# DMFX-1_v1_1.net
KiCad netlist of a schematic drawn in EAGLE
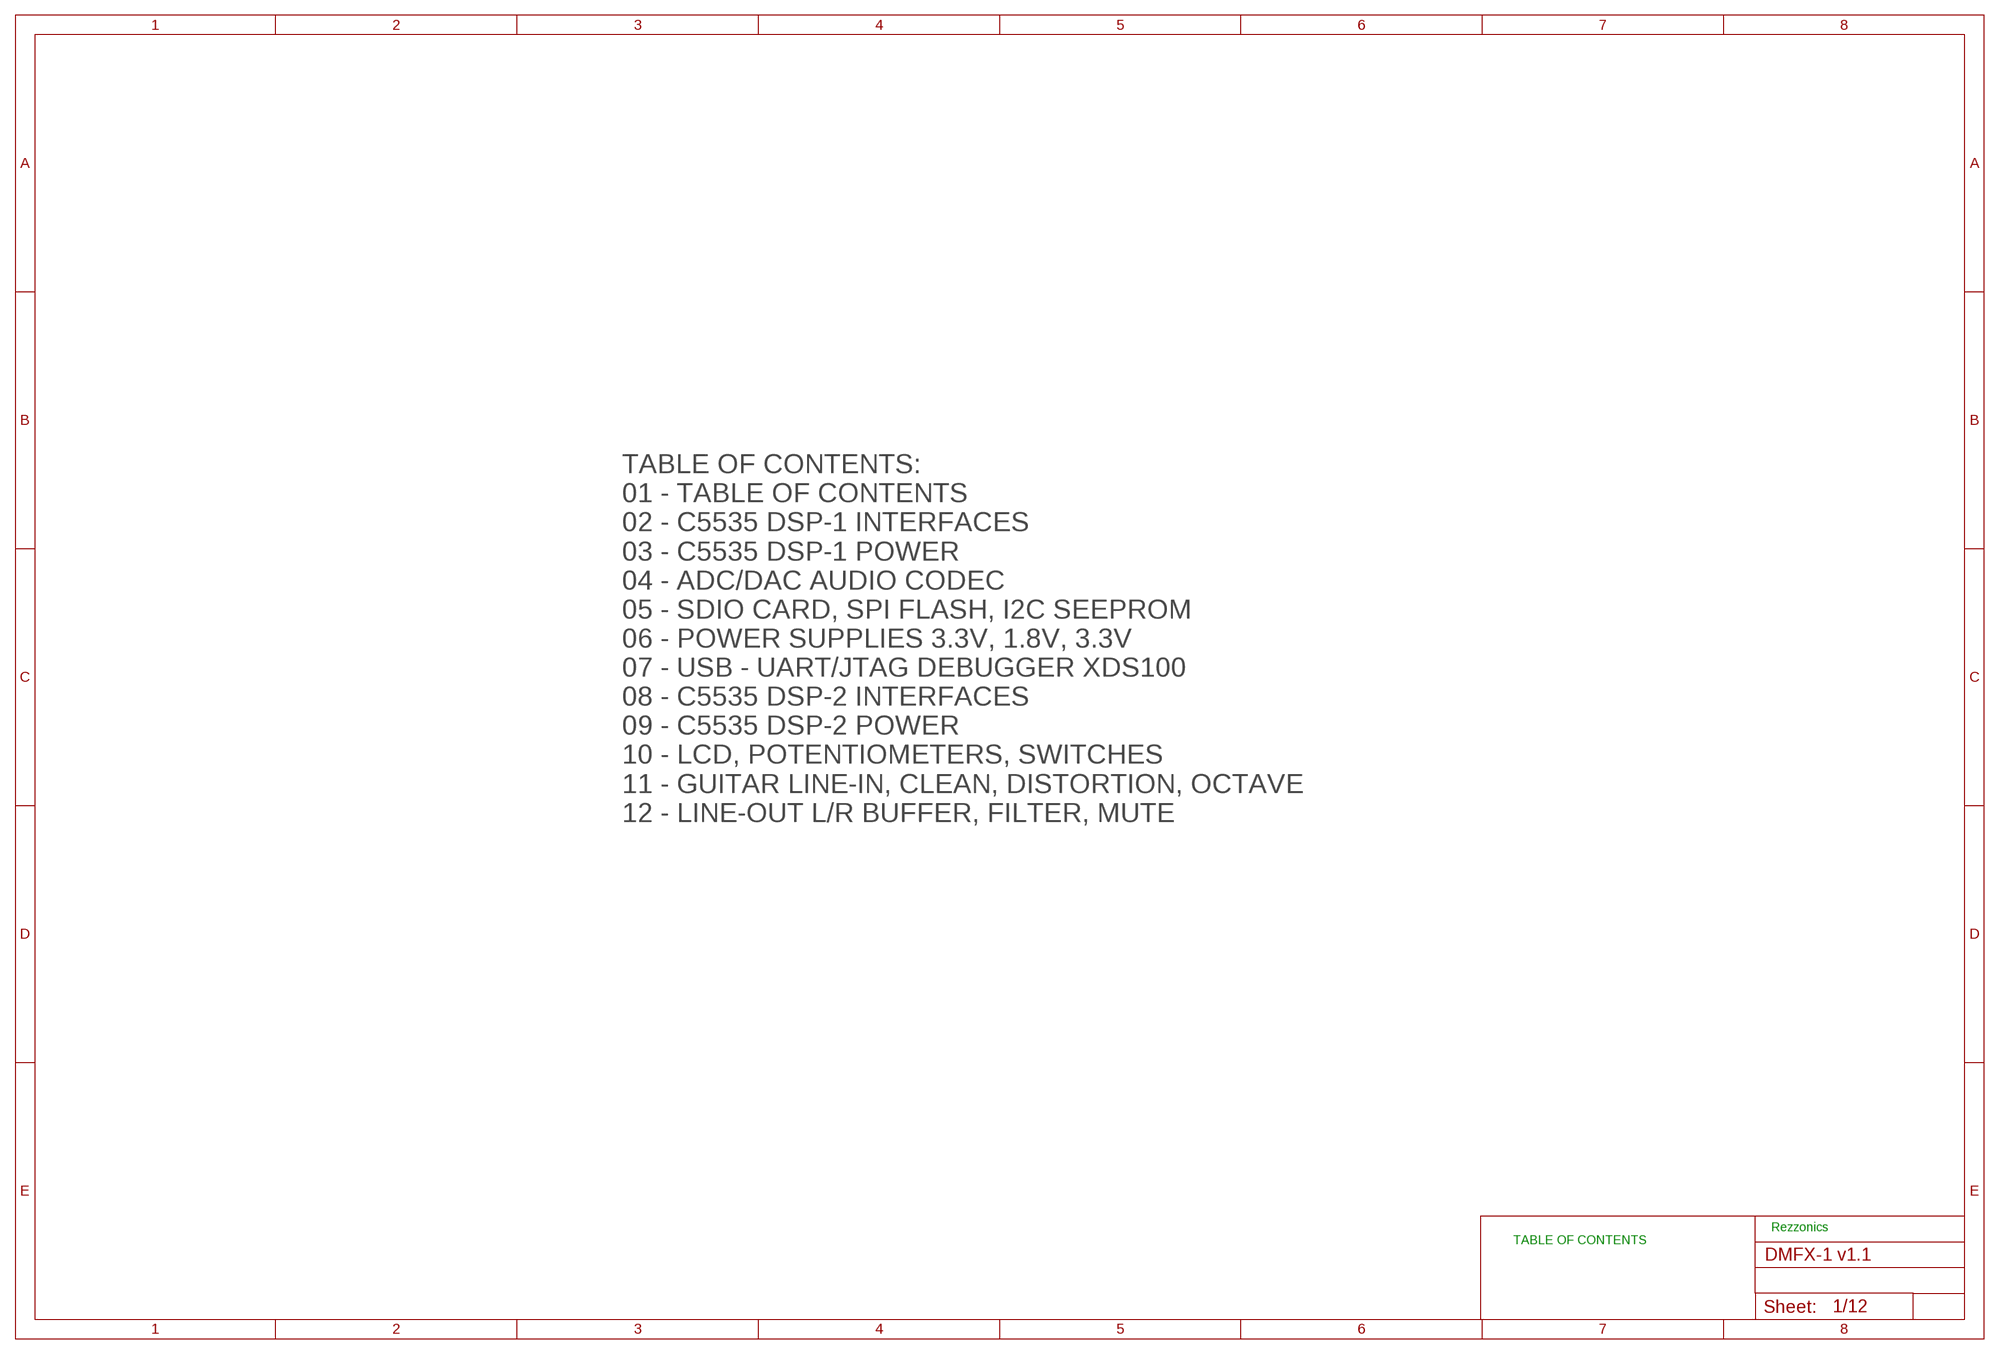
[diagram p0: schematic, sheet 1]
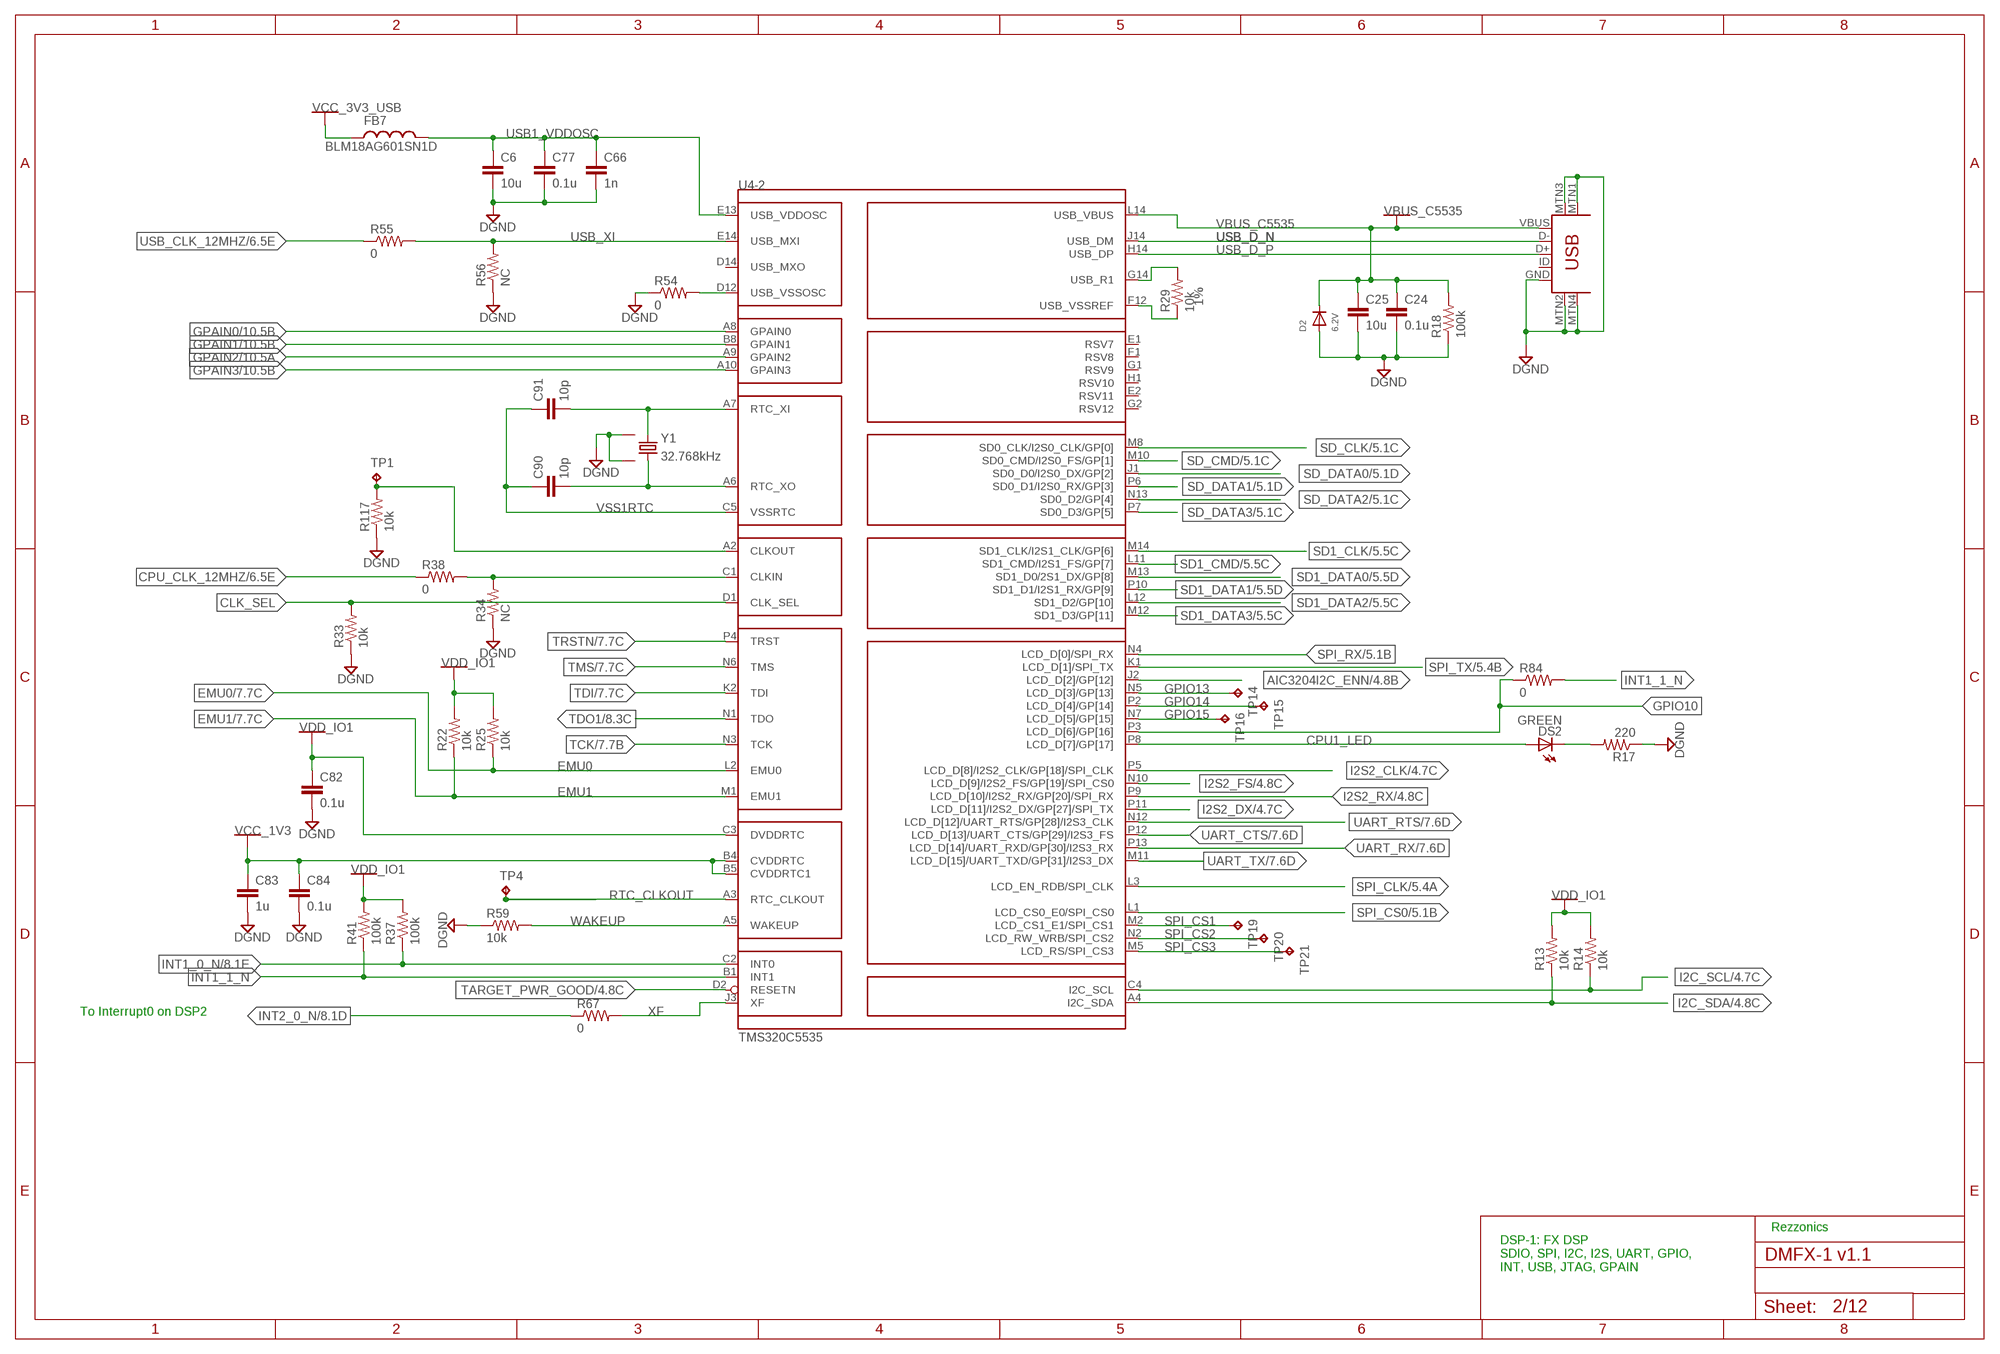
[diagram p1: schematic, sheet 2]
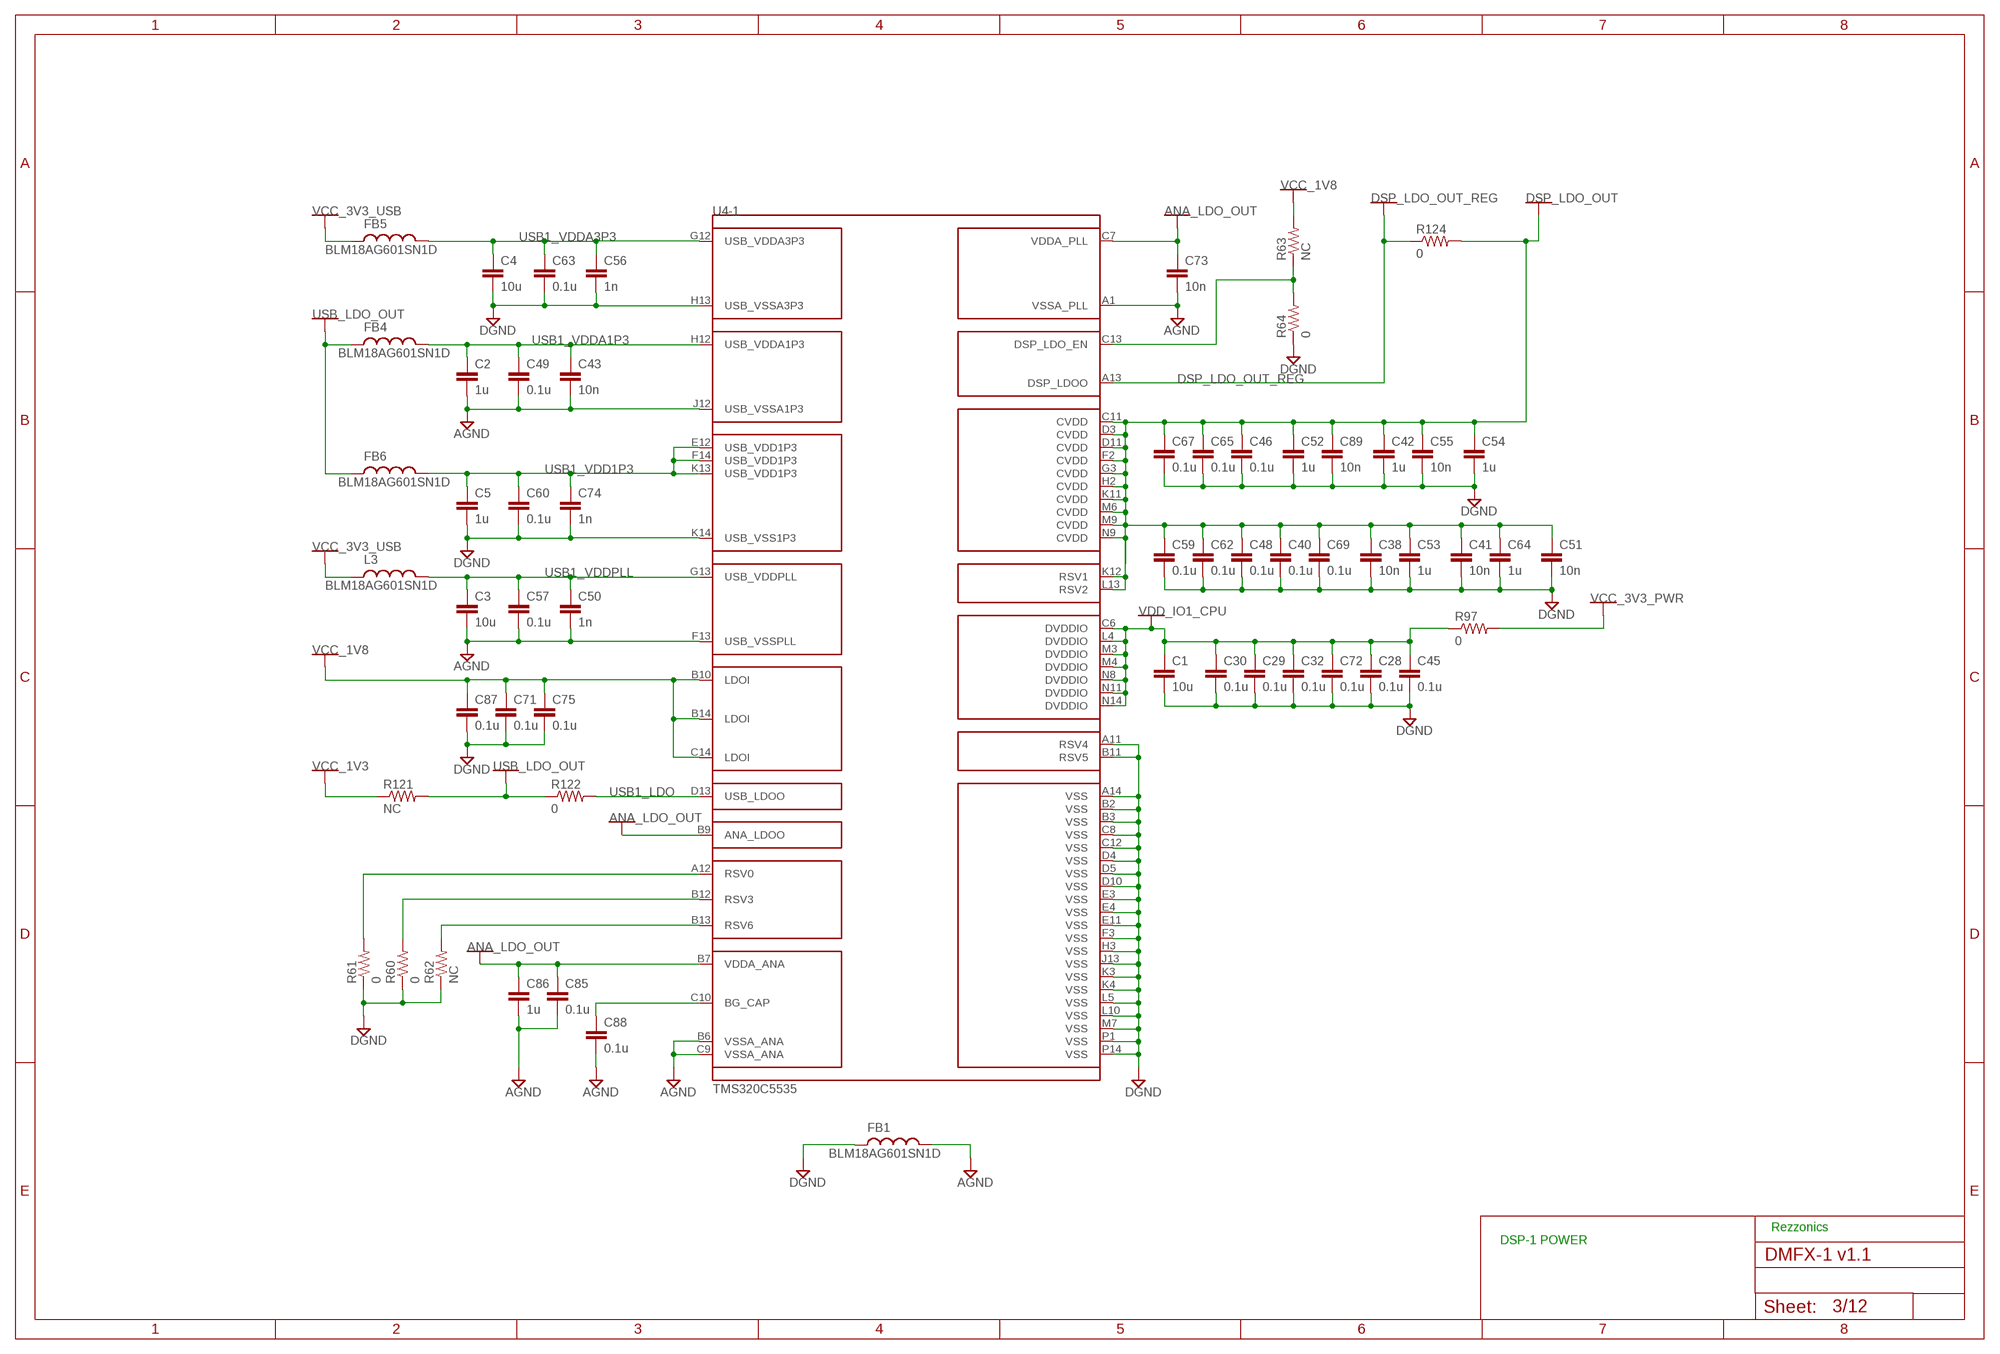
[diagram p2: schematic, sheet 3]
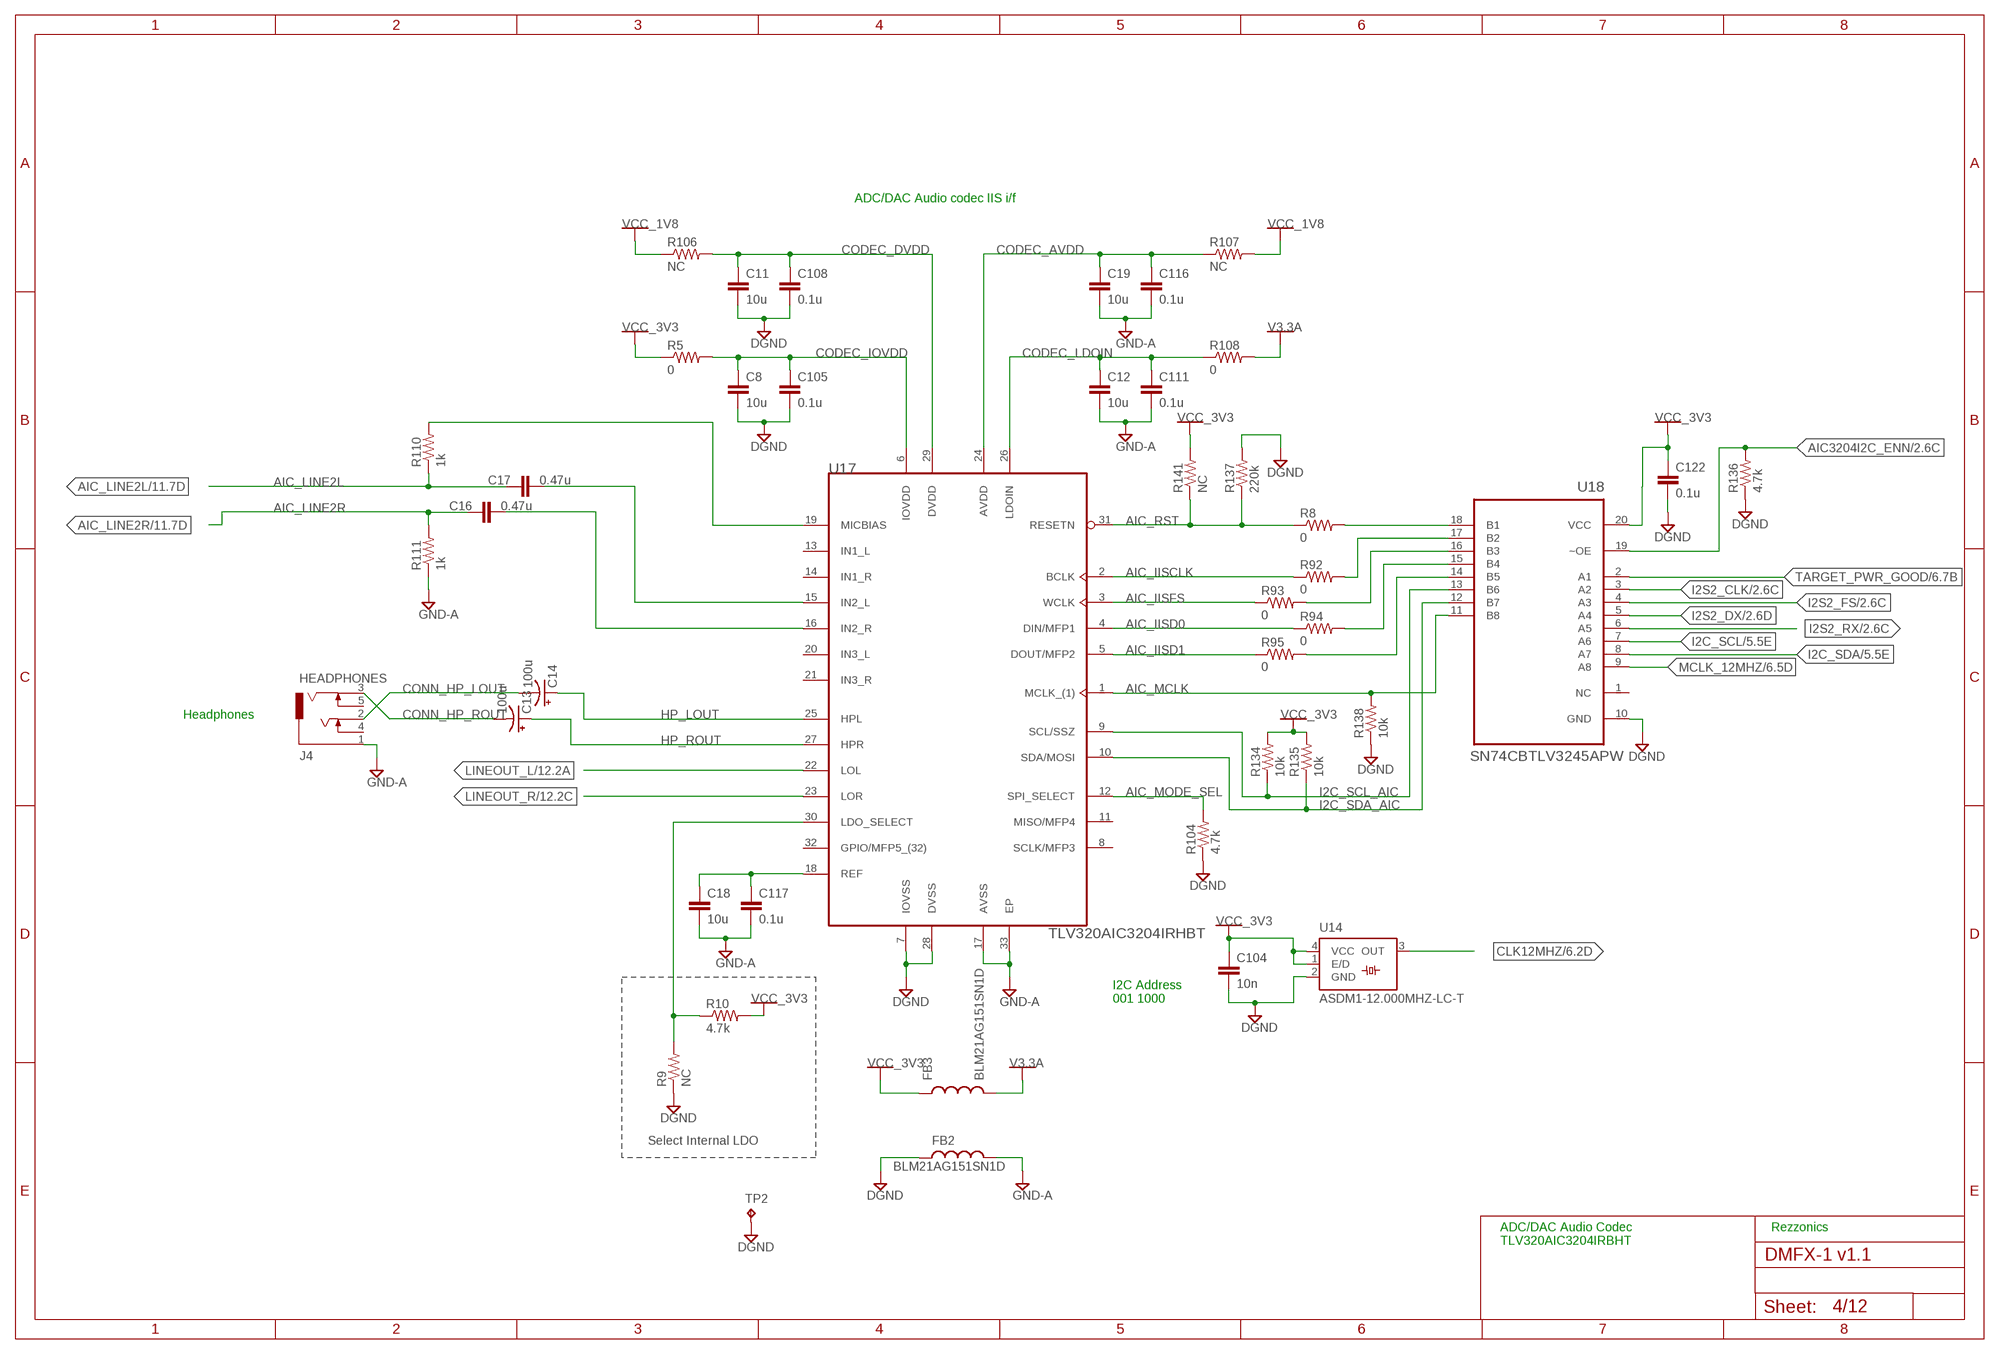
[diagram p3: schematic, sheet 4]
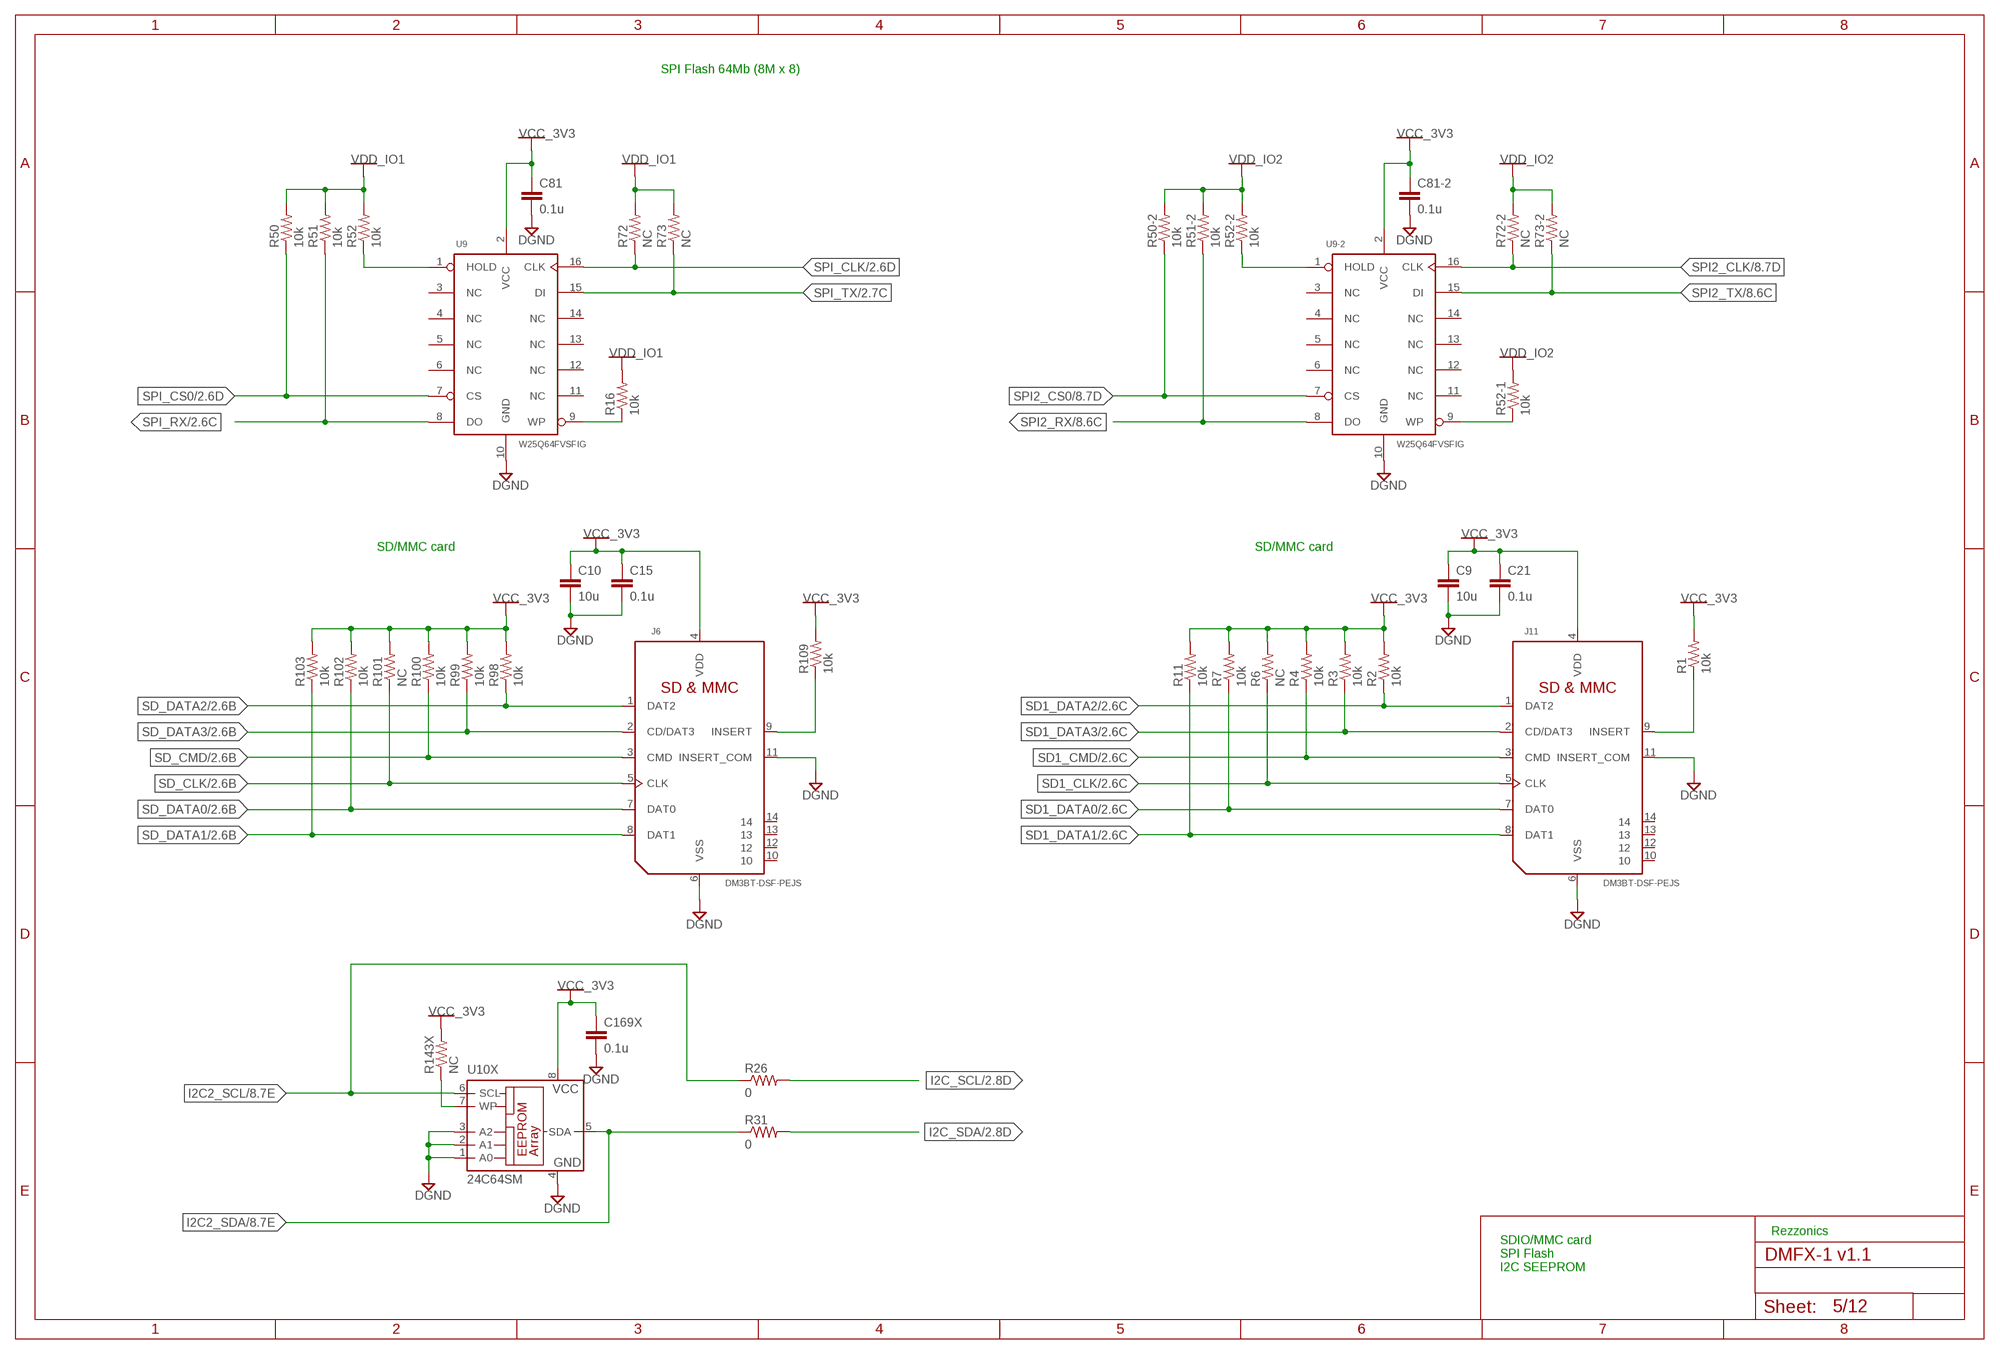
[diagram p4: schematic, sheet 5]
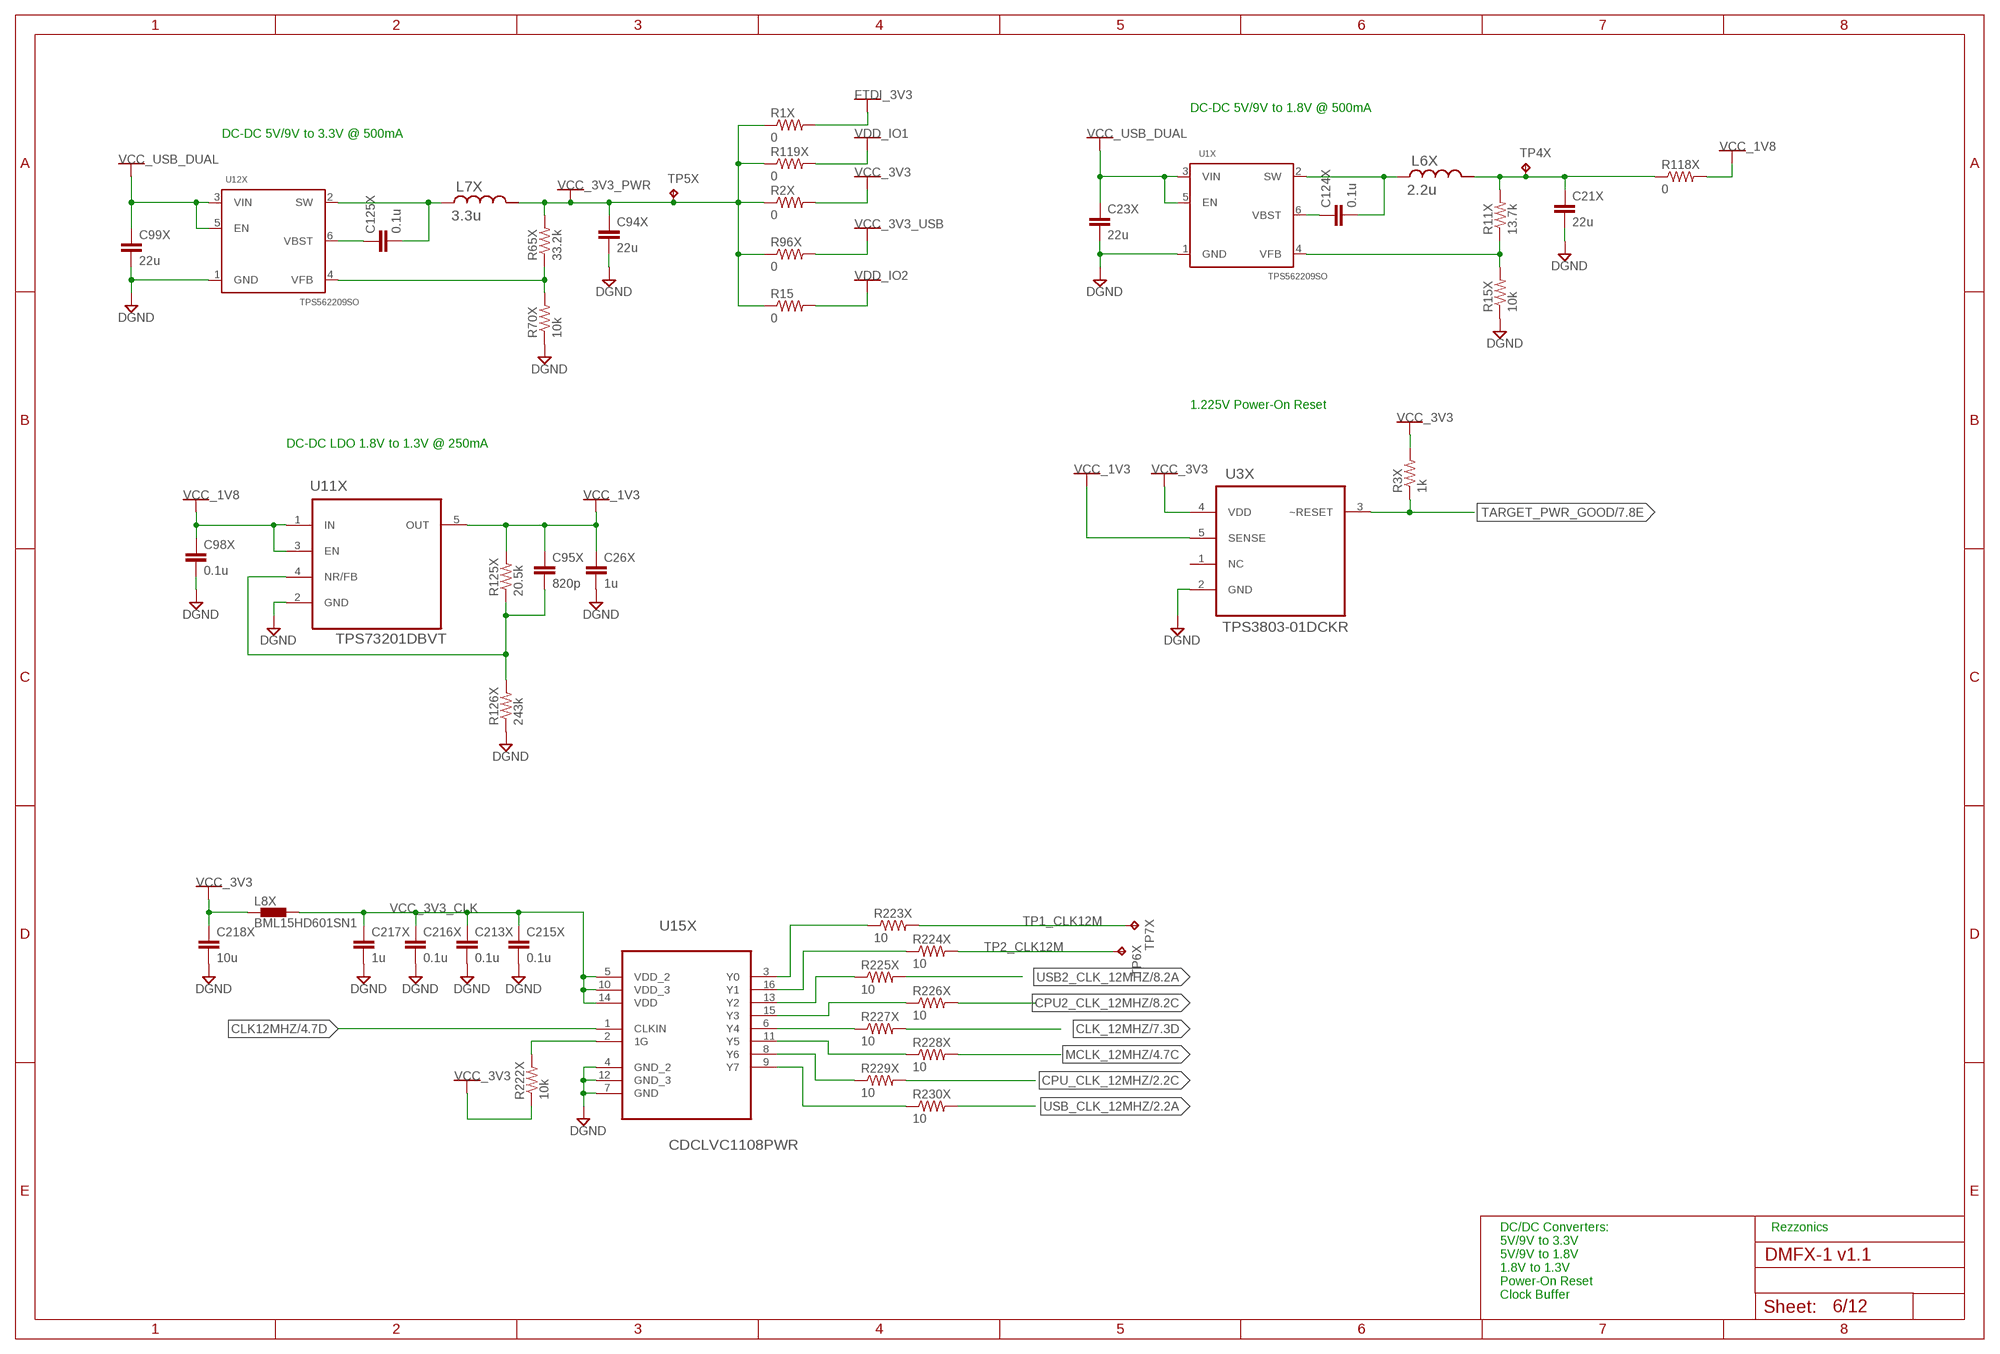
[diagram p5: schematic, sheet 6]
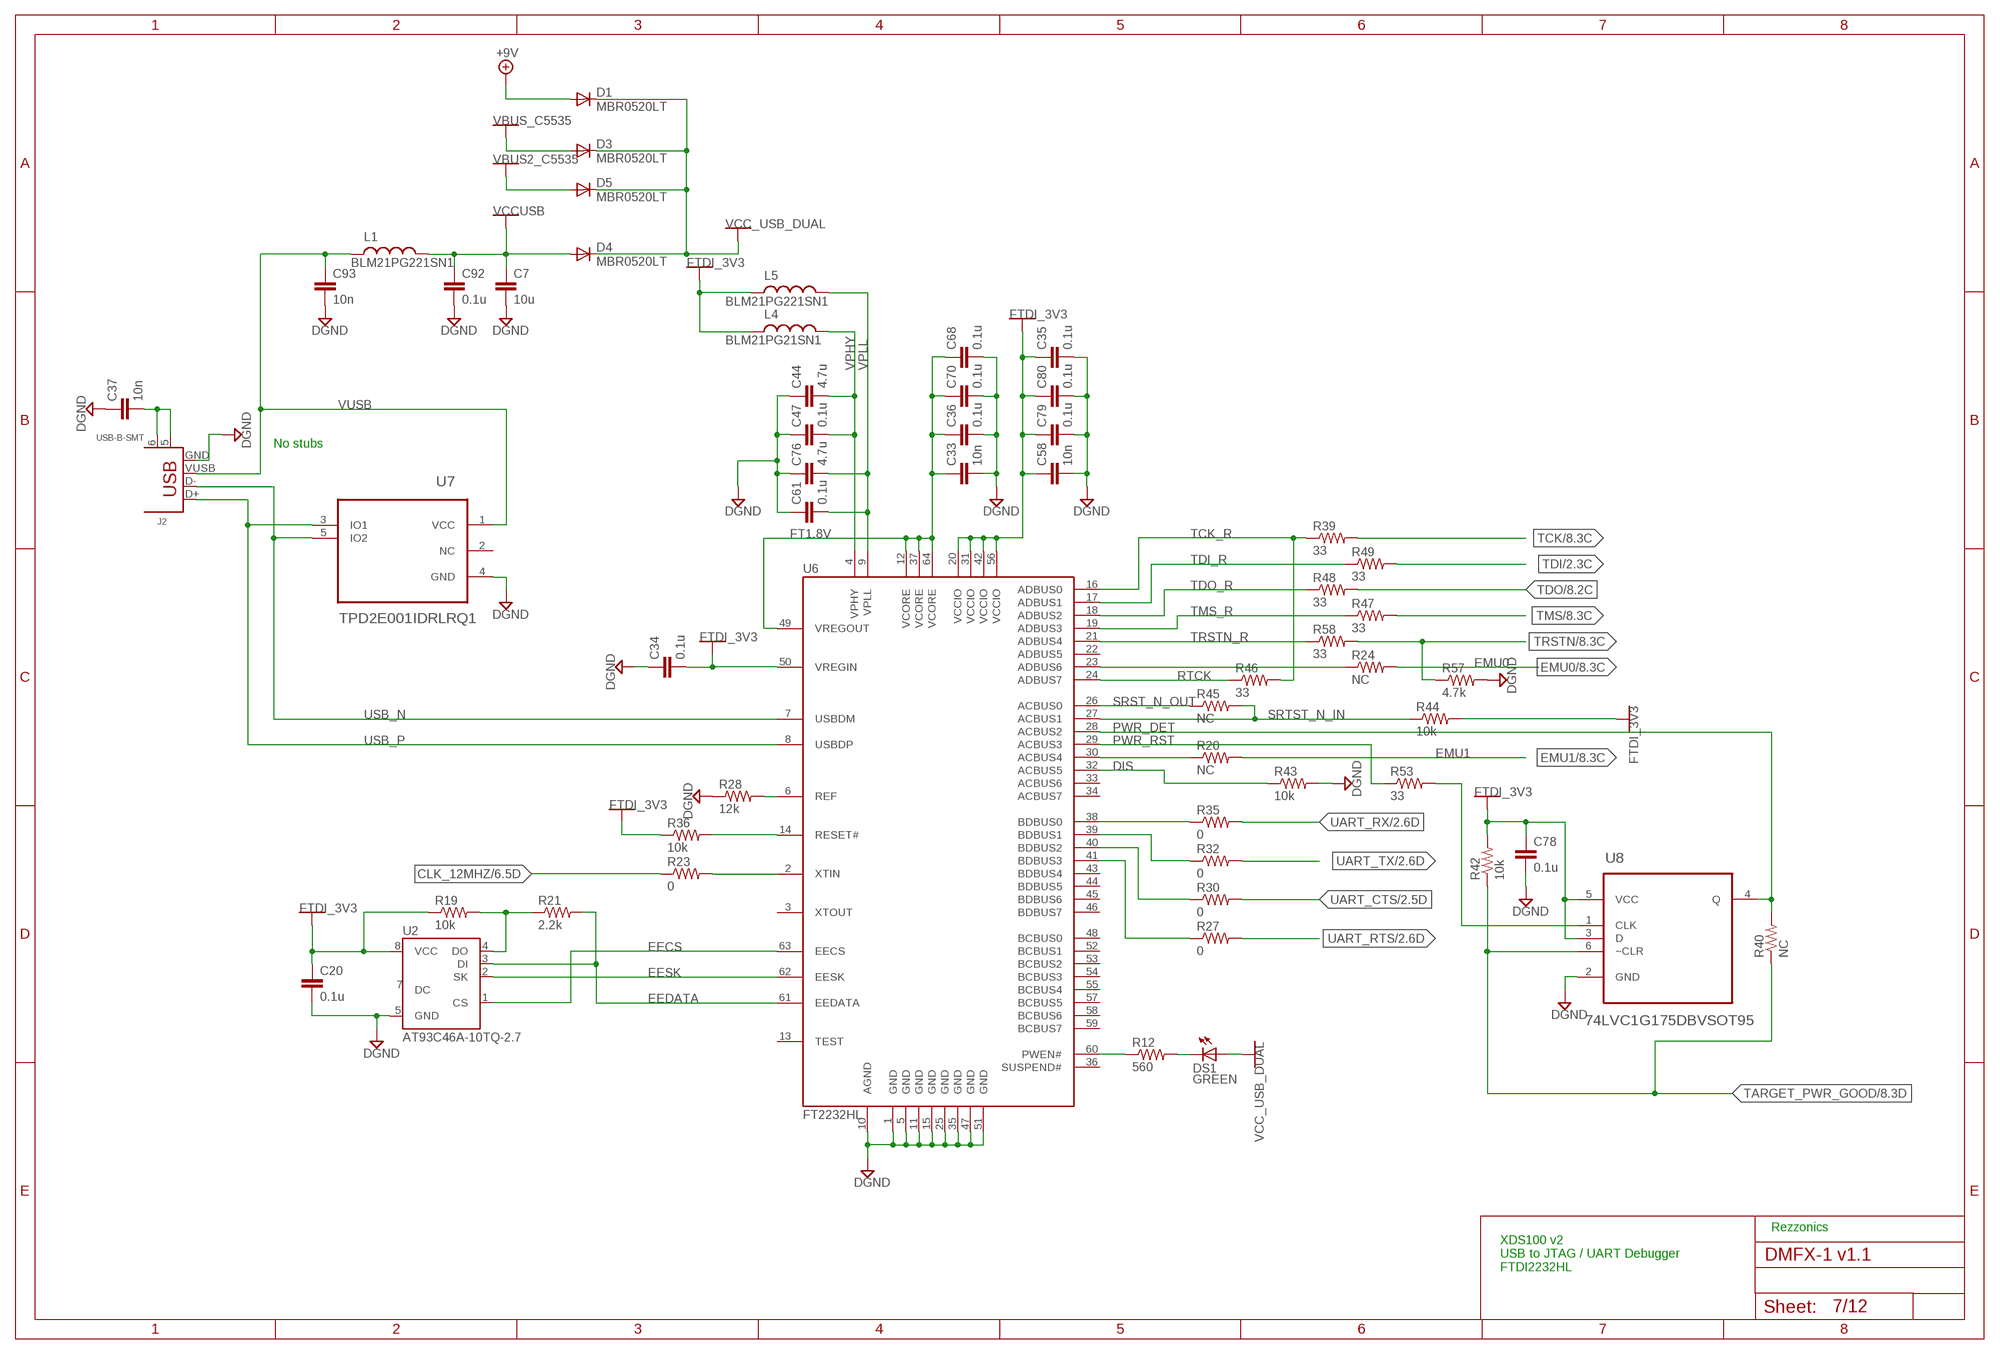
[diagram p6: schematic, sheet 7]
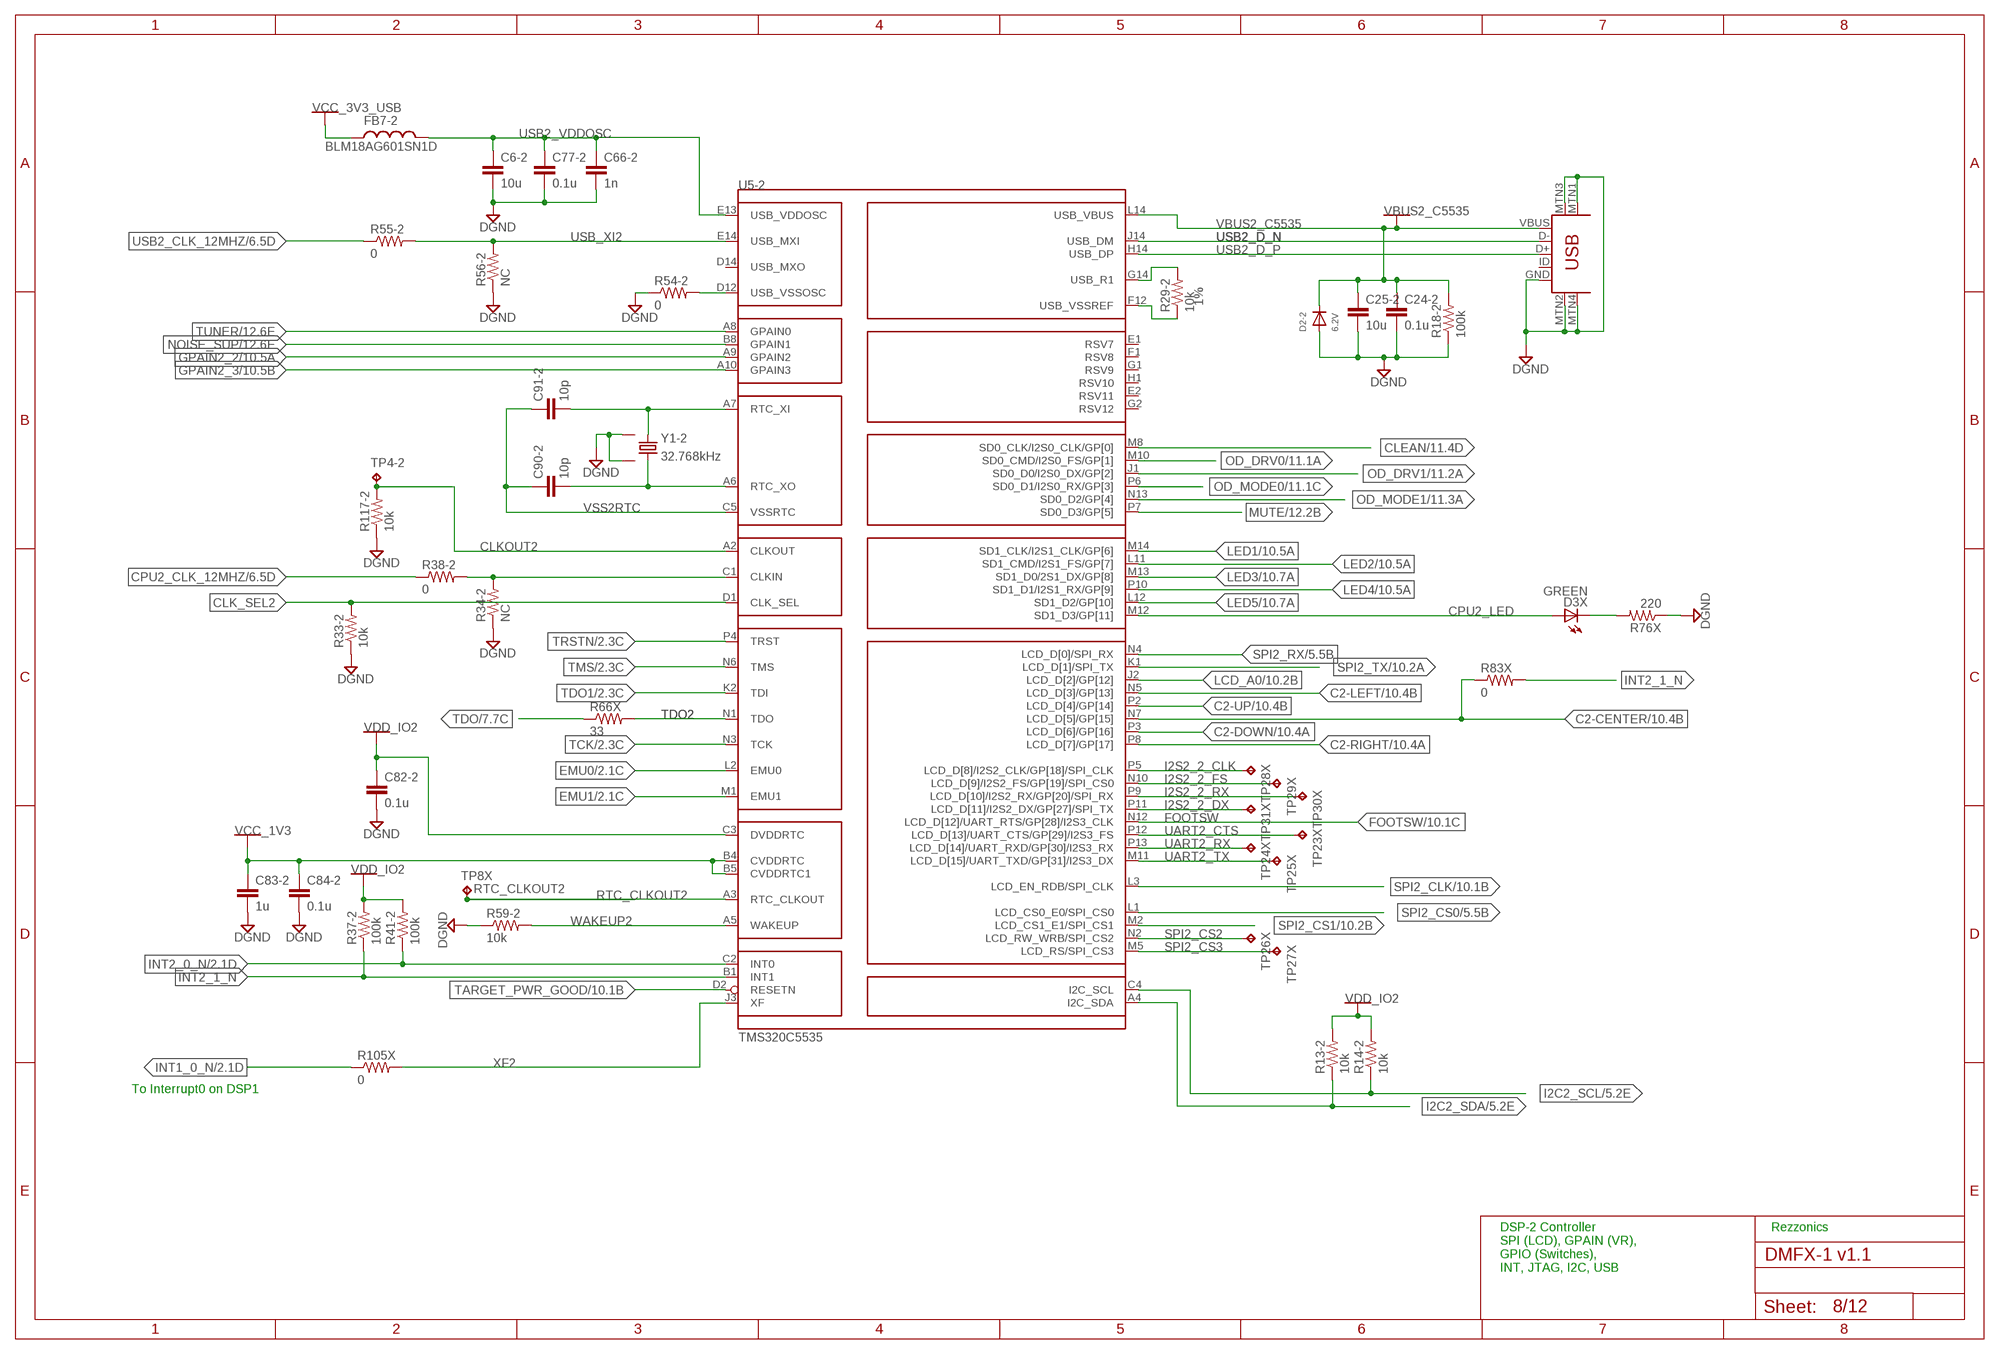
[diagram p7: schematic, sheet 8]
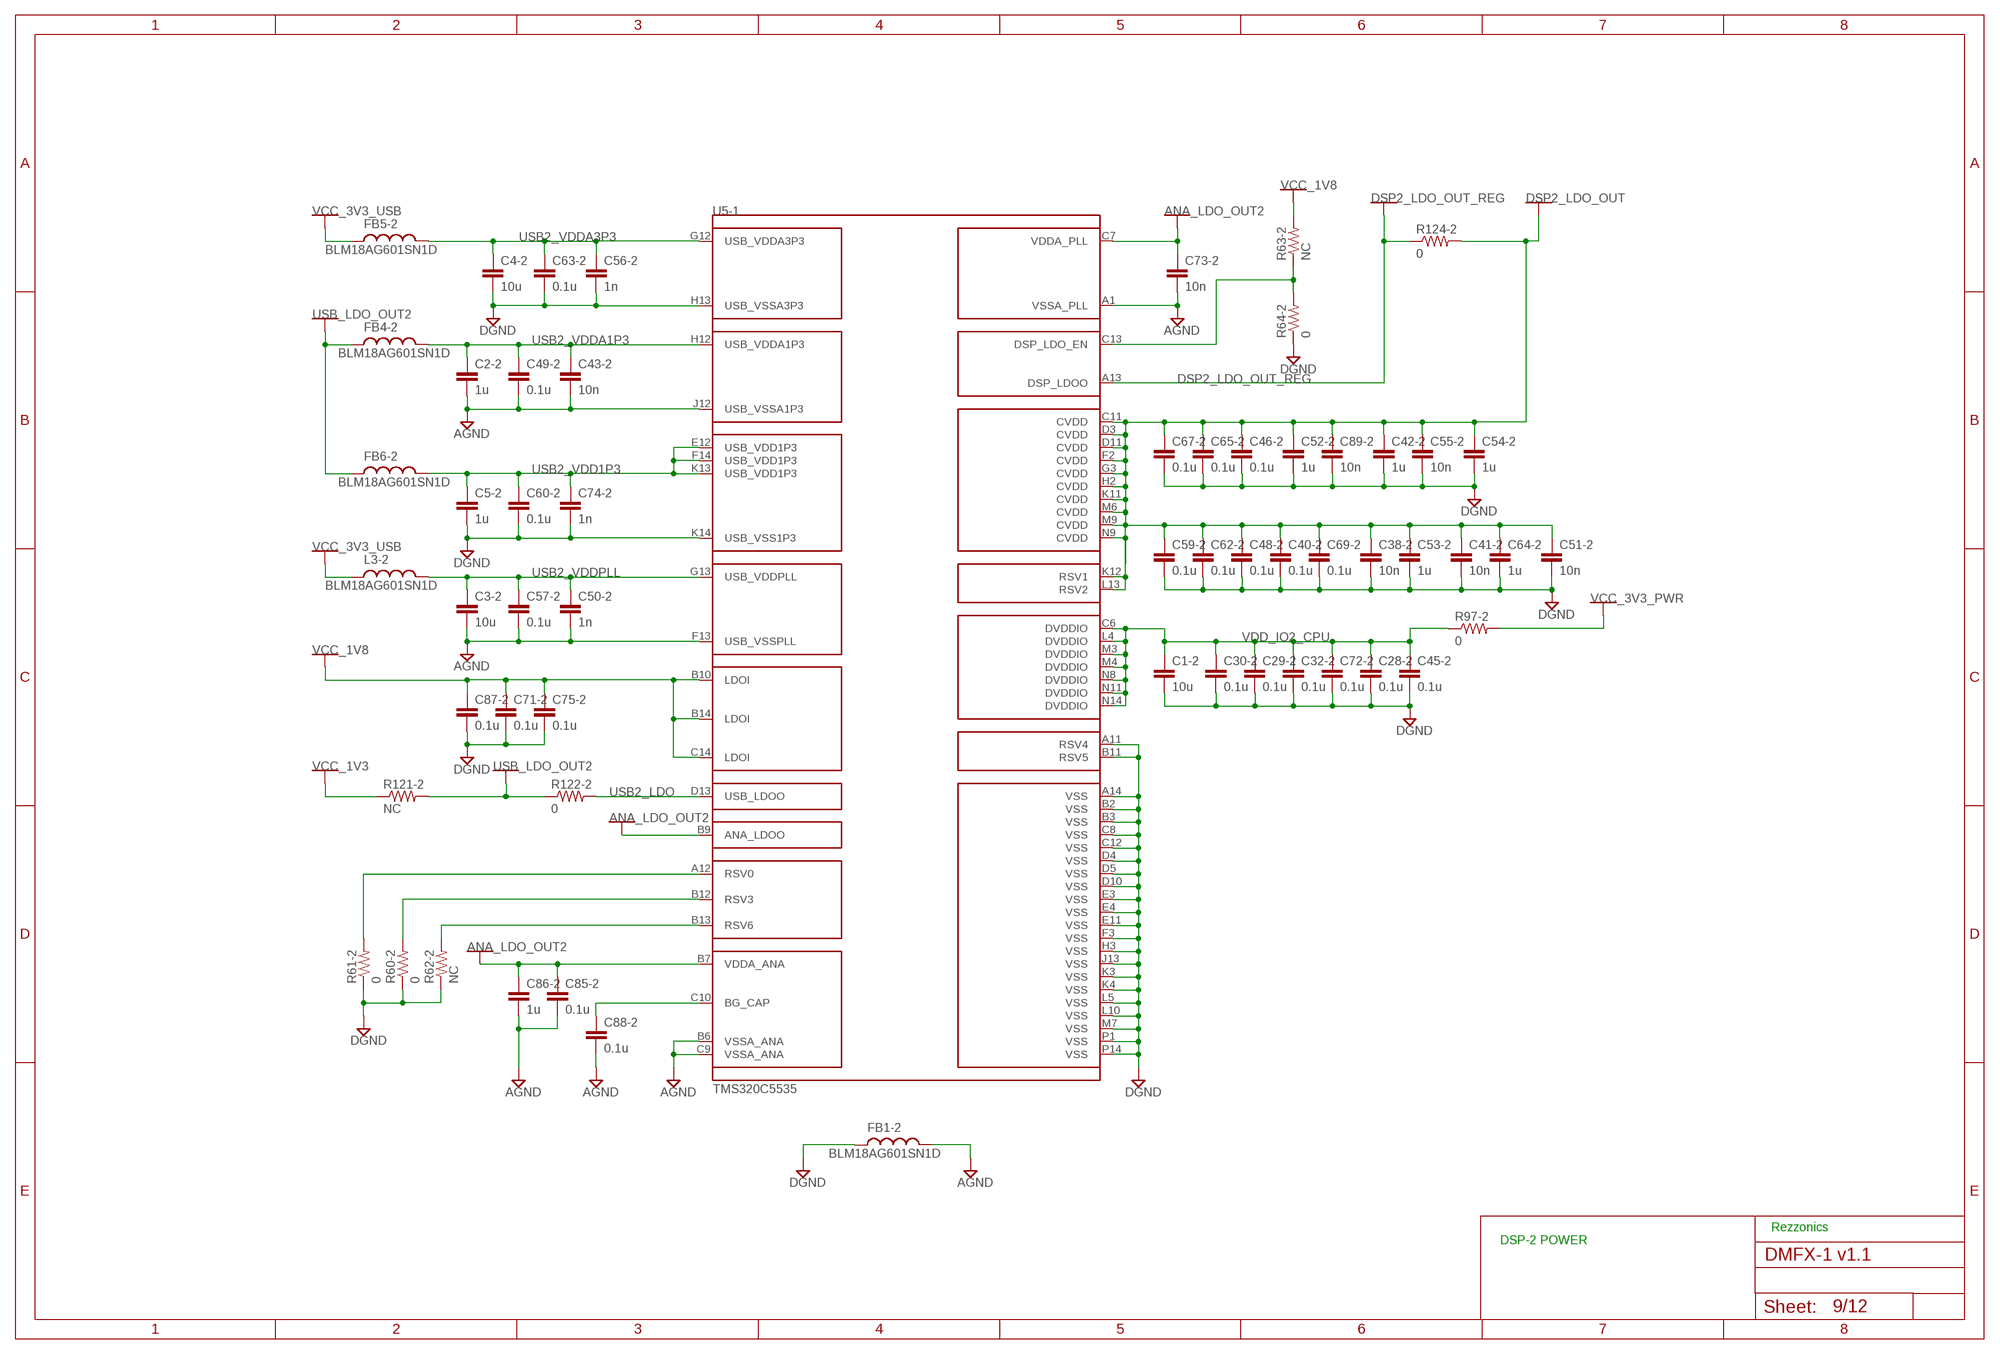
[diagram p8: schematic, sheet 9]
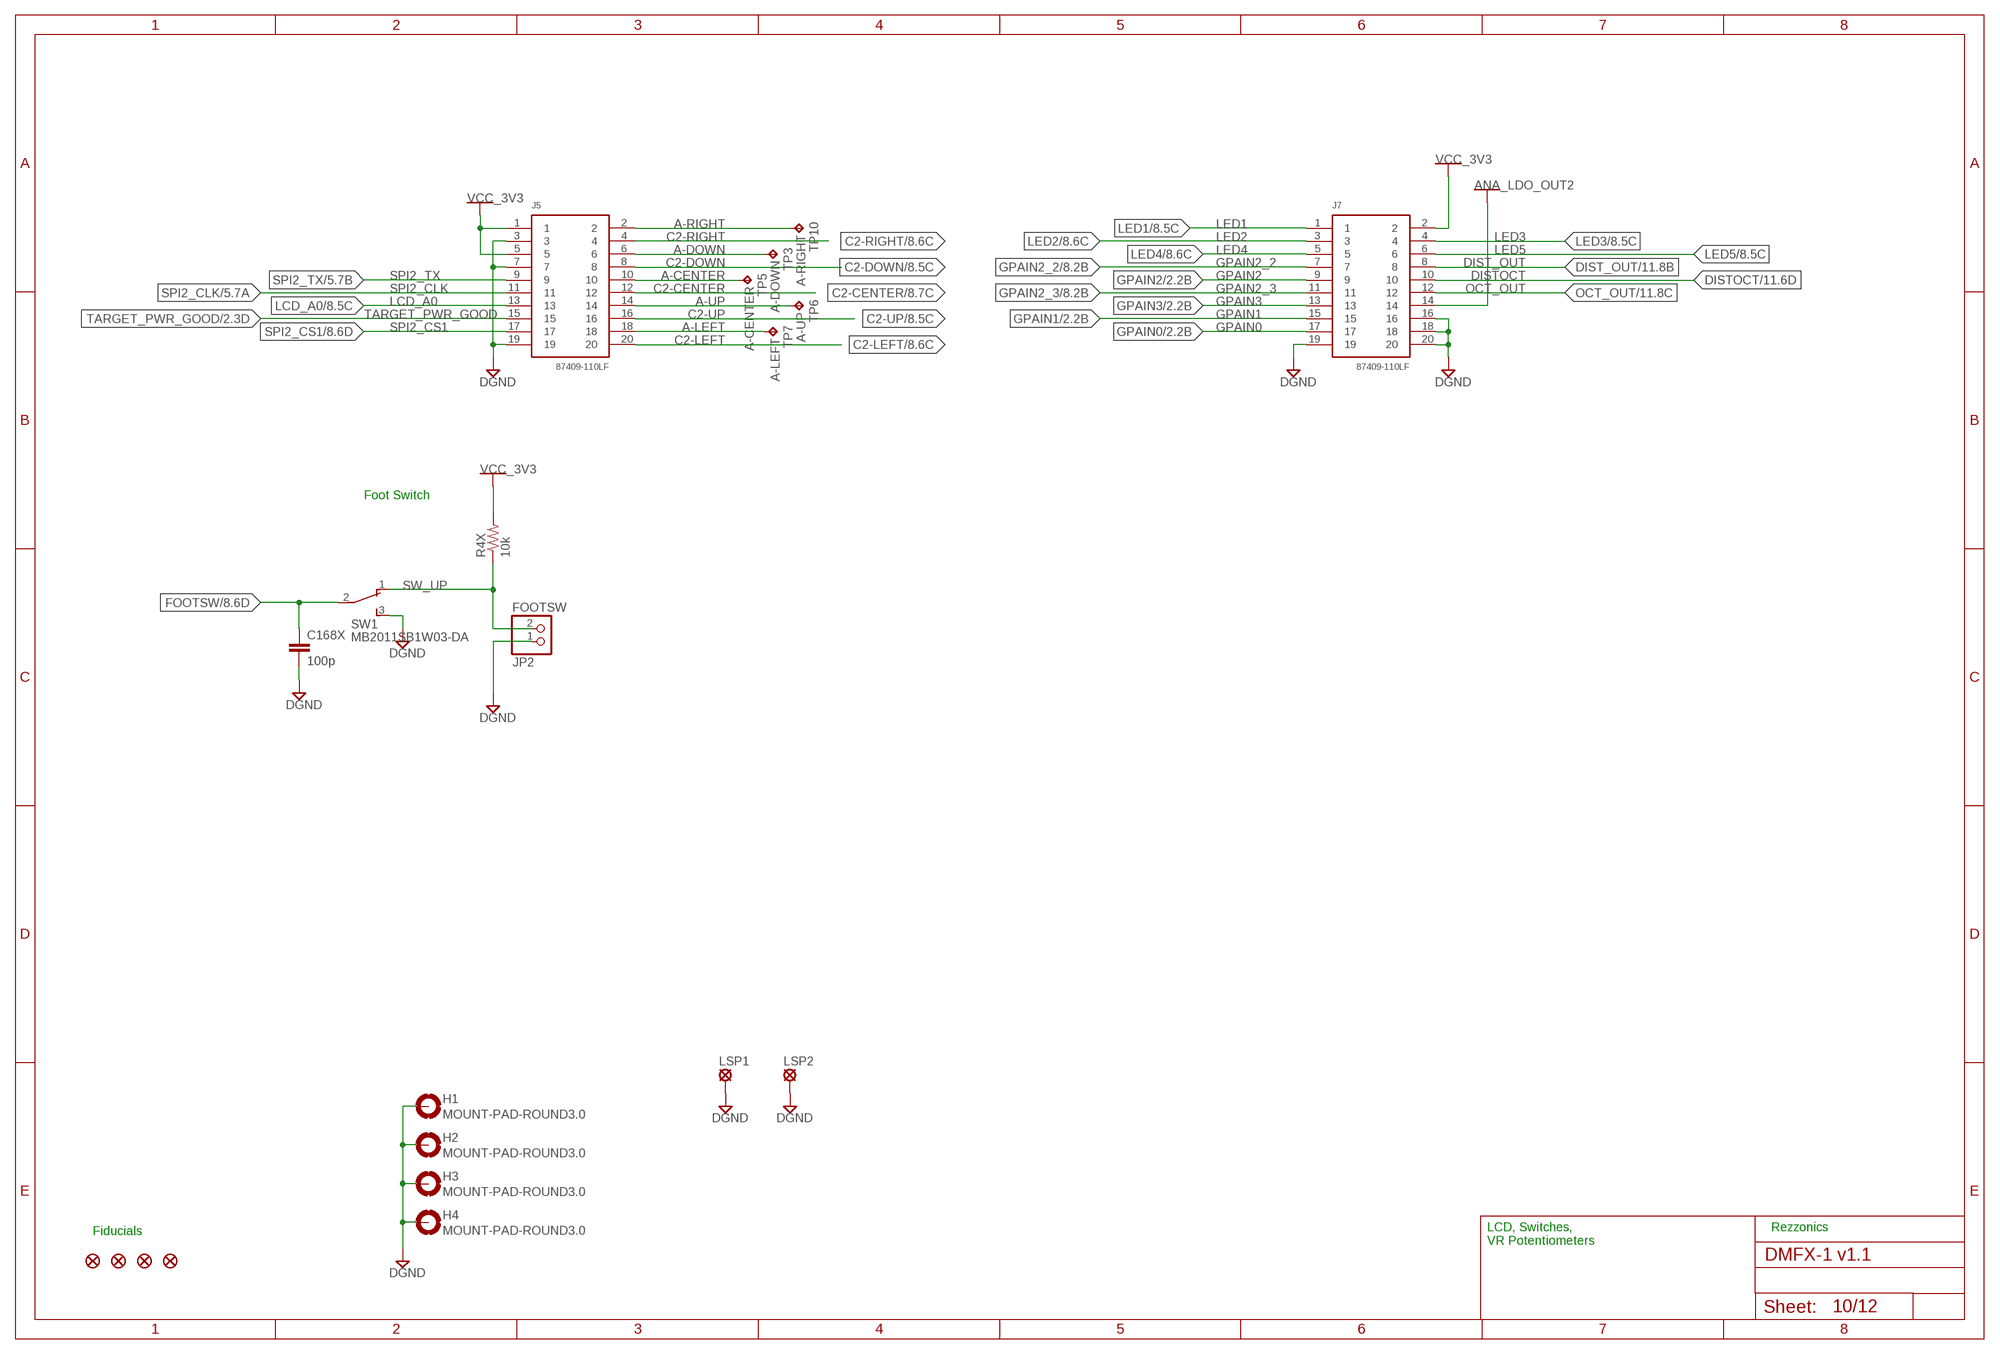
[diagram p9: schematic, sheet 10]
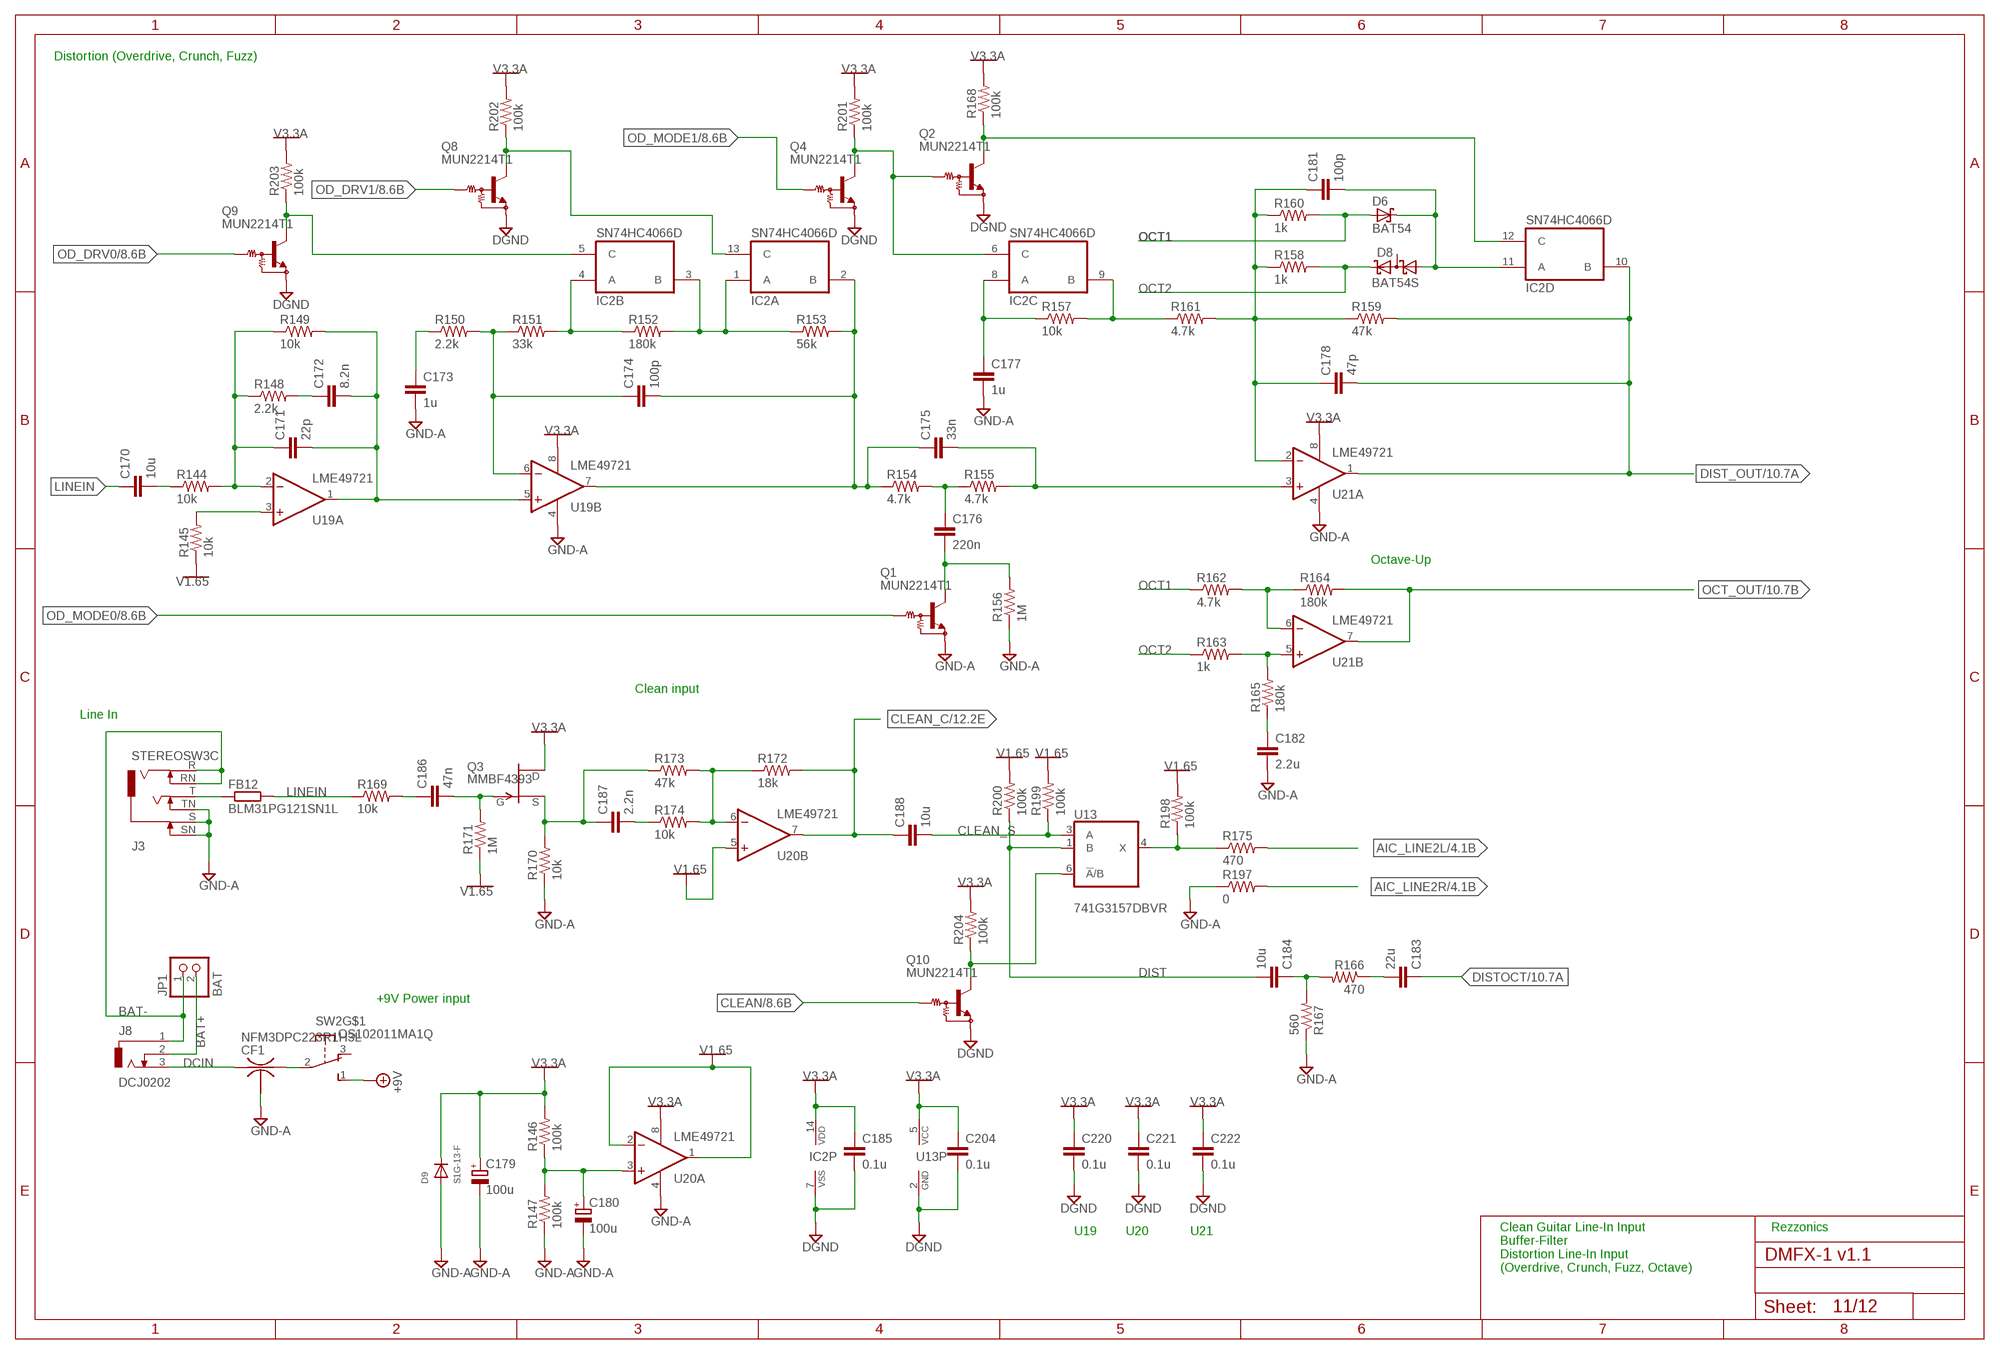
[diagram p10: schematic, sheet 11]
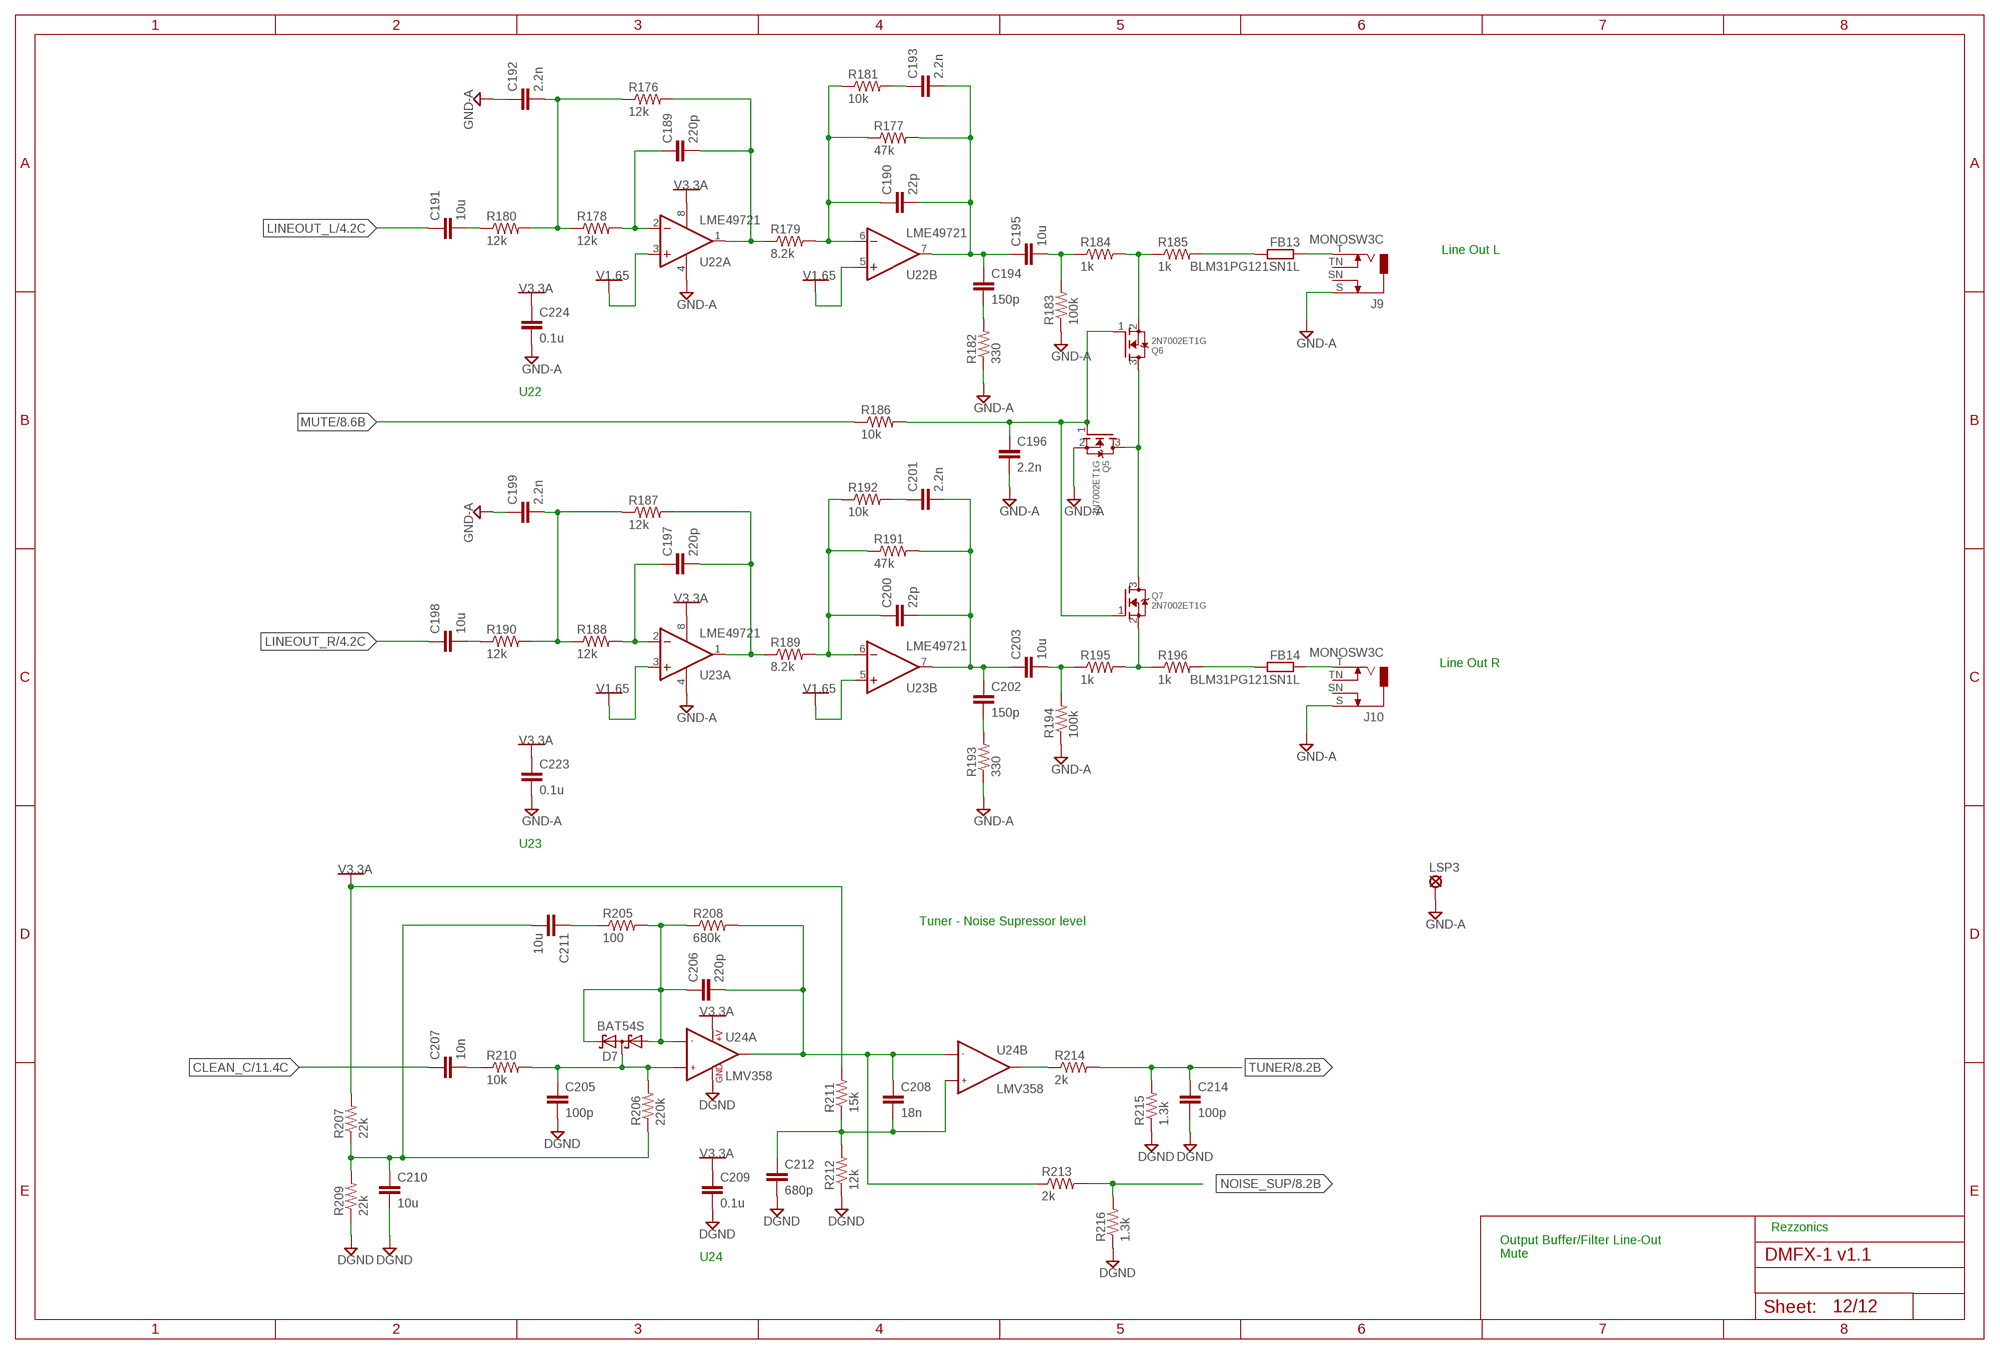
[diagram p11: schematic, sheet 12]

(export (version "E")
  (design (tool "Eeschema 10.0.6"))
  (components
    (comp (ref "C170")
      (value "10u")
      (footprint "eagle-import:C0805K")
      (fields (field (name "MPN") "GRM21BR71A106KA73L"))
      (libsource (lib "eagle-import") (part "C-EUC0805K"))
    )
    (comp (ref "C171")
      (value "22p")
      (footprint "eagle-import:0402-CAP")
      (fields (field (name "MPN") "GRM1555C2A220JA01D"))
      (libsource (lib "eagle-import") (part "CAP0402-CAP"))
    )
    (comp (ref "C172")
      (value "8.2n")
      (footprint "eagle-import:0402-CAP")
      (fields (field (name "MPN") "GRM155R71H822KA88D"))
      (libsource (lib "eagle-import") (part "CAP0402-CAP"))
    )
    (comp (ref "C173")
      (value "1u")
      (footprint "eagle-import:0402-CAP")
      (fields (field (name "MPN") "GRM155R70J105KA12D"))
      (libsource (lib "eagle-import") (part "CAP0402-CAP"))
    )
    (comp (ref "C174")
      (value "100p")
      (footprint "eagle-import:0402-CAP")
      (fields (field (name "MPN") "GRM1555C1H101FA01J"))
      (libsource (lib "eagle-import") (part "CAP0402-CAP"))
    )
    (comp (ref "C175")
      (value "33n")
      (footprint "eagle-import:0402-CAP")
      (fields (field (name "MPN") "GRM155R71E333KA88J"))
      (libsource (lib "eagle-import") (part "CAP0402-CAP"))
    )
    (comp (ref "C176")
      (value "220n")
      (footprint "eagle-import:0402-CAP")
      (fields (field (name "MPN") "GRM155R71C224KA12D"))
      (libsource (lib "eagle-import") (part "CAP0402-CAP"))
    )
    (comp (ref "C177")
      (value "1u")
      (footprint "eagle-import:0402-CAP")
      (fields (field (name "MPN") "GRM155R70J105KA12D"))
      (libsource (lib "eagle-import") (part "CAP0402-CAP"))
    )
    (comp (ref "C178")
      (value "47p")
      (footprint "eagle-import:0402-CAP")
      (fields (field (name "MPN") "GRM1555C1H470FA01D"))
      (libsource (lib "eagle-import") (part "CAP0402-CAP"))
    )
    (comp (ref "C179")
      (value "100u")
      (footprint "eagle-import:PANASONIC_D")
      (fields (field (name "MF") "Cornell-Dubilier") (field (name "MPN") "AVE107M25X16T-F"))
      (libsource (lib "eagle-import") (part "CPOL-EUD"))
    )
    (comp (ref "C180")
      (value "100u")
      (footprint "eagle-import:PANASONIC_D")
      (fields (field (name "MF") "Cornell Dubilier") (field (name "MPN") "AVE107M25X16T-F"))
      (libsource (lib "eagle-import") (part "CPOL-EUD"))
    )
    (comp (ref "C181")
      (value "100p")
      (footprint "eagle-import:0402-CAP")
      (fields (field (name "MPN") "GRM1555C1H101FA01J"))
      (libsource (lib "eagle-import") (part "CAP0402-CAP"))
    )
    (comp (ref "C182")
      (value "2.2u")
      (footprint "eagle-import:0402-CAP")
      (fields (field (name "MPN") "GRM155R60J225ME15D"))
      (libsource (lib "eagle-import") (part "CAP0402-CAP"))
    )
    (comp (ref "C183")
      (value "22u")
      (footprint "eagle-import:C1206K")
      (fields (field (name "MPN") "GRM31CR71A226KE15L"))
      (libsource (lib "eagle-import") (part "C-EUC1206K"))
    )
    (comp (ref "C184")
      (value "10u")
      (footprint "eagle-import:C0805K")
      (fields (field (name "MPN") "GRM21BR71A106KA73L"))
      (libsource (lib "eagle-import") (part "C-EUC0805K"))
    )
    (comp (ref "C185")
      (value "0.1u")
      (footprint "eagle-import:C0402K")
      (fields (field (name "MPN") "GRM155R71C104JA88D"))
      (libsource (lib "eagle-import") (part "resistor_C-EUC0402K"))
    )
    (comp (ref "C186")
      (value "47n")
      (footprint "eagle-import:0402-CAP")
      (fields (field (name "MPN") "GRM155R71H473KE14D"))
      (libsource (lib "eagle-import") (part "CAP0402-CAP"))
    )
    (comp (ref "C187")
      (value "2.2n")
      (footprint "eagle-import:0402-CAP")
      (fields (field (name "MPN") "GRM155R71H222JA01J"))
      (libsource (lib "eagle-import") (part "CAP0402-CAP"))
    )
    (comp (ref "C188")
      (value "10u")
      (footprint "eagle-import:C0805K")
      (fields (field (name "MPN") "GRM21BR71A106KA73L"))
      (libsource (lib "eagle-import") (part "C-EUC0805K"))
    )
    (comp (ref "C204")
      (value "0.1u")
      (footprint "eagle-import:C0402K")
      (fields (field (name "MPN") "GRM155R71C104JA88D"))
      (libsource (lib "eagle-import") (part "resistor_C-EUC0402K"))
    )
    (comp (ref "C220")
      (value "0.1u")
      (footprint "eagle-import:C0402K")
      (fields (field (name "MPN") "GRM155R71C104JA88D"))
      (libsource (lib "eagle-import") (part "resistor_C-EUC0402K"))
    )
    (comp (ref "C221")
      (value "0.1u")
      (footprint "eagle-import:C0402K")
      (fields (field (name "MPN") "GRM155R71C104JA88D"))
      (libsource (lib "eagle-import") (part "resistor_C-EUC0402K"))
    )
    (comp (ref "C222")
      (value "0.1u")
      (footprint "eagle-import:C0402K")
      (fields (field (name "MPN") "GRM155R71C104JA88D"))
      (libsource (lib "eagle-import") (part "resistor_C-EUC0402K"))
    )
    (comp (ref "CF1")
      (value "NFM3DPC223R1H3L")
      (footprint "eagle-import:NFM3DC")
      (fields
        (field (name "MF") "FARNELL")
        (field (name "MPN") "NFM3DCC470U1H3L")
        (field (name "MPN_1") "NFM3DPC223R1H3L")
      )
      (libsource (lib "eagle-import") (part "NFM3DC"))
    )
    (comp (ref "D6")
      (value "BAT54")
      (footprint "eagle-import:SOT23")
      (fields (field (name "MPN") "BAT54LT1G"))
      (libsource (lib "eagle-import") (part "BAT54"))
    )
    (comp (ref "D8")
      (value "BAT54S")
      (footprint "eagle-import:SOT23")
      (fields (field (name "MPN") "BAT54SLT1G"))
      (libsource (lib "eagle-import") (part "BAT54S"))
    )
    (comp (ref "D9")
      (value "S1G-13-F")
      (footprint "eagle-import:SMADIODE")
      (libsource (lib "eagle-import") (part "DIODESMA"))
    )
    (comp (ref "FB12")
      (value "BLM31PG121SN1L")
      (footprint "eagle-import:R1206")
      (libsource (lib "eagle-import") (part "R-EU_R1206"))
    )
    (comp (ref "IC2")
      (value "SN74HC4066D")
      (footprint "eagle-import:SO14")
      (fields (field (name "MPN") "SN74HC4066DR"))
      (libsource (lib "eagle-import") (part "4066D"))
    )
    (comp (ref "J3")
      (value "STEREOSW3C")
      (footprint "eagle-import:NEUTRIK-NMJ6HCD2")
      (fields (field (name "MPN") "NMJ6HCD2"))
      (libsource (lib "eagle-import") (part "STEREOSW3C"))
    )
    (comp (ref "J8")
      (value "DCJ0202")
      (footprint "eagle-import:DCJ0202")
      (fields (field (name "MF") "Kobiconn") (field (name "MPN") "PJ-202A"))
      (libsource (lib "eagle-import") (part "DCJ0202"))
    )
    (comp (ref "JP1")
      (value "BAT")
      (footprint "eagle-import:1X02")
      (fields (field (name "MF") "3M") (field (name "MPN") "929834-01-02-RK"))
      (libsource (lib "eagle-import") (part "PINHD-1X2"))
    )
    (comp (ref "Q1")
      (value "MUN2214T1")
      (footprint "eagle-import:SC59-BEC")
      (fields (field (name "MPN") "MUN2214T1G"))
      (libsource (lib "eagle-import") (part "MUN2214T1"))
    )
    (comp (ref "Q2")
      (value "MUN2214T1")
      (footprint "eagle-import:SC59-BEC")
      (fields (field (name "MPN") "MUN2214T1G"))
      (libsource (lib "eagle-import") (part "MUN2214T1"))
    )
    (comp (ref "Q3")
      (value "MMBF4393")
      (footprint "eagle-import:SOT23")
      (libsource (lib "eagle-import") (part "?548SST6"))
    )
    (comp (ref "Q4")
      (value "MUN2214T1")
      (footprint "eagle-import:SC59-BEC")
      (fields (field (name "MPN") "MUN2214T1G"))
      (libsource (lib "eagle-import") (part "MUN2214T1"))
    )
    (comp (ref "Q8")
      (value "MUN2214T1")
      (footprint "eagle-import:SC59-BEC")
      (fields (field (name "MPN") "MUN2214T1G"))
      (libsource (lib "eagle-import") (part "MUN2214T1"))
    )
    (comp (ref "Q9")
      (value "MUN2214T1")
      (footprint "eagle-import:SC59-BEC")
      (fields (field (name "MPN") "MUN2214T1G"))
      (libsource (lib "eagle-import") (part "MUN2214T1"))
    )
    (comp (ref "Q10")
      (value "MUN2214T1")
      (footprint "eagle-import:SC59-BEC")
      (fields (field (name "MPN") "MUN2214T1G"))
      (libsource (lib "eagle-import") (part "MUN2214T1"))
    )
    (comp (ref "R144")
      (value "10k")
      (footprint "eagle-import:0402-RES")
      (fields (field (name "MPN") "ERJ-2RKF1002X"))
      (libsource (lib "eagle-import") (part "RESISTOR0402-RES"))
    )
    (comp (ref "R145")
      (value "10k")
      (footprint "eagle-import:0402-RES")
      (fields (field (name "MPN") "ERJ-2RKF1002X"))
      (libsource (lib "eagle-import") (part "RESISTOR0402-RES"))
    )
    (comp (ref "R146")
      (value "100k")
      (footprint "eagle-import:0402-RES")
      (fields (field (name "MPN") "ERJ-2RKF1003X"))
      (libsource (lib "eagle-import") (part "RESISTOR0402-RES"))
    )
    (comp (ref "R147")
      (value "100k")
      (footprint "eagle-import:0402-RES")
      (fields (field (name "MPN") "ERJ-2RKF1003X"))
      (libsource (lib "eagle-import") (part "RESISTOR0402-RES"))
    )
    (comp (ref "R148")
      (value "2.2k")
      (footprint "eagle-import:0402-RES")
      (fields (field (name "MPN") "ERJ-2RKF2201X"))
      (libsource (lib "eagle-import") (part "RESISTOR0402-RES"))
    )
    (comp (ref "R149")
      (value "10k")
      (footprint "eagle-import:0402-RES")
      (fields (field (name "MPN") "ERJ-2RKF1002X"))
      (libsource (lib "eagle-import") (part "RESISTOR0402-RES"))
    )
    (comp (ref "R150")
      (value "2.2k")
      (footprint "eagle-import:0402-RES")
      (fields (field (name "MPN") "ERJ-2RKF2201X"))
      (libsource (lib "eagle-import") (part "RESISTOR0402-RES"))
    )
    (comp (ref "R151")
      (value "33k")
      (footprint "eagle-import:0402-RES")
      (fields (field (name "MPN") "ERJ-2RKF3302X"))
      (libsource (lib "eagle-import") (part "RESISTOR0402-RES"))
    )
    (comp (ref "R152")
      (value "180k")
      (footprint "eagle-import:0402-RES")
      (fields (field (name "MPN") "ERJ-2RKF1803X"))
      (libsource (lib "eagle-import") (part "RESISTOR0402-RES"))
    )
    (comp (ref "R153")
      (value "56k")
      (footprint "eagle-import:0402-RES")
      (fields (field (name "MPN") "ERJ-2RKF5602X"))
      (libsource (lib "eagle-import") (part "RESISTOR0402-RES"))
    )
    (comp (ref "R154")
      (value "4.7k")
      (footprint "eagle-import:0402-RES")
      (fields (field (name "MPN") "ERJ-2RKF4701X"))
      (libsource (lib "eagle-import") (part "RESISTOR0402-RES"))
    )
    (comp (ref "R155")
      (value "4.7k")
      (footprint "eagle-import:0402-RES")
      (fields (field (name "MPN") "ERJ-2RKF4701X"))
      (libsource (lib "eagle-import") (part "RESISTOR0402-RES"))
    )
    (comp (ref "R156")
      (value "1M")
      (footprint "eagle-import:0402-RES")
      (fields (field (name "MPN") "ERJ-2RKF1004X"))
      (libsource (lib "eagle-import") (part "RESISTOR0402-RES"))
    )
    (comp (ref "R157")
      (value "10k")
      (footprint "eagle-import:0402-RES")
      (fields (field (name "MPN") "ERJ-2RKF1002X"))
      (libsource (lib "eagle-import") (part "RESISTOR0402-RES"))
    )
    (comp (ref "R158")
      (value "1k")
      (footprint "eagle-import:0402-RES")
      (fields (field (name "MPN") "ERJ-2RKF1001X"))
      (libsource (lib "eagle-import") (part "RESISTOR0402-RES"))
    )
    (comp (ref "R159")
      (value "47k")
      (footprint "eagle-import:0402-RES")
      (fields (field (name "MPN") "ERJ-2RKF4702X"))
      (libsource (lib "eagle-import") (part "RESISTOR0402-RES"))
    )
    (comp (ref "R160")
      (value "1k")
      (footprint "eagle-import:0402-RES")
      (fields (field (name "MPN") "ERJ-2RKF1001X"))
      (libsource (lib "eagle-import") (part "RESISTOR0402-RES"))
    )
    (comp (ref "R161")
      (value "4.7k")
      (footprint "eagle-import:0402-RES")
      (fields (field (name "MPN") "ERJ-2RKF4701X"))
      (libsource (lib "eagle-import") (part "RESISTOR0402-RES"))
    )
    (comp (ref "R162")
      (value "4.7k")
      (footprint "eagle-import:0402-RES")
      (fields (field (name "MPN") "ERJ-2RKF4701X"))
      (libsource (lib "eagle-import") (part "RESISTOR0402-RES"))
    )
    (comp (ref "R163")
      (value "1k")
      (footprint "eagle-import:0402-RES")
      (fields (field (name "MPN") "ERJ-2RKF1001X"))
      (libsource (lib "eagle-import") (part "RESISTOR0402-RES"))
    )
    (comp (ref "R164")
      (value "180k")
      (footprint "eagle-import:0402-RES")
      (fields (field (name "MPN") "ERJ-2RKF1803X"))
      (libsource (lib "eagle-import") (part "RESISTOR0402-RES"))
    )
    (comp (ref "R165")
      (value "180k")
      (footprint "eagle-import:0402-RES")
      (fields (field (name "MPN") "ERJ-2RKF1803X"))
      (libsource (lib "eagle-import") (part "RESISTOR0402-RES"))
    )
    (comp (ref "R166")
      (value "470")
      (footprint "eagle-import:0402-RES")
      (fields (field (name "MPN") "ERJ-2RKF4700X"))
      (libsource (lib "eagle-import") (part "RESISTOR0402-RES"))
    )
    (comp (ref "R167")
      (value "560")
      (footprint "eagle-import:0402-RES")
      (fields (field (name "MPN") "ERJ-2RKF5600X"))
      (libsource (lib "eagle-import") (part "RESISTOR0402-RES"))
    )
    (comp (ref "R168")
      (value "100k")
      (footprint "eagle-import:0402-RES")
      (fields (field (name "MPN") "ERJ-2RKF1003X"))
      (libsource (lib "eagle-import") (part "RESISTOR0402-RES"))
    )
    (comp (ref "R169")
      (value "10k")
      (footprint "eagle-import:0402-RES")
      (fields (field (name "MPN") "ERJ-2RKF1002X"))
      (libsource (lib "eagle-import") (part "RESISTOR0402-RES"))
    )
    (comp (ref "R170")
      (value "10k")
      (footprint "eagle-import:0402-RES")
      (fields (field (name "MPN") "ERJ-2RKF1002X"))
      (libsource (lib "eagle-import") (part "RESISTOR0402-RES"))
    )
    (comp (ref "R171")
      (value "1M")
      (footprint "eagle-import:0402-RES")
      (fields (field (name "MPN") "ERJ-2RKF1004X"))
      (libsource (lib "eagle-import") (part "RESISTOR0402-RES"))
    )
    (comp (ref "R172")
      (value "18k")
      (footprint "eagle-import:0402-RES")
      (fields (field (name "MPN") "ERJ-2RKF1802X"))
      (libsource (lib "eagle-import") (part "RESISTOR0402-RES"))
    )
    (comp (ref "R173")
      (value "47k")
      (footprint "eagle-import:0402-RES")
      (fields (field (name "MPN") "ERJ-2RKF4702X"))
      (libsource (lib "eagle-import") (part "RESISTOR0402-RES"))
    )
    (comp (ref "R174")
      (value "10k")
      (footprint "eagle-import:0402-RES")
      (fields (field (name "MPN") "ERJ-2RKF1002X"))
      (libsource (lib "eagle-import") (part "RESISTOR0402-RES"))
    )
    (comp (ref "R175")
      (value "470")
      (footprint "eagle-import:0402-RES")
      (fields (field (name "MPN") "ERJ-2RKF4700X"))
      (libsource (lib "eagle-import") (part "RESISTOR0402-RES"))
    )
    (comp (ref "R197")
      (value "0")
      (footprint "eagle-import:0402-RES")
      (fields (field (name "MPN") "ERJ-2GE0R00X"))
      (libsource (lib "eagle-import") (part "RESISTOR0402-RES"))
    )
    (comp (ref "R198")
      (value "100k")
      (footprint "eagle-import:0402-RES")
      (fields (field (name "MPN") "ERJ-2RKF1003X"))
      (libsource (lib "eagle-import") (part "RESISTOR0402-RES"))
    )
    (comp (ref "R199")
      (value "100k")
      (footprint "eagle-import:0402-RES")
      (fields (field (name "MPN") "ERJ-2RKF1003X"))
      (libsource (lib "eagle-import") (part "RESISTOR0402-RES"))
    )
    (comp (ref "R200")
      (value "100k")
      (footprint "eagle-import:0402-RES")
      (fields (field (name "MPN") "ERJ-2RKF1003X"))
      (libsource (lib "eagle-import") (part "RESISTOR0402-RES"))
    )
    (comp (ref "R201")
      (value "100k")
      (footprint "eagle-import:0402-RES")
      (fields (field (name "MPN") "ERJ-2RKF1003X"))
      (libsource (lib "eagle-import") (part "RESISTOR0402-RES"))
    )
    (comp (ref "R202")
      (value "100k")
      (footprint "eagle-import:0402-RES")
      (fields (field (name "MPN") "ERJ-2RKF1003X"))
      (libsource (lib "eagle-import") (part "RESISTOR0402-RES"))
    )
    (comp (ref "R203")
      (value "100k")
      (footprint "eagle-import:0402-RES")
      (fields (field (name "MPN") "ERJ-2RKF1003X"))
      (libsource (lib "eagle-import") (part "RESISTOR0402-RES"))
    )
    (comp (ref "R204")
      (value "100k")
      (footprint "eagle-import:0402-RES")
      (fields (field (name "MPN") "ERJ-2RKF1003X"))
      (libsource (lib "eagle-import") (part "RESISTOR0402-RES"))
    )
    (comp (ref "SW2")
      (value "OS102011MA1Q")
      (footprint "eagle-import:OS102011MA1Q")
      (fields (field (name "MPN") "OS102011MA1QN1"))
      (libsource (lib "eagle-import") (part "OS102011MA1Q"))
    )
    (comp (ref "U13")
      (value "741G3157DBVR")
      (footprint "eagle-import:DBV_R-PDSO-G6")
      (fields (field (name "MPN") "SN74LVC1G3157DBVR"))
      (libsource (lib "eagle-import") (part "741G3157DBVR"))
    )
    (comp (ref "U19")
      (value "LME49721")
      (footprint "eagle-import:SO08")
      (fields (field (name "MPN") "LME49721MAX/NOPB"))
      (libsource (lib "eagle-import") (part "RC4559D"))
    )
    (comp (ref "U20")
      (value "LME49721")
      (footprint "eagle-import:SO08")
      (fields (field (name "MPN") "LME49721MAX/NOPB"))
      (libsource (lib "eagle-import") (part "RC4559D"))
    )
    (comp (ref "U21")
      (value "LME49721")
      (footprint "eagle-import:SO08")
      (fields (field (name "MPN") "LME49721MAX/NOPB"))
      (libsource (lib "eagle-import") (part "RC4559D"))
    )
    (comp (ref "C1-2")
      (value "10u")
      (footprint "eagle-import:C0603K")
      (fields (field (name "MPN") "GRM188R61C106MA73D"))
      (libsource (lib "eagle-import") (part "C-EUC0603K"))
    )
    (comp (ref "C2-2")
      (value "1u")
      (footprint "eagle-import:C0402K")
      (fields (field (name "MPN") "GRM155R70J105KA12D"))
      (libsource (lib "eagle-import") (part "resistor_C-EUC0402K"))
    )
    (comp (ref "C3-2")
      (value "10u")
      (footprint "eagle-import:C0603K")
      (fields (field (name "MPN") "GRM188R61C106MA73D"))
      (libsource (lib "eagle-import") (part "C-EUC0603K"))
    )
    (comp (ref "C4-2")
      (value "10u")
      (footprint "eagle-import:C0603K")
      (fields (field (name "MPN") "GRM188R61C106MA73D"))
      (libsource (lib "eagle-import") (part "C-EUC0603K"))
    )
    (comp (ref "C5-2")
      (value "1u")
      (footprint "eagle-import:C0402K")
      (fields (field (name "MPN") "GRM155R70J105KA12D"))
      (libsource (lib "eagle-import") (part "resistor_C-EUC0402K"))
    )
    (comp (ref "C28-2")
      (value "0.1u")
      (footprint "eagle-import:0402")
      (fields (field (name "MPN") "GRM155R71C104JA88D"))
      (libsource (lib "eagle-import") (part "C0402_BGA"))
    )
    (comp (ref "C29-2")
      (value "0.1u")
      (footprint "eagle-import:0402")
      (fields (field (name "MPN") "GRM155R71C104JA88D"))
      (libsource (lib "eagle-import") (part "C0402_BGA"))
    )
    (comp (ref "C30-2")
      (value "0.1u")
      (footprint "eagle-import:0402")
      (fields (field (name "MPN") "GRM155R71C104JA88D"))
      (libsource (lib "eagle-import") (part "C0402_BGA"))
    )
    (comp (ref "C32-2")
      (value "0.1u")
      (footprint "eagle-import:0402")
      (fields (field (name "MPN") "GRM155R71C104JA88D"))
      (libsource (lib "eagle-import") (part "C0402_BGA"))
    )
    (comp (ref "C38-2")
      (value "10n")
      (footprint "eagle-import:0402")
      (fields (field (name "MPN") "GRM155R71E103KA01D"))
      (libsource (lib "eagle-import") (part "C0402_BGA"))
    )
    (comp (ref "C40-2")
      (value "0.1u")
      (footprint "eagle-import:0402")
      (fields (field (name "MPN") "GRM155R71C104JA88D"))
      (libsource (lib "eagle-import") (part "C0402_BGA"))
    )
    (comp (ref "C41-2")
      (value "10n")
      (footprint "eagle-import:0402")
      (fields (field (name "MPN") "GRM155R71E103KA01D"))
      (libsource (lib "eagle-import") (part "C0402_BGA"))
    )
    (comp (ref "C42-2")
      (value "1u")
      (footprint "eagle-import:0402")
      (fields (field (name "MPN") "GRM155R70J105KA12D"))
      (libsource (lib "eagle-import") (part "C0402_BGA"))
    )
    (comp (ref "C43-2")
      (value "10n")
      (footprint "eagle-import:0402")
      (fields (field (name "MPN") "GRM155R71E103KA01D"))
      (libsource (lib "eagle-import") (part "C0402_BGA"))
    )
    (comp (ref "C45-2")
      (value "0.1u")
      (footprint "eagle-import:0402")
      (fields (field (name "MPN") "GRM155R71C104JA88D"))
      (libsource (lib "eagle-import") (part "C0402_BGA"))
    )
    (comp (ref "C46-2")
      (value "0.1u")
      (footprint "eagle-import:0402")
      (fields (field (name "MPN") "GRM155R71C104JA88D"))
      (libsource (lib "eagle-import") (part "C0402_BGA"))
    )
    (comp (ref "C48-2")
      (value "0.1u")
      (footprint "eagle-import:0402")
      (fields (field (name "MPN") "GRM155R71C104JA88D"))
      (libsource (lib "eagle-import") (part "C0402_BGA"))
    )
    (comp (ref "C49-2")
      (value "0.1u")
      (footprint "eagle-import:0402")
      (fields (field (name "MPN") "GRM155R71C104JA88D"))
      (libsource (lib "eagle-import") (part "C0402_BGA"))
    )
    (comp (ref "C50-2")
      (value "1n")
      (footprint "eagle-import:0402")
      (fields (field (name "MPN") "GRM155R71H102JA01J"))
      (libsource (lib "eagle-import") (part "C0402_BGA"))
    )
    (comp (ref "C51-2")
      (value "10n")
      (footprint "eagle-import:0402")
      (fields (field (name "MPN") "GRM155R71E103KA01D"))
      (libsource (lib "eagle-import") (part "C0402_BGA"))
    )
    (comp (ref "C52-2")
      (value "1u")
      (footprint "eagle-import:0402")
      (fields (field (name "MPN") "GRM155R70J105KA12D"))
      (libsource (lib "eagle-import") (part "C0402_BGA"))
    )
    (comp (ref "C53-2")
      (value "1u")
      (footprint "eagle-import:0402")
      (fields (field (name "MPN") "GRM155R70J105KA12D"))
      (libsource (lib "eagle-import") (part "C0402_BGA"))
    )
    (comp (ref "C54-2")
      (value "1u")
      (footprint "eagle-import:0402")
      (fields (field (name "MPN") "GRM155R70J105KA12D"))
      (libsource (lib "eagle-import") (part "C0402_BGA"))
    )
    (comp (ref "C55-2")
      (value "10n")
      (footprint "eagle-import:0402")
      (fields (field (name "MPN") "GRM155R71E103KA01D"))
      (libsource (lib "eagle-import") (part "C0402_BGA"))
    )
    (comp (ref "C56-2")
      (value "1n")
      (footprint "eagle-import:0402")
      (fields (field (name "MPN") "GRM155R71H102JA01J"))
      (libsource (lib "eagle-import") (part "C0402_BGA"))
    )
    (comp (ref "C57-2")
      (value "0.1u")
      (footprint "eagle-import:0402")
      (fields (field (name "MPN") "GRM155R71C104JA88D"))
      (libsource (lib "eagle-import") (part "C0402_BGA"))
    )
    (comp (ref "C59-2")
      (value "0.1u")
      (footprint "eagle-import:0402")
      (fields (field (name "MPN") "GRM155R71C104JA88D"))
      (libsource (lib "eagle-import") (part "C0402_BGA"))
    )
    (comp (ref "C60-2")
      (value "0.1u")
      (footprint "eagle-import:0402")
      (fields (field (name "MPN") "GRM155R71C104JA88D"))
      (libsource (lib "eagle-import") (part "C0402_BGA"))
    )
    (comp (ref "C62-2")
      (value "0.1u")
      (footprint "eagle-import:0402")
      (fields (field (name "MPN") "GRM155R71C104JA88D"))
      (libsource (lib "eagle-import") (part "C0402_BGA"))
    )
    (comp (ref "C63-2")
      (value "0.1u")
      (footprint "eagle-import:0402")
      (fields (field (name "MPN") "GRM155R71C104JA88D"))
      (libsource (lib "eagle-import") (part "C0402_BGA"))
    )
    (comp (ref "C64-2")
      (value "1u")
      (footprint "eagle-import:0402")
      (fields (field (name "MPN") "GRM155R70J105KA12D"))
      (libsource (lib "eagle-import") (part "C0402_BGA"))
    )
    (comp (ref "C65-2")
      (value "0.1u")
      (footprint "eagle-import:0402")
      (fields (field (name "MPN") "GRM155R71C104JA88D"))
      (libsource (lib "eagle-import") (part "C0402_BGA"))
    )
    (comp (ref "C67-2")
      (value "0.1u")
      (footprint "eagle-import:0402")
      (fields (field (name "MPN") "GRM155R71C104JA88D"))
      (libsource (lib "eagle-import") (part "C0402_BGA"))
    )
    (comp (ref "C69-2")
      (value "0.1u")
      (footprint "eagle-import:0402")
      (fields (field (name "MPN") "GRM155R71C104JA88D"))
      (libsource (lib "eagle-import") (part "C0402_BGA"))
    )
    (comp (ref "C71-2")
      (value "0.1u")
      (footprint "eagle-import:0402")
      (fields (field (name "MPN") "GRM155R71C104JA88D"))
      (libsource (lib "eagle-import") (part "C0402_BGA"))
    )
    (comp (ref "C72-2")
      (value "0.1u")
      (footprint "eagle-import:0402")
      (fields (field (name "MPN") "GRM155R71C104JA88D"))
      (libsource (lib "eagle-import") (part "C0402_BGA"))
    )
    (comp (ref "C73-2")
      (value "10n")
      (footprint "eagle-import:0402")
      (fields (field (name "MPN") "GRM155R71E103KA01D"))
      (libsource (lib "eagle-import") (part "C0402_BGA"))
    )
    (comp (ref "C74-2")
      (value "1n")
      (footprint "eagle-import:C0402K")
      (fields (field (name "MPN") "GRM155R71H102JA01J"))
      (libsource (lib "eagle-import") (part "resistor_C-EUC0402K"))
    )
    (comp (ref "C75-2")
      (value "0.1u")
      (footprint "eagle-import:0402")
      (fields (field (name "MPN") "GRM155R71C104JA88D"))
      (libsource (lib "eagle-import") (part "C0402_BGA"))
    )
    (comp (ref "C85-2")
      (value "0.1u")
      (footprint "eagle-import:0402")
      (fields (field (name "MPN") "GRM155R71C104JA88D"))
      (libsource (lib "eagle-import") (part "C0402_BGA"))
    )
    (comp (ref "C86-2")
      (value "1u")
      (footprint "eagle-import:0402")
      (fields (field (name "MPN") "GRM155R70J105KA12D"))
      (libsource (lib "eagle-import") (part "C0402_BGA"))
    )
    (comp (ref "C87-2")
      (value "0.1u")
      (footprint "eagle-import:0402")
      (fields (field (name "MPN") "GRM155R71C104JA88D"))
      (libsource (lib "eagle-import") (part "C0402_BGA"))
    )
    (comp (ref "C88-2")
      (value "0.1u")
      (footprint "eagle-import:0402")
      (fields (field (name "MPN") "GRM155R71C104JA88D"))
      (libsource (lib "eagle-import") (part "C0402_BGA"))
    )
    (comp (ref "C89-2")
      (value "10n")
      (footprint "eagle-import:C0402K")
      (fields (field (name "MPN") "GRM155R71E103KA01D"))
      (libsource (lib "eagle-import") (part "resistor_C-EUC0402K"))
    )
    (comp (ref "FB1-2")
      (value "BLM18AG601SN1D")
      (footprint "eagle-import:0603")
      (libsource (lib "eagle-import") (part "INDUCTOR0603"))
    )
    (comp (ref "FB4-2")
      (value "BLM18AG601SN1D")
      (footprint "eagle-import:0603")
      (libsource (lib "eagle-import") (part "INDUCTOR0603"))
    )
    (comp (ref "FB5-2")
      (value "BLM18AG601SN1D")
      (footprint "eagle-import:0603")
      (libsource (lib "eagle-import") (part "INDUCTOR0603"))
    )
    (comp (ref "FB6-2")
      (value "BLM18AG601SN1D")
      (footprint "eagle-import:0603")
      (libsource (lib "eagle-import") (part "INDUCTOR0603"))
    )
    (comp (ref "L3-2")
      (value "BLM18AG601SN1D")
      (footprint "eagle-import:0603")
      (libsource (lib "eagle-import") (part "INDUCTOR0603"))
    )
    (comp (ref "R60-2")
      (value "0")
      (footprint "eagle-import:0402-RES")
      (fields (field (name "MPN") "ERJ-2GE0R00X"))
      (libsource (lib "eagle-import") (part "RESISTOR0402-RES"))
    )
    (comp (ref "R61-2")
      (value "0")
      (footprint "eagle-import:0402-RES")
      (fields (field (name "MPN") "ERJ-2GE0R00X"))
      (libsource (lib "eagle-import") (part "RESISTOR0402-RES"))
    )
    (comp (ref "R62-2")
      (value "NC")
      (footprint "eagle-import:0402-RES")
      (libsource (lib "eagle-import") (part "RESISTOR0402-RES"))
    )
    (comp (ref "R63-2")
      (value "NC")
      (footprint "eagle-import:0402-RES")
      (libsource (lib "eagle-import") (part "RESISTOR0402-RES"))
    )
    (comp (ref "R64-2")
      (value "0")
      (footprint "eagle-import:0402-RES")
      (fields (field (name "MPN") "ERJ-2GE0R00X"))
      (libsource (lib "eagle-import") (part "RESISTOR0402-RES"))
    )
    (comp (ref "R97-2")
      (value "0")
      (footprint "eagle-import:0805")
      (fields (field (name "MPN") "ERJ-6GEY0R00V"))
      (libsource (lib "eagle-import") (part "RESISTOR0805-RES"))
    )
    (comp (ref "R121-2")
      (value "NC")
      (footprint "eagle-import:0805")
      (libsource (lib "eagle-import") (part "RESISTOR0805-RES"))
    )
    (comp (ref "R122-2")
      (value "0")
      (footprint "eagle-import:0805")
      (fields (field (name "MPN") "ERJ-6GEY0R00V"))
      (libsource (lib "eagle-import") (part "RESISTOR0805-RES"))
    )
    (comp (ref "R124-2")
      (value "0")
      (footprint "eagle-import:0805")
      (fields (field (name "MPN") "ERJ-6GEY0R00V"))
      (libsource (lib "eagle-import") (part "RESISTOR0805-RES"))
    )
    (comp (ref "U5")
      (value "TMS320C5535")
      (footprint "eagle-import:PBGA144")
      (fields (field (name "MPN") "TMS320C5535AZHH10"))
      (libsource (lib "eagle-import") (part "TMS320C5535S-PBGA-N144"))
    )
    (comp (ref "C189")
      (value "220p")
      (footprint "eagle-import:0402-CAP")
      (fields (field (name "MPN") "GRM1555C1H221FA01D"))
      (libsource (lib "eagle-import") (part "CAP0402-CAP"))
    )
    (comp (ref "C190")
      (value "22p")
      (footprint "eagle-import:0402-CAP")
      (fields (field (name "MPN") "GRM1555C2A220JA01D"))
      (libsource (lib "eagle-import") (part "CAP0402-CAP"))
    )
    (comp (ref "C191")
      (value "10u")
      (footprint "eagle-import:C0805K")
      (fields (field (name "MPN") "GRM21BR71A106KA73L"))
      (libsource (lib "eagle-import") (part "C-EUC0805K"))
    )
    (comp (ref "C192")
      (value "2.2n")
      (footprint "eagle-import:0402-CAP")
      (fields (field (name "MPN") "GRM155R71H222JA01J"))
      (libsource (lib "eagle-import") (part "CAP0402-CAP"))
    )
    (comp (ref "C193")
      (value "2.2n")
      (footprint "eagle-import:0402-CAP")
      (fields (field (name "MPN") "GRM155R71H222JA01J"))
      (libsource (lib "eagle-import") (part "CAP0402-CAP"))
    )
    (comp (ref "C194")
      (value "150p")
      (footprint "eagle-import:0402-CAP")
      (fields (field (name "MPN") "GRM1555C1H151GA01D"))
      (libsource (lib "eagle-import") (part "CAP0402-CAP"))
    )
    (comp (ref "C195")
      (value "10u")
      (footprint "eagle-import:C0805K")
      (fields (field (name "MPN") "GRM21BR71A106KA73L"))
      (libsource (lib "eagle-import") (part "C-EUC0805K"))
    )
    (comp (ref "C196")
      (value "2.2n")
      (footprint "eagle-import:0402-CAP")
      (fields (field (name "MPN") "GRM155R71H222JA01J"))
      (libsource (lib "eagle-import") (part "CAP0402-CAP"))
    )
    (comp (ref "C197")
      (value "220p")
      (footprint "eagle-import:0402-CAP")
      (fields (field (name "MPN") "GRM1555C1H221FA01D"))
      (libsource (lib "eagle-import") (part "CAP0402-CAP"))
    )
    (comp (ref "C198")
      (value "10u")
      (footprint "eagle-import:C0805K")
      (fields (field (name "MPN") "GRM21BR71A106KA73L"))
      (libsource (lib "eagle-import") (part "C-EUC0805K"))
    )
    (comp (ref "C199")
      (value "2.2n")
      (footprint "eagle-import:0402-CAP")
      (fields (field (name "MPN") "GRM155R71H222JA01J"))
      (libsource (lib "eagle-import") (part "CAP0402-CAP"))
    )
    (comp (ref "C200")
      (value "22p")
      (footprint "eagle-import:0402-CAP")
      (fields (field (name "MPN") "GRM1555C2A220JA01D"))
      (libsource (lib "eagle-import") (part "CAP0402-CAP"))
    )
    (comp (ref "C201")
      (value "2.2n")
      (footprint "eagle-import:0402-CAP")
      (fields (field (name "MPN") "GRM155R71H222JA01J"))
      (libsource (lib "eagle-import") (part "CAP0402-CAP"))
    )
    (comp (ref "C202")
      (value "150p")
      (footprint "eagle-import:0402-CAP")
      (fields (field (name "MPN") "GRM1555C1H151GA01D"))
      (libsource (lib "eagle-import") (part "CAP0402-CAP"))
    )
    (comp (ref "C203")
      (value "10u")
      (footprint "eagle-import:C0805K")
      (fields (field (name "MPN") "GRM21BR71A106KA73L"))
      (libsource (lib "eagle-import") (part "C-EUC0805K"))
    )
    (comp (ref "C205")
      (value "100p")
      (footprint "eagle-import:0402-CAP")
      (fields (field (name "MPN") "GRM1555C1H101FA01J"))
      (libsource (lib "eagle-import") (part "CAP0402-CAP"))
    )
    (comp (ref "C206")
      (value "220p")
      (footprint "eagle-import:0402-CAP")
      (fields (field (name "MPN") "GRM1555C1H221FA01D"))
      (libsource (lib "eagle-import") (part "CAP0402-CAP"))
    )
    (comp (ref "C207")
      (value "10n")
      (footprint "eagle-import:0402-CAP")
      (fields (field (name "MPN") "GRM155R71E103KA01D"))
      (libsource (lib "eagle-import") (part "CAP0402-CAP"))
    )
    (comp (ref "C208")
      (value "18n")
      (footprint "eagle-import:0402-CAP")
      (fields (field (name "MPN") "GRM155R71H183KA12D"))
      (libsource (lib "eagle-import") (part "CAP0402-CAP"))
    )
    (comp (ref "C209")
      (value "0.1u")
      (footprint "eagle-import:0402-CAP")
      (fields (field (name "MPN") "GRM155R71C104JA88D"))
      (libsource (lib "eagle-import") (part "CAP0402-CAP"))
    )
    (comp (ref "C210")
      (value "10u")
      (footprint "eagle-import:C0805K")
      (fields (field (name "MPN") "GRM21BR71A106KA73L"))
      (libsource (lib "eagle-import") (part "resistor_C-EUC0805K"))
    )
    (comp (ref "C211")
      (value "10u")
      (footprint "eagle-import:C0805K")
      (fields (field (name "MPN") "GRM21BR71A106KA73L"))
      (libsource (lib "eagle-import") (part "resistor_C-EUC0805K"))
    )
    (comp (ref "C212")
      (value "680p")
      (footprint "eagle-import:0402-CAP")
      (fields (field (name "MPN") "GRM155R72A681KA01D"))
      (libsource (lib "eagle-import") (part "CAP0402-CAP"))
    )
    (comp (ref "C214")
      (value "100p")
      (footprint "eagle-import:0402-CAP")
      (fields (field (name "MPN") "GRM1555C1H101FA01J"))
      (libsource (lib "eagle-import") (part "CAP0402-CAP"))
    )
    (comp (ref "C223")
      (value "0.1u")
      (footprint "eagle-import:0402-CAP")
      (fields (field (name "MPN") "GRM155R71C104JA88D"))
      (libsource (lib "eagle-import") (part "CAP0402-CAP"))
    )
    (comp (ref "C224")
      (value "0.1u")
      (footprint "eagle-import:0402-CAP")
      (fields (field (name "MPN") "GRM155R71C104JA88D"))
      (libsource (lib "eagle-import") (part "CAP0402-CAP"))
    )
    (comp (ref "D7")
      (value "BAT54S")
      (footprint "eagle-import:SOT23")
      (fields (field (name "MPN") "BAT54SLT1G"))
      (libsource (lib "eagle-import") (part "BAT54S"))
    )
    (comp (ref "FB13")
      (value "BLM31PG121SN1L")
      (footprint "eagle-import:R1206")
      (libsource (lib "eagle-import") (part "R-EU_R1206"))
    )
    (comp (ref "FB14")
      (value "BLM31PG121SN1L")
      (footprint "eagle-import:R1206")
      (libsource (lib "eagle-import") (part "R-EU_R1206"))
    )
    (comp (ref "J9")
      (value "MONOSW3C")
      (footprint "eagle-import:NEUTRIK-NMJ4HCD2")
      (fields (field (name "MPN") "NMJ4HCD2"))
      (libsource (lib "eagle-import") (part "MONOSW3C"))
    )
    (comp (ref "J10")
      (value "MONOSW3C")
      (footprint "eagle-import:NEUTRIK-NMJ4HCD2")
      (fields (field (name "MPN") "NMJ4HCD2"))
      (libsource (lib "eagle-import") (part "MONOSW3C"))
    )
    (comp (ref "LSP3")
      (value "LSP13")
      (footprint "eagle-import:LSP13")
      (libsource (lib "eagle-import") (part "LSP13"))
    )
    (comp (ref "Q5")
      (value "2N7002ET1G")
      (footprint "eagle-import:SOT23")
      (libsource (lib "eagle-import") (part "MOSFET-NREFLOW"))
    )
    (comp (ref "Q6")
      (value "2N7002ET1G")
      (footprint "eagle-import:SOT23")
      (libsource (lib "eagle-import") (part "MOSFET-NREFLOW"))
    )
    (comp (ref "Q7")
      (value "2N7002ET1G")
      (footprint "eagle-import:SOT23")
      (libsource (lib "eagle-import") (part "MOSFET-NREFLOW"))
    )
    (comp (ref "R176")
      (value "12k")
      (footprint "eagle-import:0402-RES")
      (fields (field (name "MPN") "ERJ-2RKF1202X"))
      (libsource (lib "eagle-import") (part "RESISTOR0402-RES"))
    )
    (comp (ref "R177")
      (value "47k")
      (footprint "eagle-import:0402-RES")
      (fields (field (name "MPN") "ERJ-2RKF4702X"))
      (libsource (lib "eagle-import") (part "RESISTOR0402-RES"))
    )
    (comp (ref "R178")
      (value "12k")
      (footprint "eagle-import:0402-RES")
      (fields (field (name "MPN") "ERJ-2RKF1202X"))
      (libsource (lib "eagle-import") (part "RESISTOR0402-RES"))
    )
    (comp (ref "R179")
      (value "8.2k")
      (footprint "eagle-import:0402-RES")
      (fields (field (name "MPN") "ERJ-2RKF8201X"))
      (libsource (lib "eagle-import") (part "RESISTOR0402-RES"))
    )
    (comp (ref "R180")
      (value "12k")
      (footprint "eagle-import:0402-RES")
      (fields (field (name "MPN") "ERJ-2RKF1202X"))
      (libsource (lib "eagle-import") (part "RESISTOR0402-RES"))
    )
    (comp (ref "R181")
      (value "10k")
      (footprint "eagle-import:0402-RES")
      (fields (field (name "MPN") "ERJ-2RKF1002X"))
      (libsource (lib "eagle-import") (part "RESISTOR0402-RES"))
    )
    (comp (ref "R182")
      (value "330")
      (footprint "eagle-import:0402-RES")
      (fields (field (name "MPN") "ERJ-2RKF3300X"))
      (libsource (lib "eagle-import") (part "RESISTOR0402-RES"))
    )
    (comp (ref "R183")
      (value "100k")
      (footprint "eagle-import:0402-RES")
      (fields (field (name "MPN") "ERJ-2RKF1003X"))
      (libsource (lib "eagle-import") (part "RESISTOR0402-RES"))
    )
    (comp (ref "R184")
      (value "1k")
      (footprint "eagle-import:0402-RES")
      (fields (field (name "MPN") "ERJ-2RKF1001X"))
      (libsource (lib "eagle-import") (part "RESISTOR0402-RES"))
    )
    (comp (ref "R185")
      (value "1k")
      (footprint "eagle-import:0402-RES")
      (fields (field (name "MPN") "ERJ-2RKF1001X"))
      (libsource (lib "eagle-import") (part "RESISTOR0402-RES"))
    )
    (comp (ref "R186")
      (value "10k")
      (footprint "eagle-import:0402-RES")
      (fields (field (name "MPN") "ERJ-2RKF1002X"))
      (libsource (lib "eagle-import") (part "RESISTOR0402-RES"))
    )
    (comp (ref "R187")
      (value "12k")
      (footprint "eagle-import:0402-RES")
      (fields (field (name "MPN") "ERJ-2RKF1202X"))
      (libsource (lib "eagle-import") (part "RESISTOR0402-RES"))
    )
    (comp (ref "R188")
      (value "12k")
      (footprint "eagle-import:0402-RES")
      (fields (field (name "MPN") "ERJ-2RKF1202X"))
      (libsource (lib "eagle-import") (part "RESISTOR0402-RES"))
    )
    (comp (ref "R189")
      (value "8.2k")
      (footprint "eagle-import:0402-RES")
      (fields (field (name "MPN") "ERJ-2RKF8201X"))
      (libsource (lib "eagle-import") (part "RESISTOR0402-RES"))
    )
    (comp (ref "R190")
      (value "12k")
      (footprint "eagle-import:0402-RES")
      (fields (field (name "MPN") "ERJ-2RKF1202X"))
      (libsource (lib "eagle-import") (part "RESISTOR0402-RES"))
    )
    (comp (ref "R191")
      (value "47k")
      (footprint "eagle-import:0402-RES")
      (fields (field (name "MPN") "ERJ-2RKF4702X"))
      (libsource (lib "eagle-import") (part "RESISTOR0402-RES"))
    )
    (comp (ref "R192")
      (value "10k")
      (footprint "eagle-import:0402-RES")
      (fields (field (name "MPN") "ERJ-2RKF1002X"))
      (libsource (lib "eagle-import") (part "RESISTOR0402-RES"))
    )
    (comp (ref "R193")
      (value "330")
      (footprint "eagle-import:0402-RES")
      (fields (field (name "MPN") "ERJ-2RKF3300X"))
      (libsource (lib "eagle-import") (part "RESISTOR0402-RES"))
    )
    (comp (ref "R194")
      (value "100k")
      (footprint "eagle-import:0402-RES")
      (fields (field (name "MPN") "ERJ-2RKF1003X"))
      (libsource (lib "eagle-import") (part "RESISTOR0402-RES"))
    )
    (comp (ref "R195")
      (value "1k")
      (footprint "eagle-import:0402-RES")
      (fields (field (name "MPN") "ERJ-2RKF1001X"))
      (libsource (lib "eagle-import") (part "RESISTOR0402-RES"))
    )
    (comp (ref "R196")
      (value "1k")
      (footprint "eagle-import:0402-RES")
      (fields (field (name "MPN") "ERJ-2RKF1001X"))
      (libsource (lib "eagle-import") (part "RESISTOR0402-RES"))
    )
    (comp (ref "R205")
      (value "100")
      (footprint "eagle-import:0402-RES")
      (fields (field (name "MPN") "ERJ-2RKF1000X"))
      (libsource (lib "eagle-import") (part "RESISTOR0402-RES"))
    )
    (comp (ref "R206")
      (value "220k")
      (footprint "eagle-import:0402-RES")
      (fields (field (name "MPN") "ERJ-2RKF2203X"))
      (libsource (lib "eagle-import") (part "RESISTOR0402-RES"))
    )
    (comp (ref "R207")
      (value "22k")
      (footprint "eagle-import:0402-RES")
      (fields (field (name "MPN") "ERJ-2RKF2202X"))
      (libsource (lib "eagle-import") (part "RESISTOR0402-RES"))
    )
    (comp (ref "R208")
      (value "680k")
      (footprint "eagle-import:0402-RES")
      (fields (field (name "MPN") "ERJ-2RKF6803X"))
      (libsource (lib "eagle-import") (part "RESISTOR0402-RES"))
    )
    (comp (ref "R209")
      (value "22k")
      (footprint "eagle-import:0402-RES")
      (fields (field (name "MPN") "ERJ-2RKF2202X"))
      (libsource (lib "eagle-import") (part "RESISTOR0402-RES"))
    )
    (comp (ref "R210")
      (value "10k")
      (footprint "eagle-import:0402-RES")
      (fields (field (name "MPN") "ERJ-2RKF1002X"))
      (libsource (lib "eagle-import") (part "RESISTOR0402-RES"))
    )
    (comp (ref "R211")
      (value "15k")
      (footprint "eagle-import:0402-RES")
      (fields (field (name "MPN") "ERJ-2RKF1502X"))
      (libsource (lib "eagle-import") (part "RESISTOR0402-RES"))
    )
    (comp (ref "R212")
      (value "12k")
      (footprint "eagle-import:0402-RES")
      (fields (field (name "MPN") "ERJ-2RKF1202X"))
      (libsource (lib "eagle-import") (part "RESISTOR0402-RES"))
    )
    (comp (ref "R213")
      (value "2k")
      (footprint "eagle-import:0402-RES")
      (fields (field (name "MPN") "ERJ-2RKF2001X"))
      (libsource (lib "eagle-import") (part "RESISTOR0402-RES"))
    )
    (comp (ref "R214")
      (value "2k")
      (footprint "eagle-import:0402-RES")
      (fields (field (name "MPN") "ERJ-2RKF2001X"))
      (libsource (lib "eagle-import") (part "RESISTOR0402-RES"))
    )
    (comp (ref "R215")
      (value "1.3k")
      (footprint "eagle-import:0402-RES")
      (fields (field (name "MPN") "ERJ-2RKF1301X"))
      (libsource (lib "eagle-import") (part "RESISTOR0402-RES"))
    )
    (comp (ref "R216")
      (value "1.3k")
      (footprint "eagle-import:0402-RES")
      (fields (field (name "MPN") "ERJ-2RKF1301X"))
      (libsource (lib "eagle-import") (part "RESISTOR0402-RES"))
    )
    (comp (ref "U22")
      (value "LME49721")
      (footprint "eagle-import:SO08")
      (fields (field (name "MPN") "LME49721MAX/NOPB"))
      (libsource (lib "eagle-import") (part "RC4559D"))
    )
    (comp (ref "U23")
      (value "LME49721")
      (footprint "eagle-import:SO08")
      (fields (field (name "MPN") "LME49721MAX/NOPB"))
      (libsource (lib "eagle-import") (part "RC4559D"))
    )
    (comp (ref "U24")
      (value "LMV358")
      (footprint "eagle-import:SO08")
      (fields (field (name "MPN") "LMV358IDR"))
      (libsource (lib "eagle-import") (part "LMV358"))
    )
    (comp (ref "C8")
      (value "10u")
      (footprint "eagle-import:C0603K")
      (fields (field (name "MPN") "GRM188R61C106MA73D"))
      (libsource (lib "eagle-import") (part "C-EUC0603K"))
    )
    (comp (ref "C11")
      (value "10u")
      (footprint "eagle-import:C0603K")
      (fields (field (name "MPN") "GRM188R61C106MA73D"))
      (libsource (lib "eagle-import") (part "C-EUC0603K"))
    )
    (comp (ref "C12")
      (value "10u")
      (footprint "eagle-import:C0603K")
      (fields (field (name "MPN") "GRM188R61C106MA73D"))
      (libsource (lib "eagle-import") (part "C-EUC0603K"))
    )
    (comp (ref "C13")
      (value "100u")
      (footprint "eagle-import:1411")
      (fields (field (name "MPN") "ATCC-211B-010-107M-T"))
      (libsource (lib "eagle-import") (part "CPOL-US1411"))
    )
    (comp (ref "C14")
      (value "100u")
      (footprint "eagle-import:1411")
      (fields (field (name "MPN") "ATCC-211B-010-107M-T"))
      (libsource (lib "eagle-import") (part "CPOL-US1411"))
    )
    (comp (ref "C16")
      (value "0.47u")
      (footprint "eagle-import:C0603K")
      (fields (field (name "MPN") "GRM188R71C474KA88D"))
      (libsource (lib "eagle-import") (part "C-EUC0603K"))
    )
    (comp (ref "C17")
      (value "0.47u")
      (footprint "eagle-import:C0603K")
      (fields (field (name "MPN") "GRM188R71C474KA88D"))
      (libsource (lib "eagle-import") (part "C-EUC0603K"))
    )
    (comp (ref "C18")
      (value "10u")
      (footprint "eagle-import:C0603K")
      (fields (field (name "MPN") "GRM188R61C106MA73D"))
      (libsource (lib "eagle-import") (part "C-EUC0603K"))
    )
    (comp (ref "C19")
      (value "10u")
      (footprint "eagle-import:C0603K")
      (fields (field (name "MPN") "GRM188R61C106MA73D"))
      (libsource (lib "eagle-import") (part "C-EUC0603K"))
    )
    (comp (ref "C104")
      (value "10n")
      (footprint "eagle-import:C0402K")
      (fields (field (name "MPN") "GRM155R71E103KA01D"))
      (libsource (lib "eagle-import") (part "resistor_C-EUC0402K"))
    )
    (comp (ref "C105")
      (value "0.1u")
      (footprint "eagle-import:C0402K")
      (fields (field (name "MPN") "GRM155R71C104JA88D"))
      (libsource (lib "eagle-import") (part "resistor_C-EUC0402K"))
    )
    (comp (ref "C108")
      (value "0.1u")
      (footprint "eagle-import:C0402K")
      (fields (field (name "MPN") "GRM155R71C104JA88D"))
      (libsource (lib "eagle-import") (part "resistor_C-EUC0402K"))
    )
    (comp (ref "C111")
      (value "0.1u")
      (footprint "eagle-import:C0402K")
      (fields (field (name "MPN") "GRM155R71C104JA88D"))
      (libsource (lib "eagle-import") (part "resistor_C-EUC0402K"))
    )
    (comp (ref "C116")
      (value "0.1u")
      (footprint "eagle-import:C0402K")
      (fields (field (name "MPN") "GRM155R71C104JA88D"))
      (libsource (lib "eagle-import") (part "resistor_C-EUC0402K"))
    )
    (comp (ref "C117")
      (value "0.1u")
      (footprint "eagle-import:C0402K")
      (fields (field (name "MPN") "GRM155R71C104JA88D"))
      (libsource (lib "eagle-import") (part "resistor_C-EUC0402K"))
    )
    (comp (ref "C122")
      (value "0.1u")
      (footprint "eagle-import:C0402K")
      (fields (field (name "MPN") "GRM155R71C104JA88D"))
      (libsource (lib "eagle-import") (part "resistor_C-EUC0402K"))
    )
    (comp (ref "FB2")
      (value "BLM21AG151SN1D")
      (footprint "eagle-import:0805")
      (libsource (lib "eagle-import") (part "INDUCTOR0805"))
    )
    (comp (ref "FB3")
      (value "BLM21AG151SN1D")
      (footprint "eagle-import:0805")
      (libsource (lib "eagle-import") (part "INDUCTOR0805"))
    )
    (comp (ref "J4")
      (value "HEADPHONES")
      (footprint "eagle-import:AUDIO-JACK-3.5MM-SMD")
      (fields (field (name "MPN") "SJ1-3515-SMT-TR"))
      (libsource (lib "eagle-import") (part "AUDIOJACK3_5SMD"))
    )
    (comp (ref "R5")
      (value "0")
      (footprint "eagle-import:0402-RES")
      (fields (field (name "MPN") "ERJ-2GE0R00X"))
      (libsource (lib "eagle-import") (part "RESISTOR0402-RES"))
    )
    (comp (ref "R8")
      (value "0")
      (footprint "eagle-import:0402-RES")
      (fields (field (name "MPN") "ERJ-2GE0R00X"))
      (libsource (lib "eagle-import") (part "RESISTOR0402-RES"))
    )
    (comp (ref "R9")
      (value "NC")
      (footprint "eagle-import:0603-RES")
      (libsource (lib "eagle-import") (part "RESISTOR0603-RES"))
    )
    (comp (ref "R10")
      (value "4.7k")
      (footprint "eagle-import:0603-RES")
      (fields (field (name "MPN") "ERJ-3EKF4701V"))
      (libsource (lib "eagle-import") (part "RESISTOR0603-RES"))
    )
    (comp (ref "R92")
      (value "0")
      (footprint "eagle-import:0402-RES")
      (fields (field (name "MPN") "ERJ-2GE0R00X"))
      (libsource (lib "eagle-import") (part "RESISTOR0402-RES"))
    )
    (comp (ref "R93")
      (value "0")
      (footprint "eagle-import:0402-RES")
      (fields (field (name "MPN") "ERJ-2GE0R00X"))
      (libsource (lib "eagle-import") (part "RESISTOR0402-RES"))
    )
    (comp (ref "R94")
      (value "0")
      (footprint "eagle-import:0402-RES")
      (fields (field (name "MPN") "ERJ-2GE0R00X"))
      (libsource (lib "eagle-import") (part "RESISTOR0402-RES"))
    )
    (comp (ref "R95")
      (value "0")
      (footprint "eagle-import:0402-RES")
      (fields (field (name "MPN") "ERJ-2GE0R00X"))
      (libsource (lib "eagle-import") (part "RESISTOR0402-RES"))
    )
    (comp (ref "R104")
      (value "4.7k")
      (footprint "eagle-import:0402-RES")
      (fields (field (name "MPN") "ERJ-2RKF4701X"))
      (libsource (lib "eagle-import") (part "RESISTOR0402-RES"))
    )
    (comp (ref "R106")
      (value "NC")
      (footprint "eagle-import:0402-RES")
      (libsource (lib "eagle-import") (part "RESISTOR0402-RES"))
    )
    (comp (ref "R107")
      (value "NC")
      (footprint "eagle-import:0402-RES")
      (libsource (lib "eagle-import") (part "RESISTOR0402-RES"))
    )
    (comp (ref "R108")
      (value "0")
      (footprint "eagle-import:0402-RES")
      (fields (field (name "MPN") "ERJ-2GE0R00X"))
      (libsource (lib "eagle-import") (part "RESISTOR0402-RES"))
    )
    (comp (ref "R110")
      (value "1k")
      (footprint "eagle-import:0402-RES")
      (fields (field (name "MPN") "ERJ-2RKF1001X"))
      (libsource (lib "eagle-import") (part "RESISTOR0402-RES"))
    )
    (comp (ref "R111")
      (value "1k")
      (footprint "eagle-import:0402-RES")
      (fields (field (name "MPN") "ERJ-2RKF1001X"))
      (libsource (lib "eagle-import") (part "RESISTOR0402-RES"))
    )
    (comp (ref "R134")
      (value "10k")
      (footprint "eagle-import:0402-RES")
      (fields (field (name "MPN") "ERJ-2RKF1002X"))
      (libsource (lib "eagle-import") (part "RESISTOR0402-RES"))
    )
    (comp (ref "R135")
      (value "10k")
      (footprint "eagle-import:0402-RES")
      (fields (field (name "MPN") "ERJ-2RKF1002X"))
      (libsource (lib "eagle-import") (part "RESISTOR0402-RES"))
    )
    (comp (ref "R136")
      (value "4.7k")
      (footprint "eagle-import:0402-RES")
      (fields (field (name "MPN") "ERJ-2RKF4701X"))
      (libsource (lib "eagle-import") (part "RESISTOR0402-RES"))
    )
    (comp (ref "R137")
      (value "220k")
      (footprint "eagle-import:0402-RES")
      (fields (field (name "MPN") "ERJ-2RKF2203X"))
      (libsource (lib "eagle-import") (part "RESISTOR0402-RES"))
    )
    (comp (ref "R138")
      (value "10k")
      (footprint "eagle-import:0402-RES")
      (fields (field (name "MPN") "ERJ-2RKF1002X"))
      (libsource (lib "eagle-import") (part "RESISTOR0402-RES"))
    )
    (comp (ref "R141")
      (value "NC")
      (footprint "eagle-import:0402-RES")
      (libsource (lib "eagle-import") (part "RESISTOR0402-RES"))
    )
    (comp (ref "TP2")
      (value "TPTP06R")
      (footprint "eagle-import:TP06R")
      (fields (field (name "TP_SIGNAL_NAME") "GND"))
      (libsource (lib "eagle-import") (part "TPTP06R"))
    )
    (comp (ref "U14")
      (value "ASDM1-12.000MHZ-LC-T")
      (footprint "eagle-import:ASDM1")
      (fields
        (field (name "MF") "Abracon")
        (field (name "MPN") "ASDM")
        (field (name "MPN_1") "ASDM1-12.000MHZ-LC-T")
      )
      (libsource (lib "eagle-import") (part "ASDM"))
    )
    (comp (ref "U17")
      (value "TLV320AIC3204IRHBT")
      (footprint "eagle-import:QFN50P500X500X100-33N")
      (fields (field (name "MPN") "TLV320AIC3204IRHBT"))
      (libsource (lib "eagle-import") (part "TLV320AIC3204IRHBT"))
    )
    (comp (ref "U18")
      (value "SN74CBTLV3245APW")
      (footprint "eagle-import:SOP65P640X120-20N")
      (fields (field (name "MPN") "SN74CBTLV3245APWR"))
      (libsource (lib "eagle-import") (part "SN74CBTLV3245APW"))
    )
    (comp (ref "C21X")
      (value "22u")
      (footprint "eagle-import:C1206K")
      (fields (field (name "MPN") "GRM31CR71A226KE15L"))
      (libsource (lib "eagle-import") (part "C-EUC1206K"))
    )
    (comp (ref "C23X")
      (value "22u")
      (footprint "eagle-import:C1210K")
      (fields (field (name "MPN") "GRM32ER71E226ME15L"))
      (libsource (lib "eagle-import") (part "C-EUC1210K"))
    )
    (comp (ref "C26X")
      (value "1u")
      (footprint "eagle-import:C0402K")
      (fields (field (name "MPN") "GRM155R70J105KA12D"))
      (libsource (lib "eagle-import") (part "resistor_C-EUC0402K"))
    )
    (comp (ref "C94X")
      (value "22u")
      (footprint "eagle-import:C1206K")
      (fields (field (name "MPN") "GRM31CR71A226KE15L"))
      (libsource (lib "eagle-import") (part "C-EUC1206K"))
    )
    (comp (ref "C95X")
      (value "820p")
      (footprint "eagle-import:C0402K")
      (fields (field (name "MPN") "GRM1555C1H821JA01D"))
      (libsource (lib "eagle-import") (part "resistor_C-EUC0402K"))
    )
    (comp (ref "C98X")
      (value "0.1u")
      (footprint "eagle-import:C0402K")
      (fields (field (name "MPN") "GRM155R71C104JA88D"))
      (libsource (lib "eagle-import") (part "resistor_C-EUC0402K"))
    )
    (comp (ref "C99X")
      (value "22u")
      (footprint "eagle-import:C1210K")
      (fields (field (name "MPN") "GRM32ER71E226ME15L"))
      (libsource (lib "eagle-import") (part "C-EUC1210K"))
    )
    (comp (ref "C124X")
      (value "0.1u")
      (footprint "eagle-import:C0402K")
      (fields (field (name "MPN") "GRM155R71C104JA88D"))
      (libsource (lib "eagle-import") (part "resistor_C-EUC0402K"))
    )
    (comp (ref "C125X")
      (value "0.1u")
      (footprint "eagle-import:C0402K")
      (fields (field (name "MPN") "GRM155R71C104JA88D"))
      (libsource (lib "eagle-import") (part "resistor_C-EUC0402K"))
    )
    (comp (ref "C213X")
      (value "0.1u")
      (footprint "eagle-import:C0402K")
      (fields (field (name "MPN") "GRM155R71C104JA88D"))
      (libsource (lib "eagle-import") (part "resistor_C-EUC0402K"))
    )
    (comp (ref "C215X")
      (value "0.1u")
      (footprint "eagle-import:C0402K")
      (fields (field (name "MPN") "GRM155R71C104JA88D"))
      (libsource (lib "eagle-import") (part "resistor_C-EUC0402K"))
    )
    (comp (ref "C216X")
      (value "0.1u")
      (footprint "eagle-import:C0402K")
      (fields (field (name "MPN") "GRM155R71C104JA88D"))
      (libsource (lib "eagle-import") (part "resistor_C-EUC0402K"))
    )
    (comp (ref "C217X")
      (value "1u")
      (footprint "eagle-import:C0402K")
      (fields (field (name "MPN") "GRM155R70J105KA12D"))
      (libsource (lib "eagle-import") (part "resistor_C-EUC0402K"))
    )
    (comp (ref "C218X")
      (value "10u")
      (footprint "eagle-import:C0603K")
      (fields (field (name "MPN") "GRM188R61C106MA73D"))
      (libsource (lib "eagle-import") (part "resistor_C-EUC0603K"))
    )
    (comp (ref "L6X")
      (value "2.2u")
      (footprint "eagle-import:SRN3015")
      (fields (field (name "MPN") "SRN3015-2R2M"))
      (libsource (lib "eagle-import") (part "SRN3015"))
    )
    (comp (ref "L7X")
      (value "3.3u")
      (footprint "eagle-import:SRN3015")
      (fields (field (name "MPN") "SRN3015-3R3M"))
      (libsource (lib "eagle-import") (part "SRN3015"))
    )
    (comp (ref "L8X")
      (value "BML15HD601SN1")
      (footprint "eagle-import:0402")
      (fields (field (name "MPN") "BLM15HD601SN1D"))
      (libsource (lib "eagle-import") (part "BML15HD601SN1"))
    )
    (comp (ref "R1X")
      (value "0")
      (footprint "eagle-import:0402-RES")
      (fields (field (name "MPN") "ERJ-2GE0R00X"))
      (libsource (lib "eagle-import") (part "RESISTOR0402-RES"))
    )
    (comp (ref "R2X")
      (value "0")
      (footprint "eagle-import:0402-RES")
      (fields (field (name "MPN") "ERJ-2GE0R00X"))
      (libsource (lib "eagle-import") (part "RESISTOR0402-RES"))
    )
    (comp (ref "R3X")
      (value "1k")
      (footprint "eagle-import:0402-RES")
      (fields (field (name "MPN") "ERJ-2RKF1001X"))
      (libsource (lib "eagle-import") (part "RESISTOR0402-RES"))
    )
    (comp (ref "R11X")
      (value "13.7k")
      (footprint "eagle-import:0402-RES")
      (fields (field (name "MPN") "ERJ-2RKF1372X"))
      (libsource (lib "eagle-import") (part "RESISTOR0402-RES"))
    )
    (comp (ref "R15")
      (value "0")
      (footprint "eagle-import:0402-RES")
      (fields (field (name "MPN") "ERJ-2GE0R00X"))
      (libsource (lib "eagle-import") (part "RESISTOR0402-RES"))
    )
    (comp (ref "R15X")
      (value "10k")
      (footprint "eagle-import:0402-RES")
      (fields (field (name "MPN") "ERJ-2RKF1002X"))
      (libsource (lib "eagle-import") (part "RESISTOR0402-RES"))
    )
    (comp (ref "R65X")
      (value "33.2k")
      (footprint "eagle-import:0402-RES")
      (fields (field (name "MPN") "ERJ-2RKF3322X"))
      (libsource (lib "eagle-import") (part "RESISTOR0402-RES"))
    )
    (comp (ref "R70X")
      (value "10k")
      (footprint "eagle-import:0402-RES")
      (fields (field (name "MPN") "ERJ-2RKF1002X"))
      (libsource (lib "eagle-import") (part "RESISTOR0402-RES"))
    )
    (comp (ref "R96X")
      (value "0")
      (footprint "eagle-import:0402-RES")
      (fields (field (name "MPN") "ERJ-2GE0R00X"))
      (libsource (lib "eagle-import") (part "RESISTOR0402-RES"))
    )
    (comp (ref "R118X")
      (value "0")
      (footprint "eagle-import:0402-RES")
      (fields (field (name "MPN") "ERJ-2GE0R00X"))
      (libsource (lib "eagle-import") (part "RESISTOR0402-RES"))
    )
    (comp (ref "R119X")
      (value "0")
      (footprint "eagle-import:0402-RES")
      (fields (field (name "MPN") "ERJ-2GE0R00X"))
      (libsource (lib "eagle-import") (part "RESISTOR0402-RES"))
    )
    (comp (ref "R125X")
      (value "20.5k")
      (footprint "eagle-import:0402-RES")
      (fields (field (name "MPN") "ERJ-2RKF2052X"))
      (libsource (lib "eagle-import") (part "RESISTOR0402-RES"))
    )
    (comp (ref "R126X")
      (value "243k")
      (footprint "eagle-import:0402-RES")
      (fields (field (name "MPN") "ERJ-2RKF2433X"))
      (libsource (lib "eagle-import") (part "RESISTOR0402-RES"))
    )
    (comp (ref "R222X")
      (value "10k")
      (footprint "eagle-import:0402-RES")
      (fields (field (name "MPN") "ERJ-2RKF1002X"))
      (libsource (lib "eagle-import") (part "RESISTOR0402-RES"))
    )
    (comp (ref "R223X")
      (value "10")
      (footprint "eagle-import:0402-RES")
      (fields (field (name "MPN") "ERJ-2RKF10R0X"))
      (libsource (lib "eagle-import") (part "RESISTOR0402-RES"))
    )
    (comp (ref "R224X")
      (value "10")
      (footprint "eagle-import:0402-RES")
      (fields (field (name "MPN") "ERJ-2RKF10R0X"))
      (libsource (lib "eagle-import") (part "RESISTOR0402-RES"))
    )
    (comp (ref "R225X")
      (value "10")
      (footprint "eagle-import:0402-RES")
      (fields (field (name "MPN") "ERJ-2RKF10R0X"))
      (libsource (lib "eagle-import") (part "RESISTOR0402-RES"))
    )
    (comp (ref "R226X")
      (value "10")
      (footprint "eagle-import:0402-RES")
      (fields (field (name "MPN") "ERJ-2RKF10R0X"))
      (libsource (lib "eagle-import") (part "RESISTOR0402-RES"))
    )
    (comp (ref "R227X")
      (value "10")
      (footprint "eagle-import:0402-RES")
      (fields (field (name "MPN") "ERJ-2RKF10R0X"))
      (libsource (lib "eagle-import") (part "RESISTOR0402-RES"))
    )
    (comp (ref "R228X")
      (value "10")
      (footprint "eagle-import:0402-RES")
      (fields (field (name "MPN") "ERJ-2RKF10R0X"))
      (libsource (lib "eagle-import") (part "RESISTOR0402-RES"))
    )
    (comp (ref "R229X")
      (value "10")
      (footprint "eagle-import:0402-RES")
      (fields (field (name "MPN") "ERJ-2RKF10R0X"))
      (libsource (lib "eagle-import") (part "RESISTOR0402-RES"))
    )
    (comp (ref "R230X")
      (value "10")
      (footprint "eagle-import:0402-RES")
      (fields (field (name "MPN") "ERJ-2RKF10R0X"))
      (libsource (lib "eagle-import") (part "RESISTOR0402-RES"))
    )
    (comp (ref "TP4X")
      (value "TPTP06R")
      (footprint "eagle-import:TP06R")
      (fields (field (name "TP_SIGNAL_NAME") "VCC_1V8_TP"))
      (libsource (lib "eagle-import") (part "TPTP06R"))
    )
    (comp (ref "TP5X")
      (value "TPTP06R")
      (footprint "eagle-import:TP06R")
      (fields (field (name "TP_SIGNAL_NAME") "VCC_3V3_TP"))
      (libsource (lib "eagle-import") (part "TPTP06R"))
    )
    (comp (ref "TP6X")
      (value "TPTP06R")
      (footprint "eagle-import:TP06R")
      (libsource (lib "eagle-import") (part "TPTP06R"))
    )
    (comp (ref "TP7X")
      (value "TPTP06R")
      (footprint "eagle-import:TP06R")
      (libsource (lib "eagle-import") (part "TPTP06R"))
    )
    (comp (ref "U1X")
      (value "TPS562209SO")
      (footprint "eagle-import:SOT95P280X145-6N")
      (fields (field (name "MPN") "TPS562209DDCT"))
      (libsource (lib "eagle-import") (part "TPS562209SO"))
    )
    (comp (ref "U3X")
      (value "TPS3803-01DCKR")
      (footprint "eagle-import:SOT65P210X110-5N")
      (fields (field (name "MPN") "TPS3803-01DCKR"))
      (libsource (lib "eagle-import") (part "TPS3803-01DCKR"))
    )
    (comp (ref "U11X")
      (value "TPS73201DBVT")
      (footprint "eagle-import:SOT95P280X145-5N")
      (fields (field (name "MPN") "TPS73201DBVT"))
      (libsource (lib "eagle-import") (part "TPS73201DBVT"))
    )
    (comp (ref "U12X")
      (value "TPS562209SO")
      (footprint "eagle-import:SOT95P280X145-6N")
      (fields (field (name "MPN") "TPS562209DDCT"))
      (libsource (lib "eagle-import") (part "TPS562209SO"))
    )
    (comp (ref "U15X")
      (value "CDCLVC1108PWR")
      (footprint "eagle-import:SOP65P640X120-16N")
      (fields (field (name "MPN") "CDCLVC1108PWR"))
      (libsource (lib "eagle-import") (part "CDCLVC1108PWR"))
    )
    (comp (ref "C1")
      (value "10u")
      (footprint "eagle-import:C0603K")
      (fields (field (name "MPN") "GRM188R61C106MA73D"))
      (libsource (lib "eagle-import") (part "C-EUC0603K"))
    )
    (comp (ref "C2")
      (value "1u")
      (footprint "eagle-import:C0402K")
      (fields (field (name "MPN") "GRM155R70J105KA12D"))
      (libsource (lib "eagle-import") (part "resistor_C-EUC0402K"))
    )
    (comp (ref "C3")
      (value "10u")
      (footprint "eagle-import:C0603K")
      (fields (field (name "MPN") "GRM188R61C106MA73D"))
      (libsource (lib "eagle-import") (part "C-EUC0603K"))
    )
    (comp (ref "C4")
      (value "10u")
      (footprint "eagle-import:C0603K")
      (fields (field (name "MPN") "GRM188R61C106MA73D"))
      (libsource (lib "eagle-import") (part "C-EUC0603K"))
    )
    (comp (ref "C5")
      (value "1u")
      (footprint "eagle-import:C0402K")
      (fields (field (name "MPN") "GRM155R70J105KA12D"))
      (libsource (lib "eagle-import") (part "resistor_C-EUC0402K"))
    )
    (comp (ref "C28")
      (value "0.1u")
      (footprint "eagle-import:C0402K")
      (fields (field (name "MPN") "GRM155R71C104JA88D"))
      (libsource (lib "eagle-import") (part "resistor_C-EUC0402K"))
    )
    (comp (ref "C29")
      (value "0.1u")
      (footprint "eagle-import:C0402K")
      (fields (field (name "MPN") "GRM155R71C104JA88D"))
      (libsource (lib "eagle-import") (part "resistor_C-EUC0402K"))
    )
    (comp (ref "C30")
      (value "0.1u")
      (footprint "eagle-import:C0402K")
      (fields (field (name "MPN") "GRM155R71C104JA88D"))
      (libsource (lib "eagle-import") (part "resistor_C-EUC0402K"))
    )
    (comp (ref "C32")
      (value "0.1u")
      (footprint "eagle-import:0402")
      (fields (field (name "MPN") "GRM155R71C104JA88D"))
      (libsource (lib "eagle-import") (part "C0402_BGA"))
    )
    (comp (ref "C38")
      (value "10n")
      (footprint "eagle-import:0402")
      (fields (field (name "MPN") "GRM155R71E103KA01D"))
      (libsource (lib "eagle-import") (part "C0402_BGA"))
    )
    (comp (ref "C40")
      (value "0.1u")
      (footprint "eagle-import:0402")
      (fields (field (name "MPN") "GRM155R71C104JA88D"))
      (libsource (lib "eagle-import") (part "C0402_BGA"))
    )
    (comp (ref "C41")
      (value "10n")
      (footprint "eagle-import:0402")
      (fields (field (name "MPN") "GRM155R71E103KA01D"))
      (libsource (lib "eagle-import") (part "C0402_BGA"))
    )
    (comp (ref "C42")
      (value "1u")
      (footprint "eagle-import:0402")
      (fields (field (name "MPN") "GRM155R70J105KA12D"))
      (libsource (lib "eagle-import") (part "C0402_BGA"))
    )
    (comp (ref "C43")
      (value "10n")
      (footprint "eagle-import:0402")
      (fields (field (name "MPN") "GRM155R71E103KA01D"))
      (libsource (lib "eagle-import") (part "C0402_BGA"))
    )
    (comp (ref "C45")
      (value "0.1u")
      (footprint "eagle-import:0402")
      (fields (field (name "MPN") "GRM155R71C104JA88D"))
      (libsource (lib "eagle-import") (part "C0402_BGA"))
    )
    (comp (ref "C46")
      (value "0.1u")
      (footprint "eagle-import:0402")
      (fields (field (name "MPN") "GRM155R71C104JA88D"))
      (libsource (lib "eagle-import") (part "C0402_BGA"))
    )
    (comp (ref "C48")
      (value "0.1u")
      (footprint "eagle-import:0402")
      (fields (field (name "MPN") "GRM155R71C104JA88D"))
      (libsource (lib "eagle-import") (part "C0402_BGA"))
    )
    (comp (ref "C49")
      (value "0.1u")
      (footprint "eagle-import:0402")
      (fields (field (name "MPN") "GRM155R71C104JA88D"))
      (libsource (lib "eagle-import") (part "C0402_BGA"))
    )
    (comp (ref "C50")
      (value "1n")
      (footprint "eagle-import:0402")
      (fields (field (name "MPN") "GRM155R71H102JA01J"))
      (libsource (lib "eagle-import") (part "C0402_BGA"))
    )
    (comp (ref "C51")
      (value "10n")
      (footprint "eagle-import:0402")
      (fields (field (name "MPN") "GRM155R71E103KA01D"))
      (libsource (lib "eagle-import") (part "C0402_BGA"))
    )
    (comp (ref "C52")
      (value "1u")
      (footprint "eagle-import:0402")
      (fields (field (name "MPN") "GRM155R70J105KA12D"))
      (libsource (lib "eagle-import") (part "C0402_BGA"))
    )
    (comp (ref "C53")
      (value "1u")
      (footprint "eagle-import:0402")
      (fields (field (name "MPN") "GRM155R70J105KA12D"))
      (libsource (lib "eagle-import") (part "C0402_BGA"))
    )
    (comp (ref "C54")
      (value "1u")
      (footprint "eagle-import:0402")
      (fields (field (name "MPN") "GRM155R70J105KA12D"))
      (libsource (lib "eagle-import") (part "C0402_BGA"))
    )
    (comp (ref "C55")
      (value "10n")
      (footprint "eagle-import:0402")
      (fields (field (name "MPN") "GRM155R71E103KA01D"))
      (libsource (lib "eagle-import") (part "C0402_BGA"))
    )
    (comp (ref "C56")
      (value "1n")
      (footprint "eagle-import:0402")
      (fields (field (name "MPN") "GRM155R71H102JA01J"))
      (libsource (lib "eagle-import") (part "C0402_BGA"))
    )
    (comp (ref "C57")
      (value "0.1u")
      (footprint "eagle-import:0402")
      (fields (field (name "MPN") "GRM155R71C104JA88D"))
      (libsource (lib "eagle-import") (part "C0402_BGA"))
    )
    (comp (ref "C59")
      (value "0.1u")
      (footprint "eagle-import:0402")
      (fields (field (name "MPN") "GRM155R71C104JA88D"))
      (libsource (lib "eagle-import") (part "C0402_BGA"))
    )
    (comp (ref "C60")
      (value "0.1u")
      (footprint "eagle-import:0402")
      (fields (field (name "MPN") "GRM155R71C104JA88D"))
      (libsource (lib "eagle-import") (part "C0402_BGA"))
    )
    (comp (ref "C62")
      (value "0.1u")
      (footprint "eagle-import:0402")
      (fields (field (name "MPN") "GRM155R71C104JA88D"))
      (libsource (lib "eagle-import") (part "C0402_BGA"))
    )
    (comp (ref "C63")
      (value "0.1u")
      (footprint "eagle-import:0402")
      (fields (field (name "MPN") "GRM155R71C104JA88D"))
      (libsource (lib "eagle-import") (part "C0402_BGA"))
    )
    (comp (ref "C64")
      (value "1u")
      (footprint "eagle-import:0402")
      (fields (field (name "MPN") "GRM155R70J105KA12D"))
      (libsource (lib "eagle-import") (part "C0402_BGA"))
    )
    (comp (ref "C65")
      (value "0.1u")
      (footprint "eagle-import:0402")
      (fields (field (name "MPN") "GRM155R71C104JA88D"))
      (libsource (lib "eagle-import") (part "C0402_BGA"))
    )
    (comp (ref "C67")
      (value "0.1u")
      (footprint "eagle-import:0402")
      (fields (field (name "MPN") "GRM155R71C104JA88D"))
      (libsource (lib "eagle-import") (part "C0402_BGA"))
    )
    (comp (ref "C69")
      (value "0.1u")
      (footprint "eagle-import:0402")
      (fields (field (name "MPN") "GRM155R71C104JA88D"))
      (libsource (lib "eagle-import") (part "C0402_BGA"))
    )
    (comp (ref "C71")
      (value "0.1u")
      (footprint "eagle-import:0402")
      (fields (field (name "MPN") "GRM155R71C104JA88D"))
      (libsource (lib "eagle-import") (part "C0402_BGA"))
    )
    (comp (ref "C72")
      (value "0.1u")
      (footprint "eagle-import:0402")
      (fields (field (name "MPN") "GRM155R71C104JA88D"))
      (libsource (lib "eagle-import") (part "C0402_BGA"))
    )
    (comp (ref "C73")
      (value "10n")
      (footprint "eagle-import:0402")
      (fields (field (name "MPN") "GRM155R71E103KA01D"))
      (libsource (lib "eagle-import") (part "C0402_BGA"))
    )
    (comp (ref "C74")
      (value "1n")
      (footprint "eagle-import:C0402K")
      (fields (field (name "MPN") "GRM155R71H102JA01J"))
      (libsource (lib "eagle-import") (part "resistor_C-EUC0402K"))
    )
    (comp (ref "C75")
      (value "0.1u")
      (footprint "eagle-import:0402")
      (fields (field (name "MPN") "GRM155R71C104JA88D"))
      (libsource (lib "eagle-import") (part "C0402_BGA"))
    )
    (comp (ref "C85")
      (value "0.1u")
      (footprint "eagle-import:0402")
      (fields (field (name "MPN") "GRM155R71C104JA88D"))
      (libsource (lib "eagle-import") (part "C0402_BGA"))
    )
    (comp (ref "C86")
      (value "1u")
      (footprint "eagle-import:0402")
      (fields (field (name "MPN") "GRM155R70J105KA12D"))
      (libsource (lib "eagle-import") (part "C0402_BGA"))
    )
    (comp (ref "C87")
      (value "0.1u")
      (footprint "eagle-import:0402")
      (fields (field (name "MPN") "GRM155R71C104JA88D"))
      (libsource (lib "eagle-import") (part "C0402_BGA"))
    )
    (comp (ref "C88")
      (value "0.1u")
      (footprint "eagle-import:0402")
      (fields (field (name "MPN") "GRM155R71C104JA88D"))
      (libsource (lib "eagle-import") (part "C0402_BGA"))
    )
    (comp (ref "C89")
      (value "10n")
      (footprint "eagle-import:C0402K")
      (fields (field (name "MPN") "GRM155R71E103KA01D"))
      (libsource (lib "eagle-import") (part "resistor_C-EUC0402K"))
    )
    (comp (ref "FB1")
      (value "BLM18AG601SN1D")
      (footprint "eagle-import:0603")
      (libsource (lib "eagle-import") (part "INDUCTOR0603"))
    )
    (comp (ref "FB4")
      (value "BLM18AG601SN1D")
      (footprint "eagle-import:0603")
      (libsource (lib "eagle-import") (part "INDUCTOR0603"))
    )
    (comp (ref "FB5")
      (value "BLM18AG601SN1D")
      (footprint "eagle-import:0603")
      (libsource (lib "eagle-import") (part "INDUCTOR0603"))
    )
    (comp (ref "FB6")
      (value "BLM18AG601SN1D")
      (footprint "eagle-import:0603")
      (libsource (lib "eagle-import") (part "INDUCTOR0603"))
    )
    (comp (ref "L3")
      (value "BLM18AG601SN1D")
      (footprint "eagle-import:0603")
      (libsource (lib "eagle-import") (part "INDUCTOR0603"))
    )
    (comp (ref "R60")
      (value "0")
      (footprint "eagle-import:0402-RES")
      (fields (field (name "MPN") "ERJ-2GE0R00X"))
      (libsource (lib "eagle-import") (part "RESISTOR0402-RES"))
    )
    (comp (ref "R61")
      (value "0")
      (footprint "eagle-import:0402-RES")
      (fields (field (name "MPN") "ERJ-2GE0R00X"))
      (libsource (lib "eagle-import") (part "RESISTOR0402-RES"))
    )
    (comp (ref "R62")
      (value "NC")
      (footprint "eagle-import:0402-RES")
      (libsource (lib "eagle-import") (part "RESISTOR0402-RES"))
    )
    (comp (ref "R63")
      (value "NC")
      (footprint "eagle-import:0402-RES")
      (libsource (lib "eagle-import") (part "RESISTOR0402-RES"))
    )
    (comp (ref "R64")
      (value "0")
      (footprint "eagle-import:0402-RES")
      (fields (field (name "MPN") "ERJ-2GE0R00X"))
      (libsource (lib "eagle-import") (part "RESISTOR0402-RES"))
    )
    (comp (ref "R97")
      (value "0")
      (footprint "eagle-import:0805")
      (fields (field (name "MPN") "ERJ-2GE0R00X"))
      (libsource (lib "eagle-import") (part "RESISTOR0805-RES"))
    )
    (comp (ref "R121")
      (value "NC")
      (footprint "eagle-import:0805")
      (libsource (lib "eagle-import") (part "RESISTOR0805-RES"))
    )
    (comp (ref "R122")
      (value "0")
      (footprint "eagle-import:0805")
      (fields (field (name "MPN") "ERJ-6GEY0R00V"))
      (libsource (lib "eagle-import") (part "RESISTOR0805-RES"))
    )
    (comp (ref "R124")
      (value "0")
      (footprint "eagle-import:0805")
      (fields (field (name "MPN") "ERJ-6GEY0R00V"))
      (libsource (lib "eagle-import") (part "RESISTOR0805-RES"))
    )
    (comp (ref "U4")
      (value "TMS320C5535")
      (footprint "eagle-import:PBGA144")
      (fields (field (name "MPN") "TMS320C5535AZHH10"))
      (libsource (lib "eagle-import") (part "TMS320C5535S-PBGA-N144"))
    )
    (comp (ref "C9")
      (value "10u")
      (footprint "eagle-import:C0603K")
      (fields (field (name "MPN") "GRM188R61C106MA73D"))
      (libsource (lib "eagle-import") (part "C-EUC0603K"))
    )
    (comp (ref "C10")
      (value "10u")
      (footprint "eagle-import:C0603K")
      (fields (field (name "MPN") "GRM188R61C106MA73D"))
      (libsource (lib "eagle-import") (part "C-EUC0603K"))
    )
    (comp (ref "C15")
      (value "0.1u")
      (footprint "eagle-import:C0402K")
      (fields (field (name "MPN") "GRM155R71C104JA88D"))
      (libsource (lib "eagle-import") (part "resistor_C-EUC0402K"))
    )
    (comp (ref "C21")
      (value "0.1u")
      (footprint "eagle-import:C0402K")
      (fields (field (name "MPN") "GRM155R71C104JA88D"))
      (libsource (lib "eagle-import") (part "resistor_C-EUC0402K"))
    )
    (comp (ref "C81")
      (value "0.1u")
      (footprint "eagle-import:C0402K")
      (fields (field (name "MPN") "GRM155R71C104JA88D"))
      (libsource (lib "eagle-import") (part "resistor_C-EUC0402K"))
    )
    (comp (ref "C81-2")
      (value "0.1u")
      (footprint "eagle-import:C0402K")
      (fields (field (name "MPN") "GRM155R71C104JA88D"))
      (libsource (lib "eagle-import") (part "resistor_C-EUC0402K"))
    )
    (comp (ref "C169X")
      (value "0.1u")
      (footprint "eagle-import:C0402K")
      (fields (field (name "MPN") "GRM155R71C104JA88D"))
      (libsource (lib "eagle-import") (part "resistor_C-EUC0402K"))
    )
    (comp (ref "J6")
      (value "DM3BT-DSF-PEJS")
      (footprint "eagle-import:MICROSD_RBT")
      (libsource (lib "eagle-import") (part "SDMMCRBT"))
    )
    (comp (ref "J11")
      (value "DM3BT-DSF-PEJS")
      (footprint "eagle-import:MICROSD_RBT")
      (libsource (lib "eagle-import") (part "SDMMCRBT"))
    )
    (comp (ref "R1")
      (value "10k")
      (footprint "eagle-import:0402-RES")
      (fields (field (name "MPN") "ERJ-2RKF1002X"))
      (libsource (lib "eagle-import") (part "RESISTOR0402-RES"))
    )
    (comp (ref "R2")
      (value "10k")
      (footprint "eagle-import:0402-RES")
      (fields (field (name "MPN") "ERJ-2RKF1002X"))
      (libsource (lib "eagle-import") (part "RESISTOR0402-RES"))
    )
    (comp (ref "R3")
      (value "10k")
      (footprint "eagle-import:0402-RES")
      (fields (field (name "MPN") "ERJ-2RKF1002X"))
      (libsource (lib "eagle-import") (part "RESISTOR0402-RES"))
    )
    (comp (ref "R4")
      (value "10k")
      (footprint "eagle-import:0402-RES")
      (fields (field (name "MPN") "ERJ-2RKF1002X"))
      (libsource (lib "eagle-import") (part "RESISTOR0402-RES"))
    )
    (comp (ref "R6")
      (value "NC")
      (footprint "eagle-import:0402-RES")
      (libsource (lib "eagle-import") (part "RESISTOR0402-RES"))
    )
    (comp (ref "R7")
      (value "10k")
      (footprint "eagle-import:0402-RES")
      (fields (field (name "MPN") "ERJ-2RKF1002X"))
      (libsource (lib "eagle-import") (part "RESISTOR0402-RES"))
    )
    (comp (ref "R11")
      (value "10k")
      (footprint "eagle-import:0402-RES")
      (fields (field (name "MPN") "ERJ-2RKF1002X"))
      (libsource (lib "eagle-import") (part "RESISTOR0402-RES"))
    )
    (comp (ref "R16")
      (value "10k")
      (footprint "eagle-import:0402-RES")
      (fields (field (name "MPN") "ERJ-2RKF1002X"))
      (libsource (lib "eagle-import") (part "RESISTOR0402-RES"))
    )
    (comp (ref "R26")
      (value "0")
      (footprint "eagle-import:0402-RES")
      (fields (field (name "MPN") "ERJ-2GE0R00X"))
      (libsource (lib "eagle-import") (part "RESISTOR0402-RES"))
    )
    (comp (ref "R31")
      (value "0")
      (footprint "eagle-import:0402-RES")
      (fields (field (name "MPN") "ERJ-2GE0R00X"))
      (libsource (lib "eagle-import") (part "RESISTOR0402-RES"))
    )
    (comp (ref "R50")
      (value "10k")
      (footprint "eagle-import:0402-RES")
      (fields (field (name "MPN") "ERJ-2RKF1002X"))
      (libsource (lib "eagle-import") (part "RESISTOR0402-RES"))
    )
    (comp (ref "R50-2")
      (value "10k")
      (footprint "eagle-import:0402-RES")
      (fields (field (name "MPN") "ERJ-2RKF1002X"))
      (libsource (lib "eagle-import") (part "RESISTOR0402-RES"))
    )
    (comp (ref "R51")
      (value "10k")
      (footprint "eagle-import:0402-RES")
      (fields (field (name "MPN") "ERJ-2RKF1002X"))
      (libsource (lib "eagle-import") (part "RESISTOR0402-RES"))
    )
    (comp (ref "R51-2")
      (value "10k")
      (footprint "eagle-import:0402-RES")
      (fields (field (name "MPN") "ERJ-2RKF1002X"))
      (libsource (lib "eagle-import") (part "RESISTOR0402-RES"))
    )
    (comp (ref "R52")
      (value "10k")
      (footprint "eagle-import:0402-RES")
      (fields (field (name "MPN") "ERJ-2RKF1002X"))
      (libsource (lib "eagle-import") (part "RESISTOR0402-RES"))
    )
    (comp (ref "R52-1")
      (value "10k")
      (footprint "eagle-import:0402-RES")
      (fields (field (name "MPN") "ERJ-2RKF1002X"))
      (libsource (lib "eagle-import") (part "RESISTOR0402-RES"))
    )
    (comp (ref "R52-2")
      (value "10k")
      (footprint "eagle-import:0402-RES")
      (fields (field (name "MPN") "ERJ-2RKF1002X"))
      (libsource (lib "eagle-import") (part "RESISTOR0402-RES"))
    )
    (comp (ref "R72")
      (value "NC")
      (footprint "eagle-import:0402-RES")
      (libsource (lib "eagle-import") (part "RESISTOR0402-RES"))
    )
    (comp (ref "R72-2")
      (value "NC")
      (footprint "eagle-import:0402-RES")
      (libsource (lib "eagle-import") (part "RESISTOR0402-RES"))
    )
    (comp (ref "R73")
      (value "NC")
      (footprint "eagle-import:0402-RES")
      (libsource (lib "eagle-import") (part "RESISTOR0402-RES"))
    )
    (comp (ref "R73-2")
      (value "NC")
      (footprint "eagle-import:0402-RES")
      (libsource (lib "eagle-import") (part "RESISTOR0402-RES"))
    )
    (comp (ref "R98")
      (value "10k")
      (footprint "eagle-import:0402-RES")
      (fields (field (name "MPN") "ERJ-2RKF1002X"))
      (libsource (lib "eagle-import") (part "RESISTOR0402-RES"))
    )
    (comp (ref "R99")
      (value "10k")
      (footprint "eagle-import:0402-RES")
      (fields (field (name "MPN") "ERJ-2RKF1002X"))
      (libsource (lib "eagle-import") (part "RESISTOR0402-RES"))
    )
    (comp (ref "R100")
      (value "10k")
      (footprint "eagle-import:0402-RES")
      (fields (field (name "MPN") "ERJ-2RKF1002X"))
      (libsource (lib "eagle-import") (part "RESISTOR0402-RES"))
    )
    (comp (ref "R101")
      (value "NC")
      (footprint "eagle-import:0402-RES")
      (libsource (lib "eagle-import") (part "RESISTOR0402-RES"))
    )
    (comp (ref "R102")
      (value "10k")
      (footprint "eagle-import:0402-RES")
      (fields (field (name "MPN") "ERJ-2RKF1002X"))
      (libsource (lib "eagle-import") (part "RESISTOR0402-RES"))
    )
    (comp (ref "R103")
      (value "10k")
      (footprint "eagle-import:0402-RES")
      (fields (field (name "MPN") "ERJ-2RKF1002X"))
      (libsource (lib "eagle-import") (part "RESISTOR0402-RES"))
    )
    (comp (ref "R109")
      (value "10k")
      (footprint "eagle-import:0402-RES")
      (fields (field (name "MPN") "ERJ-2RKF1002X"))
      (libsource (lib "eagle-import") (part "RESISTOR0402-RES"))
    )
    (comp (ref "R143X")
      (value "NC")
      (footprint "eagle-import:0402-RES")
      (libsource (lib "eagle-import") (part "RESISTOR0402-RES"))
    )
    (comp (ref "U9")
      (value "W25Q64FVSFIG")
      (footprint "eagle-import:SO16L")
      (libsource (lib "eagle-import") (part "SPI_FLASH-X25XX"))
    )
    (comp (ref "U9-2")
      (value "W25Q64FVSFIG")
      (footprint "eagle-import:SO16L")
      (libsource (lib "eagle-import") (part "SPI_FLASH-X25XX"))
    )
    (comp (ref "U10X")
      (value "24C64SM")
      (footprint "eagle-import:SO-08M")
      (fields
        (field (name "MF") "RAMTRON INTERNATIONAL CORP")
        (field (name "MPN") "FM24C64-S")
        (field (name "MPN_1") "AT24C64D-SSHM-T")
      )
      (libsource (lib "eagle-import") (part "24SMC64"))
    )
    (comp (ref "C7")
      (value "10u")
      (footprint "eagle-import:C0603K")
      (fields (field (name "MPN") "GRM188R61C106MA73D"))
      (libsource (lib "eagle-import") (part "C-EUC0603K"))
    )
    (comp (ref "C20")
      (value "0.1u")
      (footprint "eagle-import:C0402K")
      (fields (field (name "MPN") "GRM155R71C104JA88D"))
      (libsource (lib "eagle-import") (part "resistor_C-EUC0402K"))
    )
    (comp (ref "C33")
      (value "10n")
      (footprint "eagle-import:C0402K")
      (fields (field (name "MPN") "GRM155R71E103KA01D"))
      (libsource (lib "eagle-import") (part "resistor_C-EUC0402K"))
    )
    (comp (ref "C34")
      (value "0.1u")
      (footprint "eagle-import:C0402K")
      (fields (field (name "MPN") "GRM155R71C104JA88D"))
      (libsource (lib "eagle-import") (part "resistor_C-EUC0402K"))
    )
    (comp (ref "C35")
      (value "0.1u")
      (footprint "eagle-import:C0402K")
      (fields (field (name "MPN") "GRM155R71C104JA88D"))
      (libsource (lib "eagle-import") (part "resistor_C-EUC0402K"))
    )
    (comp (ref "C36")
      (value "0.1u")
      (footprint "eagle-import:C0402K")
      (fields (field (name "MPN") "GRM155R71C104JA88D"))
      (libsource (lib "eagle-import") (part "resistor_C-EUC0402K"))
    )
    (comp (ref "C37")
      (value "10n")
      (footprint "eagle-import:C0402K")
      (fields (field (name "MPN") "GRM155R71E103KA01D"))
      (libsource (lib "eagle-import") (part "resistor_C-EUC0402K"))
    )
    (comp (ref "C44")
      (value "4.7u")
      (footprint "eagle-import:C0603K")
      (fields (field (name "MPN") "GRM188R60J475KE19D"))
      (libsource (lib "eagle-import") (part "C-EUC0603K"))
    )
    (comp (ref "C47")
      (value "0.1u")
      (footprint "eagle-import:C0402K")
      (fields (field (name "MPN") "GRM155R71C104JA88D"))
      (libsource (lib "eagle-import") (part "resistor_C-EUC0402K"))
    )
    (comp (ref "C58")
      (value "10n")
      (footprint "eagle-import:C0402K")
      (fields (field (name "MPN") "GRM155R71E103KA01D"))
      (libsource (lib "eagle-import") (part "resistor_C-EUC0402K"))
    )
    (comp (ref "C61")
      (value "0.1u")
      (footprint "eagle-import:C0402K")
      (fields (field (name "MPN") "GRM155R71C104JA88D"))
      (libsource (lib "eagle-import") (part "resistor_C-EUC0402K"))
    )
    (comp (ref "C68")
      (value "0.1u")
      (footprint "eagle-import:C0402K")
      (fields (field (name "MPN") "GRM155R71C104JA88D"))
      (libsource (lib "eagle-import") (part "resistor_C-EUC0402K"))
    )
    (comp (ref "C70")
      (value "0.1u")
      (footprint "eagle-import:C0402K")
      (fields (field (name "MPN") "GRM155R71C104JA88D"))
      (libsource (lib "eagle-import") (part "resistor_C-EUC0402K"))
    )
    (comp (ref "C76")
      (value "4.7u")
      (footprint "eagle-import:C0603K")
      (fields (field (name "MPN") "GRM188R60J475KE19D"))
      (libsource (lib "eagle-import") (part "C-EUC0603K"))
    )
    (comp (ref "C78")
      (value "0.1u")
      (footprint "eagle-import:C0402K")
      (fields (field (name "MPN") "GRM155R71C104JA88D"))
      (libsource (lib "eagle-import") (part "resistor_C-EUC0402K"))
    )
    (comp (ref "C79")
      (value "0.1u")
      (footprint "eagle-import:C0402K")
      (fields (field (name "MPN") "GRM155R71C104JA88D"))
      (libsource (lib "eagle-import") (part "resistor_C-EUC0402K"))
    )
    (comp (ref "C80")
      (value "0.1u")
      (footprint "eagle-import:C0402K")
      (fields (field (name "MPN") "GRM155R71C104JA88D"))
      (libsource (lib "eagle-import") (part "resistor_C-EUC0402K"))
    )
    (comp (ref "C92")
      (value "0.1u")
      (footprint "eagle-import:C0402K")
      (fields (field (name "MPN") "GRM155R71C104JA88D"))
      (libsource (lib "eagle-import") (part "resistor_C-EUC0402K"))
    )
    (comp (ref "C93")
      (value "10n")
      (footprint "eagle-import:C0402K")
      (fields (field (name "MPN") "GRM155R71E103KA01D"))
      (libsource (lib "eagle-import") (part "resistor_C-EUC0402K"))
    )
    (comp (ref "D1")
      (value "MBR0520LT")
      (footprint "eagle-import:SOD123")
      (fields (field (name "MPN") "MBR0520LT1G"))
      (libsource (lib "eagle-import") (part "MBR0520LT"))
    )
    (comp (ref "D3")
      (value "MBR0520LT")
      (footprint "eagle-import:SOD123")
      (fields (field (name "MPN") "MBR0520LT1G"))
      (libsource (lib "eagle-import") (part "MBR0520LT"))
    )
    (comp (ref "D4")
      (value "MBR0520LT")
      (footprint "eagle-import:SOD123")
      (fields (field (name "MPN") "MBR0520LT1G"))
      (libsource (lib "eagle-import") (part "MBR0520LT"))
    )
    (comp (ref "D5")
      (value "MBR0520LT")
      (footprint "eagle-import:SOD123")
      (fields (field (name "MPN") "MBR0520LT1G"))
      (libsource (lib "eagle-import") (part "MBR0520LT"))
    )
    (comp (ref "DS1")
      (value "GREEN")
      (footprint "eagle-import:CHIPLED_1206")
      (fields (field (name "MPN") "LTST-C230KGKT"))
      (libsource (lib "eagle-import") (part "LEDCHIPLED_1206"))
    )
    (comp (ref "J2")
      (value "USB-B-SMT")
      (footprint "eagle-import:USB-B-SMT")
      (fields (field (name "MPN") "M701-370442"))
      (libsource (lib "eagle-import") (part "USB-B-SMT"))
    )
    (comp (ref "L1")
      (value "BLM21PG221SN1")
      (footprint "eagle-import:0805")
      (fields (field (name "MPN") "BLM21PG221SN1D"))
      (libsource (lib "eagle-import") (part "INDUCTOR0805"))
    )
    (comp (ref "L4")
      (value "BLM21PG21SN1")
      (footprint "eagle-import:0805")
      (fields (field (name "MPN") "BLM21PG221SN1D"))
      (libsource (lib "eagle-import") (part "INDUCTOR0805"))
    )
    (comp (ref "L5")
      (value "BLM21PG221SN1")
      (footprint "eagle-import:0805")
      (fields (field (name "MPN") "BLM21PG221SN1D"))
      (libsource (lib "eagle-import") (part "INDUCTOR0805"))
    )
    (comp (ref "R12")
      (value "560")
      (footprint "eagle-import:0402-RES")
      (fields (field (name "MPN") "ERJ-2RKF2200X"))
      (libsource (lib "eagle-import") (part "RESISTOR0402-RES"))
    )
    (comp (ref "R19")
      (value "10k")
      (footprint "eagle-import:0402-RES")
      (fields (field (name "MPN") "ERJ-2RKF1002X"))
      (libsource (lib "eagle-import") (part "RESISTOR0402-RES"))
    )
    (comp (ref "R20")
      (value "NC")
      (footprint "eagle-import:0402-RES")
      (libsource (lib "eagle-import") (part "RESISTOR0402-RES"))
    )
    (comp (ref "R21")
      (value "2.2k")
      (footprint "eagle-import:0402-RES")
      (fields (field (name "MPN") "ERJ-2RKF2201X"))
      (libsource (lib "eagle-import") (part "RESISTOR0402-RES"))
    )
    (comp (ref "R23")
      (value "0")
      (footprint "eagle-import:0402-RES")
      (fields (field (name "MPN") "ERJ-2GE0R00X"))
      (libsource (lib "eagle-import") (part "RESISTOR0402-RES"))
    )
    (comp (ref "R24")
      (value "NC")
      (footprint "eagle-import:0402-RES")
      (libsource (lib "eagle-import") (part "RESISTOR0402-RES"))
    )
    (comp (ref "R27")
      (value "0")
      (footprint "eagle-import:0402-RES")
      (fields (field (name "MPN") "ERJ-2GE0R00X"))
      (libsource (lib "eagle-import") (part "RESISTOR0402-RES"))
    )
    (comp (ref "R28")
      (value "12k")
      (footprint "eagle-import:0402-RES")
      (fields (field (name "MPN") "ERJ-2RKF1202X"))
      (libsource (lib "eagle-import") (part "RESISTOR0402-RES"))
    )
    (comp (ref "R30")
      (value "0")
      (footprint "eagle-import:0402-RES")
      (fields (field (name "MPN") "ERJ-2GE0R00X"))
      (libsource (lib "eagle-import") (part "RESISTOR0402-RES"))
    )
    (comp (ref "R32")
      (value "0")
      (footprint "eagle-import:0402-RES")
      (fields (field (name "MPN") "ERJ-2GE0R00X"))
      (libsource (lib "eagle-import") (part "RESISTOR0402-RES"))
    )
    (comp (ref "R35")
      (value "0")
      (footprint "eagle-import:0402-RES")
      (fields (field (name "MPN") "ERJ-2GE0R00X"))
      (libsource (lib "eagle-import") (part "RESISTOR0402-RES"))
    )
    (comp (ref "R36")
      (value "10k")
      (footprint "eagle-import:0402-RES")
      (fields (field (name "MPN") "ERJ-2RKF1002X"))
      (libsource (lib "eagle-import") (part "RESISTOR0402-RES"))
    )
    (comp (ref "R39")
      (value "33")
      (footprint "eagle-import:0402-RES")
      (fields (field (name "MPN") "ERJ-2RKF33R0X"))
      (libsource (lib "eagle-import") (part "RESISTOR0402-RES"))
    )
    (comp (ref "R40")
      (value "NC")
      (footprint "eagle-import:0402-RES")
      (libsource (lib "eagle-import") (part "RESISTOR0402-RES"))
    )
    (comp (ref "R42")
      (value "10k")
      (footprint "eagle-import:0402-RES")
      (fields (field (name "MPN") "ERJ-2RKF1002X"))
      (libsource (lib "eagle-import") (part "RESISTOR0402-RES"))
    )
    (comp (ref "R43")
      (value "10k")
      (footprint "eagle-import:0402-RES")
      (fields (field (name "MPN") "ERJ-2RKF1002X"))
      (libsource (lib "eagle-import") (part "RESISTOR0402-RES"))
    )
    (comp (ref "R44")
      (value "10k")
      (footprint "eagle-import:0402-RES")
      (fields (field (name "MPN") "ERJ-2RKF1002X"))
      (libsource (lib "eagle-import") (part "RESISTOR0402-RES"))
    )
    (comp (ref "R45")
      (value "NC")
      (footprint "eagle-import:0402-RES")
      (libsource (lib "eagle-import") (part "RESISTOR0402-RES"))
    )
    (comp (ref "R46")
      (value "33")
      (footprint "eagle-import:0402-RES")
      (fields (field (name "MPN") "ERJ-2RKF33R0X"))
      (libsource (lib "eagle-import") (part "RESISTOR0402-RES"))
    )
    (comp (ref "R47")
      (value "33")
      (footprint "eagle-import:0402-RES")
      (fields (field (name "MPN") "ERJ-2RKF33R0X"))
      (libsource (lib "eagle-import") (part "RESISTOR0402-RES"))
    )
    (comp (ref "R48")
      (value "33")
      (footprint "eagle-import:0402-RES")
      (fields (field (name "MPN") "ERJ-2RKF33R0X"))
      (libsource (lib "eagle-import") (part "RESISTOR0402-RES"))
    )
    (comp (ref "R49")
      (value "33")
      (footprint "eagle-import:0402-RES")
      (fields (field (name "MPN") "ERJ-2RKF33R0X"))
      (libsource (lib "eagle-import") (part "RESISTOR0402-RES"))
    )
    (comp (ref "R53")
      (value "33")
      (footprint "eagle-import:0402-RES")
      (fields (field (name "MPN") "ERJ-2RKF33R0X"))
      (libsource (lib "eagle-import") (part "RESISTOR0402-RES"))
    )
    (comp (ref "R57")
      (value "4.7k")
      (footprint "eagle-import:0402-RES")
      (fields (field (name "MPN") "ERJ-2RKF4701X"))
      (libsource (lib "eagle-import") (part "RESISTOR0402-RES"))
    )
    (comp (ref "R58")
      (value "33")
      (footprint "eagle-import:0402-RES")
      (fields (field (name "MPN") "ERJ-2RKF33R0X"))
      (libsource (lib "eagle-import") (part "RESISTOR0402-RES"))
    )
    (comp (ref "U2")
      (value "AT93C46A-10TQ-2.7")
      (footprint "eagle-import:TSSOP8")
      (fields (field (name "MPN") "AT93C46D-TH-T"))
      (libsource (lib "eagle-import") (part "AT93C46A-10?Q-2.7T"))
    )
    (comp (ref "U6")
      (value "FT2232HL")
      (footprint "eagle-import:LQFP-10X10-64")
      (fields (field (name "MPN") "FT2232HL-REEL"))
      (libsource (lib "eagle-import") (part "FT2232H"))
    )
    (comp (ref "U7")
      (value "TPD2E001IDRLRQ1")
      (footprint "eagle-import:SOT50P160X60-5N")
      (fields (field (name "MPN") "TPD2E001DRLR"))
      (libsource (lib "eagle-import") (part "TPD2E001IDRLRQ1"))
    )
    (comp (ref "U8")
      (value "74LVC1G175DBVSOT95")
      (footprint "eagle-import:SOT95P280X145-6N")
      (fields (field (name "MPN") "SN74LVC1G175DBVT"))
      (libsource (lib "eagle-import") (part "74LVC1G175SOT95DBV"))
    )
    (comp (ref "C6")
      (value "10u")
      (footprint "eagle-import:C0603K")
      (fields (field (name "MPN") "GRM188R61C106MA73D"))
      (libsource (lib "eagle-import") (part "C-EUC0603K"))
    )
    (comp (ref "C24")
      (value "0.1u")
      (footprint "eagle-import:C0402K")
      (fields (field (name "MPN") "GRM155R71C104JA88D"))
      (libsource (lib "eagle-import") (part "resistor_C-EUC0402K"))
    )
    (comp (ref "C25")
      (value "10u")
      (footprint "eagle-import:C0603K")
      (fields (field (name "MPN") "GRM188R61C106MA73D"))
      (libsource (lib "eagle-import") (part "C-EUC0603K"))
    )
    (comp (ref "C66")
      (value "1n")
      (footprint "eagle-import:0402")
      (fields (field (name "MPN") "GRM155R71H102JA01J"))
      (libsource (lib "eagle-import") (part "C0402_BGA"))
    )
    (comp (ref "C77")
      (value "0.1u")
      (footprint "eagle-import:C0402K")
      (fields (field (name "MPN") "GRM155R71C104JA88D"))
      (libsource (lib "eagle-import") (part "resistor_C-EUC0402K"))
    )
    (comp (ref "C82")
      (value "0.1u")
      (footprint "eagle-import:0402")
      (fields (field (name "MPN") "GRM155R71C104JA88D"))
      (libsource (lib "eagle-import") (part "C0402_BGA"))
    )
    (comp (ref "C83")
      (value "1u")
      (footprint "eagle-import:0402")
      (fields (field (name "MPN") "GRM155R70J105KA12D"))
      (libsource (lib "eagle-import") (part "C0402_BGA"))
    )
    (comp (ref "C84")
      (value "0.1u")
      (footprint "eagle-import:0402")
      (fields (field (name "MPN") "GRM155R71C104JA88D"))
      (libsource (lib "eagle-import") (part "C0402_BGA"))
    )
    (comp (ref "C90")
      (value "10p")
      (footprint "eagle-import:C0402K")
      (fields (field (name "MPN") "GRM1555C1H100FA01D"))
      (libsource (lib "eagle-import") (part "resistor_C-EUC0402K"))
    )
    (comp (ref "C91")
      (value "10p")
      (footprint "eagle-import:C0402K")
      (fields (field (name "MPN") "GRM1555C1H100FA01D"))
      (libsource (lib "eagle-import") (part "resistor_C-EUC0402K"))
    )
    (comp (ref "D2")
      (value "6.2V")
      (footprint "eagle-import:SMADIODE")
      (fields (field (name "MPN") "1SMA5920BT3G") (field (name "PART_NUMBER") "SMAZ6V2-13-F"))
      (libsource (lib "eagle-import") (part "DIODESMA"))
    )
    (comp (ref "DS2")
      (value "GREEN")
      (footprint "eagle-import:CHIPLED_0603")
      (fields (field (name "MPN") "LTST-C190KGKT"))
      (libsource (lib "eagle-import") (part "LEDCHIPLED_0603"))
    )
    (comp (ref "FB7")
      (value "BLM18AG601SN1D")
      (footprint "eagle-import:0805")
      (fields (field (name "MPN") "BLM21AG151SN1D"))
      (libsource (lib "eagle-import") (part "INDUCTOR0805"))
    )
    (comp (ref "J1")
      (value "USB-MINIB-5PIN")
      (footprint "eagle-import:USB-MINIB")
      (fields (field (name "MPN") "10033526-N3212LF"))
      (libsource (lib "eagle-import") (part "USB-MINIB-5PIN"))
    )
    (comp (ref "R13")
      (value "10k")
      (footprint "eagle-import:0402-RES")
      (fields (field (name "MPN") "ERJ-2RKF1002X"))
      (libsource (lib "eagle-import") (part "RESISTOR0402-RES"))
    )
    (comp (ref "R14")
      (value "10k")
      (footprint "eagle-import:0402-RES")
      (fields (field (name "MPN") "ERJ-2RKF1002X"))
      (libsource (lib "eagle-import") (part "RESISTOR0402-RES"))
    )
    (comp (ref "R17")
      (value "220")
      (footprint "eagle-import:0402-RES")
      (fields (field (name "MPN") "ERJ-2RKF2200X"))
      (libsource (lib "eagle-import") (part "RESISTOR0402-RES"))
    )
    (comp (ref "R18")
      (value "100k")
      (footprint "eagle-import:0402-RES")
      (fields (field (name "MPN") "ERJ-2RKF1003X"))
      (libsource (lib "eagle-import") (part "RESISTOR0402-RES"))
    )
    (comp (ref "R22")
      (value "10k")
      (footprint "eagle-import:0402-RES")
      (fields (field (name "MPN") "ERJ-2RKF1002X"))
      (libsource (lib "eagle-import") (part "RESISTOR0402-RES"))
    )
    (comp (ref "R25")
      (value "10k")
      (footprint "eagle-import:0402-RES")
      (fields (field (name "MPN") "ERJ-2RKF1002X"))
      (libsource (lib "eagle-import") (part "RESISTOR0402-RES"))
    )
    (comp (ref "R29")
      (value "10k")
      (footprint "eagle-import:0402")
      (fields
        (field (name "MANUFACTURER_PART_NUMBER") "CRCW04021K00FKED")
        (field (name "POWER") "0.063")
        (field (name "TOLERANCE") "1.0")
        (field (name "MPN") "ERJ-2RKF1002X")
        (field (name "TOLERANCE_1") "1%")
      )
      (libsource (lib "eagle-import") (part "CRCW04021K00FKED"))
    )
    (comp (ref "R33")
      (value "10k")
      (footprint "eagle-import:0402-RES")
      (fields (field (name "MPN") "ERJ-2RKF1002X"))
      (libsource (lib "eagle-import") (part "RESISTOR0402-RES"))
    )
    (comp (ref "R34")
      (value "NC")
      (footprint "eagle-import:0402")
      (fields
        (field (name "MANUFACTURER_PART_NUMBER") "CRCW04021K00FKED")
        (field (name "POWER") "0.063")
        (field (name "TOLERANCE") "1.0")
      )
      (libsource (lib "eagle-import") (part "CRCW04021K00FKED"))
    )
    (comp (ref "R37")
      (value "100k")
      (footprint "eagle-import:0402-RES")
      (fields (field (name "MPN") "ERJ-2RKF1003X"))
      (libsource (lib "eagle-import") (part "RESISTOR0402-RES"))
    )
    (comp (ref "R38")
      (value "0")
      (footprint "eagle-import:0402")
      (fields
        (field (name "MANUFACTURER_PART_NUMBER") "CRCW04021K00FKED")
        (field (name "POWER") "0.063")
        (field (name "TOLERANCE") "1.0")
      )
      (libsource (lib "eagle-import") (part "CRCW04021K00FKED"))
    )
    (comp (ref "R41")
      (value "100k")
      (footprint "eagle-import:0402-RES")
      (fields (field (name "MPN") "ERJ-2RKF1003X"))
      (libsource (lib "eagle-import") (part "RESISTOR0402-RES"))
    )
    (comp (ref "R54")
      (value "0")
      (footprint "eagle-import:0402")
      (fields
        (field (name "MANUFACTURER_PART_NUMBER") "CRCW04021K00FKED")
        (field (name "POWER") "0.063")
        (field (name "TOLERANCE") "1.0")
      )
      (libsource (lib "eagle-import") (part "CRCW04021K00FKED"))
    )
    (comp (ref "R55")
      (value "0")
      (footprint "eagle-import:0402-RES")
      (fields (field (name "MPN") "ERJ-2GE0R00X"))
      (libsource (lib "eagle-import") (part "RESISTOR0402-RES"))
    )
    (comp (ref "R56")
      (value "NC")
      (footprint "eagle-import:0402-RES")
      (libsource (lib "eagle-import") (part "RESISTOR0402-RES"))
    )
    (comp (ref "R59")
      (value "10k")
      (footprint "eagle-import:0402-RES")
      (fields (field (name "MPN") "ERJ-2RKF1002X"))
      (libsource (lib "eagle-import") (part "RESISTOR0402-RES"))
    )
    (comp (ref "R67")
      (value "0")
      (footprint "eagle-import:0402")
      (fields
        (field (name "MANUFACTURER_PART_NUMBER") "CRCW04021K00FKED")
        (field (name "POWER") "0.063")
        (field (name "TOLERANCE") "1.0")
      )
      (libsource (lib "eagle-import") (part "CRCW04021K00FKED"))
    )
    (comp (ref "R84")
      (value "0")
      (footprint "eagle-import:0402-RES")
      (fields (field (name "MPN") "ERJ-2GE0R00X"))
      (libsource (lib "eagle-import") (part "RESISTOR0402-RES"))
    )
    (comp (ref "R117")
      (value "10k")
      (footprint "eagle-import:0402-RES")
      (fields (field (name "MPN") "ERJ-2RKF1002X"))
      (libsource (lib "eagle-import") (part "RESISTOR0402-RES"))
    )
    (comp (ref "TP1")
      (value "TPTP06R")
      (footprint "eagle-import:TP06R")
      (fields (field (name "TP_SIGNAL_NAME") "CLKOUT"))
      (libsource (lib "eagle-import") (part "TPTP06R"))
    )
    (comp (ref "TP4")
      (value "TPTP06R")
      (footprint "eagle-import:TP06R")
      (fields (field (name "TP_SIGNAL_NAME") "RTC_CLKOUT"))
      (libsource (lib "eagle-import") (part "TPTP06R"))
    )
    (comp (ref "TP14")
      (value "TPTP06R")
      (footprint "eagle-import:TP06R")
      (libsource (lib "eagle-import") (part "TPTP06R"))
    )
    (comp (ref "TP15")
      (value "TPTP06R")
      (footprint "eagle-import:TP06R")
      (libsource (lib "eagle-import") (part "TPTP06R"))
    )
    (comp (ref "TP16")
      (value "TPTP06R")
      (footprint "eagle-import:TP06R")
      (libsource (lib "eagle-import") (part "TPTP06R"))
    )
    (comp (ref "TP19")
      (value "TPTP06R")
      (footprint "eagle-import:TP06R")
      (libsource (lib "eagle-import") (part "TPTP06R"))
    )
    (comp (ref "TP20")
      (value "TPTP06R")
      (footprint "eagle-import:TP06R")
      (libsource (lib "eagle-import") (part "TPTP06R"))
    )
    (comp (ref "TP21")
      (value "TPTP06R")
      (footprint "eagle-import:TP06R")
      (libsource (lib "eagle-import") (part "TPTP06R"))
    )
    (comp (ref "Y1")
      (value "32.768kHz")
      (footprint "eagle-import:CRYSTAL-32KHZ-SMD_EPSON_MC146")
      (fields (field (name "MPN") "SSPT7F-12.5PF20-R"))
      (libsource (lib "eagle-import") (part "CRYSTAL"))
    )
    (comp (ref "C6-2")
      (value "10u")
      (footprint "eagle-import:C0603K")
      (fields (field (name "MPN") "GRM188R61C106MA73D"))
      (libsource (lib "eagle-import") (part "C-EUC0603K"))
    )
    (comp (ref "C24-2")
      (value "0.1u")
      (footprint "eagle-import:C0402K")
      (fields (field (name "MPN") "GRM155R71C104JA88D"))
      (libsource (lib "eagle-import") (part "resistor_C-EUC0402K"))
    )
    (comp (ref "C25-2")
      (value "10u")
      (footprint "eagle-import:C0603K")
      (fields (field (name "MPN") "GRM188R61C106MA73D"))
      (libsource (lib "eagle-import") (part "C-EUC0603K"))
    )
    (comp (ref "C66-2")
      (value "1n")
      (footprint "eagle-import:0402")
      (fields (field (name "MPN") "GRM155R71H102JA01J"))
      (libsource (lib "eagle-import") (part "C0402_BGA"))
    )
    (comp (ref "C77-2")
      (value "0.1u")
      (footprint "eagle-import:C0402K")
      (fields (field (name "MPN") "GRM155R71C104JA88D"))
      (libsource (lib "eagle-import") (part "resistor_C-EUC0402K"))
    )
    (comp (ref "C82-2")
      (value "0.1u")
      (footprint "eagle-import:0402")
      (fields (field (name "MPN") "GRM155R71C104JA88D"))
      (libsource (lib "eagle-import") (part "C0402_BGA"))
    )
    (comp (ref "C83-2")
      (value "1u")
      (footprint "eagle-import:0402")
      (fields (field (name "MPN") "GRM155R70J105KA12D"))
      (libsource (lib "eagle-import") (part "C0402_BGA"))
    )
    (comp (ref "C84-2")
      (value "0.1u")
      (footprint "eagle-import:0402")
      (fields (field (name "MPN") "GRM155R71C104JA88D"))
      (libsource (lib "eagle-import") (part "C0402_BGA"))
    )
    (comp (ref "C90-2")
      (value "10p")
      (footprint "eagle-import:C0402K")
      (fields (field (name "MPN") "GRM1555C1H100FA01D"))
      (libsource (lib "eagle-import") (part "resistor_C-EUC0402K"))
    )
    (comp (ref "C91-2")
      (value "10p")
      (footprint "eagle-import:C0402K")
      (fields (field (name "MPN") "GRM1555C1H100FA01D"))
      (libsource (lib "eagle-import") (part "resistor_C-EUC0402K"))
    )
    (comp (ref "D2-2")
      (value "6.2V")
      (footprint "eagle-import:SMADIODE")
      (fields (field (name "MPN") "1SMA5920BT3G") (field (name "PART_NUMBER") "SMAZ6V2-13-F"))
      (libsource (lib "eagle-import") (part "DIODESMA"))
    )
    (comp (ref "D3X")
      (value "GREEN")
      (footprint "eagle-import:CHIPLED_0603")
      (fields (field (name "MPN") "LTST-C190KGKT"))
      (libsource (lib "eagle-import") (part "LEDCHIPLED_0603"))
    )
    (comp (ref "FB7-2")
      (value "BLM18AG601SN1D")
      (footprint "eagle-import:0805")
      (fields (field (name "MPN") "BLM21AG151SN1D"))
      (libsource (lib "eagle-import") (part "INDUCTOR0805"))
    )
    (comp (ref "J1-2")
      (value "USB-MINIB-5PIN")
      (footprint "eagle-import:USB-MINIB")
      (fields (field (name "MPN") "10033526-N3212LF"))
      (libsource (lib "eagle-import") (part "USB-MINIB-5PIN"))
    )
    (comp (ref "R13-2")
      (value "10k")
      (footprint "eagle-import:0402-RES")
      (fields (field (name "MPN") "ERJ-2RKF1002X"))
      (libsource (lib "eagle-import") (part "RESISTOR0402-RES"))
    )
    (comp (ref "R14-2")
      (value "10k")
      (footprint "eagle-import:0402-RES")
      (fields (field (name "MPN") "ERJ-2RKF1002X"))
      (libsource (lib "eagle-import") (part "RESISTOR0402-RES"))
    )
    (comp (ref "R18-2")
      (value "100k")
      (footprint "eagle-import:0402-RES")
      (fields (field (name "MPN") "ERJ-2RKF1003X"))
      (libsource (lib "eagle-import") (part "RESISTOR0402-RES"))
    )
    (comp (ref "R29-2")
      (value "10k")
      (footprint "eagle-import:0402")
      (fields
        (field (name "MANUFACTURER_PART_NUMBER") "CRCW04021K00FKED")
        (field (name "POWER") "0.063")
        (field (name "TOLERANCE") "1.0")
        (field (name "MPN") "ERJ-2RKF1002X")
        (field (name "TOLERANCE_1") "1%")
      )
      (libsource (lib "eagle-import") (part "CRCW04021K00FKED"))
    )
    (comp (ref "R33-2")
      (value "10k")
      (footprint "eagle-import:0402-RES")
      (fields (field (name "MPN") "ERJ-2RKF1002X"))
      (libsource (lib "eagle-import") (part "RESISTOR0402-RES"))
    )
    (comp (ref "R34-2")
      (value "NC")
      (footprint "eagle-import:0402")
      (fields
        (field (name "MANUFACTURER_PART_NUMBER") "CRCW04021K00FKED")
        (field (name "POWER") "0.063")
        (field (name "TOLERANCE") "1.0")
      )
      (libsource (lib "eagle-import") (part "CRCW04021K00FKED"))
    )
    (comp (ref "R37-2")
      (value "100k")
      (footprint "eagle-import:0402-RES")
      (fields (field (name "MPN") "ERJ-2RKF1003X"))
      (libsource (lib "eagle-import") (part "RESISTOR0402-RES"))
    )
    (comp (ref "R38-2")
      (value "0")
      (footprint "eagle-import:0402")
      (fields
        (field (name "MANUFACTURER_PART_NUMBER") "CRCW04021K00FKED")
        (field (name "POWER") "0.063")
        (field (name "TOLERANCE") "1.0")
      )
      (libsource (lib "eagle-import") (part "CRCW04021K00FKED"))
    )
    (comp (ref "R41-2")
      (value "100k")
      (footprint "eagle-import:0402-RES")
      (fields (field (name "MPN") "ERJ-2RKF1003X"))
      (libsource (lib "eagle-import") (part "RESISTOR0402-RES"))
    )
    (comp (ref "R54-2")
      (value "0")
      (footprint "eagle-import:0402")
      (fields
        (field (name "MANUFACTURER_PART_NUMBER") "CRCW04021K00FKED")
        (field (name "POWER") "0.063")
        (field (name "TOLERANCE") "1.0")
      )
      (libsource (lib "eagle-import") (part "CRCW04021K00FKED"))
    )
    (comp (ref "R55-2")
      (value "0")
      (footprint "eagle-import:0402-RES")
      (fields (field (name "MPN") "ERJ-2GE0R00X"))
      (libsource (lib "eagle-import") (part "RESISTOR0402-RES"))
    )
    (comp (ref "R56-2")
      (value "NC")
      (footprint "eagle-import:0402-RES")
      (libsource (lib "eagle-import") (part "RESISTOR0402-RES"))
    )
    (comp (ref "R59-2")
      (value "10k")
      (footprint "eagle-import:0402-RES")
      (fields (field (name "MPN") "ERJ-2RKF1002X"))
      (libsource (lib "eagle-import") (part "RESISTOR0402-RES"))
    )
    (comp (ref "R66X")
      (value "33")
      (footprint "eagle-import:0402-RES")
      (fields (field (name "MPN") "ERJ-2RKF33R0X"))
      (libsource (lib "eagle-import") (part "RESISTOR0402-RES"))
    )
    (comp (ref "R76X")
      (value "220")
      (footprint "eagle-import:0402-RES")
      (fields (field (name "MPN") "ERJ-2RKF2200X"))
      (libsource (lib "eagle-import") (part "RESISTOR0402-RES"))
    )
    (comp (ref "R83X")
      (value "0")
      (footprint "eagle-import:0402")
      (fields
        (field (name "MANUFACTURER_PART_NUMBER") "CRCW04021K00FKED")
        (field (name "POWER") "0.063")
        (field (name "TOLERANCE") "1.0")
      )
      (libsource (lib "eagle-import") (part "CRCW04021K00FKED"))
    )
    (comp (ref "R105X")
      (value "0")
      (footprint "eagle-import:0402-RES")
      (fields (field (name "MPN") "ERJ-2GE0R00X"))
      (libsource (lib "eagle-import") (part "RESISTOR0402-RES"))
    )
    (comp (ref "R117-2")
      (value "10k")
      (footprint "eagle-import:0402-RES")
      (fields (field (name "MPN") "ERJ-2RKF1002X"))
      (libsource (lib "eagle-import") (part "RESISTOR0402-RES"))
    )
    (comp (ref "TP4-2")
      (value "TPTP06R")
      (footprint "eagle-import:TP06R")
      (fields (field (name "TP_SIGNAL_NAME") "CLKOUT2"))
      (libsource (lib "eagle-import") (part "TPTP06R"))
    )
    (comp (ref "TP8X")
      (value "TPTP06R")
      (footprint "eagle-import:TP06R")
      (fields (field (name "TP_SIGNAL_NAME") "RTC_CLKOUT2"))
      (libsource (lib "eagle-import") (part "TPTP06R"))
    )
    (comp (ref "TP23X")
      (value "TPTP06R")
      (footprint "eagle-import:TP06R")
      (libsource (lib "eagle-import") (part "TPTP06R"))
    )
    (comp (ref "TP24X")
      (value "TPTP06R")
      (footprint "eagle-import:TP06R")
      (libsource (lib "eagle-import") (part "TPTP06R"))
    )
    (comp (ref "TP25X")
      (value "TPTP06R")
      (footprint "eagle-import:TP06R")
      (libsource (lib "eagle-import") (part "TPTP06R"))
    )
    (comp (ref "TP26X")
      (value "TPTP06R")
      (footprint "eagle-import:TP06R")
      (libsource (lib "eagle-import") (part "TPTP06R"))
    )
    (comp (ref "TP27X")
      (value "TPTP06R")
      (footprint "eagle-import:TP06R")
      (libsource (lib "eagle-import") (part "TPTP06R"))
    )
    (comp (ref "TP28X")
      (value "TPTP06R")
      (footprint "eagle-import:TP06R")
      (libsource (lib "eagle-import") (part "TPTP06R"))
    )
    (comp (ref "TP29X")
      (value "TPTP06R")
      (footprint "eagle-import:TP06R")
      (libsource (lib "eagle-import") (part "TPTP06R"))
    )
    (comp (ref "TP30X")
      (value "TPTP06R")
      (footprint "eagle-import:TP06R")
      (libsource (lib "eagle-import") (part "TPTP06R"))
    )
    (comp (ref "TP31X")
      (value "TPTP06R")
      (footprint "eagle-import:TP06R")
      (libsource (lib "eagle-import") (part "TPTP06R"))
    )
    (comp (ref "Y1-2")
      (value "32.768kHz")
      (footprint "eagle-import:CRYSTAL-32KHZ-SMD_EPSON_MC146")
      (fields (field (name "MPN") "SSPT7F-12.5PF20-R"))
      (libsource (lib "eagle-import") (part "CRYSTAL"))
    )
    (comp (ref "C168X")
      (value "100p")
      (footprint "eagle-import:C0402K")
      (fields (field (name "MPN") "GRM1555C1H101FA01J"))
      (libsource (lib "eagle-import") (part "C-EUC0402K"))
    )
    (comp (ref "H1")
      (value "MOUNT-PAD-ROUND3.0")
      (footprint "eagle-import:3,0-PAD")
      (libsource (lib "eagle-import") (part "MOUNT-PAD-ROUND3.0"))
    )
    (comp (ref "H2")
      (value "MOUNT-PAD-ROUND3.0")
      (footprint "eagle-import:3,0-PAD")
      (libsource (lib "eagle-import") (part "MOUNT-PAD-ROUND3.0"))
    )
    (comp (ref "H3")
      (value "MOUNT-PAD-ROUND3.0")
      (footprint "eagle-import:3,0-PAD")
      (libsource (lib "eagle-import") (part "MOUNT-PAD-ROUND3.0"))
    )
    (comp (ref "H4")
      (value "MOUNT-PAD-ROUND3.0")
      (footprint "eagle-import:3,0-PAD")
      (libsource (lib "eagle-import") (part "MOUNT-PAD-ROUND3.0"))
    )
    (comp (ref "J5")
      (value "87409-110LF")
      (footprint "eagle-import:87409-110LF")
      (libsource (lib "eagle-import") (part "87409-110LF"))
    )
    (comp (ref "J7")
      (value "87409-110LF")
      (footprint "eagle-import:87409-110LF")
      (libsource (lib "eagle-import") (part "87409-110LF"))
    )
    (comp (ref "JP2")
      (value "FOOTSW")
      (footprint "eagle-import:1X02")
      (libsource (lib "eagle-import") (part "PINHD-1X2"))
    )
    (comp (ref "JP3")
      (value "FIDUCIAL1X2.5")
      (footprint "eagle-import:FIDUCIAL-1X2.5")
      (libsource (lib "eagle-import") (part "FIDUCIAL1X2.5"))
    )
    (comp (ref "JP6")
      (value "FIDUCIAL1X2.5")
      (footprint "eagle-import:FIDUCIAL-1X2.5")
      (libsource (lib "eagle-import") (part "FIDUCIAL1X2.5"))
    )
    (comp (ref "JP7")
      (value "FIDUCIAL1X2.5")
      (footprint "eagle-import:FIDUCIAL-1X2.5")
      (libsource (lib "eagle-import") (part "FIDUCIAL1X2.5"))
    )
    (comp (ref "JP8")
      (value "FIDUCIAL1X2.5")
      (footprint "eagle-import:FIDUCIAL-1X2.5")
      (libsource (lib "eagle-import") (part "FIDUCIAL1X2.5"))
    )
    (comp (ref "LSP1")
      (value "LSP13")
      (footprint "eagle-import:LSP13")
      (libsource (lib "eagle-import") (part "LSP13"))
    )
    (comp (ref "LSP2")
      (value "LSP13")
      (footprint "eagle-import:LSP13")
      (libsource (lib "eagle-import") (part "LSP13"))
    )
    (comp (ref "R4X")
      (value "10k")
      (footprint "eagle-import:0402-RES")
      (fields (field (name "MPN") "ERJ-2RKF1002X"))
      (libsource (lib "eagle-import") (part "RESISTOR0402-RES"))
    )
    (comp (ref "SW1")
      (value "MB2011SB1W03-DA")
      (footprint "eagle-import:MB2011")
      (libsource (lib "eagle-import") (part "MB2011"))
    )
    (comp (ref "TP3")
      (value "TPTP12R")
      (footprint "eagle-import:TP12R")
      (fields (field (name "TP_SIGNAL_NAME") "A-DOWN"))
      (libsource (lib "eagle-import") (part "TPTP12R"))
    )
    (comp (ref "TP5")
      (value "TPTP12R")
      (footprint "eagle-import:TP12R")
      (fields (field (name "TP_SIGNAL_NAME") "A-CENTER"))
      (libsource (lib "eagle-import") (part "TPTP12R"))
    )
    (comp (ref "TP6")
      (value "TPTP12R")
      (footprint "eagle-import:TP12R")
      (fields (field (name "TP_SIGNAL_NAME") "A-UP"))
      (libsource (lib "eagle-import") (part "TPTP12R"))
    )
    (comp (ref "TP7")
      (value "TPTP12R")
      (footprint "eagle-import:TP12R")
      (fields (field (name "TP_SIGNAL_NAME") "A-LEFT"))
      (libsource (lib "eagle-import") (part "TPTP12R"))
    )
    (comp (ref "TP10")
      (value "TPTP12R")
      (footprint "eagle-import:TP12R")
      (fields (field (name "TP_SIGNAL_NAME") "A-RIGHT"))
      (libsource (lib "eagle-import") (part "TPTP12R"))
    )
  )
  (nets
    (net (code "1") (name "+9V") (class "Default")
      (node (ref "D1") (pin "A") (pinfunction "A_A") (pintype "passive"))
      (node (ref "SW2") (pin "1") (pinfunction "S_1") (pintype "passive"))
    )
    (net (code "2") (name "A-CENTER") (class "Default")
      (node (ref "J5") (pin "10") (pinfunction "10_10") (pintype "passive"))
      (node (ref "TP5") (pin "TP") (pinfunction "TP_TP") (pintype "input"))
    )
    (net (code "3") (name "A-DOWN") (class "Default")
      (node (ref "J5") (pin "6") (pinfunction "6_6") (pintype "passive"))
      (node (ref "TP3") (pin "TP") (pinfunction "TP_TP") (pintype "input"))
    )
    (net (code "4") (name "A-LEFT") (class "Default")
      (node (ref "J5") (pin "18") (pinfunction "18_18") (pintype "passive"))
      (node (ref "TP7") (pin "TP") (pinfunction "TP_TP") (pintype "input"))
    )
    (net (code "5") (name "A-RIGHT") (class "Default")
      (node (ref "J5") (pin "2") (pinfunction "2_2") (pintype "passive"))
      (node (ref "TP10") (pin "TP") (pinfunction "TP_TP") (pintype "input"))
    )
    (net (code "6") (name "A-UP") (class "Default")
      (node (ref "J5") (pin "14") (pinfunction "14_14") (pintype "passive"))
      (node (ref "TP6") (pin "TP") (pinfunction "TP_TP") (pintype "input"))
    )
    (net (code "7") (name "AGND") (class "Default")
      (node (ref "C2") (pin "2") (pinfunction "2_2") (pintype "passive"))
      (node (ref "C2-2") (pin "2") (pinfunction "2_2") (pintype "passive"))
      (node (ref "C3") (pin "2") (pinfunction "2_2") (pintype "passive"))
      (node (ref "C3-2") (pin "2") (pinfunction "2_2") (pintype "passive"))
      (node (ref "C43") (pin "2") (pinfunction "2_2") (pintype "passive"))
      (node (ref "C43-2") (pin "2") (pinfunction "2_2") (pintype "passive"))
      (node (ref "C49") (pin "2") (pinfunction "2_2") (pintype "passive"))
      (node (ref "C49-2") (pin "2") (pinfunction "2_2") (pintype "passive"))
      (node (ref "C50") (pin "2") (pinfunction "2_2") (pintype "passive"))
      (node (ref "C50-2") (pin "2") (pinfunction "2_2") (pintype "passive"))
      (node (ref "C57") (pin "2") (pinfunction "2_2") (pintype "passive"))
      (node (ref "C57-2") (pin "2") (pinfunction "2_2") (pintype "passive"))
      (node (ref "C73") (pin "2") (pinfunction "2_2") (pintype "passive"))
      (node (ref "C73-2") (pin "2") (pinfunction "2_2") (pintype "passive"))
      (node (ref "C85") (pin "2") (pinfunction "2_2") (pintype "passive"))
      (node (ref "C85-2") (pin "2") (pinfunction "2_2") (pintype "passive"))
      (node (ref "C86") (pin "2") (pinfunction "2_2") (pintype "passive"))
      (node (ref "C86-2") (pin "2") (pinfunction "2_2") (pintype "passive"))
      (node (ref "C88") (pin "2") (pinfunction "2_2") (pintype "passive"))
      (node (ref "C88-2") (pin "2") (pinfunction "2_2") (pintype "passive"))
      (node (ref "FB1") (pin "2") (pinfunction "2_2") (pintype "passive"))
      (node (ref "FB1-2") (pin "2") (pinfunction "2_2") (pintype "passive"))
      (node (ref "U4") (pin "A1") (pinfunction "VSSA_PLL_A1") (pintype "power_in"))
      (node (ref "U4") (pin "B6") (pinfunction "VSSA_ANA_B6") (pintype "power_in"))
      (node (ref "U4") (pin "C9") (pinfunction "VSSA_ANA_C9") (pintype "power_in"))
      (node (ref "U4") (pin "F13") (pinfunction "USB_VSSPLL_F13") (pintype "power_in"))
      (node (ref "U4") (pin "J12") (pinfunction "USB_VSSA1P3_J12") (pintype "power_in"))
      (node (ref "U5") (pin "A1") (pinfunction "VSSA_PLL_A1") (pintype "power_in"))
      (node (ref "U5") (pin "B6") (pinfunction "VSSA_ANA_B6") (pintype "power_in"))
      (node (ref "U5") (pin "C9") (pinfunction "VSSA_ANA_C9") (pintype "power_in"))
      (node (ref "U5") (pin "F13") (pinfunction "USB_VSSPLL_F13") (pintype "power_in"))
      (node (ref "U5") (pin "J12") (pinfunction "USB_VSSA1P3_J12") (pintype "power_in"))
    )
    (net (code "8") (name "AIC3204I2C_ENN") (class "Default")
      (node (ref "R136") (pin "2") (pinfunction "2_2") (pintype "passive"))
      (node (ref "U18") (pin "19") (pinfunction "~{OE}_19") (pintype "input"))
      (node (ref "U4") (pin "J2") (pinfunction "LCD_D[2]/GP[12]_J2") (pintype "tri_state"))
    )
    (net (code "9") (name "AIC_IISCLK") (class "Default")
      (node (ref "R92") (pin "1") (pinfunction "1_1") (pintype "passive"))
      (node (ref "U17") (pin "2") (pinfunction "BCLK_2") (pintype "bidirectional"))
    )
    (net (code "10") (name "AIC_IISD0") (class "Default")
      (node (ref "R94") (pin "1") (pinfunction "1_1") (pintype "passive"))
      (node (ref "U17") (pin "4") (pinfunction "DIN/MFP1_4") (pintype "input"))
    )
    (net (code "11") (name "AIC_IISD1") (class "Default")
      (node (ref "R95") (pin "1") (pinfunction "1_1") (pintype "passive"))
      (node (ref "U17") (pin "5") (pinfunction "DOUT/MFP2_5") (pintype "output"))
    )
    (net (code "12") (name "AIC_IISFS") (class "Default")
      (node (ref "R93") (pin "1") (pinfunction "1_1") (pintype "passive"))
      (node (ref "U17") (pin "3") (pinfunction "WCLK_3") (pintype "bidirectional"))
    )
    (net (code "13") (name "AIC_LINE2L") (class "Default")
      (node (ref "C17") (pin "1") (pinfunction "1_1") (pintype "passive"))
      (node (ref "R110") (pin "1") (pinfunction "1_1") (pintype "passive"))
      (node (ref "R175") (pin "2") (pinfunction "2_2") (pintype "passive"))
    )
    (net (code "14") (name "AIC_LINE2R") (class "Default")
      (node (ref "C16") (pin "1") (pinfunction "1_1") (pintype "passive"))
      (node (ref "R111") (pin "2") (pinfunction "2_2") (pintype "passive"))
      (node (ref "R197") (pin "2") (pinfunction "2_2") (pintype "passive"))
    )
    (net (code "15") (name "AIC_MCLK") (class "Default")
      (node (ref "R138") (pin "2") (pinfunction "2_2") (pintype "passive"))
      (node (ref "U17") (pin "1") (pinfunction "MCLK_(1)_1") (pintype "input"))
      (node (ref "U18") (pin "11") (pinfunction "B8_11") (pintype "bidirectional"))
    )
    (net (code "16") (name "AIC_MODE_SEL") (class "Default")
      (node (ref "R104") (pin "2") (pinfunction "2_2") (pintype "passive"))
      (node (ref "U17") (pin "12") (pinfunction "SPI_SELECT_12") (pintype "input"))
    )
    (net (code "17") (name "AIC_RST") (class "Default")
      (node (ref "R137") (pin "1") (pinfunction "1_1") (pintype "passive"))
      (node (ref "R141") (pin "1") (pinfunction "1_1") (pintype "passive"))
      (node (ref "R8") (pin "1") (pinfunction "1_1") (pintype "passive"))
      (node (ref "U17") (pin "31") (pinfunction "RESETN_31") (pintype "input"))
    )
    (net (code "18") (name "ANA_LDO_OUT") (class "Default")
      (node (ref "C73") (pin "1") (pinfunction "1_1") (pintype "passive"))
      (node (ref "C85") (pin "1") (pinfunction "1_1") (pintype "passive"))
      (node (ref "C86") (pin "1") (pinfunction "1_1") (pintype "passive"))
      (node (ref "U4") (pin "B7") (pinfunction "VDDA_ANA_B7") (pintype "power_in"))
      (node (ref "U4") (pin "B9") (pinfunction "ANA_LDOO_B9") (pintype "power_in"))
      (node (ref "U4") (pin "C7") (pinfunction "VDDA_PLL_C7") (pintype "power_in"))
    )
    (net (code "19") (name "ANA_LDO_OUT2") (class "Default")
      (node (ref "C73-2") (pin "1") (pinfunction "1_1") (pintype "passive"))
      (node (ref "C85-2") (pin "1") (pinfunction "1_1") (pintype "passive"))
      (node (ref "C86-2") (pin "1") (pinfunction "1_1") (pintype "passive"))
      (node (ref "J7") (pin "14") (pinfunction "14_14") (pintype "passive"))
      (node (ref "U5") (pin "B7") (pinfunction "VDDA_ANA_B7") (pintype "power_in"))
      (node (ref "U5") (pin "B9") (pinfunction "ANA_LDOO_B9") (pintype "power_in"))
      (node (ref "U5") (pin "C7") (pinfunction "VDDA_PLL_C7") (pintype "power_in"))
    )
    (net (code "20") (name "BAT+") (class "Default")
      (node (ref "J8") (pin "2") (pinfunction "2_2") (pintype "passive"))
      (node (ref "JP1") (pin "2") (pinfunction "2_2") (pintype "passive"))
    )
    (net (code "21") (name "BAT-") (class "Default")
      (node (ref "J3") (pin "R") (pinfunction "R_R") (pintype "passive"))
      (node (ref "J3") (pin "RN") (pinfunction "RN_RN") (pintype "passive"))
      (node (ref "J8") (pin "1") (pinfunction "1_1") (pintype "passive"))
      (node (ref "JP1") (pin "1") (pinfunction "1_1") (pintype "passive"))
    )
    (net (code "22") (name "C2-CENTER") (class "Default")
      (node (ref "J5") (pin "12") (pinfunction "12_12") (pintype "passive"))
      (node (ref "R83X") (pin "1") (pinfunction "1_1") (pintype "passive"))
      (node (ref "U5") (pin "N7") (pinfunction "LCD_D[5]/GP[15]_N7") (pintype "tri_state"))
    )
    (net (code "23") (name "C2-DOWN") (class "Default")
      (node (ref "J5") (pin "8") (pinfunction "8_8") (pintype "passive"))
      (node (ref "U5") (pin "P3") (pinfunction "LCD_D[6]/GP[16]_P3") (pintype "tri_state"))
    )
    (net (code "24") (name "C2-LEFT") (class "Default")
      (node (ref "J5") (pin "20") (pinfunction "20_20") (pintype "passive"))
      (node (ref "U5") (pin "N5") (pinfunction "LCD_D[3]/GP[13]_N5") (pintype "tri_state"))
    )
    (net (code "25") (name "C2-RIGHT") (class "Default")
      (node (ref "J5") (pin "4") (pinfunction "4_4") (pintype "passive"))
      (node (ref "U5") (pin "P8") (pinfunction "LCD_D[7]/GP[17]_P8") (pintype "tri_state"))
    )
    (net (code "26") (name "C2-UP") (class "Default")
      (node (ref "J5") (pin "16") (pinfunction "16_16") (pintype "passive"))
      (node (ref "U5") (pin "P2") (pinfunction "LCD_D[4]/GP[14]_P2") (pintype "tri_state"))
    )
    (net (code "27") (name "CLEAN") (class "Default")
      (node (ref "Q10") (pin "B") (pinfunction "B_B") (pintype "passive"))
      (node (ref "U5") (pin "M8") (pinfunction "SD0_CLK/I2S0_CLK/GP[0]_M8") (pintype "bidirectional"))
    )
    (net (code "28") (name "CLEAN_C") (class "Default")
      (node (ref "C188") (pin "1") (pinfunction "1_1") (pintype "passive"))
      (node (ref "C207") (pin "1") (pinfunction "1_1") (pintype "passive"))
      (node (ref "R172") (pin "2") (pinfunction "2_2") (pintype "passive"))
      (node (ref "U20") (pin "7") (pinfunction "OUT_7") (pintype "output"))
    )
    (net (code "29") (name "CLEAN_S") (class "Default")
      (node (ref "C188") (pin "2") (pinfunction "2_2") (pintype "passive"))
      (node (ref "R199") (pin "1") (pinfunction "1_1") (pintype "passive"))
      (node (ref "U13") (pin "3") (pinfunction "A_3") (pintype "bidirectional"))
    )
    (net (code "30") (name "CLK12MHZ") (class "Default")
      (node (ref "U14") (pin "3") (pinfunction "OUT_3") (pintype "output"))
      (node (ref "U15X") (pin "1") (pinfunction "CLKIN_1") (pintype "input"))
    )
    (net (code "31") (name "CLKOUT2") (class "Default")
      (node (ref "R117-2") (pin "2") (pinfunction "2_2") (pintype "passive"))
      (node (ref "TP4-2") (pin "TP") (pinfunction "TP_TP") (pintype "input"))
      (node (ref "U5") (pin "A2") (pinfunction "CLKOUT_A2") (pintype "output"))
    )
    (net (code "32") (name "CLK_12MHZ") (class "Default")
      (node (ref "R227X") (pin "2") (pinfunction "2_2") (pintype "passive"))
      (node (ref "R23") (pin "1") (pinfunction "1_1") (pintype "passive"))
    )
    (net (code "33") (name "CLK_SEL") (class "Default")
      (node (ref "R33") (pin "2") (pinfunction "2_2") (pintype "passive"))
      (node (ref "U4") (pin "D1") (pinfunction "CLK_SEL_D1") (pintype "input"))
    )
    (net (code "34") (name "CLK_SEL2") (class "Default")
      (node (ref "R33-2") (pin "2") (pinfunction "2_2") (pintype "passive"))
      (node (ref "U5") (pin "D1") (pinfunction "CLK_SEL_D1") (pintype "input"))
    )
    (net (code "35") (name "CODEC_AVDD") (class "Default")
      (node (ref "C116") (pin "1") (pinfunction "1_1") (pintype "passive"))
      (node (ref "C19") (pin "1") (pinfunction "1_1") (pintype "passive"))
      (node (ref "R107") (pin "1") (pinfunction "1_1") (pintype "passive"))
      (node (ref "U17") (pin "24") (pinfunction "AVDD_24") (pintype "power_in"))
    )
    (net (code "36") (name "CODEC_DVDD") (class "Default")
      (node (ref "C108") (pin "1") (pinfunction "1_1") (pintype "passive"))
      (node (ref "C11") (pin "1") (pinfunction "1_1") (pintype "passive"))
      (node (ref "R106") (pin "2") (pinfunction "2_2") (pintype "passive"))
      (node (ref "U17") (pin "29") (pinfunction "DVDD_29") (pintype "power_in"))
    )
    (net (code "37") (name "CODEC_IOVDD") (class "Default")
      (node (ref "C105") (pin "1") (pinfunction "1_1") (pintype "passive"))
      (node (ref "C8") (pin "1") (pinfunction "1_1") (pintype "passive"))
      (node (ref "R5") (pin "2") (pinfunction "2_2") (pintype "passive"))
      (node (ref "U17") (pin "6") (pinfunction "IOVDD_6") (pintype "power_in"))
    )
    (net (code "38") (name "CODEC_LDOIN") (class "Default")
      (node (ref "C111") (pin "1") (pinfunction "1_1") (pintype "passive"))
      (node (ref "C12") (pin "1") (pinfunction "1_1") (pintype "passive"))
      (node (ref "R108") (pin "1") (pinfunction "1_1") (pintype "passive"))
      (node (ref "U17") (pin "26") (pinfunction "LDOIN_26") (pintype "power_in"))
    )
    (net (code "39") (name "CONN_HP_LOUT") (class "Default")
      (node (ref "C14") (pin "-") (pinfunction "-_-") (pintype "passive"))
      (node (ref "J4") (pin "2") (pinfunction "T_2") (pintype "passive"))
    )
    (net (code "40") (name "CONN_HP_ROUT") (class "Default")
      (node (ref "C13") (pin "-") (pinfunction "-_-") (pintype "passive"))
      (node (ref "J4") (pin "3") (pinfunction "R_3") (pintype "passive"))
    )
    (net (code "41") (name "CPU1_LED") (class "Default")
      (node (ref "DS2") (pin "A") (pinfunction "A_A") (pintype "passive"))
      (node (ref "U4") (pin "P8") (pinfunction "LCD_D[7]/GP[17]_P8") (pintype "tri_state"))
    )
    (net (code "42") (name "CPU2_CLK_12MHZ") (class "Default")
      (node (ref "R226X") (pin "2") (pinfunction "2_2") (pintype "passive"))
      (node (ref "R38-2") (pin "1") (pinfunction "1_1") (pintype "passive"))
    )
    (net (code "43") (name "CPU2_LED") (class "Default")
      (node (ref "D3X") (pin "A") (pinfunction "A_A") (pintype "passive"))
      (node (ref "U5") (pin "M12") (pinfunction "SD1_D3/GP[11]_M12") (pintype "bidirectional"))
    )
    (net (code "44") (name "CPU_CLK_12MHZ") (class "Default")
      (node (ref "R229X") (pin "2") (pinfunction "2_2") (pintype "passive"))
      (node (ref "R38") (pin "1") (pinfunction "1_1") (pintype "passive"))
    )
    (net (code "45") (name "DCIN") (class "Default")
      (node (ref "CF1") (pin "1") (pinfunction "1_1") (pintype "passive"))
      (node (ref "J8") (pin "3") (pinfunction "3_3") (pintype "passive"))
    )
    (net (code "46") (name "DGND") (class "Default")
      (node (ref "C1") (pin "2") (pinfunction "2_2") (pintype "passive"))
      (node (ref "C1-2") (pin "2") (pinfunction "2_2") (pintype "passive"))
      (node (ref "C10") (pin "2") (pinfunction "2_2") (pintype "passive"))
      (node (ref "C104") (pin "2") (pinfunction "2_2") (pintype "passive"))
      (node (ref "C105") (pin "2") (pinfunction "2_2") (pintype "passive"))
      (node (ref "C108") (pin "2") (pinfunction "2_2") (pintype "passive"))
      (node (ref "C11") (pin "2") (pinfunction "2_2") (pintype "passive"))
      (node (ref "C122") (pin "2") (pinfunction "2_2") (pintype "passive"))
      (node (ref "C15") (pin "2") (pinfunction "2_2") (pintype "passive"))
      (node (ref "C168X") (pin "2") (pinfunction "2_2") (pintype "passive"))
      (node (ref "C169X") (pin "2") (pinfunction "2_2") (pintype "passive"))
      (node (ref "C185") (pin "2") (pinfunction "2_2") (pintype "passive"))
      (node (ref "C20") (pin "2") (pinfunction "2_2") (pintype "passive"))
      (node (ref "C204") (pin "2") (pinfunction "2_2") (pintype "passive"))
      (node (ref "C205") (pin "2") (pinfunction "2_2") (pintype "passive"))
      (node (ref "C209") (pin "2") (pinfunction "2_2") (pintype "passive"))
      (node (ref "C21") (pin "2") (pinfunction "2_2") (pintype "passive"))
      (node (ref "C210") (pin "2") (pinfunction "2_2") (pintype "passive"))
      (node (ref "C212") (pin "2") (pinfunction "2_2") (pintype "passive"))
      (node (ref "C213X") (pin "2") (pinfunction "2_2") (pintype "passive"))
      (node (ref "C214") (pin "2") (pinfunction "2_2") (pintype "passive"))
      (node (ref "C215X") (pin "2") (pinfunction "2_2") (pintype "passive"))
      (node (ref "C216X") (pin "2") (pinfunction "2_2") (pintype "passive"))
      (node (ref "C217X") (pin "2") (pinfunction "2_2") (pintype "passive"))
      (node (ref "C218X") (pin "2") (pinfunction "2_2") (pintype "passive"))
      (node (ref "C21X") (pin "2") (pinfunction "2_2") (pintype "passive"))
      (node (ref "C220") (pin "2") (pinfunction "2_2") (pintype "passive"))
      (node (ref "C221") (pin "2") (pinfunction "2_2") (pintype "passive"))
      (node (ref "C222") (pin "2") (pinfunction "2_2") (pintype "passive"))
      (node (ref "C23X") (pin "2") (pinfunction "2_2") (pintype "passive"))
      (node (ref "C24") (pin "2") (pinfunction "2_2") (pintype "passive"))
      (node (ref "C24-2") (pin "2") (pinfunction "2_2") (pintype "passive"))
      (node (ref "C25") (pin "2") (pinfunction "2_2") (pintype "passive"))
      (node (ref "C25-2") (pin "2") (pinfunction "2_2") (pintype "passive"))
      (node (ref "C26X") (pin "2") (pinfunction "2_2") (pintype "passive"))
      (node (ref "C28") (pin "2") (pinfunction "2_2") (pintype "passive"))
      (node (ref "C28-2") (pin "2") (pinfunction "2_2") (pintype "passive"))
      (node (ref "C29") (pin "2") (pinfunction "2_2") (pintype "passive"))
      (node (ref "C29-2") (pin "2") (pinfunction "2_2") (pintype "passive"))
      (node (ref "C30") (pin "2") (pinfunction "2_2") (pintype "passive"))
      (node (ref "C30-2") (pin "2") (pinfunction "2_2") (pintype "passive"))
      (node (ref "C32") (pin "2") (pinfunction "2_2") (pintype "passive"))
      (node (ref "C32-2") (pin "2") (pinfunction "2_2") (pintype "passive"))
      (node (ref "C33") (pin "2") (pinfunction "2_2") (pintype "passive"))
      (node (ref "C34") (pin "1") (pinfunction "1_1") (pintype "passive"))
      (node (ref "C35") (pin "2") (pinfunction "2_2") (pintype "passive"))
      (node (ref "C36") (pin "2") (pinfunction "2_2") (pintype "passive"))
      (node (ref "C37") (pin "1") (pinfunction "1_1") (pintype "passive"))
      (node (ref "C38") (pin "2") (pinfunction "2_2") (pintype "passive"))
      (node (ref "C38-2") (pin "2") (pinfunction "2_2") (pintype "passive"))
      (node (ref "C4") (pin "2") (pinfunction "2_2") (pintype "passive"))
      (node (ref "C4-2") (pin "2") (pinfunction "2_2") (pintype "passive"))
      (node (ref "C40") (pin "2") (pinfunction "2_2") (pintype "passive"))
      (node (ref "C40-2") (pin "2") (pinfunction "2_2") (pintype "passive"))
      (node (ref "C41") (pin "2") (pinfunction "2_2") (pintype "passive"))
      (node (ref "C41-2") (pin "2") (pinfunction "2_2") (pintype "passive"))
      (node (ref "C42") (pin "2") (pinfunction "2_2") (pintype "passive"))
      (node (ref "C42-2") (pin "2") (pinfunction "2_2") (pintype "passive"))
      (node (ref "C44") (pin "1") (pinfunction "1_1") (pintype "passive"))
      (node (ref "C45") (pin "2") (pinfunction "2_2") (pintype "passive"))
      (node (ref "C45-2") (pin "2") (pinfunction "2_2") (pintype "passive"))
      (node (ref "C46") (pin "2") (pinfunction "2_2") (pintype "passive"))
      (node (ref "C46-2") (pin "2") (pinfunction "2_2") (pintype "passive"))
      (node (ref "C47") (pin "1") (pinfunction "1_1") (pintype "passive"))
      (node (ref "C48") (pin "2") (pinfunction "2_2") (pintype "passive"))
      (node (ref "C48-2") (pin "2") (pinfunction "2_2") (pintype "passive"))
      (node (ref "C5") (pin "2") (pinfunction "2_2") (pintype "passive"))
      (node (ref "C5-2") (pin "2") (pinfunction "2_2") (pintype "passive"))
      (node (ref "C51") (pin "2") (pinfunction "2_2") (pintype "passive"))
      (node (ref "C51-2") (pin "2") (pinfunction "2_2") (pintype "passive"))
      (node (ref "C52") (pin "2") (pinfunction "2_2") (pintype "passive"))
      (node (ref "C52-2") (pin "2") (pinfunction "2_2") (pintype "passive"))
      (node (ref "C53") (pin "2") (pinfunction "2_2") (pintype "passive"))
      (node (ref "C53-2") (pin "2") (pinfunction "2_2") (pintype "passive"))
      (node (ref "C54") (pin "2") (pinfunction "2_2") (pintype "passive"))
      (node (ref "C54-2") (pin "2") (pinfunction "2_2") (pintype "passive"))
      (node (ref "C55") (pin "2") (pinfunction "2_2") (pintype "passive"))
      (node (ref "C55-2") (pin "2") (pinfunction "2_2") (pintype "passive"))
      (node (ref "C56") (pin "2") (pinfunction "2_2") (pintype "passive"))
      (node (ref "C56-2") (pin "2") (pinfunction "2_2") (pintype "passive"))
      (node (ref "C58") (pin "2") (pinfunction "2_2") (pintype "passive"))
      (node (ref "C59") (pin "2") (pinfunction "2_2") (pintype "passive"))
      (node (ref "C59-2") (pin "2") (pinfunction "2_2") (pintype "passive"))
      (node (ref "C6") (pin "2") (pinfunction "2_2") (pintype "passive"))
      (node (ref "C6-2") (pin "2") (pinfunction "2_2") (pintype "passive"))
      (node (ref "C60") (pin "2") (pinfunction "2_2") (pintype "passive"))
      (node (ref "C60-2") (pin "2") (pinfunction "2_2") (pintype "passive"))
      (node (ref "C61") (pin "1") (pinfunction "1_1") (pintype "passive"))
      (node (ref "C62") (pin "2") (pinfunction "2_2") (pintype "passive"))
      (node (ref "C62-2") (pin "2") (pinfunction "2_2") (pintype "passive"))
      (node (ref "C63") (pin "2") (pinfunction "2_2") (pintype "passive"))
      (node (ref "C63-2") (pin "2") (pinfunction "2_2") (pintype "passive"))
      (node (ref "C64") (pin "2") (pinfunction "2_2") (pintype "passive"))
      (node (ref "C64-2") (pin "2") (pinfunction "2_2") (pintype "passive"))
      (node (ref "C65") (pin "2") (pinfunction "2_2") (pintype "passive"))
      (node (ref "C65-2") (pin "2") (pinfunction "2_2") (pintype "passive"))
      (node (ref "C66") (pin "2") (pinfunction "2_2") (pintype "passive"))
      (node (ref "C66-2") (pin "2") (pinfunction "2_2") (pintype "passive"))
      (node (ref "C67") (pin "2") (pinfunction "2_2") (pintype "passive"))
      (node (ref "C67-2") (pin "2") (pinfunction "2_2") (pintype "passive"))
      (node (ref "C68") (pin "2") (pinfunction "2_2") (pintype "passive"))
      (node (ref "C69") (pin "2") (pinfunction "2_2") (pintype "passive"))
      (node (ref "C69-2") (pin "2") (pinfunction "2_2") (pintype "passive"))
      (node (ref "C7") (pin "2") (pinfunction "2_2") (pintype "passive"))
      (node (ref "C70") (pin "2") (pinfunction "2_2") (pintype "passive"))
      (node (ref "C71") (pin "2") (pinfunction "2_2") (pintype "passive"))
      (node (ref "C71-2") (pin "2") (pinfunction "2_2") (pintype "passive"))
      (node (ref "C72") (pin "2") (pinfunction "2_2") (pintype "passive"))
      (node (ref "C72-2") (pin "2") (pinfunction "2_2") (pintype "passive"))
      (node (ref "C74") (pin "2") (pinfunction "2_2") (pintype "passive"))
      (node (ref "C74-2") (pin "2") (pinfunction "2_2") (pintype "passive"))
      (node (ref "C75") (pin "2") (pinfunction "2_2") (pintype "passive"))
      (node (ref "C75-2") (pin "2") (pinfunction "2_2") (pintype "passive"))
      (node (ref "C76") (pin "1") (pinfunction "1_1") (pintype "passive"))
      (node (ref "C77") (pin "2") (pinfunction "2_2") (pintype "passive"))
      (node (ref "C77-2") (pin "2") (pinfunction "2_2") (pintype "passive"))
      (node (ref "C78") (pin "2") (pinfunction "2_2") (pintype "passive"))
      (node (ref "C79") (pin "2") (pinfunction "2_2") (pintype "passive"))
      (node (ref "C8") (pin "2") (pinfunction "2_2") (pintype "passive"))
      (node (ref "C80") (pin "2") (pinfunction "2_2") (pintype "passive"))
      (node (ref "C81") (pin "2") (pinfunction "2_2") (pintype "passive"))
      (node (ref "C81-2") (pin "2") (pinfunction "2_2") (pintype "passive"))
      (node (ref "C82") (pin "2") (pinfunction "2_2") (pintype "passive"))
      (node (ref "C82-2") (pin "2") (pinfunction "2_2") (pintype "passive"))
      (node (ref "C83") (pin "2") (pinfunction "2_2") (pintype "passive"))
      (node (ref "C83-2") (pin "2") (pinfunction "2_2") (pintype "passive"))
      (node (ref "C84") (pin "2") (pinfunction "2_2") (pintype "passive"))
      (node (ref "C84-2") (pin "2") (pinfunction "2_2") (pintype "passive"))
      (node (ref "C87") (pin "2") (pinfunction "2_2") (pintype "passive"))
      (node (ref "C87-2") (pin "2") (pinfunction "2_2") (pintype "passive"))
      (node (ref "C89") (pin "2") (pinfunction "2_2") (pintype "passive"))
      (node (ref "C89-2") (pin "2") (pinfunction "2_2") (pintype "passive"))
      (node (ref "C9") (pin "2") (pinfunction "2_2") (pintype "passive"))
      (node (ref "C92") (pin "2") (pinfunction "2_2") (pintype "passive"))
      (node (ref "C93") (pin "2") (pinfunction "2_2") (pintype "passive"))
      (node (ref "C94X") (pin "2") (pinfunction "2_2") (pintype "passive"))
      (node (ref "C98X") (pin "2") (pinfunction "2_2") (pintype "passive"))
      (node (ref "C99X") (pin "2") (pinfunction "2_2") (pintype "passive"))
      (node (ref "D2") (pin "A") (pinfunction "A_A") (pintype "passive"))
      (node (ref "D2-2") (pin "A") (pinfunction "A_A") (pintype "passive"))
      (node (ref "FB1") (pin "1") (pinfunction "1_1") (pintype "passive"))
      (node (ref "FB1-2") (pin "1") (pinfunction "1_1") (pintype "passive"))
      (node (ref "FB2") (pin "1") (pinfunction "1_1") (pintype "passive"))
      (node (ref "H1") (pin "B3,0") (pinfunction "MOUNT_B3,0") (pintype "passive"))
      (node (ref "H2") (pin "B3,0") (pinfunction "MOUNT_B3,0") (pintype "passive"))
      (node (ref "H3") (pin "B3,0") (pinfunction "MOUNT_B3,0") (pintype "passive"))
      (node (ref "H4") (pin "B3,0") (pinfunction "MOUNT_B3,0") (pintype "passive"))
      (node (ref "IC2") (pin "7") (pinfunction "VSS_7") (pintype "power_in"))
      (node (ref "J1") (pin "GND") (pinfunction "GND_GND") (pintype "bidirectional"))
      (node (ref "J1") (pin "MTN1") (pinfunction "MTN2_MTN1") (pintype "bidirectional"))
      (node (ref "J1") (pin "MTN2") (pinfunction "MTN3_MTN2") (pintype "bidirectional"))
      (node (ref "J1") (pin "MTN3") (pinfunction "MTN1_MTN3") (pintype "bidirectional"))
      (node (ref "J1") (pin "MTN4") (pinfunction "MTN4_MTN4") (pintype "bidirectional"))
      (node (ref "J1-2") (pin "GND") (pinfunction "GND_GND") (pintype "bidirectional"))
      (node (ref "J1-2") (pin "MTN1") (pinfunction "MTN2_MTN1") (pintype "bidirectional"))
      (node (ref "J1-2") (pin "MTN2") (pinfunction "MTN3_MTN2") (pintype "bidirectional"))
      (node (ref "J1-2") (pin "MTN3") (pinfunction "MTN1_MTN3") (pintype "bidirectional"))
      (node (ref "J1-2") (pin "MTN4") (pinfunction "MTN4_MTN4") (pintype "bidirectional"))
      (node (ref "J11") (pin "11") (pinfunction "INSERT_COM_11") (pintype "passive"))
      (node (ref "J11") (pin "6") (pinfunction "VSS_6") (pintype "power_in"))
      (node (ref "J2") (pin "GND") (pinfunction "GND_GND") (pintype "bidirectional"))
      (node (ref "J5") (pin "19") (pinfunction "19_19") (pintype "passive"))
      (node (ref "J5") (pin "3") (pinfunction "3_3") (pintype "passive"))
      (node (ref "J5") (pin "7") (pinfunction "7_7") (pintype "passive"))
      (node (ref "J6") (pin "11") (pinfunction "INSERT_COM_11") (pintype "passive"))
      (node (ref "J6") (pin "6") (pinfunction "VSS_6") (pintype "power_in"))
      (node (ref "J7") (pin "16") (pinfunction "16_16") (pintype "passive"))
      (node (ref "J7") (pin "18") (pinfunction "18_18") (pintype "passive"))
      (node (ref "J7") (pin "19") (pinfunction "19_19") (pintype "passive"))
      (node (ref "J7") (pin "20") (pinfunction "20_20") (pintype "passive"))
      (node (ref "JP2") (pin "1") (pinfunction "1_1") (pintype "passive"))
      (node (ref "LSP1") (pin "MP") (pinfunction "MP_MP") (pintype "passive"))
      (node (ref "LSP2") (pin "MP") (pinfunction "MP_MP") (pintype "passive"))
      (node (ref "Q10") (pin "E") (pinfunction "E_E") (pintype "passive"))
      (node (ref "Q2") (pin "E") (pinfunction "E_E") (pintype "passive"))
      (node (ref "Q4") (pin "E") (pinfunction "E_E") (pintype "passive"))
      (node (ref "Q8") (pin "E") (pinfunction "E_E") (pintype "passive"))
      (node (ref "Q9") (pin "E") (pinfunction "E_E") (pintype "passive"))
      (node (ref "R104") (pin "1") (pinfunction "1_1") (pintype "passive"))
      (node (ref "R117") (pin "1") (pinfunction "1_1") (pintype "passive"))
      (node (ref "R117-2") (pin "1") (pinfunction "1_1") (pintype "passive"))
      (node (ref "R126X") (pin "1") (pinfunction "1_1") (pintype "passive"))
      (node (ref "R136") (pin "1") (pinfunction "1_1") (pintype "passive"))
      (node (ref "R137") (pin "2") (pinfunction "2_2") (pintype "passive"))
      (node (ref "R138") (pin "1") (pinfunction "1_1") (pintype "passive"))
      (node (ref "R15X") (pin "1") (pinfunction "1_1") (pintype "passive"))
      (node (ref "R17") (pin "1") (pinfunction "1_1") (pintype "passive"))
      (node (ref "R18") (pin "1") (pinfunction "1_1") (pintype "passive"))
      (node (ref "R18-2") (pin "1") (pinfunction "1_1") (pintype "passive"))
      (node (ref "R209") (pin "1") (pinfunction "1_1") (pintype "passive"))
      (node (ref "R212") (pin "1") (pinfunction "1_1") (pintype "passive"))
      (node (ref "R215") (pin "1") (pinfunction "1_1") (pintype "passive"))
      (node (ref "R216") (pin "1") (pinfunction "1_1") (pintype "passive"))
      (node (ref "R28") (pin "1") (pinfunction "1_1") (pintype "passive"))
      (node (ref "R33") (pin "1") (pinfunction "1_1") (pintype "passive"))
      (node (ref "R33-2") (pin "1") (pinfunction "1_1") (pintype "passive"))
      (node (ref "R34") (pin "1") (pinfunction "1_1") (pintype "passive"))
      (node (ref "R34-2") (pin "1") (pinfunction "1_1") (pintype "passive"))
      (node (ref "R43") (pin "2") (pinfunction "2_2") (pintype "passive"))
      (node (ref "R54") (pin "1") (pinfunction "1_1") (pintype "passive"))
      (node (ref "R54-2") (pin "1") (pinfunction "1_1") (pintype "passive"))
      (node (ref "R56") (pin "1") (pinfunction "1_1") (pintype "passive"))
      (node (ref "R56-2") (pin "1") (pinfunction "1_1") (pintype "passive"))
      (node (ref "R57") (pin "2") (pinfunction "2_2") (pintype "passive"))
      (node (ref "R59") (pin "1") (pinfunction "1_1") (pintype "passive"))
      (node (ref "R59-2") (pin "1") (pinfunction "1_1") (pintype "passive"))
      (node (ref "R60") (pin "1") (pinfunction "1_1") (pintype "passive"))
      (node (ref "R60-2") (pin "1") (pinfunction "1_1") (pintype "passive"))
      (node (ref "R61") (pin "1") (pinfunction "1_1") (pintype "passive"))
      (node (ref "R61-2") (pin "1") (pinfunction "1_1") (pintype "passive"))
      (node (ref "R62") (pin "1") (pinfunction "1_1") (pintype "passive"))
      (node (ref "R62-2") (pin "1") (pinfunction "1_1") (pintype "passive"))
      (node (ref "R64") (pin "1") (pinfunction "1_1") (pintype "passive"))
      (node (ref "R64-2") (pin "1") (pinfunction "1_1") (pintype "passive"))
      (node (ref "R70X") (pin "1") (pinfunction "1_1") (pintype "passive"))
      (node (ref "R76X") (pin "1") (pinfunction "1_1") (pintype "passive"))
      (node (ref "R9") (pin "1") (pinfunction "1_1") (pintype "passive"))
      (node (ref "SW1") (pin "3") (pinfunction "S_3") (pintype "passive"))
      (node (ref "TP2") (pin "TP") (pinfunction "TP_TP") (pintype "input"))
      (node (ref "U10X") (pin "1") (pinfunction "A0_1") (pintype "input"))
      (node (ref "U10X") (pin "2") (pinfunction "A1_2") (pintype "input"))
      (node (ref "U10X") (pin "3") (pinfunction "A2_3") (pintype "input"))
      (node (ref "U10X") (pin "4") (pinfunction "GND_4") (pintype "power_in"))
      (node (ref "U11X") (pin "2") (pinfunction "GND_2") (pintype "passive"))
      (node (ref "U12X") (pin "1") (pinfunction "GND_1") (pintype "power_in"))
      (node (ref "U13") (pin "2") (pinfunction "GND_2") (pintype "power_in"))
      (node (ref "U14") (pin "2") (pinfunction "GND_2") (pintype "power_in"))
      (node (ref "U15X") (pin "12") (pinfunction "GND_3_12") (pintype "passive"))
      (node (ref "U15X") (pin "4") (pinfunction "GND_2_4") (pintype "passive"))
      (node (ref "U15X") (pin "7") (pinfunction "GND_7") (pintype "passive"))
      (node (ref "U17") (pin "28") (pinfunction "DVSS_28") (pintype "power_in"))
      (node (ref "U17") (pin "7") (pinfunction "IOVSS_7") (pintype "power_in"))
      (node (ref "U18") (pin "10") (pinfunction "GND_10") (pintype "passive"))
      (node (ref "U1X") (pin "1") (pinfunction "GND_1") (pintype "power_in"))
      (node (ref "U2") (pin "5") (pinfunction "GND_5") (pintype "power_in"))
      (node (ref "U24") (pin "4") (pinfunction "GND_4") (pintype "power_in"))
      (node (ref "U3X") (pin "2") (pinfunction "GND_2") (pintype "passive"))
      (node (ref "U4") (pin "A11") (pinfunction "RSV4_A11") (pintype "input"))
      (node (ref "U4") (pin "A14") (pinfunction "VSS_A14") (pintype "power_in"))
      (node (ref "U4") (pin "B11") (pinfunction "RSV5_B11") (pintype "input"))
      (node (ref "U4") (pin "B2") (pinfunction "VSS_B2") (pintype "power_in"))
      (node (ref "U4") (pin "B3") (pinfunction "VSS_B3") (pintype "power_in"))
      (node (ref "U4") (pin "C12") (pinfunction "VSS_C12") (pintype "power_in"))
      (node (ref "U4") (pin "C8") (pinfunction "VSS_C8") (pintype "power_in"))
      (node (ref "U4") (pin "D10") (pinfunction "VSS_D10") (pintype "power_in"))
      (node (ref "U4") (pin "D4") (pinfunction "VSS_D4") (pintype "power_in"))
      (node (ref "U4") (pin "D5") (pinfunction "VSS_D5") (pintype "power_in"))
      (node (ref "U4") (pin "E11") (pinfunction "VSS_E11") (pintype "power_in"))
      (node (ref "U4") (pin "E3") (pinfunction "VSS_E3") (pintype "power_in"))
      (node (ref "U4") (pin "E4") (pinfunction "VSS_E4") (pintype "power_in"))
      (node (ref "U4") (pin "F3") (pinfunction "VSS_F3") (pintype "power_in"))
      (node (ref "U4") (pin "H13") (pinfunction "USB_VSSA3P3_H13") (pintype "power_in"))
      (node (ref "U4") (pin "H3") (pinfunction "VSS_H3") (pintype "power_in"))
      (node (ref "U4") (pin "J13") (pinfunction "VSS_J13") (pintype "power_in"))
      (node (ref "U4") (pin "K14") (pinfunction "USB_VSS1P3_K14") (pintype "power_in"))
      (node (ref "U4") (pin "K3") (pinfunction "VSS_K3") (pintype "power_in"))
      (node (ref "U4") (pin "K4") (pinfunction "VSS_K4") (pintype "power_in"))
      (node (ref "U4") (pin "L10") (pinfunction "VSS_L10") (pintype "power_in"))
      (node (ref "U4") (pin "L5") (pinfunction "VSS_L5") (pintype "power_in"))
      (node (ref "U4") (pin "M7") (pinfunction "VSS_M7") (pintype "power_in"))
      (node (ref "U4") (pin "P1") (pinfunction "VSS_P1") (pintype "power_in"))
      (node (ref "U4") (pin "P14") (pinfunction "VSS_P14") (pintype "power_in"))
      (node (ref "U5") (pin "A11") (pinfunction "RSV4_A11") (pintype "input"))
      (node (ref "U5") (pin "A14") (pinfunction "VSS_A14") (pintype "power_in"))
      (node (ref "U5") (pin "B11") (pinfunction "RSV5_B11") (pintype "input"))
      (node (ref "U5") (pin "B2") (pinfunction "VSS_B2") (pintype "power_in"))
      (node (ref "U5") (pin "B3") (pinfunction "VSS_B3") (pintype "power_in"))
      (node (ref "U5") (pin "C12") (pinfunction "VSS_C12") (pintype "power_in"))
      (node (ref "U5") (pin "C8") (pinfunction "VSS_C8") (pintype "power_in"))
      (node (ref "U5") (pin "D10") (pinfunction "VSS_D10") (pintype "power_in"))
      (node (ref "U5") (pin "D4") (pinfunction "VSS_D4") (pintype "power_in"))
      (node (ref "U5") (pin "D5") (pinfunction "VSS_D5") (pintype "power_in"))
      (node (ref "U5") (pin "E11") (pinfunction "VSS_E11") (pintype "power_in"))
      (node (ref "U5") (pin "E3") (pinfunction "VSS_E3") (pintype "power_in"))
      (node (ref "U5") (pin "E4") (pinfunction "VSS_E4") (pintype "power_in"))
      (node (ref "U5") (pin "F3") (pinfunction "VSS_F3") (pintype "power_in"))
      (node (ref "U5") (pin "H13") (pinfunction "USB_VSSA3P3_H13") (pintype "power_in"))
      (node (ref "U5") (pin "H3") (pinfunction "VSS_H3") (pintype "power_in"))
      (node (ref "U5") (pin "J13") (pinfunction "VSS_J13") (pintype "power_in"))
      (node (ref "U5") (pin "K14") (pinfunction "USB_VSS1P3_K14") (pintype "power_in"))
      (node (ref "U5") (pin "K3") (pinfunction "VSS_K3") (pintype "power_in"))
      (node (ref "U5") (pin "K4") (pinfunction "VSS_K4") (pintype "power_in"))
      (node (ref "U5") (pin "L10") (pinfunction "VSS_L10") (pintype "power_in"))
      (node (ref "U5") (pin "L5") (pinfunction "VSS_L5") (pintype "power_in"))
      (node (ref "U5") (pin "M7") (pinfunction "VSS_M7") (pintype "power_in"))
      (node (ref "U5") (pin "P1") (pinfunction "VSS_P1") (pintype "power_in"))
      (node (ref "U5") (pin "P14") (pinfunction "VSS_P14") (pintype "power_in"))
      (node (ref "U6") (pin "1") (pinfunction "GND_1") (pintype "power_in"))
      (node (ref "U6") (pin "10") (pinfunction "AGND_10") (pintype "power_in"))
      (node (ref "U6") (pin "11") (pinfunction "GND_11") (pintype "power_in"))
      (node (ref "U6") (pin "15") (pinfunction "GND_15") (pintype "power_in"))
      (node (ref "U6") (pin "25") (pinfunction "GND_25") (pintype "power_in"))
      (node (ref "U6") (pin "35") (pinfunction "GND_35") (pintype "power_in"))
      (node (ref "U6") (pin "47") (pinfunction "GND_47") (pintype "power_in"))
      (node (ref "U6") (pin "5") (pinfunction "GND_5") (pintype "power_in"))
      (node (ref "U6") (pin "51") (pinfunction "GND_51") (pintype "power_in"))
      (node (ref "U7") (pin "4") (pinfunction "GND_4") (pintype "passive"))
      (node (ref "U8") (pin "2") (pinfunction "GND_2") (pintype "passive"))
      (node (ref "U9") (pin "10") (pinfunction "GND_10") (pintype "power_in"))
      (node (ref "U9-2") (pin "10") (pinfunction "GND_10") (pintype "power_in"))
      (node (ref "Y1") (pin "NC1") (pinfunction "3_NC1") (pintype "passive"))
      (node (ref "Y1") (pin "NC2") (pinfunction "4_NC2") (pintype "passive"))
      (node (ref "Y1-2") (pin "NC1") (pinfunction "3_NC1") (pintype "passive"))
      (node (ref "Y1-2") (pin "NC2") (pinfunction "4_NC2") (pintype "passive"))
    )
    (net (code "47") (name "DIS") (class "Default")
      (node (ref "R43") (pin "1") (pinfunction "1_1") (pintype "passive"))
      (node (ref "U6") (pin "32") (pinfunction "ACBUS5_32") (pintype "bidirectional"))
    )
    (net (code "48") (name "DIST") (class "Default")
      (node (ref "C184") (pin "2") (pinfunction "2_2") (pintype "passive"))
      (node (ref "R200") (pin "1") (pinfunction "1_1") (pintype "passive"))
      (node (ref "U13") (pin "1") (pinfunction "B_1") (pintype "bidirectional"))
    )
    (net (code "49") (name "DISTOCT") (class "Default")
      (node (ref "C183") (pin "1") (pinfunction "1_1") (pintype "passive"))
      (node (ref "J7") (pin "10") (pinfunction "10_10") (pintype "passive"))
    )
    (net (code "50") (name "DIST_OUT") (class "Default")
      (node (ref "C178") (pin "2") (pinfunction "2_2") (pintype "passive"))
      (node (ref "IC2") (pin "10") (pinfunction "B_10") (pintype "tri_state"))
      (node (ref "J7") (pin "8") (pinfunction "8_8") (pintype "passive"))
      (node (ref "R159") (pin "2") (pinfunction "2_2") (pintype "passive"))
      (node (ref "U21") (pin "1") (pinfunction "OUT_1") (pintype "output"))
    )
    (net (code "51") (name "DSP2_LDO_OUT") (class "Default")
      (node (ref "C38-2") (pin "1") (pinfunction "1_1") (pintype "passive"))
      (node (ref "C40-2") (pin "1") (pinfunction "1_1") (pintype "passive"))
      (node (ref "C41-2") (pin "1") (pinfunction "1_1") (pintype "passive"))
      (node (ref "C42-2") (pin "1") (pinfunction "1_1") (pintype "passive"))
      (node (ref "C46-2") (pin "1") (pinfunction "1_1") (pintype "passive"))
      (node (ref "C48-2") (pin "1") (pinfunction "1_1") (pintype "passive"))
      (node (ref "C51-2") (pin "1") (pinfunction "1_1") (pintype "passive"))
      (node (ref "C52-2") (pin "1") (pinfunction "1_1") (pintype "passive"))
      (node (ref "C53-2") (pin "1") (pinfunction "1_1") (pintype "passive"))
      (node (ref "C54-2") (pin "1") (pinfunction "1_1") (pintype "passive"))
      (node (ref "C55-2") (pin "1") (pinfunction "1_1") (pintype "passive"))
      (node (ref "C59-2") (pin "1") (pinfunction "1_1") (pintype "passive"))
      (node (ref "C62-2") (pin "1") (pinfunction "1_1") (pintype "passive"))
      (node (ref "C64-2") (pin "1") (pinfunction "1_1") (pintype "passive"))
      (node (ref "C65-2") (pin "1") (pinfunction "1_1") (pintype "passive"))
      (node (ref "C67-2") (pin "1") (pinfunction "1_1") (pintype "passive"))
      (node (ref "C69-2") (pin "1") (pinfunction "1_1") (pintype "passive"))
      (node (ref "C89-2") (pin "1") (pinfunction "1_1") (pintype "passive"))
      (node (ref "R124-2") (pin "2") (pinfunction "2_2") (pintype "passive"))
      (node (ref "U5") (pin "C11") (pinfunction "CVDD_C11") (pintype "power_in"))
      (node (ref "U5") (pin "D11") (pinfunction "CVDD_D11") (pintype "power_in"))
      (node (ref "U5") (pin "D3") (pinfunction "CVDD_D3") (pintype "power_in"))
      (node (ref "U5") (pin "F2") (pinfunction "CVDD_F2") (pintype "power_in"))
      (node (ref "U5") (pin "G3") (pinfunction "CVDD_G3") (pintype "power_in"))
      (node (ref "U5") (pin "H2") (pinfunction "CVDD_H2") (pintype "power_in"))
      (node (ref "U5") (pin "K11") (pinfunction "CVDD_K11") (pintype "power_in"))
      (node (ref "U5") (pin "K12") (pinfunction "RSV1_K12") (pintype "power_in"))
      (node (ref "U5") (pin "L13") (pinfunction "RSV2_L13") (pintype "power_in"))
      (node (ref "U5") (pin "M6") (pinfunction "CVDD_M6") (pintype "power_in"))
      (node (ref "U5") (pin "M9") (pinfunction "CVDD_M9") (pintype "power_in"))
      (node (ref "U5") (pin "N9") (pinfunction "CVDD_N9") (pintype "power_in"))
    )
    (net (code "52") (name "DSP2_LDO_OUT_REG") (class "Default")
      (node (ref "R124-2") (pin "1") (pinfunction "1_1") (pintype "passive"))
      (node (ref "U5") (pin "A13") (pinfunction "DSP_LDOO_A13") (pintype "power_in"))
    )
    (net (code "53") (name "DSP_LDO_OUT") (class "Default")
      (node (ref "C38") (pin "1") (pinfunction "1_1") (pintype "passive"))
      (node (ref "C40") (pin "1") (pinfunction "1_1") (pintype "passive"))
      (node (ref "C41") (pin "1") (pinfunction "1_1") (pintype "passive"))
      (node (ref "C42") (pin "1") (pinfunction "1_1") (pintype "passive"))
      (node (ref "C46") (pin "1") (pinfunction "1_1") (pintype "passive"))
      (node (ref "C48") (pin "1") (pinfunction "1_1") (pintype "passive"))
      (node (ref "C51") (pin "1") (pinfunction "1_1") (pintype "passive"))
      (node (ref "C52") (pin "1") (pinfunction "1_1") (pintype "passive"))
      (node (ref "C53") (pin "1") (pinfunction "1_1") (pintype "passive"))
      (node (ref "C54") (pin "1") (pinfunction "1_1") (pintype "passive"))
      (node (ref "C55") (pin "1") (pinfunction "1_1") (pintype "passive"))
      (node (ref "C59") (pin "1") (pinfunction "1_1") (pintype "passive"))
      (node (ref "C62") (pin "1") (pinfunction "1_1") (pintype "passive"))
      (node (ref "C64") (pin "1") (pinfunction "1_1") (pintype "passive"))
      (node (ref "C65") (pin "1") (pinfunction "1_1") (pintype "passive"))
      (node (ref "C67") (pin "1") (pinfunction "1_1") (pintype "passive"))
      (node (ref "C69") (pin "1") (pinfunction "1_1") (pintype "passive"))
      (node (ref "C89") (pin "1") (pinfunction "1_1") (pintype "passive"))
      (node (ref "R124") (pin "2") (pinfunction "2_2") (pintype "passive"))
      (node (ref "U4") (pin "C11") (pinfunction "CVDD_C11") (pintype "power_in"))
      (node (ref "U4") (pin "D11") (pinfunction "CVDD_D11") (pintype "power_in"))
      (node (ref "U4") (pin "D3") (pinfunction "CVDD_D3") (pintype "power_in"))
      (node (ref "U4") (pin "F2") (pinfunction "CVDD_F2") (pintype "power_in"))
      (node (ref "U4") (pin "G3") (pinfunction "CVDD_G3") (pintype "power_in"))
      (node (ref "U4") (pin "H2") (pinfunction "CVDD_H2") (pintype "power_in"))
      (node (ref "U4") (pin "K11") (pinfunction "CVDD_K11") (pintype "power_in"))
      (node (ref "U4") (pin "K12") (pinfunction "RSV1_K12") (pintype "power_in"))
      (node (ref "U4") (pin "L13") (pinfunction "RSV2_L13") (pintype "power_in"))
      (node (ref "U4") (pin "M6") (pinfunction "CVDD_M6") (pintype "power_in"))
      (node (ref "U4") (pin "M9") (pinfunction "CVDD_M9") (pintype "power_in"))
      (node (ref "U4") (pin "N9") (pinfunction "CVDD_N9") (pintype "power_in"))
    )
    (net (code "54") (name "DSP_LDO_OUT_REG") (class "Default")
      (node (ref "R124") (pin "1") (pinfunction "1_1") (pintype "passive"))
      (node (ref "U4") (pin "A13") (pinfunction "DSP_LDOO_A13") (pintype "power_in"))
    )
    (net (code "55") (name "EECS") (class "Default")
      (node (ref "U2") (pin "1") (pinfunction "CS_1") (pintype "input"))
      (node (ref "U6") (pin "63") (pinfunction "EECS_63") (pintype "bidirectional"))
    )
    (net (code "56") (name "EEDATA") (class "Default")
      (node (ref "R21") (pin "2") (pinfunction "2_2") (pintype "passive"))
      (node (ref "U2") (pin "3") (pinfunction "DI_3") (pintype "input"))
      (node (ref "U6") (pin "61") (pinfunction "EEDATA_61") (pintype "bidirectional"))
    )
    (net (code "57") (name "EESK") (class "Default")
      (node (ref "U2") (pin "2") (pinfunction "SK_2") (pintype "input"))
      (node (ref "U6") (pin "62") (pinfunction "EESK_62") (pintype "output"))
    )
    (net (code "58") (name "EMU0") (class "Default")
      (node (ref "R24") (pin "2") (pinfunction "2_2") (pintype "passive"))
      (node (ref "R25") (pin "1") (pinfunction "1_1") (pintype "passive"))
      (node (ref "U4") (pin "L2") (pinfunction "EMU0_L2") (pintype "bidirectional"))
      (node (ref "U5") (pin "L2") (pinfunction "EMU0_L2") (pintype "bidirectional"))
    )
    (net (code "59") (name "EMU1") (class "Default")
      (node (ref "R20") (pin "2") (pinfunction "2_2") (pintype "passive"))
      (node (ref "R22") (pin "1") (pinfunction "1_1") (pintype "passive"))
      (node (ref "U4") (pin "M1") (pinfunction "EMU1_M1") (pintype "bidirectional"))
      (node (ref "U5") (pin "M1") (pinfunction "EMU1_M1") (pintype "bidirectional"))
    )
    (net (code "60") (name "FOOTSW") (class "Default")
      (node (ref "C168X") (pin "1") (pinfunction "1_1") (pintype "passive"))
      (node (ref "SW1") (pin "2") (pinfunction "P_2") (pintype "passive"))
      (node (ref "U5") (pin "N12") (pinfunction "LCD_D[12]/UART_RTS/GP[28]/I2S3_CLK_N12") (pintype "bidirectional"))
    )
    (net (code "61") (name "FT1.8V") (class "Default")
      (node (ref "C33") (pin "1") (pinfunction "1_1") (pintype "passive"))
      (node (ref "C36") (pin "1") (pinfunction "1_1") (pintype "passive"))
      (node (ref "C68") (pin "1") (pinfunction "1_1") (pintype "passive"))
      (node (ref "C70") (pin "1") (pinfunction "1_1") (pintype "passive"))
      (node (ref "U6") (pin "12") (pinfunction "VCORE_12") (pintype "power_in"))
      (node (ref "U6") (pin "37") (pinfunction "VCORE_37") (pintype "power_in"))
      (node (ref "U6") (pin "49") (pinfunction "VREGOUT_49") (pintype "power_in"))
      (node (ref "U6") (pin "64") (pinfunction "VCORE_64") (pintype "power_in"))
    )
    (net (code "62") (name "FTDI_3V3") (class "Default")
      (node (ref "C20") (pin "1") (pinfunction "1_1") (pintype "passive"))
      (node (ref "C34") (pin "2") (pinfunction "2_2") (pintype "passive"))
      (node (ref "C35") (pin "1") (pinfunction "1_1") (pintype "passive"))
      (node (ref "C58") (pin "1") (pinfunction "1_1") (pintype "passive"))
      (node (ref "C78") (pin "1") (pinfunction "1_1") (pintype "passive"))
      (node (ref "C79") (pin "1") (pinfunction "1_1") (pintype "passive"))
      (node (ref "C80") (pin "1") (pinfunction "1_1") (pintype "passive"))
      (node (ref "L4") (pin "1") (pinfunction "1_1") (pintype "passive"))
      (node (ref "L5") (pin "1") (pinfunction "1_1") (pintype "passive"))
      (node (ref "R19") (pin "1") (pinfunction "1_1") (pintype "passive"))
      (node (ref "R1X") (pin "2") (pinfunction "2_2") (pintype "passive"))
      (node (ref "R36") (pin "1") (pinfunction "1_1") (pintype "passive"))
      (node (ref "R42") (pin "2") (pinfunction "2_2") (pintype "passive"))
      (node (ref "R44") (pin "2") (pinfunction "2_2") (pintype "passive"))
      (node (ref "U2") (pin "8") (pinfunction "VCC_8") (pintype "power_in"))
      (node (ref "U6") (pin "20") (pinfunction "VCCIO_20") (pintype "power_in"))
      (node (ref "U6") (pin "31") (pinfunction "VCCIO_31") (pintype "power_in"))
      (node (ref "U6") (pin "42") (pinfunction "VCCIO_42") (pintype "power_in"))
      (node (ref "U6") (pin "50") (pinfunction "VREGIN_50") (pintype "power_in"))
      (node (ref "U6") (pin "56") (pinfunction "VCCIO_56") (pintype "power_in"))
      (node (ref "U8") (pin "3") (pinfunction "D_3") (pintype "input"))
      (node (ref "U8") (pin "5") (pinfunction "VCC_5") (pintype "power_in"))
    )
    (net (code "63") (name "GND-A") (class "Default")
      (node (ref "C111") (pin "2") (pinfunction "2_2") (pintype "passive"))
      (node (ref "C116") (pin "2") (pinfunction "2_2") (pintype "passive"))
      (node (ref "C117") (pin "2") (pinfunction "2_2") (pintype "passive"))
      (node (ref "C12") (pin "2") (pinfunction "2_2") (pintype "passive"))
      (node (ref "C173") (pin "2") (pinfunction "2_2") (pintype "passive"))
      (node (ref "C177") (pin "2") (pinfunction "2_2") (pintype "passive"))
      (node (ref "C179") (pin "-") (pinfunction "-_-") (pintype "passive"))
      (node (ref "C18") (pin "2") (pinfunction "2_2") (pintype "passive"))
      (node (ref "C180") (pin "-") (pinfunction "-_-") (pintype "passive"))
      (node (ref "C182") (pin "2") (pinfunction "2_2") (pintype "passive"))
      (node (ref "C19") (pin "2") (pinfunction "2_2") (pintype "passive"))
      (node (ref "C192") (pin "1") (pinfunction "1_1") (pintype "passive"))
      (node (ref "C196") (pin "2") (pinfunction "2_2") (pintype "passive"))
      (node (ref "C199") (pin "1") (pinfunction "1_1") (pintype "passive"))
      (node (ref "C223") (pin "2") (pinfunction "2_2") (pintype "passive"))
      (node (ref "C224") (pin "2") (pinfunction "2_2") (pintype "passive"))
      (node (ref "CF1") (pin "2@1") (pinfunction "2_2@1") (pintype "passive"))
      (node (ref "D9") (pin "A") (pinfunction "A_A") (pintype "passive"))
      (node (ref "FB2") (pin "2") (pinfunction "2_2") (pintype "passive"))
      (node (ref "J10") (pin "S") (pinfunction "S_S") (pintype "passive"))
      (node (ref "J3") (pin "S") (pinfunction "S_S") (pintype "passive"))
      (node (ref "J3") (pin "SN") (pinfunction "SN_SN") (pintype "passive"))
      (node (ref "J3") (pin "TN") (pinfunction "TN_TN") (pintype "passive"))
      (node (ref "J4") (pin "1") (pinfunction "S_1") (pintype "passive"))
      (node (ref "J9") (pin "S") (pinfunction "S_S") (pintype "passive"))
      (node (ref "LSP3") (pin "MP") (pinfunction "MP_MP") (pintype "passive"))
      (node (ref "Q1") (pin "E") (pinfunction "E_E") (pintype "passive"))
      (node (ref "Q5") (pin "2") (pinfunction "S_2") (pintype "bidirectional"))
      (node (ref "R111") (pin "1") (pinfunction "1_1") (pintype "passive"))
      (node (ref "R147") (pin "1") (pinfunction "1_1") (pintype "passive"))
      (node (ref "R156") (pin "1") (pinfunction "1_1") (pintype "passive"))
      (node (ref "R167") (pin "1") (pinfunction "1_1") (pintype "passive"))
      (node (ref "R170") (pin "1") (pinfunction "1_1") (pintype "passive"))
      (node (ref "R182") (pin "1") (pinfunction "1_1") (pintype "passive"))
      (node (ref "R183") (pin "1") (pinfunction "1_1") (pintype "passive"))
      (node (ref "R193") (pin "1") (pinfunction "1_1") (pintype "passive"))
      (node (ref "R194") (pin "1") (pinfunction "1_1") (pintype "passive"))
      (node (ref "R197") (pin "1") (pinfunction "1_1") (pintype "passive"))
      (node (ref "U17") (pin "17") (pinfunction "AVSS_17") (pintype "power_in"))
      (node (ref "U17") (pin "33") (pinfunction "EP_33") (pintype "power_in"))
      (node (ref "U19") (pin "4") (pinfunction "V-_4") (pintype "power_in"))
      (node (ref "U20") (pin "4") (pinfunction "V-_4") (pintype "power_in"))
      (node (ref "U21") (pin "4") (pinfunction "V-_4") (pintype "power_in"))
      (node (ref "U22") (pin "4") (pinfunction "V-_4") (pintype "power_in"))
      (node (ref "U23") (pin "4") (pinfunction "V-_4") (pintype "power_in"))
    )
    (net (code "64") (name "GPAIN0") (class "Default")
      (node (ref "J7") (pin "17") (pinfunction "17_17") (pintype "passive"))
      (node (ref "U4") (pin "A8") (pinfunction "GPAIN0_A8") (pintype "bidirectional"))
    )
    (net (code "65") (name "GPAIN1") (class "Default")
      (node (ref "J7") (pin "15") (pinfunction "15_15") (pintype "passive"))
      (node (ref "U4") (pin "B8") (pinfunction "GPAIN1_B8") (pintype "bidirectional"))
    )
    (net (code "66") (name "GPAIN2") (class "Default")
      (node (ref "J7") (pin "9") (pinfunction "9_9") (pintype "passive"))
      (node (ref "U4") (pin "A9") (pinfunction "GPAIN2_A9") (pintype "bidirectional"))
    )
    (net (code "67") (name "GPAIN2_2") (class "Default")
      (node (ref "J7") (pin "7") (pinfunction "7_7") (pintype "passive"))
      (node (ref "U5") (pin "A9") (pinfunction "GPAIN2_A9") (pintype "bidirectional"))
    )
    (net (code "68") (name "GPAIN2_3") (class "Default")
      (node (ref "J7") (pin "11") (pinfunction "11_11") (pintype "passive"))
      (node (ref "U5") (pin "A10") (pinfunction "GPAIN3_A10") (pintype "bidirectional"))
    )
    (net (code "69") (name "GPAIN3") (class "Default")
      (node (ref "J7") (pin "13") (pinfunction "13_13") (pintype "passive"))
      (node (ref "U4") (pin "A10") (pinfunction "GPAIN3_A10") (pintype "bidirectional"))
    )
    (net (code "70") (name "GPIO10") (class "Default")
      (node (ref "R84") (pin "1") (pinfunction "1_1") (pintype "passive"))
      (node (ref "U4") (pin "P3") (pinfunction "LCD_D[6]/GP[16]_P3") (pintype "tri_state"))
    )
    (net (code "71") (name "GPIO13") (class "Default")
      (node (ref "TP14") (pin "TP") (pinfunction "TP_TP") (pintype "input"))
      (node (ref "U4") (pin "N5") (pinfunction "LCD_D[3]/GP[13]_N5") (pintype "tri_state"))
    )
    (net (code "72") (name "GPIO14") (class "Default")
      (node (ref "TP15") (pin "TP") (pinfunction "TP_TP") (pintype "input"))
      (node (ref "U4") (pin "P2") (pinfunction "LCD_D[4]/GP[14]_P2") (pintype "tri_state"))
    )
    (net (code "73") (name "GPIO15") (class "Default")
      (node (ref "TP16") (pin "TP") (pinfunction "TP_TP") (pintype "input"))
      (node (ref "U4") (pin "N7") (pinfunction "LCD_D[5]/GP[15]_N7") (pintype "tri_state"))
    )
    (net (code "74") (name "HP_LOUT") (class "Default")
      (node (ref "C14") (pin "+") (pinfunction "+_+") (pintype "passive"))
      (node (ref "U17") (pin "25") (pinfunction "HPL_25") (pintype "output"))
    )
    (net (code "75") (name "HP_ROUT") (class "Default")
      (node (ref "C13") (pin "+") (pinfunction "+_+") (pintype "passive"))
      (node (ref "U17") (pin "27") (pinfunction "HPR_27") (pintype "output"))
    )
    (net (code "76") (name "I2C2_SCL") (class "Default")
      (node (ref "R14-2") (pin "1") (pinfunction "1_1") (pintype "passive"))
      (node (ref "R26") (pin "1") (pinfunction "1_1") (pintype "passive"))
      (node (ref "U10X") (pin "6") (pinfunction "SCL_6") (pintype "input"))
      (node (ref "U5") (pin "C4") (pinfunction "I2C_SCL_C4") (pintype "bidirectional"))
    )
    (net (code "77") (name "I2C2_SDA") (class "Default")
      (node (ref "R13-2") (pin "1") (pinfunction "1_1") (pintype "passive"))
      (node (ref "R31") (pin "1") (pinfunction "1_1") (pintype "passive"))
      (node (ref "U10X") (pin "5") (pinfunction "SDA_5") (pintype "bidirectional"))
      (node (ref "U5") (pin "A4") (pinfunction "I2C_SDA_A4") (pintype "bidirectional"))
    )
    (net (code "78") (name "I2C_SCL") (class "Default")
      (node (ref "R14") (pin "1") (pinfunction "1_1") (pintype "passive"))
      (node (ref "R26") (pin "2") (pinfunction "2_2") (pintype "passive"))
      (node (ref "U18") (pin "7") (pinfunction "A6_7") (pintype "bidirectional"))
      (node (ref "U4") (pin "C4") (pinfunction "I2C_SCL_C4") (pintype "bidirectional"))
    )
    (net (code "79") (name "I2C_SCL_AIC") (class "Default")
      (node (ref "R134") (pin "1") (pinfunction "1_1") (pintype "passive"))
      (node (ref "U17") (pin "9") (pinfunction "SCL/SSZ_9") (pintype "input"))
      (node (ref "U18") (pin "13") (pinfunction "B6_13") (pintype "bidirectional"))
    )
    (net (code "80") (name "I2C_SDA") (class "Default")
      (node (ref "R13") (pin "1") (pinfunction "1_1") (pintype "passive"))
      (node (ref "R31") (pin "2") (pinfunction "2_2") (pintype "passive"))
      (node (ref "U18") (pin "8") (pinfunction "A7_8") (pintype "bidirectional"))
      (node (ref "U4") (pin "A4") (pinfunction "I2C_SDA_A4") (pintype "bidirectional"))
    )
    (net (code "81") (name "I2C_SDA_AIC") (class "Default")
      (node (ref "R135") (pin "1") (pinfunction "1_1") (pintype "passive"))
      (node (ref "U17") (pin "10") (pinfunction "SDA/MOSI_10") (pintype "input"))
      (node (ref "U18") (pin "12") (pinfunction "B7_12") (pintype "bidirectional"))
    )
    (net (code "82") (name "I2S2_2_CLK") (class "Default")
      (node (ref "TP28X") (pin "TP") (pinfunction "TP_TP") (pintype "input"))
      (node (ref "U5") (pin "P5") (pinfunction "LCD_D[8]/I2S2_CLK/GP[18]/SPI_CLK_P5") (pintype "bidirectional"))
    )
    (net (code "83") (name "I2S2_2_DX") (class "Default")
      (node (ref "TP31X") (pin "TP") (pinfunction "TP_TP") (pintype "input"))
      (node (ref "U5") (pin "P11") (pinfunction "LCD_D[11]/I2S2_DX/GP[27]/SPI_TX_P11") (pintype "bidirectional"))
    )
    (net (code "84") (name "I2S2_2_FS") (class "Default")
      (node (ref "TP29X") (pin "TP") (pinfunction "TP_TP") (pintype "input"))
      (node (ref "U5") (pin "N10") (pinfunction "LCD_D[9]/I2S2_FS/GP[19]/SPI_CS0_N10") (pintype "bidirectional"))
    )
    (net (code "85") (name "I2S2_2_RX") (class "Default")
      (node (ref "TP30X") (pin "TP") (pinfunction "TP_TP") (pintype "input"))
      (node (ref "U5") (pin "P9") (pinfunction "LCD_D[10]/I2S2_RX/GP[20]/SPI_RX_P9") (pintype "bidirectional"))
    )
    (net (code "86") (name "I2S2_CLK") (class "Default")
      (node (ref "U18") (pin "3") (pinfunction "A2_3") (pintype "bidirectional"))
      (node (ref "U4") (pin "P5") (pinfunction "LCD_D[8]/I2S2_CLK/GP[18]/SPI_CLK_P5") (pintype "bidirectional"))
    )
    (net (code "87") (name "I2S2_DX") (class "Default")
      (node (ref "U18") (pin "5") (pinfunction "A4_5") (pintype "bidirectional"))
      (node (ref "U4") (pin "P11") (pinfunction "LCD_D[11]/I2S2_DX/GP[27]/SPI_TX_P11") (pintype "bidirectional"))
    )
    (net (code "88") (name "I2S2_FS") (class "Default")
      (node (ref "U18") (pin "4") (pinfunction "A3_4") (pintype "bidirectional"))
      (node (ref "U4") (pin "N10") (pinfunction "LCD_D[9]/I2S2_FS/GP[19]/SPI_CS0_N10") (pintype "bidirectional"))
    )
    (net (code "89") (name "I2S2_RX") (class "Default")
      (node (ref "U18") (pin "6") (pinfunction "A5_6") (pintype "bidirectional"))
      (node (ref "U4") (pin "P9") (pinfunction "LCD_D[10]/I2S2_RX/GP[20]/SPI_RX_P9") (pintype "bidirectional"))
    )
    (net (code "90") (name "INT1_0_N") (class "Default")
      (node (ref "R105X") (pin "1") (pinfunction "1_1") (pintype "passive"))
      (node (ref "R37") (pin "1") (pinfunction "1_1") (pintype "passive"))
      (node (ref "U4") (pin "C2") (pinfunction "INT0_C2") (pintype "input"))
    )
    (net (code "91") (name "INT1_1_N") (class "Default")
      (node (ref "R41") (pin "1") (pinfunction "1_1") (pintype "passive"))
      (node (ref "R84") (pin "2") (pinfunction "2_2") (pintype "passive"))
      (node (ref "U4") (pin "B1") (pinfunction "INT1_B1") (pintype "input"))
    )
    (net (code "92") (name "INT2_0_N") (class "Default")
      (node (ref "R41-2") (pin "1") (pinfunction "1_1") (pintype "passive"))
      (node (ref "R67") (pin "1") (pinfunction "1_1") (pintype "passive"))
      (node (ref "U5") (pin "C2") (pinfunction "INT0_C2") (pintype "input"))
    )
    (net (code "93") (name "INT2_1_N") (class "Default")
      (node (ref "R37-2") (pin "1") (pinfunction "1_1") (pintype "passive"))
      (node (ref "R83X") (pin "2") (pinfunction "2_2") (pintype "passive"))
      (node (ref "U5") (pin "B1") (pinfunction "INT1_B1") (pintype "input"))
    )
    (net (code "94") (name "LCD_A0") (class "Default")
      (node (ref "J5") (pin "13") (pinfunction "13_13") (pintype "passive"))
      (node (ref "U5") (pin "J2") (pinfunction "LCD_D[2]/GP[12]_J2") (pintype "tri_state"))
    )
    (net (code "95") (name "LED1") (class "Default")
      (node (ref "J7") (pin "1") (pinfunction "1_1") (pintype "passive"))
      (node (ref "U5") (pin "M14") (pinfunction "SD1_CLK/I2S1_CLK/GP[6]_M14") (pintype "bidirectional"))
    )
    (net (code "96") (name "LED2") (class "Default")
      (node (ref "J7") (pin "3") (pinfunction "3_3") (pintype "passive"))
      (node (ref "U5") (pin "L11") (pinfunction "SD1_CMD/I2S1_FS/GP[7]_L11") (pintype "bidirectional"))
    )
    (net (code "97") (name "LED3") (class "Default")
      (node (ref "J7") (pin "4") (pinfunction "4_4") (pintype "passive"))
      (node (ref "U5") (pin "M13") (pinfunction "SD1_D0/2S1_DX/GP[8]_M13") (pintype "bidirectional"))
    )
    (net (code "98") (name "LED4") (class "Default")
      (node (ref "J7") (pin "5") (pinfunction "5_5") (pintype "passive"))
      (node (ref "U5") (pin "P10") (pinfunction "SD1_D1/I2S1_RX/GP[9]_P10") (pintype "bidirectional"))
    )
    (net (code "99") (name "LED5") (class "Default")
      (node (ref "J7") (pin "6") (pinfunction "6_6") (pintype "passive"))
      (node (ref "U5") (pin "L12") (pinfunction "SD1_D2/GP[10]_L12") (pintype "bidirectional"))
    )
    (net (code "100") (name "LINEIN") (class "Default")
      (node (ref "C170") (pin "1") (pinfunction "1_1") (pintype "passive"))
      (node (ref "FB12") (pin "2") (pinfunction "2_2") (pintype "passive"))
      (node (ref "R169") (pin "1") (pinfunction "1_1") (pintype "passive"))
    )
    (net (code "101") (name "LINEOUT_L") (class "Default")
      (node (ref "C191") (pin "1") (pinfunction "1_1") (pintype "passive"))
      (node (ref "U17") (pin "22") (pinfunction "LOL_22") (pintype "output"))
    )
    (net (code "102") (name "LINEOUT_R") (class "Default")
      (node (ref "C198") (pin "1") (pinfunction "1_1") (pintype "passive"))
      (node (ref "U17") (pin "23") (pinfunction "LOR_23") (pintype "output"))
    )
    (net (code "103") (name "MCLK_12MHZ") (class "Default")
      (node (ref "R228X") (pin "2") (pinfunction "2_2") (pintype "passive"))
      (node (ref "U18") (pin "9") (pinfunction "A8_9") (pintype "bidirectional"))
    )
    (net (code "104") (name "MUTE") (class "Default")
      (node (ref "R186") (pin "1") (pinfunction "1_1") (pintype "passive"))
      (node (ref "U5") (pin "P7") (pinfunction "SD0_D3/GP[5]_P7") (pintype "bidirectional"))
    )
    (net (code "105") (name "NOISE_SUP") (class "Default")
      (node (ref "R213") (pin "2") (pinfunction "2_2") (pintype "passive"))
      (node (ref "R216") (pin "2") (pinfunction "2_2") (pintype "passive"))
      (node (ref "U5") (pin "B8") (pinfunction "GPAIN1_B8") (pintype "bidirectional"))
    )
    (net (code "106") (name "Net-(C21X-Pad1)") (class "Default")
      (node (ref "C21X") (pin "1") (pinfunction "1_1") (pintype "passive"))
      (node (ref "L6X") (pin "1") (pinfunction "1_1") (pintype "passive"))
      (node (ref "R118X") (pin "1") (pinfunction "1_1") (pintype "passive"))
      (node (ref "R11X") (pin "2") (pinfunction "2_2") (pintype "passive"))
      (node (ref "TP4X") (pin "TP") (pinfunction "TP_TP") (pintype "input"))
    )
    (net (code "107") (name "Net-(C170-Pad2)") (class "Default")
      (node (ref "C170") (pin "2") (pinfunction "2_2") (pintype "passive"))
      (node (ref "R144") (pin "1") (pinfunction "1_1") (pintype "passive"))
    )
    (net (code "108") (name "Net-(C172-Pad1)") (class "Default")
      (node (ref "C172") (pin "1") (pinfunction "1_1") (pintype "passive"))
      (node (ref "R148") (pin "2") (pinfunction "2_2") (pintype "passive"))
    )
    (net (code "109") (name "Net-(C173-Pad1)") (class "Default")
      (node (ref "C173") (pin "1") (pinfunction "1_1") (pintype "passive"))
      (node (ref "R150") (pin "1") (pinfunction "1_1") (pintype "passive"))
    )
    (net (code "110") (name "Net-(C176-Pad1)") (class "Default")
      (node (ref "C176") (pin "1") (pinfunction "1_1") (pintype "passive"))
      (node (ref "R154") (pin "2") (pinfunction "2_2") (pintype "passive"))
      (node (ref "R155") (pin "1") (pinfunction "1_1") (pintype "passive"))
    )
    (net (code "111") (name "Net-(C176-Pad2)") (class "Default")
      (node (ref "C176") (pin "2") (pinfunction "2_2") (pintype "passive"))
      (node (ref "Q1") (pin "C") (pinfunction "C_C") (pintype "passive"))
      (node (ref "R156") (pin "2") (pinfunction "2_2") (pintype "passive"))
    )
    (net (code "112") (name "Net-(C182-Pad1)") (class "Default")
      (node (ref "C182") (pin "1") (pinfunction "1_1") (pintype "passive"))
      (node (ref "R165") (pin "1") (pinfunction "1_1") (pintype "passive"))
    )
    (net (code "113") (name "Net-(C183-Pad2)") (class "Default")
      (node (ref "C183") (pin "2") (pinfunction "2_2") (pintype "passive"))
      (node (ref "R166") (pin "1") (pinfunction "1_1") (pintype "passive"))
    )
    (net (code "114") (name "Net-(C184-Pad1)") (class "Default")
      (node (ref "C184") (pin "1") (pinfunction "1_1") (pintype "passive"))
      (node (ref "R166") (pin "2") (pinfunction "2_2") (pintype "passive"))
      (node (ref "R167") (pin "2") (pinfunction "2_2") (pintype "passive"))
    )
    (net (code "115") (name "Net-(C186-Pad1)") (class "Default")
      (node (ref "C186") (pin "1") (pinfunction "1_1") (pintype "passive"))
      (node (ref "R169") (pin "2") (pinfunction "2_2") (pintype "passive"))
    )
    (net (code "116") (name "Net-(C187-Pad2)") (class "Default")
      (node (ref "C187") (pin "2") (pinfunction "2_2") (pintype "passive"))
      (node (ref "R174") (pin "1") (pinfunction "1_1") (pintype "passive"))
    )
    (net (code "117") (name "Net-(C191-Pad2)") (class "Default")
      (node (ref "C191") (pin "2") (pinfunction "2_2") (pintype "passive"))
      (node (ref "R180") (pin "1") (pinfunction "1_1") (pintype "passive"))
    )
    (net (code "118") (name "Net-(C192-Pad2)") (class "Default")
      (node (ref "C192") (pin "2") (pinfunction "2_2") (pintype "passive"))
      (node (ref "R176") (pin "1") (pinfunction "1_1") (pintype "passive"))
      (node (ref "R178") (pin "1") (pinfunction "1_1") (pintype "passive"))
      (node (ref "R180") (pin "2") (pinfunction "2_2") (pintype "passive"))
    )
    (net (code "119") (name "Net-(C193-Pad1)") (class "Default")
      (node (ref "C193") (pin "1") (pinfunction "1_1") (pintype "passive"))
      (node (ref "R181") (pin "2") (pinfunction "2_2") (pintype "passive"))
    )
    (net (code "120") (name "Net-(C194-Pad2)") (class "Default")
      (node (ref "C194") (pin "2") (pinfunction "2_2") (pintype "passive"))
      (node (ref "R182") (pin "2") (pinfunction "2_2") (pintype "passive"))
    )
    (net (code "121") (name "Net-(C195-Pad2)") (class "Default")
      (node (ref "C195") (pin "2") (pinfunction "2_2") (pintype "passive"))
      (node (ref "R183") (pin "2") (pinfunction "2_2") (pintype "passive"))
      (node (ref "R184") (pin "1") (pinfunction "1_1") (pintype "passive"))
    )
    (net (code "122") (name "Net-(C198-Pad2)") (class "Default")
      (node (ref "C198") (pin "2") (pinfunction "2_2") (pintype "passive"))
      (node (ref "R190") (pin "1") (pinfunction "1_1") (pintype "passive"))
    )
    (net (code "123") (name "Net-(C199-Pad2)") (class "Default")
      (node (ref "C199") (pin "2") (pinfunction "2_2") (pintype "passive"))
      (node (ref "R187") (pin "1") (pinfunction "1_1") (pintype "passive"))
      (node (ref "R188") (pin "1") (pinfunction "1_1") (pintype "passive"))
      (node (ref "R190") (pin "2") (pinfunction "2_2") (pintype "passive"))
    )
    (net (code "124") (name "Net-(C201-Pad1)") (class "Default")
      (node (ref "C201") (pin "1") (pinfunction "1_1") (pintype "passive"))
      (node (ref "R192") (pin "2") (pinfunction "2_2") (pintype "passive"))
    )
    (net (code "125") (name "Net-(C202-Pad2)") (class "Default")
      (node (ref "C202") (pin "2") (pinfunction "2_2") (pintype "passive"))
      (node (ref "R193") (pin "2") (pinfunction "2_2") (pintype "passive"))
    )
    (net (code "126") (name "Net-(C203-Pad2)") (class "Default")
      (node (ref "C203") (pin "2") (pinfunction "2_2") (pintype "passive"))
      (node (ref "R194") (pin "2") (pinfunction "2_2") (pintype "passive"))
      (node (ref "R195") (pin "1") (pinfunction "1_1") (pintype "passive"))
    )
    (net (code "127") (name "Net-(C207-Pad2)") (class "Default")
      (node (ref "C207") (pin "2") (pinfunction "2_2") (pintype "passive"))
      (node (ref "R210") (pin "1") (pinfunction "1_1") (pintype "passive"))
    )
    (net (code "128") (name "Net-(C210-Pad1)") (class "Default")
      (node (ref "C210") (pin "1") (pinfunction "1_1") (pintype "passive"))
      (node (ref "C211") (pin "2") (pinfunction "2_2") (pintype "passive"))
      (node (ref "R206") (pin "1") (pinfunction "1_1") (pintype "passive"))
      (node (ref "R207") (pin "1") (pinfunction "1_1") (pintype "passive"))
      (node (ref "R209") (pin "2") (pinfunction "2_2") (pintype "passive"))
    )
    (net (code "129") (name "Net-(C211-Pad1)") (class "Default")
      (node (ref "C211") (pin "1") (pinfunction "1_1") (pintype "passive"))
      (node (ref "R205") (pin "1") (pinfunction "1_1") (pintype "passive"))
    )
    (net (code "130") (name "Net-(D3X-PadC)") (class "Default")
      (node (ref "D3X") (pin "C") (pinfunction "C_C") (pintype "passive"))
      (node (ref "R76X") (pin "2") (pinfunction "2_2") (pintype "passive"))
    )
    (net (code "131") (name "Net-(D6-C)") (class "Default")
      (node (ref "C181") (pin "2") (pinfunction "2_2") (pintype "passive"))
      (node (ref "D6") (pin "3") (pinfunction "C_3") (pintype "passive"))
      (node (ref "D8") (pin "1") (pinfunction "A1_1") (pintype "passive"))
      (node (ref "IC2") (pin "11") (pinfunction "A_11") (pintype "tri_state"))
    )
    (net (code "132") (name "Net-(D7-A1)") (class "Default")
      (node (ref "C206") (pin "1") (pinfunction "1_1") (pintype "passive"))
      (node (ref "D7") (pin "1") (pinfunction "A1_1") (pintype "passive"))
      (node (ref "D7") (pin "2") (pinfunction "C2_2") (pintype "passive"))
      (node (ref "R205") (pin "2") (pinfunction "2_2") (pintype "passive"))
      (node (ref "R208") (pin "1") (pinfunction "1_1") (pintype "passive"))
      (node (ref "U24") (pin "2") (pinfunction "-IN1_2") (pintype "input"))
    )
    (net (code "133") (name "Net-(D7-C1A2)") (class "Default")
      (node (ref "C205") (pin "1") (pinfunction "1_1") (pintype "passive"))
      (node (ref "D7") (pin "3") (pinfunction "C1A2_3") (pintype "passive"))
      (node (ref "R206") (pin "2") (pinfunction "2_2") (pintype "passive"))
      (node (ref "R210") (pin "2") (pinfunction "2_2") (pintype "passive"))
      (node (ref "U24") (pin "3") (pinfunction "+IN1_3") (pintype "input"))
    )
    (net (code "134") (name "Net-(DS1-PadC)") (class "Default")
      (node (ref "DS1") (pin "C") (pinfunction "C_C") (pintype "passive"))
      (node (ref "R12") (pin "2") (pinfunction "2_2") (pintype "passive"))
    )
    (net (code "135") (name "Net-(DS2-PadC)") (class "Default")
      (node (ref "DS2") (pin "C") (pinfunction "C_C") (pintype "passive"))
      (node (ref "R17") (pin "2") (pinfunction "2_2") (pintype "passive"))
    )
    (net (code "136") (name "Net-(FB12-Pad1)") (class "Default")
      (node (ref "FB12") (pin "1") (pinfunction "1_1") (pintype "passive"))
      (node (ref "J3") (pin "T") (pinfunction "T_T") (pintype "passive"))
    )
    (net (code "137") (name "Net-(FB13-Pad1)") (class "Default")
      (node (ref "FB13") (pin "1") (pinfunction "1_1") (pintype "passive"))
      (node (ref "J9") (pin "T") (pinfunction "T_T") (pintype "passive"))
    )
    (net (code "138") (name "Net-(FB13-Pad2)") (class "Default")
      (node (ref "FB13") (pin "2") (pinfunction "2_2") (pintype "passive"))
      (node (ref "R185") (pin "2") (pinfunction "2_2") (pintype "passive"))
    )
    (net (code "139") (name "Net-(FB14-Pad1)") (class "Default")
      (node (ref "FB14") (pin "1") (pinfunction "1_1") (pintype "passive"))
      (node (ref "J10") (pin "T") (pinfunction "T_T") (pintype "passive"))
    )
    (net (code "140") (name "Net-(FB14-Pad2)") (class "Default")
      (node (ref "FB14") (pin "2") (pinfunction "2_2") (pintype "passive"))
      (node (ref "R196") (pin "2") (pinfunction "2_2") (pintype "passive"))
    )
    (net (code "141") (name "Net-(IC2A-A)") (class "Default")
      (node (ref "IC2") (pin "1") (pinfunction "A_1") (pintype "tri_state"))
      (node (ref "IC2") (pin "3") (pinfunction "B_3") (pintype "tri_state"))
      (node (ref "R152") (pin "2") (pinfunction "2_2") (pintype "passive"))
      (node (ref "R153") (pin "1") (pinfunction "1_1") (pintype "passive"))
    )
    (net (code "142") (name "Net-(IC2A-B)") (class "Default")
      (node (ref "C174") (pin "2") (pinfunction "2_2") (pintype "passive"))
      (node (ref "C175") (pin "1") (pinfunction "1_1") (pintype "passive"))
      (node (ref "IC2") (pin "2") (pinfunction "B_2") (pintype "tri_state"))
      (node (ref "R153") (pin "2") (pinfunction "2_2") (pintype "passive"))
      (node (ref "R154") (pin "1") (pinfunction "1_1") (pintype "passive"))
      (node (ref "U19") (pin "7") (pinfunction "OUT_7") (pintype "output"))
    )
    (net (code "143") (name "Net-(IC2A-C)") (class "Default")
      (node (ref "IC2") (pin "13") (pinfunction "C_13") (pintype "input"))
      (node (ref "Q8") (pin "C") (pinfunction "C_C") (pintype "passive"))
      (node (ref "R202") (pin "1") (pinfunction "1_1") (pintype "passive"))
    )
    (net (code "144") (name "Net-(IC2B-A)") (class "Default")
      (node (ref "IC2") (pin "4") (pinfunction "A_4") (pintype "tri_state"))
      (node (ref "R151") (pin "2") (pinfunction "2_2") (pintype "passive"))
      (node (ref "R152") (pin "1") (pinfunction "1_1") (pintype "passive"))
    )
    (net (code "145") (name "Net-(IC2B-C)") (class "Default")
      (node (ref "IC2") (pin "5") (pinfunction "C_5") (pintype "input"))
      (node (ref "Q9") (pin "C") (pinfunction "C_C") (pintype "passive"))
      (node (ref "R203") (pin "1") (pinfunction "1_1") (pintype "passive"))
    )
    (net (code "146") (name "Net-(IC2C-A)") (class "Default")
      (node (ref "C177") (pin "1") (pinfunction "1_1") (pintype "passive"))
      (node (ref "IC2") (pin "8") (pinfunction "A_8") (pintype "tri_state"))
      (node (ref "R157") (pin "1") (pinfunction "1_1") (pintype "passive"))
    )
    (net (code "147") (name "Net-(IC2C-B)") (class "Default")
      (node (ref "IC2") (pin "9") (pinfunction "B_9") (pintype "tri_state"))
      (node (ref "R157") (pin "2") (pinfunction "2_2") (pintype "passive"))
      (node (ref "R161") (pin "1") (pinfunction "1_1") (pintype "passive"))
    )
    (net (code "148") (name "Net-(IC2C-C)") (class "Default")
      (node (ref "IC2") (pin "6") (pinfunction "C_6") (pintype "input"))
      (node (ref "Q2") (pin "B") (pinfunction "B_B") (pintype "passive"))
      (node (ref "Q4") (pin "C") (pinfunction "C_C") (pintype "passive"))
      (node (ref "R201") (pin "1") (pinfunction "1_1") (pintype "passive"))
    )
    (net (code "149") (name "Net-(IC2D-C)") (class "Default")
      (node (ref "IC2") (pin "12") (pinfunction "C_12") (pintype "input"))
      (node (ref "Q2") (pin "C") (pinfunction "C_C") (pintype "passive"))
      (node (ref "R168") (pin "1") (pinfunction "1_1") (pintype "passive"))
    )
    (net (code "150") (name "Net-(J2-P$1)") (class "Default")
      (node (ref "C37") (pin "2") (pinfunction "2_2") (pintype "passive"))
      (node (ref "J2") (pin "5") (pinfunction "P$1_5") (pintype "bidirectional"))
      (node (ref "J2") (pin "6") (pinfunction "P$2_6") (pintype "bidirectional"))
    )
    (net (code "151") (name "Net-(J6-INSERT)") (class "Default")
      (node (ref "J6") (pin "9") (pinfunction "INSERT_9") (pintype "passive"))
      (node (ref "R109") (pin "1") (pinfunction "1_1") (pintype "passive"))
    )
    (net (code "152") (name "Net-(J11-INSERT)") (class "Default")
      (node (ref "J11") (pin "9") (pinfunction "INSERT_9") (pintype "passive"))
      (node (ref "R1") (pin "1") (pinfunction "1_1") (pintype "passive"))
    )
    (net (code "153") (name "Net-(Q3-G)") (class "Default")
      (node (ref "C186") (pin "2") (pinfunction "2_2") (pintype "passive"))
      (node (ref "Q3") (pin "3") (pinfunction "G_3") (pintype "passive"))
      (node (ref "R171") (pin "2") (pinfunction "2_2") (pintype "passive"))
    )
    (net (code "154") (name "Net-(Q3-S)") (class "Default")
      (node (ref "C187") (pin "1") (pinfunction "1_1") (pintype "passive"))
      (node (ref "Q3") (pin "2") (pinfunction "S_2") (pintype "passive"))
      (node (ref "R170") (pin "2") (pinfunction "2_2") (pintype "passive"))
      (node (ref "R173") (pin "1") (pinfunction "1_1") (pintype "passive"))
    )
    (net (code "155") (name "Net-(Q5-D)") (class "Default")
      (node (ref "Q5") (pin "3") (pinfunction "D_3") (pintype "bidirectional"))
      (node (ref "Q6") (pin "3") (pinfunction "D_3") (pintype "bidirectional"))
      (node (ref "Q7") (pin "3") (pinfunction "D_3") (pintype "bidirectional"))
    )
    (net (code "156") (name "Net-(Q5-G)") (class "Default")
      (node (ref "C196") (pin "1") (pinfunction "1_1") (pintype "passive"))
      (node (ref "Q5") (pin "1") (pinfunction "G_1") (pintype "bidirectional"))
      (node (ref "Q6") (pin "1") (pinfunction "G_1") (pintype "bidirectional"))
      (node (ref "Q7") (pin "1") (pinfunction "G_1") (pintype "bidirectional"))
      (node (ref "R186") (pin "2") (pinfunction "2_2") (pintype "passive"))
    )
    (net (code "157") (name "Net-(Q6-S)") (class "Default")
      (node (ref "Q6") (pin "2") (pinfunction "S_2") (pintype "bidirectional"))
      (node (ref "R184") (pin "2") (pinfunction "2_2") (pintype "passive"))
      (node (ref "R185") (pin "1") (pinfunction "1_1") (pintype "passive"))
    )
    (net (code "158") (name "Net-(Q7-S)") (class "Default")
      (node (ref "Q7") (pin "2") (pinfunction "S_2") (pintype "bidirectional"))
      (node (ref "R195") (pin "2") (pinfunction "2_2") (pintype "passive"))
      (node (ref "R196") (pin "1") (pinfunction "1_1") (pintype "passive"))
    )
    (net (code "159") (name "Net-(SW2A-P)") (class "Default")
      (node (ref "CF1") (pin "3") (pinfunction "3_3") (pintype "passive"))
      (node (ref "SW2") (pin "2") (pinfunction "P_2") (pintype "passive"))
    )
    (net (code "160") (name "Net-(U1X-SW)") (class "Default")
      (node (ref "C124X") (pin "2") (pinfunction "2_2") (pintype "passive"))
      (node (ref "L6X") (pin "2") (pinfunction "2_2") (pintype "passive"))
      (node (ref "U1X") (pin "2") (pinfunction "SW_2") (pintype "output"))
    )
    (net (code "161") (name "Net-(U1X-VBST)") (class "Default")
      (node (ref "C124X") (pin "1") (pinfunction "1_1") (pintype "passive"))
      (node (ref "U1X") (pin "6") (pinfunction "VBST_6") (pintype "passive"))
    )
    (net (code "162") (name "Net-(U1X-VFB)") (class "Default")
      (node (ref "R11X") (pin "1") (pinfunction "1_1") (pintype "passive"))
      (node (ref "R15X") (pin "2") (pinfunction "2_2") (pintype "passive"))
      (node (ref "U1X") (pin "4") (pinfunction "VFB_4") (pintype "input"))
    )
    (net (code "163") (name "Net-(U2-DO)") (class "Default")
      (node (ref "R19") (pin "2") (pinfunction "2_2") (pintype "passive"))
      (node (ref "R21") (pin "1") (pinfunction "1_1") (pintype "passive"))
      (node (ref "U2") (pin "4") (pinfunction "DO_4") (pintype "output"))
    )
    (net (code "164") (name "Net-(U4A-BG_CAP)") (class "Default")
      (node (ref "C88") (pin "1") (pinfunction "1_1") (pintype "passive"))
      (node (ref "U4") (pin "C10") (pinfunction "BG_CAP_C10") (pintype "bidirectional"))
    )
    (net (code "165") (name "Net-(U4A-DSP_LDO_EN)") (class "Default")
      (node (ref "R63") (pin "1") (pinfunction "1_1") (pintype "passive"))
      (node (ref "R64") (pin "2") (pinfunction "2_2") (pintype "passive"))
      (node (ref "U4") (pin "C13") (pinfunction "DSP_LDO_EN_C13") (pintype "input"))
    )
    (net (code "166") (name "Net-(U4A-RSV0)") (class "Default")
      (node (ref "R61") (pin "2") (pinfunction "2_2") (pintype "passive"))
      (node (ref "U4") (pin "A12") (pinfunction "RSV0_A12") (pintype "input"))
    )
    (net (code "167") (name "Net-(U4A-RSV3)") (class "Default")
      (node (ref "R60") (pin "2") (pinfunction "2_2") (pintype "passive"))
      (node (ref "U4") (pin "B12") (pinfunction "RSV3_B12") (pintype "input"))
    )
    (net (code "168") (name "Net-(U4A-RSV6)") (class "Default")
      (node (ref "R62") (pin "2") (pinfunction "2_2") (pintype "passive"))
      (node (ref "U4") (pin "B13") (pinfunction "RSV6_B13") (pintype "input"))
    )
    (net (code "169") (name "Net-(U4B-CLKIN)") (class "Default")
      (node (ref "R34") (pin "2") (pinfunction "2_2") (pintype "passive"))
      (node (ref "R38") (pin "2") (pinfunction "2_2") (pintype "passive"))
      (node (ref "U4") (pin "C1") (pinfunction "CLKIN_C1") (pintype "input"))
    )
    (net (code "170") (name "Net-(U4B-CLKOUT)") (class "Default")
      (node (ref "R117") (pin "2") (pinfunction "2_2") (pintype "passive"))
      (node (ref "TP1") (pin "TP") (pinfunction "TP_TP") (pintype "input"))
      (node (ref "U4") (pin "A2") (pinfunction "CLKOUT_A2") (pintype "output"))
    )
    (net (code "171") (name "Net-(U4B-RTC_XI)") (class "Default")
      (node (ref "C91") (pin "2") (pinfunction "2_2") (pintype "passive"))
      (node (ref "U4") (pin "A7") (pinfunction "RTC_XI_A7") (pintype "input"))
      (node (ref "Y1") (pin "P$2") (pinfunction "2_P$2") (pintype "passive"))
    )
    (net (code "172") (name "Net-(U4B-RTC_XO)") (class "Default")
      (node (ref "C90") (pin "2") (pinfunction "2_2") (pintype "passive"))
      (node (ref "U4") (pin "A6") (pinfunction "RTC_XO_A6") (pintype "bidirectional"))
      (node (ref "Y1") (pin "P$1") (pinfunction "1_P$1") (pintype "passive"))
    )
    (net (code "173") (name "Net-(U4B-USB_R1)") (class "Default")
      (node (ref "R29") (pin "2") (pinfunction "2_2") (pintype "passive"))
      (node (ref "U4") (pin "G14") (pinfunction "USB_R1_G14") (pintype "bidirectional"))
    )
    (net (code "174") (name "Net-(U4B-USB_VSSOSC)") (class "Default")
      (node (ref "R54") (pin "2") (pinfunction "2_2") (pintype "passive"))
      (node (ref "U4") (pin "D12") (pinfunction "USB_VSSOSC_D12") (pintype "power_in"))
    )
    (net (code "175") (name "Net-(U4B-USB_VSSREF)") (class "Default")
      (node (ref "R29") (pin "1") (pinfunction "1_1") (pintype "passive"))
      (node (ref "U4") (pin "F12") (pinfunction "USB_VSSREF_F12") (pintype "power_in"))
    )
    (net (code "176") (name "Net-(U5A-BG_CAP)") (class "Default")
      (node (ref "C88-2") (pin "1") (pinfunction "1_1") (pintype "passive"))
      (node (ref "U5") (pin "C10") (pinfunction "BG_CAP_C10") (pintype "bidirectional"))
    )
    (net (code "177") (name "Net-(U5A-DSP_LDO_EN)") (class "Default")
      (node (ref "R63-2") (pin "1") (pinfunction "1_1") (pintype "passive"))
      (node (ref "R64-2") (pin "2") (pinfunction "2_2") (pintype "passive"))
      (node (ref "U5") (pin "C13") (pinfunction "DSP_LDO_EN_C13") (pintype "input"))
    )
    (net (code "178") (name "Net-(U5A-RSV0)") (class "Default")
      (node (ref "R61-2") (pin "2") (pinfunction "2_2") (pintype "passive"))
      (node (ref "U5") (pin "A12") (pinfunction "RSV0_A12") (pintype "input"))
    )
    (net (code "179") (name "Net-(U5A-RSV3)") (class "Default")
      (node (ref "R60-2") (pin "2") (pinfunction "2_2") (pintype "passive"))
      (node (ref "U5") (pin "B12") (pinfunction "RSV3_B12") (pintype "input"))
    )
    (net (code "180") (name "Net-(U5A-RSV6)") (class "Default")
      (node (ref "R62-2") (pin "2") (pinfunction "2_2") (pintype "passive"))
      (node (ref "U5") (pin "B13") (pinfunction "RSV6_B13") (pintype "input"))
    )
    (net (code "181") (name "Net-(U5B-CLKIN)") (class "Default")
      (node (ref "R34-2") (pin "2") (pinfunction "2_2") (pintype "passive"))
      (node (ref "R38-2") (pin "2") (pinfunction "2_2") (pintype "passive"))
      (node (ref "U5") (pin "C1") (pinfunction "CLKIN_C1") (pintype "input"))
    )
    (net (code "182") (name "Net-(U5B-RTC_XI)") (class "Default")
      (node (ref "C91-2") (pin "2") (pinfunction "2_2") (pintype "passive"))
      (node (ref "U5") (pin "A7") (pinfunction "RTC_XI_A7") (pintype "input"))
      (node (ref "Y1-2") (pin "P$2") (pinfunction "2_P$2") (pintype "passive"))
    )
    (net (code "183") (name "Net-(U5B-RTC_XO)") (class "Default")
      (node (ref "C90-2") (pin "2") (pinfunction "2_2") (pintype "passive"))
      (node (ref "U5") (pin "A6") (pinfunction "RTC_XO_A6") (pintype "bidirectional"))
      (node (ref "Y1-2") (pin "P$1") (pinfunction "1_P$1") (pintype "passive"))
    )
    (net (code "184") (name "Net-(U5B-USB_R1)") (class "Default")
      (node (ref "R29-2") (pin "2") (pinfunction "2_2") (pintype "passive"))
      (node (ref "U5") (pin "G14") (pinfunction "USB_R1_G14") (pintype "bidirectional"))
    )
    (net (code "185") (name "Net-(U5B-USB_VSSOSC)") (class "Default")
      (node (ref "R54-2") (pin "2") (pinfunction "2_2") (pintype "passive"))
      (node (ref "U5") (pin "D12") (pinfunction "USB_VSSOSC_D12") (pintype "power_in"))
    )
    (net (code "186") (name "Net-(U5B-USB_VSSREF)") (class "Default")
      (node (ref "R29-2") (pin "1") (pinfunction "1_1") (pintype "passive"))
      (node (ref "U5") (pin "F12") (pinfunction "USB_VSSREF_F12") (pintype "power_in"))
    )
    (net (code "187") (name "Net-(U6-ACBUS4)") (class "Default")
      (node (ref "R20") (pin "1") (pinfunction "1_1") (pintype "passive"))
      (node (ref "U6") (pin "30") (pinfunction "ACBUS4_30") (pintype "bidirectional"))
    )
    (net (code "188") (name "Net-(U6-ADBUS6)") (class "Default")
      (node (ref "R24") (pin "1") (pinfunction "1_1") (pintype "passive"))
      (node (ref "U6") (pin "23") (pinfunction "ADBUS6_23") (pintype "bidirectional"))
    )
    (net (code "189") (name "Net-(U6-BDBUS0)") (class "Default")
      (node (ref "R35") (pin "1") (pinfunction "1_1") (pintype "passive"))
      (node (ref "U6") (pin "38") (pinfunction "BDBUS0_38") (pintype "output"))
    )
    (net (code "190") (name "Net-(U6-BDBUS1)") (class "Default")
      (node (ref "R32") (pin "1") (pinfunction "1_1") (pintype "passive"))
      (node (ref "U6") (pin "39") (pinfunction "BDBUS1_39") (pintype "input"))
    )
    (net (code "191") (name "Net-(U6-BDBUS2)") (class "Default")
      (node (ref "R30") (pin "1") (pinfunction "1_1") (pintype "passive"))
      (node (ref "U6") (pin "40") (pinfunction "BDBUS2_40") (pintype "output"))
    )
    (net (code "192") (name "Net-(U6-BDBUS3)") (class "Default")
      (node (ref "R27") (pin "1") (pinfunction "1_1") (pintype "passive"))
      (node (ref "U6") (pin "41") (pinfunction "BDBUS3_41") (pintype "input"))
    )
    (net (code "193") (name "Net-(U6-PWEN#)") (class "Default")
      (node (ref "R12") (pin "1") (pinfunction "1_1") (pintype "passive"))
      (node (ref "U6") (pin "60") (pinfunction "PWEN#_60") (pintype "output"))
    )
    (net (code "194") (name "Net-(U6-REF)") (class "Default")
      (node (ref "R28") (pin "2") (pinfunction "2_2") (pintype "passive"))
      (node (ref "U6") (pin "6") (pinfunction "REF_6") (pintype "passive"))
    )
    (net (code "195") (name "Net-(U6-RESET#)") (class "Default")
      (node (ref "R36") (pin "2") (pinfunction "2_2") (pintype "passive"))
      (node (ref "U6") (pin "14") (pinfunction "RESET#_14") (pintype "input"))
    )
    (net (code "196") (name "Net-(U6-XTIN)") (class "Default")
      (node (ref "R23") (pin "2") (pinfunction "2_2") (pintype "passive"))
      (node (ref "U6") (pin "2") (pinfunction "XTIN_2") (pintype "input"))
    )
    (net (code "197") (name "Net-(U8-CLK)") (class "Default")
      (node (ref "R53") (pin "2") (pinfunction "2_2") (pintype "passive"))
      (node (ref "U8") (pin "1") (pinfunction "CLK_1") (pintype "input"))
    )
    (net (code "198") (name "Net-(U9-2-HOLD)") (class "Default")
      (node (ref "R52-2") (pin "1") (pinfunction "1_1") (pintype "passive"))
      (node (ref "U9-2") (pin "1") (pinfunction "HOLD_1") (pintype "bidirectional"))
    )
    (net (code "199") (name "Net-(U9-2-WP)") (class "Default")
      (node (ref "R52-1") (pin "1") (pinfunction "1_1") (pintype "passive"))
      (node (ref "U9-2") (pin "9") (pinfunction "WP_9") (pintype "bidirectional"))
    )
    (net (code "200") (name "Net-(U9-HOLD)") (class "Default")
      (node (ref "R52") (pin "1") (pinfunction "1_1") (pintype "passive"))
      (node (ref "U9") (pin "1") (pinfunction "HOLD_1") (pintype "bidirectional"))
    )
    (net (code "201") (name "Net-(U9-WP)") (class "Default")
      (node (ref "R16") (pin "1") (pinfunction "1_1") (pintype "passive"))
      (node (ref "U9") (pin "9") (pinfunction "WP_9") (pintype "bidirectional"))
    )
    (net (code "202") (name "Net-(U10X-WP)") (class "Default")
      (node (ref "R143X") (pin "1") (pinfunction "1_1") (pintype "passive"))
      (node (ref "U10X") (pin "7") (pinfunction "WP_7") (pintype "input"))
    )
    (net (code "203") (name "Net-(U11X-NR{slash}FB)") (class "Default")
      (node (ref "C95X") (pin "2") (pinfunction "2_2") (pintype "passive"))
      (node (ref "R125X") (pin "1") (pinfunction "1_1") (pintype "passive"))
      (node (ref "R126X") (pin "2") (pinfunction "2_2") (pintype "passive"))
      (node (ref "U11X") (pin "4") (pinfunction "NR/FB_4") (pintype "passive"))
    )
    (net (code "204") (name "Net-(U12X-SW)") (class "Default")
      (node (ref "C125X") (pin "2") (pinfunction "2_2") (pintype "passive"))
      (node (ref "L7X") (pin "2") (pinfunction "2_2") (pintype "passive"))
      (node (ref "U12X") (pin "2") (pinfunction "SW_2") (pintype "output"))
    )
    (net (code "205") (name "Net-(U12X-VBST)") (class "Default")
      (node (ref "C125X") (pin "1") (pinfunction "1_1") (pintype "passive"))
      (node (ref "U12X") (pin "6") (pinfunction "VBST_6") (pintype "passive"))
    )
    (net (code "206") (name "Net-(U12X-VFB)") (class "Default")
      (node (ref "R65X") (pin "1") (pinfunction "1_1") (pintype "passive"))
      (node (ref "R70X") (pin "2") (pinfunction "2_2") (pintype "passive"))
      (node (ref "U12X") (pin "4") (pinfunction "VFB_4") (pintype "input"))
    )
    (net (code "207") (name "Net-(U13A-X)") (class "Default")
      (node (ref "R175") (pin "1") (pinfunction "1_1") (pintype "passive"))
      (node (ref "R198") (pin "1") (pinfunction "1_1") (pintype "passive"))
      (node (ref "U13") (pin "4") (pinfunction "X_4") (pintype "bidirectional"))
    )
    (net (code "208") (name "Net-(U13A-~{A}{slash}B)") (class "Default")
      (node (ref "Q10") (pin "C") (pinfunction "C_C") (pintype "passive"))
      (node (ref "R204") (pin "1") (pinfunction "1_1") (pintype "passive"))
      (node (ref "U13") (pin "6") (pinfunction "~{A}/B_6") (pintype "input"))
    )
    (net (code "209") (name "Net-(U15X-1G)") (class "Default")
      (node (ref "R222X") (pin "2") (pinfunction "2_2") (pintype "passive"))
      (node (ref "U15X") (pin "2") (pinfunction "1G_2") (pintype "input"))
    )
    (net (code "210") (name "Net-(U15X-Y0)") (class "Default")
      (node (ref "R223X") (pin "1") (pinfunction "1_1") (pintype "passive"))
      (node (ref "U15X") (pin "3") (pinfunction "Y0_3") (pintype "output"))
    )
    (net (code "211") (name "Net-(U15X-Y1)") (class "Default")
      (node (ref "R224X") (pin "1") (pinfunction "1_1") (pintype "passive"))
      (node (ref "U15X") (pin "16") (pinfunction "Y1_16") (pintype "output"))
    )
    (net (code "212") (name "Net-(U15X-Y2)") (class "Default")
      (node (ref "R225X") (pin "1") (pinfunction "1_1") (pintype "passive"))
      (node (ref "U15X") (pin "13") (pinfunction "Y2_13") (pintype "output"))
    )
    (net (code "213") (name "Net-(U15X-Y3)") (class "Default")
      (node (ref "R226X") (pin "1") (pinfunction "1_1") (pintype "passive"))
      (node (ref "U15X") (pin "15") (pinfunction "Y3_15") (pintype "output"))
    )
    (net (code "214") (name "Net-(U15X-Y4)") (class "Default")
      (node (ref "R227X") (pin "1") (pinfunction "1_1") (pintype "passive"))
      (node (ref "U15X") (pin "6") (pinfunction "Y4_6") (pintype "output"))
    )
    (net (code "215") (name "Net-(U15X-Y5)") (class "Default")
      (node (ref "R228X") (pin "1") (pinfunction "1_1") (pintype "passive"))
      (node (ref "U15X") (pin "11") (pinfunction "Y5_11") (pintype "output"))
    )
    (net (code "216") (name "Net-(U15X-Y6)") (class "Default")
      (node (ref "R229X") (pin "1") (pinfunction "1_1") (pintype "passive"))
      (node (ref "U15X") (pin "8") (pinfunction "Y6_8") (pintype "output"))
    )
    (net (code "217") (name "Net-(U15X-Y7)") (class "Default")
      (node (ref "R230X") (pin "1") (pinfunction "1_1") (pintype "passive"))
      (node (ref "U15X") (pin "9") (pinfunction "Y7_9") (pintype "output"))
    )
    (net (code "218") (name "Net-(U17-IN2_L)") (class "Default")
      (node (ref "C17") (pin "2") (pinfunction "2_2") (pintype "passive"))
      (node (ref "U17") (pin "15") (pinfunction "IN2_L_15") (pintype "input"))
    )
    (net (code "219") (name "Net-(U17-IN2_R)") (class "Default")
      (node (ref "C16") (pin "2") (pinfunction "2_2") (pintype "passive"))
      (node (ref "U17") (pin "16") (pinfunction "IN2_R_16") (pintype "input"))
    )
    (net (code "220") (name "Net-(U17-LDO_SELECT)") (class "Default")
      (node (ref "R10") (pin "1") (pinfunction "1_1") (pintype "passive"))
      (node (ref "R9") (pin "2") (pinfunction "2_2") (pintype "passive"))
      (node (ref "U17") (pin "30") (pinfunction "LDO_SELECT_30") (pintype "input"))
    )
    (net (code "221") (name "Net-(U17-MICBIAS)") (class "Default")
      (node (ref "R110") (pin "2") (pinfunction "2_2") (pintype "passive"))
      (node (ref "U17") (pin "19") (pinfunction "MICBIAS_19") (pintype "output"))
    )
    (net (code "222") (name "Net-(U17-REF)") (class "Default")
      (node (ref "C117") (pin "1") (pinfunction "1_1") (pintype "passive"))
      (node (ref "C18") (pin "1") (pinfunction "1_1") (pintype "passive"))
      (node (ref "U17") (pin "18") (pinfunction "REF_18") (pintype "output"))
    )
    (net (code "223") (name "Net-(U18-B1)") (class "Default")
      (node (ref "R8") (pin "2") (pinfunction "2_2") (pintype "passive"))
      (node (ref "U18") (pin "18") (pinfunction "B1_18") (pintype "bidirectional"))
    )
    (net (code "224") (name "Net-(U18-B2)") (class "Default")
      (node (ref "R92") (pin "2") (pinfunction "2_2") (pintype "passive"))
      (node (ref "U18") (pin "17") (pinfunction "B2_17") (pintype "bidirectional"))
    )
    (net (code "225") (name "Net-(U18-B3)") (class "Default")
      (node (ref "R93") (pin "2") (pinfunction "2_2") (pintype "passive"))
      (node (ref "U18") (pin "16") (pinfunction "B3_16") (pintype "bidirectional"))
    )
    (net (code "226") (name "Net-(U18-B4)") (class "Default")
      (node (ref "R94") (pin "2") (pinfunction "2_2") (pintype "passive"))
      (node (ref "U18") (pin "15") (pinfunction "B4_15") (pintype "bidirectional"))
    )
    (net (code "227") (name "Net-(U18-B5)") (class "Default")
      (node (ref "R95") (pin "2") (pinfunction "2_2") (pintype "passive"))
      (node (ref "U18") (pin "14") (pinfunction "B5_14") (pintype "bidirectional"))
    )
    (net (code "228") (name "Net-(U19A-+IN)") (class "Default")
      (node (ref "R145") (pin "2") (pinfunction "2_2") (pintype "passive"))
      (node (ref "U19") (pin "3") (pinfunction "+IN_3") (pintype "input"))
    )
    (net (code "229") (name "Net-(U19A--IN)") (class "Default")
      (node (ref "C171") (pin "1") (pinfunction "1_1") (pintype "passive"))
      (node (ref "R144") (pin "2") (pinfunction "2_2") (pintype "passive"))
      (node (ref "R148") (pin "1") (pinfunction "1_1") (pintype "passive"))
      (node (ref "R149") (pin "1") (pinfunction "1_1") (pintype "passive"))
      (node (ref "U19") (pin "2") (pinfunction "-IN_2") (pintype "input"))
    )
    (net (code "230") (name "Net-(U19A-OUT)") (class "Default")
      (node (ref "C171") (pin "2") (pinfunction "2_2") (pintype "passive"))
      (node (ref "C172") (pin "2") (pinfunction "2_2") (pintype "passive"))
      (node (ref "R149") (pin "2") (pinfunction "2_2") (pintype "passive"))
      (node (ref "U19") (pin "1") (pinfunction "OUT_1") (pintype "output"))
      (node (ref "U19") (pin "5") (pinfunction "+IN_5") (pintype "input"))
    )
    (net (code "231") (name "Net-(U19B--IN)") (class "Default")
      (node (ref "C174") (pin "1") (pinfunction "1_1") (pintype "passive"))
      (node (ref "R150") (pin "2") (pinfunction "2_2") (pintype "passive"))
      (node (ref "R151") (pin "1") (pinfunction "1_1") (pintype "passive"))
      (node (ref "U19") (pin "6") (pinfunction "-IN_6") (pintype "input"))
    )
    (net (code "232") (name "Net-(U20A-+IN)") (class "Default")
      (node (ref "C180") (pin "+") (pinfunction "+_+") (pintype "passive"))
      (node (ref "R146") (pin "1") (pinfunction "1_1") (pintype "passive"))
      (node (ref "R147") (pin "2") (pinfunction "2_2") (pintype "passive"))
      (node (ref "U20") (pin "3") (pinfunction "+IN_3") (pintype "input"))
    )
    (net (code "233") (name "Net-(U20B--IN)") (class "Default")
      (node (ref "R172") (pin "1") (pinfunction "1_1") (pintype "passive"))
      (node (ref "R173") (pin "2") (pinfunction "2_2") (pintype "passive"))
      (node (ref "R174") (pin "2") (pinfunction "2_2") (pintype "passive"))
      (node (ref "U20") (pin "6") (pinfunction "-IN_6") (pintype "input"))
    )
    (net (code "234") (name "Net-(U21A-+IN)") (class "Default")
      (node (ref "C175") (pin "2") (pinfunction "2_2") (pintype "passive"))
      (node (ref "R155") (pin "2") (pinfunction "2_2") (pintype "passive"))
      (node (ref "U21") (pin "3") (pinfunction "+IN_3") (pintype "input"))
    )
    (net (code "235") (name "Net-(U21A--IN)") (class "Default")
      (node (ref "C178") (pin "1") (pinfunction "1_1") (pintype "passive"))
      (node (ref "C181") (pin "1") (pinfunction "1_1") (pintype "passive"))
      (node (ref "R158") (pin "1") (pinfunction "1_1") (pintype "passive"))
      (node (ref "R159") (pin "1") (pinfunction "1_1") (pintype "passive"))
      (node (ref "R160") (pin "1") (pinfunction "1_1") (pintype "passive"))
      (node (ref "R161") (pin "2") (pinfunction "2_2") (pintype "passive"))
      (node (ref "U21") (pin "2") (pinfunction "-IN_2") (pintype "input"))
    )
    (net (code "236") (name "Net-(U21B-+IN)") (class "Default")
      (node (ref "R163") (pin "2") (pinfunction "2_2") (pintype "passive"))
      (node (ref "R165") (pin "2") (pinfunction "2_2") (pintype "passive"))
      (node (ref "U21") (pin "5") (pinfunction "+IN_5") (pintype "input"))
    )
    (net (code "237") (name "Net-(U21B--IN)") (class "Default")
      (node (ref "R162") (pin "2") (pinfunction "2_2") (pintype "passive"))
      (node (ref "R164") (pin "1") (pinfunction "1_1") (pintype "passive"))
      (node (ref "U21") (pin "6") (pinfunction "-IN_6") (pintype "input"))
    )
    (net (code "238") (name "Net-(U22A--IN)") (class "Default")
      (node (ref "C189") (pin "1") (pinfunction "1_1") (pintype "passive"))
      (node (ref "R178") (pin "2") (pinfunction "2_2") (pintype "passive"))
      (node (ref "U22") (pin "2") (pinfunction "-IN_2") (pintype "input"))
    )
    (net (code "239") (name "Net-(U22A-OUT)") (class "Default")
      (node (ref "C189") (pin "2") (pinfunction "2_2") (pintype "passive"))
      (node (ref "R176") (pin "2") (pinfunction "2_2") (pintype "passive"))
      (node (ref "R179") (pin "1") (pinfunction "1_1") (pintype "passive"))
      (node (ref "U22") (pin "1") (pinfunction "OUT_1") (pintype "output"))
    )
    (net (code "240") (name "Net-(U22B--IN)") (class "Default")
      (node (ref "C190") (pin "1") (pinfunction "1_1") (pintype "passive"))
      (node (ref "R177") (pin "1") (pinfunction "1_1") (pintype "passive"))
      (node (ref "R179") (pin "2") (pinfunction "2_2") (pintype "passive"))
      (node (ref "R181") (pin "1") (pinfunction "1_1") (pintype "passive"))
      (node (ref "U22") (pin "6") (pinfunction "-IN_6") (pintype "input"))
    )
    (net (code "241") (name "Net-(U22B-OUT)") (class "Default")
      (node (ref "C190") (pin "2") (pinfunction "2_2") (pintype "passive"))
      (node (ref "C193") (pin "2") (pinfunction "2_2") (pintype "passive"))
      (node (ref "C194") (pin "1") (pinfunction "1_1") (pintype "passive"))
      (node (ref "C195") (pin "1") (pinfunction "1_1") (pintype "passive"))
      (node (ref "R177") (pin "2") (pinfunction "2_2") (pintype "passive"))
      (node (ref "U22") (pin "7") (pinfunction "OUT_7") (pintype "output"))
    )
    (net (code "242") (name "Net-(U23A--IN)") (class "Default")
      (node (ref "C197") (pin "1") (pinfunction "1_1") (pintype "passive"))
      (node (ref "R188") (pin "2") (pinfunction "2_2") (pintype "passive"))
      (node (ref "U23") (pin "2") (pinfunction "-IN_2") (pintype "input"))
    )
    (net (code "243") (name "Net-(U23A-OUT)") (class "Default")
      (node (ref "C197") (pin "2") (pinfunction "2_2") (pintype "passive"))
      (node (ref "R187") (pin "2") (pinfunction "2_2") (pintype "passive"))
      (node (ref "R189") (pin "1") (pinfunction "1_1") (pintype "passive"))
      (node (ref "U23") (pin "1") (pinfunction "OUT_1") (pintype "output"))
    )
    (net (code "244") (name "Net-(U23B--IN)") (class "Default")
      (node (ref "C200") (pin "1") (pinfunction "1_1") (pintype "passive"))
      (node (ref "R189") (pin "2") (pinfunction "2_2") (pintype "passive"))
      (node (ref "R191") (pin "1") (pinfunction "1_1") (pintype "passive"))
      (node (ref "R192") (pin "1") (pinfunction "1_1") (pintype "passive"))
      (node (ref "U23") (pin "6") (pinfunction "-IN_6") (pintype "input"))
    )
    (net (code "245") (name "Net-(U23B-OUT)") (class "Default")
      (node (ref "C200") (pin "2") (pinfunction "2_2") (pintype "passive"))
      (node (ref "C201") (pin "2") (pinfunction "2_2") (pintype "passive"))
      (node (ref "C202") (pin "1") (pinfunction "1_1") (pintype "passive"))
      (node (ref "C203") (pin "1") (pinfunction "1_1") (pintype "passive"))
      (node (ref "R191") (pin "2") (pinfunction "2_2") (pintype "passive"))
      (node (ref "U23") (pin "7") (pinfunction "OUT_7") (pintype "output"))
    )
    (net (code "246") (name "Net-(U24A-OUT1)") (class "Default")
      (node (ref "C206") (pin "2") (pinfunction "2_2") (pintype "passive"))
      (node (ref "C208") (pin "1") (pinfunction "1_1") (pintype "passive"))
      (node (ref "R208") (pin "2") (pinfunction "2_2") (pintype "passive"))
      (node (ref "R213") (pin "1") (pinfunction "1_1") (pintype "passive"))
      (node (ref "U24") (pin "1") (pinfunction "OUT1_1") (pintype "output"))
      (node (ref "U24") (pin "6") (pinfunction "-IN2_6") (pintype "input"))
    )
    (net (code "247") (name "Net-(U24B-+IN2)") (class "Default")
      (node (ref "C208") (pin "2") (pinfunction "2_2") (pintype "passive"))
      (node (ref "C212") (pin "1") (pinfunction "1_1") (pintype "passive"))
      (node (ref "R211") (pin "1") (pinfunction "1_1") (pintype "passive"))
      (node (ref "R212") (pin "2") (pinfunction "2_2") (pintype "passive"))
      (node (ref "U24") (pin "5") (pinfunction "+IN2_5") (pintype "input"))
    )
    (net (code "248") (name "Net-(U24B-OUT2)") (class "Default")
      (node (ref "R214") (pin "1") (pinfunction "1_1") (pintype "passive"))
      (node (ref "U24") (pin "7") (pinfunction "OUT2_7") (pintype "output"))
    )
    (net (code "249") (name "OCT1") (class "Default")
      (node (ref "D6") (pin "1") (pinfunction "A_1") (pintype "passive"))
      (node (ref "R160") (pin "2") (pinfunction "2_2") (pintype "passive"))
      (node (ref "R162") (pin "1") (pinfunction "1_1") (pintype "passive"))
    )
    (net (code "250") (name "OCT2") (class "Default")
      (node (ref "D8") (pin "2") (pinfunction "C2_2") (pintype "passive"))
      (node (ref "R158") (pin "2") (pinfunction "2_2") (pintype "passive"))
      (node (ref "R163") (pin "1") (pinfunction "1_1") (pintype "passive"))
    )
    (net (code "251") (name "OCT_OUT") (class "Default")
      (node (ref "J7") (pin "12") (pinfunction "12_12") (pintype "passive"))
      (node (ref "R164") (pin "2") (pinfunction "2_2") (pintype "passive"))
      (node (ref "U21") (pin "7") (pinfunction "OUT_7") (pintype "output"))
    )
    (net (code "252") (name "OD_DRV0") (class "Default")
      (node (ref "Q9") (pin "B") (pinfunction "B_B") (pintype "passive"))
      (node (ref "U5") (pin "M10") (pinfunction "SD0_CMD/I2S0_FS/GP[1]_M10") (pintype "bidirectional"))
    )
    (net (code "253") (name "OD_DRV1") (class "Default")
      (node (ref "Q8") (pin "B") (pinfunction "B_B") (pintype "passive"))
      (node (ref "U5") (pin "J1") (pinfunction "SD0_D0/I2S0_DX/GP[2]_J1") (pintype "bidirectional"))
    )
    (net (code "254") (name "OD_MODE0") (class "Default")
      (node (ref "Q1") (pin "B") (pinfunction "B_B") (pintype "passive"))
      (node (ref "U5") (pin "P6") (pinfunction "SD0_D1/I2S0_RX/GP[3]_P6") (pintype "bidirectional"))
    )
    (net (code "255") (name "OD_MODE1") (class "Default")
      (node (ref "Q4") (pin "B") (pinfunction "B_B") (pintype "passive"))
      (node (ref "U5") (pin "N13") (pinfunction "SD0_D2/GP[4]_N13") (pintype "bidirectional"))
    )
    (net (code "256") (name "PWR_DET") (class "Default")
      (node (ref "R40") (pin "2") (pinfunction "2_2") (pintype "passive"))
      (node (ref "U6") (pin "28") (pinfunction "ACBUS2_28") (pintype "bidirectional"))
      (node (ref "U8") (pin "4") (pinfunction "Q_4") (pintype "output"))
    )
    (net (code "257") (name "PWR_RST") (class "Default")
      (node (ref "R53") (pin "1") (pinfunction "1_1") (pintype "passive"))
      (node (ref "U6") (pin "29") (pinfunction "ACBUS3_29") (pintype "bidirectional"))
    )
    (net (code "258") (name "RTCK") (class "Default")
      (node (ref "R46") (pin "1") (pinfunction "1_1") (pintype "passive"))
      (node (ref "U6") (pin "24") (pinfunction "ADBUS7_24") (pintype "bidirectional"))
    )
    (net (code "259") (name "RTC_CLKOUT") (class "Default")
      (node (ref "TP4") (pin "TP") (pinfunction "TP_TP") (pintype "input"))
      (node (ref "U4") (pin "A3") (pinfunction "RTC_CLKOUT_A3") (pintype "output"))
    )
    (net (code "260") (name "RTC_CLKOUT2") (class "Default")
      (node (ref "TP8X") (pin "TP") (pinfunction "TP_TP") (pintype "input"))
      (node (ref "U5") (pin "A3") (pinfunction "RTC_CLKOUT_A3") (pintype "output"))
    )
    (net (code "261") (name "SD1_CLK") (class "Default")
      (node (ref "J11") (pin "5") (pinfunction "CLK_5") (pintype "input"))
      (node (ref "R6") (pin "1") (pinfunction "1_1") (pintype "passive"))
      (node (ref "U4") (pin "M14") (pinfunction "SD1_CLK/I2S1_CLK/GP[6]_M14") (pintype "bidirectional"))
    )
    (net (code "262") (name "SD1_CMD") (class "Default")
      (node (ref "J11") (pin "3") (pinfunction "CMD_3") (pintype "input"))
      (node (ref "R4") (pin "1") (pinfunction "1_1") (pintype "passive"))
      (node (ref "U4") (pin "L11") (pinfunction "SD1_CMD/I2S1_FS/GP[7]_L11") (pintype "bidirectional"))
    )
    (net (code "263") (name "SD1_DATA0") (class "Default")
      (node (ref "J11") (pin "7") (pinfunction "DAT0_7") (pintype "bidirectional"))
      (node (ref "R7") (pin "1") (pinfunction "1_1") (pintype "passive"))
      (node (ref "U4") (pin "M13") (pinfunction "SD1_D0/2S1_DX/GP[8]_M13") (pintype "bidirectional"))
    )
    (net (code "264") (name "SD1_DATA1") (class "Default")
      (node (ref "J11") (pin "8") (pinfunction "DAT1_8") (pintype "bidirectional"))
      (node (ref "R11") (pin "1") (pinfunction "1_1") (pintype "passive"))
      (node (ref "U4") (pin "P10") (pinfunction "SD1_D1/I2S1_RX/GP[9]_P10") (pintype "bidirectional"))
    )
    (net (code "265") (name "SD1_DATA2") (class "Default")
      (node (ref "J11") (pin "1") (pinfunction "DAT2_1") (pintype "bidirectional"))
      (node (ref "R2") (pin "1") (pinfunction "1_1") (pintype "passive"))
      (node (ref "U4") (pin "L12") (pinfunction "SD1_D2/GP[10]_L12") (pintype "bidirectional"))
    )
    (net (code "266") (name "SD1_DATA3") (class "Default")
      (node (ref "J11") (pin "2") (pinfunction "CD/DAT3_2") (pintype "bidirectional"))
      (node (ref "R3") (pin "1") (pinfunction "1_1") (pintype "passive"))
      (node (ref "U4") (pin "M12") (pinfunction "SD1_D3/GP[11]_M12") (pintype "bidirectional"))
    )
    (net (code "267") (name "SD_CLK") (class "Default")
      (node (ref "J6") (pin "5") (pinfunction "CLK_5") (pintype "input"))
      (node (ref "R101") (pin "1") (pinfunction "1_1") (pintype "passive"))
      (node (ref "U4") (pin "M8") (pinfunction "SD0_CLK/I2S0_CLK/GP[0]_M8") (pintype "bidirectional"))
    )
    (net (code "268") (name "SD_CMD") (class "Default")
      (node (ref "J6") (pin "3") (pinfunction "CMD_3") (pintype "input"))
      (node (ref "R100") (pin "1") (pinfunction "1_1") (pintype "passive"))
      (node (ref "U4") (pin "M10") (pinfunction "SD0_CMD/I2S0_FS/GP[1]_M10") (pintype "bidirectional"))
    )
    (net (code "269") (name "SD_DATA0") (class "Default")
      (node (ref "J6") (pin "7") (pinfunction "DAT0_7") (pintype "bidirectional"))
      (node (ref "R102") (pin "1") (pinfunction "1_1") (pintype "passive"))
      (node (ref "U4") (pin "J1") (pinfunction "SD0_D0/I2S0_DX/GP[2]_J1") (pintype "bidirectional"))
    )
    (net (code "270") (name "SD_DATA1") (class "Default")
      (node (ref "J6") (pin "8") (pinfunction "DAT1_8") (pintype "bidirectional"))
      (node (ref "R103") (pin "1") (pinfunction "1_1") (pintype "passive"))
      (node (ref "U4") (pin "P6") (pinfunction "SD0_D1/I2S0_RX/GP[3]_P6") (pintype "bidirectional"))
    )
    (net (code "271") (name "SD_DATA2") (class "Default")
      (node (ref "J6") (pin "1") (pinfunction "DAT2_1") (pintype "bidirectional"))
      (node (ref "R98") (pin "1") (pinfunction "1_1") (pintype "passive"))
      (node (ref "U4") (pin "N13") (pinfunction "SD0_D2/GP[4]_N13") (pintype "bidirectional"))
    )
    (net (code "272") (name "SD_DATA3") (class "Default")
      (node (ref "J6") (pin "2") (pinfunction "CD/DAT3_2") (pintype "bidirectional"))
      (node (ref "R99") (pin "1") (pinfunction "1_1") (pintype "passive"))
      (node (ref "U4") (pin "P7") (pinfunction "SD0_D3/GP[5]_P7") (pintype "bidirectional"))
    )
    (net (code "273") (name "SPI2_CLK") (class "Default")
      (node (ref "J5") (pin "11") (pinfunction "11_11") (pintype "passive"))
      (node (ref "R72-2") (pin "1") (pinfunction "1_1") (pintype "passive"))
      (node (ref "U5") (pin "L3") (pinfunction "LCD_EN_RDB/SPI_CLK_L3") (pintype "output"))
      (node (ref "U9-2") (pin "16") (pinfunction "CLK_16") (pintype "input"))
    )
    (net (code "274") (name "SPI2_CS0") (class "Default")
      (node (ref "R50-2") (pin "1") (pinfunction "1_1") (pintype "passive"))
      (node (ref "U5") (pin "L1") (pinfunction "LCD_CS0_E0/SPI_CS0_L1") (pintype "bidirectional"))
      (node (ref "U9-2") (pin "7") (pinfunction "CS_7") (pintype "input"))
    )
    (net (code "275") (name "SPI2_CS1") (class "Default")
      (node (ref "J5") (pin "17") (pinfunction "17_17") (pintype "passive"))
      (node (ref "U5") (pin "M2") (pinfunction "LCD_CS1_E1/SPI_CS1_M2") (pintype "bidirectional"))
    )
    (net (code "276") (name "SPI2_CS2") (class "Default")
      (node (ref "TP26X") (pin "TP") (pinfunction "TP_TP") (pintype "input"))
      (node (ref "U5") (pin "N2") (pinfunction "LCD_RW_WRB/SPI_CS2_N2") (pintype "bidirectional"))
    )
    (net (code "277") (name "SPI2_CS3") (class "Default")
      (node (ref "TP27X") (pin "TP") (pinfunction "TP_TP") (pintype "input"))
      (node (ref "U5") (pin "M5") (pinfunction "LCD_RS/SPI_CS3_M5") (pintype "bidirectional"))
    )
    (net (code "278") (name "SPI2_RX") (class "Default")
      (node (ref "R51-2") (pin "1") (pinfunction "1_1") (pintype "passive"))
      (node (ref "U5") (pin "N4") (pinfunction "LCD_D[0]/SPI_RX_N4") (pintype "tri_state"))
      (node (ref "U9-2") (pin "8") (pinfunction "DO_8") (pintype "bidirectional"))
    )
    (net (code "279") (name "SPI2_TX") (class "Default")
      (node (ref "J5") (pin "9") (pinfunction "9_9") (pintype "passive"))
      (node (ref "R73-2") (pin "1") (pinfunction "1_1") (pintype "passive"))
      (node (ref "U5") (pin "K1") (pinfunction "LCD_D[1]/SPI_TX_K1") (pintype "tri_state"))
      (node (ref "U9-2") (pin "15") (pinfunction "DI_15") (pintype "bidirectional"))
    )
    (net (code "280") (name "SPI_CLK") (class "Default")
      (node (ref "R72") (pin "1") (pinfunction "1_1") (pintype "passive"))
      (node (ref "U4") (pin "L3") (pinfunction "LCD_EN_RDB/SPI_CLK_L3") (pintype "output"))
      (node (ref "U9") (pin "16") (pinfunction "CLK_16") (pintype "input"))
    )
    (net (code "281") (name "SPI_CS0") (class "Default")
      (node (ref "R50") (pin "1") (pinfunction "1_1") (pintype "passive"))
      (node (ref "U4") (pin "L1") (pinfunction "LCD_CS0_E0/SPI_CS0_L1") (pintype "bidirectional"))
      (node (ref "U9") (pin "7") (pinfunction "CS_7") (pintype "input"))
    )
    (net (code "282") (name "SPI_CS1") (class "Default")
      (node (ref "TP19") (pin "TP") (pinfunction "TP_TP") (pintype "input"))
      (node (ref "U4") (pin "M2") (pinfunction "LCD_CS1_E1/SPI_CS1_M2") (pintype "bidirectional"))
    )
    (net (code "283") (name "SPI_CS2") (class "Default")
      (node (ref "TP20") (pin "TP") (pinfunction "TP_TP") (pintype "input"))
      (node (ref "U4") (pin "N2") (pinfunction "LCD_RW_WRB/SPI_CS2_N2") (pintype "bidirectional"))
    )
    (net (code "284") (name "SPI_CS3") (class "Default")
      (node (ref "TP21") (pin "TP") (pinfunction "TP_TP") (pintype "input"))
      (node (ref "U4") (pin "M5") (pinfunction "LCD_RS/SPI_CS3_M5") (pintype "bidirectional"))
    )
    (net (code "285") (name "SPI_RX") (class "Default")
      (node (ref "R51") (pin "1") (pinfunction "1_1") (pintype "passive"))
      (node (ref "U4") (pin "N4") (pinfunction "LCD_D[0]/SPI_RX_N4") (pintype "tri_state"))
      (node (ref "U9") (pin "8") (pinfunction "DO_8") (pintype "bidirectional"))
    )
    (net (code "286") (name "SPI_TX") (class "Default")
      (node (ref "R73") (pin "1") (pinfunction "1_1") (pintype "passive"))
      (node (ref "U4") (pin "K1") (pinfunction "LCD_D[1]/SPI_TX_K1") (pintype "tri_state"))
      (node (ref "U9") (pin "15") (pinfunction "DI_15") (pintype "bidirectional"))
    )
    (net (code "287") (name "SRST_N_OUT") (class "Default")
      (node (ref "R45") (pin "1") (pinfunction "1_1") (pintype "passive"))
      (node (ref "U6") (pin "26") (pinfunction "ACBUS0_26") (pintype "bidirectional"))
    )
    (net (code "288") (name "SRTST_N_IN") (class "Default")
      (node (ref "R44") (pin "1") (pinfunction "1_1") (pintype "passive"))
      (node (ref "R45") (pin "2") (pinfunction "2_2") (pintype "passive"))
      (node (ref "U6") (pin "27") (pinfunction "ACBUS1_27") (pintype "bidirectional"))
    )
    (net (code "289") (name "SW_UP") (class "Default")
      (node (ref "JP2") (pin "2") (pinfunction "2_2") (pintype "passive"))
      (node (ref "R4X") (pin "1") (pinfunction "1_1") (pintype "passive"))
      (node (ref "SW1") (pin "1") (pinfunction "O_1") (pintype "passive"))
    )
    (net (code "290") (name "TARGET_PWR_GOOD") (class "Default")
      (node (ref "J5") (pin "15") (pinfunction "15_15") (pintype "passive"))
      (node (ref "R3X") (pin "1") (pinfunction "1_1") (pintype "passive"))
      (node (ref "R40") (pin "1") (pinfunction "1_1") (pintype "passive"))
      (node (ref "R42") (pin "1") (pinfunction "1_1") (pintype "passive"))
      (node (ref "U18") (pin "2") (pinfunction "A1_2") (pintype "bidirectional"))
      (node (ref "U3X") (pin "3") (pinfunction "~{RESET}_3") (pintype "output"))
      (node (ref "U4") (pin "D2") (pinfunction "RESETN_D2") (pintype "input"))
      (node (ref "U5") (pin "D2") (pinfunction "RESETN_D2") (pintype "input"))
      (node (ref "U8") (pin "6") (pinfunction "~{CLR}_6") (pintype "input"))
    )
    (net (code "291") (name "TCK") (class "Default")
      (node (ref "R39") (pin "2") (pinfunction "2_2") (pintype "passive"))
      (node (ref "U4") (pin "N3") (pinfunction "TCK_N3") (pintype "input"))
      (node (ref "U5") (pin "N3") (pinfunction "TCK_N3") (pintype "input"))
    )
    (net (code "292") (name "TCK_R") (class "Default")
      (node (ref "R39") (pin "1") (pinfunction "1_1") (pintype "passive"))
      (node (ref "R46") (pin "2") (pinfunction "2_2") (pintype "passive"))
      (node (ref "U6") (pin "16") (pinfunction "ADBUS0_16") (pintype "bidirectional"))
    )
    (net (code "293") (name "TDI") (class "Default")
      (node (ref "R49") (pin "2") (pinfunction "2_2") (pintype "passive"))
      (node (ref "U4") (pin "K2") (pinfunction "TDI_K2") (pintype "input"))
    )
    (net (code "294") (name "TDI_R") (class "Default")
      (node (ref "R49") (pin "1") (pinfunction "1_1") (pintype "passive"))
      (node (ref "U6") (pin "17") (pinfunction "ADBUS1_17") (pintype "bidirectional"))
    )
    (net (code "295") (name "TDO") (class "Default")
      (node (ref "R48") (pin "2") (pinfunction "2_2") (pintype "passive"))
      (node (ref "R66X") (pin "1") (pinfunction "1_1") (pintype "passive"))
    )
    (net (code "296") (name "TDO1") (class "Default")
      (node (ref "U4") (pin "N1") (pinfunction "TDO_N1") (pintype "output"))
      (node (ref "U5") (pin "K2") (pinfunction "TDI_K2") (pintype "input"))
    )
    (net (code "297") (name "TDO2") (class "Default")
      (node (ref "R66X") (pin "2") (pinfunction "2_2") (pintype "passive"))
      (node (ref "U5") (pin "N1") (pinfunction "TDO_N1") (pintype "output"))
    )
    (net (code "298") (name "TDO_R") (class "Default")
      (node (ref "R48") (pin "1") (pinfunction "1_1") (pintype "passive"))
      (node (ref "U6") (pin "18") (pinfunction "ADBUS2_18") (pintype "bidirectional"))
    )
    (net (code "299") (name "TMS") (class "Default")
      (node (ref "R47") (pin "2") (pinfunction "2_2") (pintype "passive"))
      (node (ref "U4") (pin "N6") (pinfunction "TMS_N6") (pintype "input"))
      (node (ref "U5") (pin "N6") (pinfunction "TMS_N6") (pintype "input"))
    )
    (net (code "300") (name "TMS_R") (class "Default")
      (node (ref "R47") (pin "1") (pinfunction "1_1") (pintype "passive"))
      (node (ref "U6") (pin "19") (pinfunction "ADBUS3_19") (pintype "bidirectional"))
    )
    (net (code "301") (name "TP1_CLK12M") (class "Default")
      (node (ref "R223X") (pin "2") (pinfunction "2_2") (pintype "passive"))
      (node (ref "TP7X") (pin "TP") (pinfunction "TP_TP") (pintype "input"))
    )
    (net (code "302") (name "TP2_CLK12M") (class "Default")
      (node (ref "R224X") (pin "2") (pinfunction "2_2") (pintype "passive"))
      (node (ref "TP6X") (pin "TP") (pinfunction "TP_TP") (pintype "input"))
    )
    (net (code "303") (name "TRSTN") (class "Default")
      (node (ref "R57") (pin "1") (pinfunction "1_1") (pintype "passive"))
      (node (ref "R58") (pin "2") (pinfunction "2_2") (pintype "passive"))
      (node (ref "U4") (pin "P4") (pinfunction "TRST_P4") (pintype "input"))
      (node (ref "U5") (pin "P4") (pinfunction "TRST_P4") (pintype "input"))
    )
    (net (code "304") (name "TRSTN_R") (class "Default")
      (node (ref "R58") (pin "1") (pinfunction "1_1") (pintype "passive"))
      (node (ref "U6") (pin "21") (pinfunction "ADBUS4_21") (pintype "bidirectional"))
    )
    (net (code "305") (name "TUNER") (class "Default")
      (node (ref "C214") (pin "1") (pinfunction "1_1") (pintype "passive"))
      (node (ref "R214") (pin "2") (pinfunction "2_2") (pintype "passive"))
      (node (ref "R215") (pin "2") (pinfunction "2_2") (pintype "passive"))
      (node (ref "U5") (pin "A8") (pinfunction "GPAIN0_A8") (pintype "bidirectional"))
    )
    (net (code "306") (name "UART2_CTS") (class "Default")
      (node (ref "TP23X") (pin "TP") (pinfunction "TP_TP") (pintype "input"))
      (node (ref "U5") (pin "P12") (pinfunction "LCD_D[13]/UART_CTS/GP[29]/I2S3_FS_P12") (pintype "bidirectional"))
    )
    (net (code "307") (name "UART2_RX") (class "Default")
      (node (ref "TP24X") (pin "TP") (pinfunction "TP_TP") (pintype "input"))
      (node (ref "U5") (pin "P13") (pinfunction "LCD_D[14]/UART_RXD/GP[30]/I2S3_RX_P13") (pintype "bidirectional"))
    )
    (net (code "308") (name "UART2_TX") (class "Default")
      (node (ref "TP25X") (pin "TP") (pinfunction "TP_TP") (pintype "input"))
      (node (ref "U5") (pin "M11") (pinfunction "LCD_D[15]/UART_TXD/GP[31]/I2S3_DX_M11") (pintype "bidirectional"))
    )
    (net (code "309") (name "UART_CTS") (class "Default")
      (node (ref "R30") (pin "2") (pinfunction "2_2") (pintype "passive"))
      (node (ref "U4") (pin "P12") (pinfunction "LCD_D[13]/UART_CTS/GP[29]/I2S3_FS_P12") (pintype "bidirectional"))
    )
    (net (code "310") (name "UART_RTS") (class "Default")
      (node (ref "R27") (pin "2") (pinfunction "2_2") (pintype "passive"))
      (node (ref "U4") (pin "N12") (pinfunction "LCD_D[12]/UART_RTS/GP[28]/I2S3_CLK_N12") (pintype "bidirectional"))
    )
    (net (code "311") (name "UART_RX") (class "Default")
      (node (ref "R35") (pin "2") (pinfunction "2_2") (pintype "passive"))
      (node (ref "U4") (pin "P13") (pinfunction "LCD_D[14]/UART_RXD/GP[30]/I2S3_RX_P13") (pintype "bidirectional"))
    )
    (net (code "312") (name "UART_TX") (class "Default")
      (node (ref "R32") (pin "2") (pinfunction "2_2") (pintype "passive"))
      (node (ref "U4") (pin "M11") (pinfunction "LCD_D[15]/UART_TXD/GP[31]/I2S3_DX_M11") (pintype "bidirectional"))
    )
    (net (code "313") (name "USB1_LDO") (class "Default")
      (node (ref "R122") (pin "2") (pinfunction "2_2") (pintype "passive"))
      (node (ref "U4") (pin "D13") (pinfunction "USB_LDOO_D13") (pintype "power_in"))
    )
    (net (code "314") (name "USB1_VDD1P3") (class "Default")
      (node (ref "C5") (pin "1") (pinfunction "1_1") (pintype "passive"))
      (node (ref "C60") (pin "1") (pinfunction "1_1") (pintype "passive"))
      (node (ref "C74") (pin "1") (pinfunction "1_1") (pintype "passive"))
      (node (ref "FB6") (pin "2") (pinfunction "2_2") (pintype "passive"))
      (node (ref "U4") (pin "E12") (pinfunction "USB_VDD1P3_E12") (pintype "power_in"))
      (node (ref "U4") (pin "F14") (pinfunction "USB_VDD1P3_F14") (pintype "power_in"))
      (node (ref "U4") (pin "K13") (pinfunction "USB_VDD1P3_K13") (pintype "power_in"))
    )
    (net (code "315") (name "USB1_VDDA1P3") (class "Default")
      (node (ref "C2") (pin "1") (pinfunction "1_1") (pintype "passive"))
      (node (ref "C43") (pin "1") (pinfunction "1_1") (pintype "passive"))
      (node (ref "C49") (pin "1") (pinfunction "1_1") (pintype "passive"))
      (node (ref "FB4") (pin "2") (pinfunction "2_2") (pintype "passive"))
      (node (ref "U4") (pin "H12") (pinfunction "USB_VDDA1P3_H12") (pintype "power_in"))
    )
    (net (code "316") (name "USB1_VDDA3P3") (class "Default")
      (node (ref "C4") (pin "1") (pinfunction "1_1") (pintype "passive"))
      (node (ref "C56") (pin "1") (pinfunction "1_1") (pintype "passive"))
      (node (ref "C63") (pin "1") (pinfunction "1_1") (pintype "passive"))
      (node (ref "FB5") (pin "2") (pinfunction "2_2") (pintype "passive"))
      (node (ref "U4") (pin "G12") (pinfunction "USB_VDDA3P3_G12") (pintype "power_in"))
    )
    (net (code "317") (name "USB1_VDDOSC") (class "Default")
      (node (ref "C6") (pin "1") (pinfunction "1_1") (pintype "passive"))
      (node (ref "C66") (pin "1") (pinfunction "1_1") (pintype "passive"))
      (node (ref "C77") (pin "1") (pinfunction "1_1") (pintype "passive"))
      (node (ref "FB7") (pin "2") (pinfunction "2_2") (pintype "passive"))
      (node (ref "U4") (pin "E13") (pinfunction "USB_VDDOSC_E13") (pintype "power_in"))
    )
    (net (code "318") (name "USB1_VDDPLL") (class "Default")
      (node (ref "C3") (pin "1") (pinfunction "1_1") (pintype "passive"))
      (node (ref "C50") (pin "1") (pinfunction "1_1") (pintype "passive"))
      (node (ref "C57") (pin "1") (pinfunction "1_1") (pintype "passive"))
      (node (ref "L3") (pin "2") (pinfunction "2_2") (pintype "passive"))
      (node (ref "U4") (pin "G13") (pinfunction "USB_VDDPLL_G13") (pintype "power_in"))
    )
    (net (code "319") (name "USB2_CLK_12MHZ") (class "Default")
      (node (ref "R225X") (pin "2") (pinfunction "2_2") (pintype "passive"))
      (node (ref "R55-2") (pin "1") (pinfunction "1_1") (pintype "passive"))
    )
    (net (code "320") (name "USB2_D_N") (class "Default")
      (node (ref "J1-2") (pin "D-") (pinfunction "D-_D-") (pintype "bidirectional"))
      (node (ref "U5") (pin "J14") (pinfunction "USB_DM_J14") (pintype "bidirectional"))
    )
    (net (code "321") (name "USB2_D_P") (class "Default")
      (node (ref "J1-2") (pin "D+") (pinfunction "D+_D+") (pintype "bidirectional"))
      (node (ref "U5") (pin "H14") (pinfunction "USB_DP_H14") (pintype "bidirectional"))
    )
    (net (code "322") (name "USB2_LDO") (class "Default")
      (node (ref "R122-2") (pin "2") (pinfunction "2_2") (pintype "passive"))
      (node (ref "U5") (pin "D13") (pinfunction "USB_LDOO_D13") (pintype "power_in"))
    )
    (net (code "323") (name "USB2_VDD1P3") (class "Default")
      (node (ref "C5-2") (pin "1") (pinfunction "1_1") (pintype "passive"))
      (node (ref "C60-2") (pin "1") (pinfunction "1_1") (pintype "passive"))
      (node (ref "C74-2") (pin "1") (pinfunction "1_1") (pintype "passive"))
      (node (ref "FB6-2") (pin "2") (pinfunction "2_2") (pintype "passive"))
      (node (ref "U5") (pin "E12") (pinfunction "USB_VDD1P3_E12") (pintype "power_in"))
      (node (ref "U5") (pin "F14") (pinfunction "USB_VDD1P3_F14") (pintype "power_in"))
      (node (ref "U5") (pin "K13") (pinfunction "USB_VDD1P3_K13") (pintype "power_in"))
    )
    (net (code "324") (name "USB2_VDDA1P3") (class "Default")
      (node (ref "C2-2") (pin "1") (pinfunction "1_1") (pintype "passive"))
      (node (ref "C43-2") (pin "1") (pinfunction "1_1") (pintype "passive"))
      (node (ref "C49-2") (pin "1") (pinfunction "1_1") (pintype "passive"))
      (node (ref "FB4-2") (pin "2") (pinfunction "2_2") (pintype "passive"))
      (node (ref "U5") (pin "H12") (pinfunction "USB_VDDA1P3_H12") (pintype "power_in"))
    )
    (net (code "325") (name "USB2_VDDA3P3") (class "Default")
      (node (ref "C4-2") (pin "1") (pinfunction "1_1") (pintype "passive"))
      (node (ref "C56-2") (pin "1") (pinfunction "1_1") (pintype "passive"))
      (node (ref "C63-2") (pin "1") (pinfunction "1_1") (pintype "passive"))
      (node (ref "FB5-2") (pin "2") (pinfunction "2_2") (pintype "passive"))
      (node (ref "U5") (pin "G12") (pinfunction "USB_VDDA3P3_G12") (pintype "power_in"))
    )
    (net (code "326") (name "USB2_VDDOSC") (class "Default")
      (node (ref "C6-2") (pin "1") (pinfunction "1_1") (pintype "passive"))
      (node (ref "C66-2") (pin "1") (pinfunction "1_1") (pintype "passive"))
      (node (ref "C77-2") (pin "1") (pinfunction "1_1") (pintype "passive"))
      (node (ref "FB7-2") (pin "2") (pinfunction "2_2") (pintype "passive"))
      (node (ref "U5") (pin "E13") (pinfunction "USB_VDDOSC_E13") (pintype "power_in"))
    )
    (net (code "327") (name "USB2_VDDPLL") (class "Default")
      (node (ref "C3-2") (pin "1") (pinfunction "1_1") (pintype "passive"))
      (node (ref "C50-2") (pin "1") (pinfunction "1_1") (pintype "passive"))
      (node (ref "C57-2") (pin "1") (pinfunction "1_1") (pintype "passive"))
      (node (ref "L3-2") (pin "2") (pinfunction "2_2") (pintype "passive"))
      (node (ref "U5") (pin "G13") (pinfunction "USB_VDDPLL_G13") (pintype "power_in"))
    )
    (net (code "328") (name "USB_CLK_12MHZ") (class "Default")
      (node (ref "R230X") (pin "2") (pinfunction "2_2") (pintype "passive"))
      (node (ref "R55") (pin "1") (pinfunction "1_1") (pintype "passive"))
    )
    (net (code "329") (name "USB_D_N") (class "Default")
      (node (ref "J1") (pin "D-") (pinfunction "D-_D-") (pintype "bidirectional"))
      (node (ref "U4") (pin "J14") (pinfunction "USB_DM_J14") (pintype "bidirectional"))
    )
    (net (code "330") (name "USB_D_P") (class "Default")
      (node (ref "J1") (pin "D+") (pinfunction "D+_D+") (pintype "bidirectional"))
      (node (ref "U4") (pin "H14") (pinfunction "USB_DP_H14") (pintype "bidirectional"))
    )
    (net (code "331") (name "USB_LDO_OUT") (class "Default")
      (node (ref "FB4") (pin "1") (pinfunction "1_1") (pintype "passive"))
      (node (ref "FB6") (pin "1") (pinfunction "1_1") (pintype "passive"))
      (node (ref "R121") (pin "2") (pinfunction "2_2") (pintype "passive"))
      (node (ref "R122") (pin "1") (pinfunction "1_1") (pintype "passive"))
    )
    (net (code "332") (name "USB_LDO_OUT2") (class "Default")
      (node (ref "FB4-2") (pin "1") (pinfunction "1_1") (pintype "passive"))
      (node (ref "FB6-2") (pin "1") (pinfunction "1_1") (pintype "passive"))
      (node (ref "R121-2") (pin "2") (pinfunction "2_2") (pintype "passive"))
      (node (ref "R122-2") (pin "1") (pinfunction "1_1") (pintype "passive"))
    )
    (net (code "333") (name "USB_N") (class "Default")
      (node (ref "J2") (pin "D-") (pinfunction "D-_D-") (pintype "bidirectional"))
      (node (ref "U6") (pin "7") (pinfunction "USBDM_7") (pintype "bidirectional"))
      (node (ref "U7") (pin "5") (pinfunction "IO2_5") (pintype "bidirectional"))
    )
    (net (code "334") (name "USB_P") (class "Default")
      (node (ref "J2") (pin "D+") (pinfunction "D+_D+") (pintype "bidirectional"))
      (node (ref "U6") (pin "8") (pinfunction "USBDP_8") (pintype "bidirectional"))
      (node (ref "U7") (pin "3") (pinfunction "IO1_3") (pintype "bidirectional"))
    )
    (net (code "335") (name "USB_XI") (class "Default")
      (node (ref "R55") (pin "2") (pinfunction "2_2") (pintype "passive"))
      (node (ref "R56") (pin "2") (pinfunction "2_2") (pintype "passive"))
      (node (ref "U4") (pin "E14") (pinfunction "USB_MXI_E14") (pintype "input"))
    )
    (net (code "336") (name "USB_XI2") (class "Default")
      (node (ref "R55-2") (pin "2") (pinfunction "2_2") (pintype "passive"))
      (node (ref "R56-2") (pin "2") (pinfunction "2_2") (pintype "passive"))
      (node (ref "U5") (pin "E14") (pinfunction "USB_MXI_E14") (pintype "input"))
    )
    (net (code "337") (name "V1.65") (class "Default")
      (node (ref "R145") (pin "1") (pinfunction "1_1") (pintype "passive"))
      (node (ref "R171") (pin "1") (pinfunction "1_1") (pintype "passive"))
      (node (ref "R198") (pin "2") (pinfunction "2_2") (pintype "passive"))
      (node (ref "R199") (pin "2") (pinfunction "2_2") (pintype "passive"))
      (node (ref "R200") (pin "2") (pinfunction "2_2") (pintype "passive"))
      (node (ref "U20") (pin "1") (pinfunction "OUT_1") (pintype "output"))
      (node (ref "U20") (pin "2") (pinfunction "-IN_2") (pintype "input"))
      (node (ref "U20") (pin "5") (pinfunction "+IN_5") (pintype "input"))
      (node (ref "U22") (pin "3") (pinfunction "+IN_3") (pintype "input"))
      (node (ref "U22") (pin "5") (pinfunction "+IN_5") (pintype "input"))
      (node (ref "U23") (pin "3") (pinfunction "+IN_3") (pintype "input"))
      (node (ref "U23") (pin "5") (pinfunction "+IN_5") (pintype "input"))
    )
    (net (code "338") (name "V3.3A") (class "Default")
      (node (ref "C179") (pin "+") (pinfunction "+_+") (pintype "passive"))
      (node (ref "C185") (pin "1") (pinfunction "1_1") (pintype "passive"))
      (node (ref "C204") (pin "1") (pinfunction "1_1") (pintype "passive"))
      (node (ref "C209") (pin "1") (pinfunction "1_1") (pintype "passive"))
      (node (ref "C220") (pin "1") (pinfunction "1_1") (pintype "passive"))
      (node (ref "C221") (pin "1") (pinfunction "1_1") (pintype "passive"))
      (node (ref "C222") (pin "1") (pinfunction "1_1") (pintype "passive"))
      (node (ref "C223") (pin "1") (pinfunction "1_1") (pintype "passive"))
      (node (ref "C224") (pin "1") (pinfunction "1_1") (pintype "passive"))
      (node (ref "D9") (pin "C") (pinfunction "C_C") (pintype "passive"))
      (node (ref "FB3") (pin "2") (pinfunction "2_2") (pintype "passive"))
      (node (ref "IC2") (pin "14") (pinfunction "VDD_14") (pintype "power_in"))
      (node (ref "Q3") (pin "1") (pinfunction "D_1") (pintype "passive"))
      (node (ref "R108") (pin "2") (pinfunction "2_2") (pintype "passive"))
      (node (ref "R146") (pin "2") (pinfunction "2_2") (pintype "passive"))
      (node (ref "R168") (pin "2") (pinfunction "2_2") (pintype "passive"))
      (node (ref "R201") (pin "2") (pinfunction "2_2") (pintype "passive"))
      (node (ref "R202") (pin "2") (pinfunction "2_2") (pintype "passive"))
      (node (ref "R203") (pin "2") (pinfunction "2_2") (pintype "passive"))
      (node (ref "R204") (pin "2") (pinfunction "2_2") (pintype "passive"))
      (node (ref "R207") (pin "2") (pinfunction "2_2") (pintype "passive"))
      (node (ref "R211") (pin "2") (pinfunction "2_2") (pintype "passive"))
      (node (ref "U13") (pin "5") (pinfunction "VCC_5") (pintype "power_in"))
      (node (ref "U19") (pin "8") (pinfunction "V+_8") (pintype "power_in"))
      (node (ref "U20") (pin "8") (pinfunction "V+_8") (pintype "power_in"))
      (node (ref "U21") (pin "8") (pinfunction "V+_8") (pintype "power_in"))
      (node (ref "U22") (pin "8") (pinfunction "V+_8") (pintype "power_in"))
      (node (ref "U23") (pin "8") (pinfunction "V+_8") (pintype "power_in"))
      (node (ref "U24") (pin "8") (pinfunction "+V_8") (pintype "power_in"))
    )
    (net (code "339") (name "VBUS2_C5535") (class "Default")
      (node (ref "C24-2") (pin "1") (pinfunction "1_1") (pintype "passive"))
      (node (ref "C25-2") (pin "1") (pinfunction "1_1") (pintype "passive"))
      (node (ref "D2-2") (pin "C") (pinfunction "C_C") (pintype "passive"))
      (node (ref "D5") (pin "A") (pinfunction "A_A") (pintype "passive"))
      (node (ref "J1-2") (pin "VBUS") (pinfunction "VBUS_VBUS") (pintype "bidirectional"))
      (node (ref "R18-2") (pin "2") (pinfunction "2_2") (pintype "passive"))
      (node (ref "U5") (pin "L14") (pinfunction "USB_VBUS_L14") (pintype "bidirectional"))
    )
    (net (code "340") (name "VBUS_C5535") (class "Default")
      (node (ref "C24") (pin "1") (pinfunction "1_1") (pintype "passive"))
      (node (ref "C25") (pin "1") (pinfunction "1_1") (pintype "passive"))
      (node (ref "D2") (pin "C") (pinfunction "C_C") (pintype "passive"))
      (node (ref "D3") (pin "A") (pinfunction "A_A") (pintype "passive"))
      (node (ref "J1") (pin "VBUS") (pinfunction "VBUS_VBUS") (pintype "bidirectional"))
      (node (ref "R18") (pin "2") (pinfunction "2_2") (pintype "passive"))
      (node (ref "U4") (pin "L14") (pinfunction "USB_VBUS_L14") (pintype "bidirectional"))
    )
    (net (code "341") (name "VCCUSB") (class "Default")
      (node (ref "C7") (pin "1") (pinfunction "1_1") (pintype "passive"))
      (node (ref "C92") (pin "1") (pinfunction "1_1") (pintype "passive"))
      (node (ref "D4") (pin "A") (pinfunction "A_A") (pintype "passive"))
      (node (ref "L1") (pin "2") (pinfunction "2_2") (pintype "passive"))
    )
    (net (code "342") (name "VCC_1V3") (class "Default")
      (node (ref "C26X") (pin "1") (pinfunction "1_1") (pintype "passive"))
      (node (ref "C83") (pin "1") (pinfunction "1_1") (pintype "passive"))
      (node (ref "C83-2") (pin "1") (pinfunction "1_1") (pintype "passive"))
      (node (ref "C84") (pin "1") (pinfunction "1_1") (pintype "passive"))
      (node (ref "C84-2") (pin "1") (pinfunction "1_1") (pintype "passive"))
      (node (ref "C95X") (pin "1") (pinfunction "1_1") (pintype "passive"))
      (node (ref "R121") (pin "1") (pinfunction "1_1") (pintype "passive"))
      (node (ref "R121-2") (pin "1") (pinfunction "1_1") (pintype "passive"))
      (node (ref "R125X") (pin "2") (pinfunction "2_2") (pintype "passive"))
      (node (ref "U11X") (pin "5") (pinfunction "OUT_5") (pintype "power_in"))
      (node (ref "U3X") (pin "5") (pinfunction "SENSE_5") (pintype "input"))
      (node (ref "U4") (pin "B4") (pinfunction "CVDDRTC_B4") (pintype "power_in"))
      (node (ref "U4") (pin "B5") (pinfunction "CVDDRTC1_B5") (pintype "power_in"))
      (node (ref "U5") (pin "B4") (pinfunction "CVDDRTC_B4") (pintype "power_in"))
      (node (ref "U5") (pin "B5") (pinfunction "CVDDRTC1_B5") (pintype "power_in"))
    )
    (net (code "343") (name "VCC_1V8") (class "Default")
      (node (ref "C71") (pin "1") (pinfunction "1_1") (pintype "passive"))
      (node (ref "C71-2") (pin "1") (pinfunction "1_1") (pintype "passive"))
      (node (ref "C75") (pin "1") (pinfunction "1_1") (pintype "passive"))
      (node (ref "C75-2") (pin "1") (pinfunction "1_1") (pintype "passive"))
      (node (ref "C87") (pin "1") (pinfunction "1_1") (pintype "passive"))
      (node (ref "C87-2") (pin "1") (pinfunction "1_1") (pintype "passive"))
      (node (ref "C98X") (pin "1") (pinfunction "1_1") (pintype "passive"))
      (node (ref "R106") (pin "1") (pinfunction "1_1") (pintype "passive"))
      (node (ref "R107") (pin "2") (pinfunction "2_2") (pintype "passive"))
      (node (ref "R118X") (pin "2") (pinfunction "2_2") (pintype "passive"))
      (node (ref "R63") (pin "2") (pinfunction "2_2") (pintype "passive"))
      (node (ref "R63-2") (pin "2") (pinfunction "2_2") (pintype "passive"))
      (node (ref "U11X") (pin "1") (pinfunction "IN_1") (pintype "power_in"))
      (node (ref "U11X") (pin "3") (pinfunction "EN_3") (pintype "input"))
      (node (ref "U4") (pin "B10") (pinfunction "LDOI_B10") (pintype "power_in"))
      (node (ref "U4") (pin "B14") (pinfunction "LDOI_B14") (pintype "power_in"))
      (node (ref "U4") (pin "C14") (pinfunction "LDOI_C14") (pintype "power_in"))
      (node (ref "U5") (pin "B10") (pinfunction "LDOI_B10") (pintype "power_in"))
      (node (ref "U5") (pin "B14") (pinfunction "LDOI_B14") (pintype "power_in"))
      (node (ref "U5") (pin "C14") (pinfunction "LDOI_C14") (pintype "power_in"))
    )
    (net (code "344") (name "VCC_3V3") (class "Default")
      (node (ref "C10") (pin "1") (pinfunction "1_1") (pintype "passive"))
      (node (ref "C104") (pin "1") (pinfunction "1_1") (pintype "passive"))
      (node (ref "C122") (pin "1") (pinfunction "1_1") (pintype "passive"))
      (node (ref "C15") (pin "1") (pinfunction "1_1") (pintype "passive"))
      (node (ref "C169X") (pin "1") (pinfunction "1_1") (pintype "passive"))
      (node (ref "C21") (pin "1") (pinfunction "1_1") (pintype "passive"))
      (node (ref "C218X") (pin "1") (pinfunction "1_1") (pintype "passive"))
      (node (ref "C81") (pin "1") (pinfunction "1_1") (pintype "passive"))
      (node (ref "C81-2") (pin "1") (pinfunction "1_1") (pintype "passive"))
      (node (ref "C9") (pin "1") (pinfunction "1_1") (pintype "passive"))
      (node (ref "FB3") (pin "1") (pinfunction "1_1") (pintype "passive"))
      (node (ref "J11") (pin "4") (pinfunction "VDD_4") (pintype "power_in"))
      (node (ref "J5") (pin "1") (pinfunction "1_1") (pintype "passive"))
      (node (ref "J5") (pin "5") (pinfunction "5_5") (pintype "passive"))
      (node (ref "J6") (pin "4") (pinfunction "VDD_4") (pintype "power_in"))
      (node (ref "J7") (pin "2") (pinfunction "2_2") (pintype "passive"))
      (node (ref "L8X") (pin "1") (pinfunction "1_1") (pintype "passive"))
      (node (ref "R1") (pin "2") (pinfunction "2_2") (pintype "passive"))
      (node (ref "R10") (pin "2") (pinfunction "2_2") (pintype "passive"))
      (node (ref "R100") (pin "2") (pinfunction "2_2") (pintype "passive"))
      (node (ref "R101") (pin "2") (pinfunction "2_2") (pintype "passive"))
      (node (ref "R102") (pin "2") (pinfunction "2_2") (pintype "passive"))
      (node (ref "R103") (pin "2") (pinfunction "2_2") (pintype "passive"))
      (node (ref "R109") (pin "2") (pinfunction "2_2") (pintype "passive"))
      (node (ref "R11") (pin "2") (pinfunction "2_2") (pintype "passive"))
      (node (ref "R134") (pin "2") (pinfunction "2_2") (pintype "passive"))
      (node (ref "R135") (pin "2") (pinfunction "2_2") (pintype "passive"))
      (node (ref "R141") (pin "2") (pinfunction "2_2") (pintype "passive"))
      (node (ref "R143X") (pin "2") (pinfunction "2_2") (pintype "passive"))
      (node (ref "R2") (pin "2") (pinfunction "2_2") (pintype "passive"))
      (node (ref "R222X") (pin "1") (pinfunction "1_1") (pintype "passive"))
      (node (ref "R2X") (pin "2") (pinfunction "2_2") (pintype "passive"))
      (node (ref "R3") (pin "2") (pinfunction "2_2") (pintype "passive"))
      (node (ref "R3X") (pin "2") (pinfunction "2_2") (pintype "passive"))
      (node (ref "R4") (pin "2") (pinfunction "2_2") (pintype "passive"))
      (node (ref "R4X") (pin "2") (pinfunction "2_2") (pintype "passive"))
      (node (ref "R5") (pin "1") (pinfunction "1_1") (pintype "passive"))
      (node (ref "R6") (pin "2") (pinfunction "2_2") (pintype "passive"))
      (node (ref "R7") (pin "2") (pinfunction "2_2") (pintype "passive"))
      (node (ref "R98") (pin "2") (pinfunction "2_2") (pintype "passive"))
      (node (ref "R99") (pin "2") (pinfunction "2_2") (pintype "passive"))
      (node (ref "U10X") (pin "8") (pinfunction "VCC_8") (pintype "power_in"))
      (node (ref "U14") (pin "1") (pinfunction "E/D_1") (pintype "input"))
      (node (ref "U14") (pin "4") (pinfunction "VCC_4") (pintype "power_in"))
      (node (ref "U18") (pin "20") (pinfunction "VCC_20") (pintype "power_in"))
      (node (ref "U3X") (pin "4") (pinfunction "VDD_4") (pintype "power_in"))
      (node (ref "U9") (pin "2") (pinfunction "VCC_2") (pintype "power_in"))
      (node (ref "U9-2") (pin "2") (pinfunction "VCC_2") (pintype "power_in"))
    )
    (net (code "345") (name "VCC_3V3_CLK") (class "Default")
      (node (ref "C213X") (pin "1") (pinfunction "1_1") (pintype "passive"))
      (node (ref "C215X") (pin "1") (pinfunction "1_1") (pintype "passive"))
      (node (ref "C216X") (pin "1") (pinfunction "1_1") (pintype "passive"))
      (node (ref "C217X") (pin "1") (pinfunction "1_1") (pintype "passive"))
      (node (ref "L8X") (pin "2") (pinfunction "2_2") (pintype "passive"))
      (node (ref "U15X") (pin "10") (pinfunction "VDD_3_10") (pintype "power_in"))
      (node (ref "U15X") (pin "14") (pinfunction "VDD_14") (pintype "power_in"))
      (node (ref "U15X") (pin "5") (pinfunction "VDD_2_5") (pintype "power_in"))
    )
    (net (code "346") (name "VCC_3V3_PWR") (class "Default")
      (node (ref "C94X") (pin "1") (pinfunction "1_1") (pintype "passive"))
      (node (ref "L7X") (pin "1") (pinfunction "1_1") (pintype "passive"))
      (node (ref "R119X") (pin "1") (pinfunction "1_1") (pintype "passive"))
      (node (ref "R15") (pin "1") (pinfunction "1_1") (pintype "passive"))
      (node (ref "R1X") (pin "1") (pinfunction "1_1") (pintype "passive"))
      (node (ref "R2X") (pin "1") (pinfunction "1_1") (pintype "passive"))
      (node (ref "R65X") (pin "2") (pinfunction "2_2") (pintype "passive"))
      (node (ref "R96X") (pin "1") (pinfunction "1_1") (pintype "passive"))
      (node (ref "R97") (pin "2") (pinfunction "2_2") (pintype "passive"))
      (node (ref "R97-2") (pin "2") (pinfunction "2_2") (pintype "passive"))
      (node (ref "TP5X") (pin "TP") (pinfunction "TP_TP") (pintype "input"))
    )
    (net (code "347") (name "VCC_3V3_USB") (class "Default")
      (node (ref "FB5") (pin "1") (pinfunction "1_1") (pintype "passive"))
      (node (ref "FB5-2") (pin "1") (pinfunction "1_1") (pintype "passive"))
      (node (ref "FB7") (pin "1") (pinfunction "1_1") (pintype "passive"))
      (node (ref "FB7-2") (pin "1") (pinfunction "1_1") (pintype "passive"))
      (node (ref "L3") (pin "1") (pinfunction "1_1") (pintype "passive"))
      (node (ref "L3-2") (pin "1") (pinfunction "1_1") (pintype "passive"))
      (node (ref "R96X") (pin "2") (pinfunction "2_2") (pintype "passive"))
    )
    (net (code "348") (name "VCC_USB_DUAL") (class "Default")
      (node (ref "C23X") (pin "1") (pinfunction "1_1") (pintype "passive"))
      (node (ref "C99X") (pin "1") (pinfunction "1_1") (pintype "passive"))
      (node (ref "D1") (pin "C") (pinfunction "C_C") (pintype "passive"))
      (node (ref "D3") (pin "C") (pinfunction "C_C") (pintype "passive"))
      (node (ref "D4") (pin "C") (pinfunction "C_C") (pintype "passive"))
      (node (ref "D5") (pin "C") (pinfunction "C_C") (pintype "passive"))
      (node (ref "DS1") (pin "A") (pinfunction "A_A") (pintype "passive"))
      (node (ref "U12X") (pin "3") (pinfunction "VIN_3") (pintype "power_in"))
      (node (ref "U12X") (pin "5") (pinfunction "EN_5") (pintype "input"))
      (node (ref "U1X") (pin "3") (pinfunction "VIN_3") (pintype "power_in"))
      (node (ref "U1X") (pin "5") (pinfunction "EN_5") (pintype "input"))
    )
    (net (code "349") (name "VDD_IO1") (class "Default")
      (node (ref "C82") (pin "1") (pinfunction "1_1") (pintype "passive"))
      (node (ref "R119X") (pin "2") (pinfunction "2_2") (pintype "passive"))
      (node (ref "R13") (pin "2") (pinfunction "2_2") (pintype "passive"))
      (node (ref "R14") (pin "2") (pinfunction "2_2") (pintype "passive"))
      (node (ref "R16") (pin "2") (pinfunction "2_2") (pintype "passive"))
      (node (ref "R22") (pin "2") (pinfunction "2_2") (pintype "passive"))
      (node (ref "R25") (pin "2") (pinfunction "2_2") (pintype "passive"))
      (node (ref "R37") (pin "2") (pinfunction "2_2") (pintype "passive"))
      (node (ref "R41") (pin "2") (pinfunction "2_2") (pintype "passive"))
      (node (ref "R50") (pin "2") (pinfunction "2_2") (pintype "passive"))
      (node (ref "R51") (pin "2") (pinfunction "2_2") (pintype "passive"))
      (node (ref "R52") (pin "2") (pinfunction "2_2") (pintype "passive"))
      (node (ref "R72") (pin "2") (pinfunction "2_2") (pintype "passive"))
      (node (ref "R73") (pin "2") (pinfunction "2_2") (pintype "passive"))
      (node (ref "U4") (pin "C3") (pinfunction "DVDDRTC_C3") (pintype "power_in"))
    )
    (net (code "350") (name "VDD_IO1_CPU") (class "Default")
      (node (ref "C1") (pin "1") (pinfunction "1_1") (pintype "passive"))
      (node (ref "C28") (pin "1") (pinfunction "1_1") (pintype "passive"))
      (node (ref "C29") (pin "1") (pinfunction "1_1") (pintype "passive"))
      (node (ref "C30") (pin "1") (pinfunction "1_1") (pintype "passive"))
      (node (ref "C32") (pin "1") (pinfunction "1_1") (pintype "passive"))
      (node (ref "C45") (pin "1") (pinfunction "1_1") (pintype "passive"))
      (node (ref "C72") (pin "1") (pinfunction "1_1") (pintype "passive"))
      (node (ref "R97") (pin "1") (pinfunction "1_1") (pintype "passive"))
      (node (ref "U4") (pin "C6") (pinfunction "DVDDIO_C6") (pintype "power_in"))
      (node (ref "U4") (pin "L4") (pinfunction "DVDDIO_L4") (pintype "power_in"))
      (node (ref "U4") (pin "M3") (pinfunction "DVDDIO_M3") (pintype "power_in"))
      (node (ref "U4") (pin "M4") (pinfunction "DVDDIO_M4") (pintype "power_in"))
      (node (ref "U4") (pin "N11") (pinfunction "DVDDIO_N11") (pintype "power_in"))
      (node (ref "U4") (pin "N14") (pinfunction "DVDDIO_N14") (pintype "power_in"))
      (node (ref "U4") (pin "N8") (pinfunction "DVDDIO_N8") (pintype "power_in"))
    )
    (net (code "351") (name "VDD_IO2") (class "Default")
      (node (ref "C82-2") (pin "1") (pinfunction "1_1") (pintype "passive"))
      (node (ref "R13-2") (pin "2") (pinfunction "2_2") (pintype "passive"))
      (node (ref "R14-2") (pin "2") (pinfunction "2_2") (pintype "passive"))
      (node (ref "R15") (pin "2") (pinfunction "2_2") (pintype "passive"))
      (node (ref "R37-2") (pin "2") (pinfunction "2_2") (pintype "passive"))
      (node (ref "R41-2") (pin "2") (pinfunction "2_2") (pintype "passive"))
      (node (ref "R50-2") (pin "2") (pinfunction "2_2") (pintype "passive"))
      (node (ref "R51-2") (pin "2") (pinfunction "2_2") (pintype "passive"))
      (node (ref "R52-1") (pin "2") (pinfunction "2_2") (pintype "passive"))
      (node (ref "R52-2") (pin "2") (pinfunction "2_2") (pintype "passive"))
      (node (ref "R72-2") (pin "2") (pinfunction "2_2") (pintype "passive"))
      (node (ref "R73-2") (pin "2") (pinfunction "2_2") (pintype "passive"))
      (node (ref "U5") (pin "C3") (pinfunction "DVDDRTC_C3") (pintype "power_in"))
    )
    (net (code "352") (name "VDD_IO2_CPU") (class "Default")
      (node (ref "C1-2") (pin "1") (pinfunction "1_1") (pintype "passive"))
      (node (ref "C28-2") (pin "1") (pinfunction "1_1") (pintype "passive"))
      (node (ref "C29-2") (pin "1") (pinfunction "1_1") (pintype "passive"))
      (node (ref "C30-2") (pin "1") (pinfunction "1_1") (pintype "passive"))
      (node (ref "C32-2") (pin "1") (pinfunction "1_1") (pintype "passive"))
      (node (ref "C45-2") (pin "1") (pinfunction "1_1") (pintype "passive"))
      (node (ref "C72-2") (pin "1") (pinfunction "1_1") (pintype "passive"))
      (node (ref "R97-2") (pin "1") (pinfunction "1_1") (pintype "passive"))
      (node (ref "U5") (pin "C6") (pinfunction "DVDDIO_C6") (pintype "power_in"))
      (node (ref "U5") (pin "L4") (pinfunction "DVDDIO_L4") (pintype "power_in"))
      (node (ref "U5") (pin "M3") (pinfunction "DVDDIO_M3") (pintype "power_in"))
      (node (ref "U5") (pin "M4") (pinfunction "DVDDIO_M4") (pintype "power_in"))
      (node (ref "U5") (pin "N11") (pinfunction "DVDDIO_N11") (pintype "power_in"))
      (node (ref "U5") (pin "N14") (pinfunction "DVDDIO_N14") (pintype "power_in"))
      (node (ref "U5") (pin "N8") (pinfunction "DVDDIO_N8") (pintype "power_in"))
    )
    (net (code "353") (name "VPHY") (class "Default")
      (node (ref "C44") (pin "2") (pinfunction "2_2") (pintype "passive"))
      (node (ref "C47") (pin "2") (pinfunction "2_2") (pintype "passive"))
      (node (ref "L4") (pin "2") (pinfunction "2_2") (pintype "passive"))
      (node (ref "U6") (pin "4") (pinfunction "VPHY_4") (pintype "power_in"))
    )
    (net (code "354") (name "VPLL") (class "Default")
      (node (ref "C61") (pin "2") (pinfunction "2_2") (pintype "passive"))
      (node (ref "C76") (pin "2") (pinfunction "2_2") (pintype "passive"))
      (node (ref "L5") (pin "2") (pinfunction "2_2") (pintype "passive"))
      (node (ref "U6") (pin "9") (pinfunction "VPLL_9") (pintype "power_in"))
    )
    (net (code "355") (name "VSS1RTC") (class "Default")
      (node (ref "C90") (pin "1") (pinfunction "1_1") (pintype "passive"))
      (node (ref "C91") (pin "1") (pinfunction "1_1") (pintype "passive"))
      (node (ref "U4") (pin "C5") (pinfunction "VSSRTC_C5") (pintype "power_in"))
    )
    (net (code "356") (name "VSS2RTC") (class "Default")
      (node (ref "C90-2") (pin "1") (pinfunction "1_1") (pintype "passive"))
      (node (ref "C91-2") (pin "1") (pinfunction "1_1") (pintype "passive"))
      (node (ref "U5") (pin "C5") (pinfunction "VSSRTC_C5") (pintype "power_in"))
    )
    (net (code "357") (name "VUSB") (class "Default")
      (node (ref "C93") (pin "1") (pinfunction "1_1") (pintype "passive"))
      (node (ref "J2") (pin "VUSB") (pinfunction "VBUS_VUSB") (pintype "bidirectional"))
      (node (ref "L1") (pin "1") (pinfunction "1_1") (pintype "passive"))
      (node (ref "U7") (pin "1") (pinfunction "VCC_1") (pintype "power_in"))
    )
    (net (code "358") (name "WAKEUP") (class "Default")
      (node (ref "R59") (pin "2") (pinfunction "2_2") (pintype "passive"))
      (node (ref "U4") (pin "A5") (pinfunction "WAKEUP_A5") (pintype "bidirectional"))
    )
    (net (code "359") (name "WAKEUP2") (class "Default")
      (node (ref "R59-2") (pin "2") (pinfunction "2_2") (pintype "passive"))
      (node (ref "U5") (pin "A5") (pinfunction "WAKEUP_A5") (pintype "bidirectional"))
    )
    (net (code "360") (name "XF") (class "Default")
      (node (ref "R67") (pin "2") (pinfunction "2_2") (pintype "passive"))
      (node (ref "U4") (pin "J3") (pinfunction "XF_J3") (pintype "output"))
    )
    (net (code "361") (name "XF2") (class "Default")
      (node (ref "R105X") (pin "2") (pinfunction "2_2") (pintype "passive"))
      (node (ref "U5") (pin "J3") (pinfunction "XF_J3") (pintype "output"))
    )
    (net (code "362") (name "unconnected-(CF1-2-Pad2@2)") (class "Default")
      (node (ref "CF1") (pin "2@2") (pinfunction "2_2@2") (pintype "passive"))
    )
    (net (code "363") (name "unconnected-(D8-C1A2-Pad3)") (class "Default")
      (node (ref "D8") (pin "3") (pinfunction "C1A2_3") (pintype "passive"))
    )
    (net (code "364") (name "unconnected-(J1-2-PadID)") (class "Default")
      (node (ref "J1-2") (pin "ID") (pinfunction "ID_ID") (pintype "bidirectional"))
    )
    (net (code "365") (name "unconnected-(J1-PadID)") (class "Default")
      (node (ref "J1") (pin "ID") (pinfunction "ID_ID") (pintype "bidirectional"))
    )
    (net (code "366") (name "unconnected-(J4-RN-Pad5)") (class "Default")
      (node (ref "J4") (pin "5") (pinfunction "RN_5") (pintype "passive"))
    )
    (net (code "367") (name "unconnected-(J4-TN-Pad4)") (class "Default")
      (node (ref "J4") (pin "4") (pinfunction "TN_4") (pintype "passive"))
    )
    (net (code "368") (name "unconnected-(J6-Pad10)") (class "Default")
      (node (ref "J6") (pin "10") (pinfunction "10_10") (pintype "no_connect"))
    )
    (net (code "369") (name "unconnected-(J6-Pad12)") (class "Default")
      (node (ref "J6") (pin "12") (pinfunction "12_12") (pintype "no_connect"))
    )
    (net (code "370") (name "unconnected-(J6-Pad13)") (class "Default")
      (node (ref "J6") (pin "13") (pinfunction "13_13") (pintype "no_connect"))
    )
    (net (code "371") (name "unconnected-(J6-Pad14)") (class "Default")
      (node (ref "J6") (pin "14") (pinfunction "14_14") (pintype "no_connect"))
    )
    (net (code "372") (name "unconnected-(J9-PadSN)") (class "Default")
      (node (ref "J9") (pin "SN") (pinfunction "SN_SN") (pintype "passive"))
    )
    (net (code "373") (name "unconnected-(J9-PadTN)") (class "Default")
      (node (ref "J9") (pin "TN") (pinfunction "TN_TN") (pintype "passive"))
    )
    (net (code "374") (name "unconnected-(J10-PadSN)") (class "Default")
      (node (ref "J10") (pin "SN") (pinfunction "SN_SN") (pintype "passive"))
    )
    (net (code "375") (name "unconnected-(J10-PadTN)") (class "Default")
      (node (ref "J10") (pin "TN") (pinfunction "TN_TN") (pintype "passive"))
    )
    (net (code "376") (name "unconnected-(J11-Pad10)") (class "Default")
      (node (ref "J11") (pin "10") (pinfunction "10_10") (pintype "no_connect"))
    )
    (net (code "377") (name "unconnected-(J11-Pad12)") (class "Default")
      (node (ref "J11") (pin "12") (pinfunction "12_12") (pintype "no_connect"))
    )
    (net (code "378") (name "unconnected-(J11-Pad13)") (class "Default")
      (node (ref "J11") (pin "13") (pinfunction "13_13") (pintype "no_connect"))
    )
    (net (code "379") (name "unconnected-(J11-Pad14)") (class "Default")
      (node (ref "J11") (pin "14") (pinfunction "14_14") (pintype "no_connect"))
    )
    (net (code "380") (name "unconnected-(SW2A-O-Pad3)") (class "Default")
      (node (ref "SW2") (pin "3") (pinfunction "O_3") (pintype "passive"))
    )
    (net (code "381") (name "unconnected-(U2-DC-Pad7)") (class "Default")
      (node (ref "U2") (pin "7") (pinfunction "DC_7") (pintype "no_connect"))
    )
    (net (code "382") (name "unconnected-(U2-NC-Pad6)") (class "Default")
      (node (ref "U2") (pin "6") (pinfunction "NC_6") (pintype "no_connect"))
    )
    (net (code "383") (name "unconnected-(U3X-NC-Pad1)") (class "Default")
      (node (ref "U3X") (pin "1") (pinfunction "NC_1") (pintype "no_connect"))
    )
    (net (code "384") (name "unconnected-(U4B-RSV7-PadE1)") (class "Default")
      (node (ref "U4") (pin "E1") (pinfunction "RSV7_E1") (pintype "input"))
    )
    (net (code "385") (name "unconnected-(U4B-RSV8-PadF1)") (class "Default")
      (node (ref "U4") (pin "F1") (pinfunction "RSV8_F1") (pintype "input"))
    )
    (net (code "386") (name "unconnected-(U4B-RSV9-PadG1)") (class "Default")
      (node (ref "U4") (pin "G1") (pinfunction "RSV9_G1") (pintype "input"))
    )
    (net (code "387") (name "unconnected-(U4B-RSV10-PadH1)") (class "Default")
      (node (ref "U4") (pin "H1") (pinfunction "RSV10_H1") (pintype "input"))
    )
    (net (code "388") (name "unconnected-(U4B-RSV11-PadE2)") (class "Default")
      (node (ref "U4") (pin "E2") (pinfunction "RSV11_E2") (pintype "input"))
    )
    (net (code "389") (name "unconnected-(U4B-RSV12-PadG2)") (class "Default")
      (node (ref "U4") (pin "G2") (pinfunction "RSV12_G2") (pintype "input"))
    )
    (net (code "390") (name "unconnected-(U4B-USB_MXO-PadD14)") (class "Default")
      (node (ref "U4") (pin "D14") (pinfunction "USB_MXO_D14") (pintype "output"))
    )
    (net (code "391") (name "unconnected-(U5B-RSV7-PadE1)") (class "Default")
      (node (ref "U5") (pin "E1") (pinfunction "RSV7_E1") (pintype "input"))
    )
    (net (code "392") (name "unconnected-(U5B-RSV8-PadF1)") (class "Default")
      (node (ref "U5") (pin "F1") (pinfunction "RSV8_F1") (pintype "input"))
    )
    (net (code "393") (name "unconnected-(U5B-RSV9-PadG1)") (class "Default")
      (node (ref "U5") (pin "G1") (pinfunction "RSV9_G1") (pintype "input"))
    )
    (net (code "394") (name "unconnected-(U5B-RSV10-PadH1)") (class "Default")
      (node (ref "U5") (pin "H1") (pinfunction "RSV10_H1") (pintype "input"))
    )
    (net (code "395") (name "unconnected-(U5B-RSV11-PadE2)") (class "Default")
      (node (ref "U5") (pin "E2") (pinfunction "RSV11_E2") (pintype "input"))
    )
    (net (code "396") (name "unconnected-(U5B-RSV12-PadG2)") (class "Default")
      (node (ref "U5") (pin "G2") (pinfunction "RSV12_G2") (pintype "input"))
    )
    (net (code "397") (name "unconnected-(U5B-USB_MXO-PadD14)") (class "Default")
      (node (ref "U5") (pin "D14") (pinfunction "USB_MXO_D14") (pintype "output"))
    )
    (net (code "398") (name "unconnected-(U6-ACBUS6-Pad33)") (class "Default")
      (node (ref "U6") (pin "33") (pinfunction "ACBUS6_33") (pintype "bidirectional"))
    )
    (net (code "399") (name "unconnected-(U6-ACBUS7-Pad34)") (class "Default")
      (node (ref "U6") (pin "34") (pinfunction "ACBUS7_34") (pintype "bidirectional"))
    )
    (net (code "400") (name "unconnected-(U6-ADBUS5-Pad22)") (class "Default")
      (node (ref "U6") (pin "22") (pinfunction "ADBUS5_22") (pintype "bidirectional"))
    )
    (net (code "401") (name "unconnected-(U6-BCBUS0-Pad48)") (class "Default")
      (node (ref "U6") (pin "48") (pinfunction "BCBUS0_48") (pintype "bidirectional"))
    )
    (net (code "402") (name "unconnected-(U6-BCBUS1-Pad52)") (class "Default")
      (node (ref "U6") (pin "52") (pinfunction "BCBUS1_52") (pintype "bidirectional"))
    )
    (net (code "403") (name "unconnected-(U6-BCBUS2-Pad53)") (class "Default")
      (node (ref "U6") (pin "53") (pinfunction "BCBUS2_53") (pintype "bidirectional"))
    )
    (net (code "404") (name "unconnected-(U6-BCBUS3-Pad54)") (class "Default")
      (node (ref "U6") (pin "54") (pinfunction "BCBUS3_54") (pintype "bidirectional"))
    )
    (net (code "405") (name "unconnected-(U6-BCBUS4-Pad55)") (class "Default")
      (node (ref "U6") (pin "55") (pinfunction "BCBUS4_55") (pintype "bidirectional"))
    )
    (net (code "406") (name "unconnected-(U6-BCBUS5-Pad57)") (class "Default")
      (node (ref "U6") (pin "57") (pinfunction "BCBUS5_57") (pintype "bidirectional"))
    )
    (net (code "407") (name "unconnected-(U6-BCBUS6-Pad58)") (class "Default")
      (node (ref "U6") (pin "58") (pinfunction "BCBUS6_58") (pintype "bidirectional"))
    )
    (net (code "408") (name "unconnected-(U6-BCBUS7-Pad59)") (class "Default")
      (node (ref "U6") (pin "59") (pinfunction "BCBUS7_59") (pintype "bidirectional"))
    )
    (net (code "409") (name "unconnected-(U6-BDBUS4-Pad43)") (class "Default")
      (node (ref "U6") (pin "43") (pinfunction "BDBUS4_43") (pintype "output"))
    )
    (net (code "410") (name "unconnected-(U6-BDBUS5-Pad44)") (class "Default")
      (node (ref "U6") (pin "44") (pinfunction "BDBUS5_44") (pintype "input"))
    )
    (net (code "411") (name "unconnected-(U6-BDBUS6-Pad45)") (class "Default")
      (node (ref "U6") (pin "45") (pinfunction "BDBUS6_45") (pintype "input"))
    )
    (net (code "412") (name "unconnected-(U6-BDBUS7-Pad46)") (class "Default")
      (node (ref "U6") (pin "46") (pinfunction "BDBUS7_46") (pintype "input"))
    )
    (net (code "413") (name "unconnected-(U6-SUSPEND#-Pad36)") (class "Default")
      (node (ref "U6") (pin "36") (pinfunction "SUSPEND#_36") (pintype "output"))
    )
    (net (code "414") (name "unconnected-(U6-TEST-Pad13)") (class "Default")
      (node (ref "U6") (pin "13") (pinfunction "TEST_13") (pintype "input"))
    )
    (net (code "415") (name "unconnected-(U6-XTOUT-Pad3)") (class "Default")
      (node (ref "U6") (pin "3") (pinfunction "XTOUT_3") (pintype "output"))
    )
    (net (code "416") (name "unconnected-(U7-NC-Pad2)") (class "Default")
      (node (ref "U7") (pin "2") (pinfunction "NC_2") (pintype "no_connect"))
    )
    (net (code "417") (name "unconnected-(U9-2-NC-Pad3)") (class "Default")
      (node (ref "U9-2") (pin "3") (pinfunction "NC_3") (pintype "no_connect"))
    )
    (net (code "418") (name "unconnected-(U9-2-NC-Pad4)") (class "Default")
      (node (ref "U9-2") (pin "4") (pinfunction "NC_4") (pintype "no_connect"))
    )
    (net (code "419") (name "unconnected-(U9-2-NC-Pad5)") (class "Default")
      (node (ref "U9-2") (pin "5") (pinfunction "NC_5") (pintype "no_connect"))
    )
    (net (code "420") (name "unconnected-(U9-2-NC-Pad6)") (class "Default")
      (node (ref "U9-2") (pin "6") (pinfunction "NC_6") (pintype "no_connect"))
    )
    (net (code "421") (name "unconnected-(U9-2-NC-Pad11)") (class "Default")
      (node (ref "U9-2") (pin "11") (pinfunction "NC_11") (pintype "no_connect"))
    )
    (net (code "422") (name "unconnected-(U9-2-NC-Pad12)") (class "Default")
      (node (ref "U9-2") (pin "12") (pinfunction "NC_12") (pintype "no_connect"))
    )
    (net (code "423") (name "unconnected-(U9-2-NC-Pad13)") (class "Default")
      (node (ref "U9-2") (pin "13") (pinfunction "NC_13") (pintype "no_connect"))
    )
    (net (code "424") (name "unconnected-(U9-2-NC-Pad14)") (class "Default")
      (node (ref "U9-2") (pin "14") (pinfunction "NC_14") (pintype "no_connect"))
    )
    (net (code "425") (name "unconnected-(U9-NC-Pad3)") (class "Default")
      (node (ref "U9") (pin "3") (pinfunction "NC_3") (pintype "no_connect"))
    )
    (net (code "426") (name "unconnected-(U9-NC-Pad4)") (class "Default")
      (node (ref "U9") (pin "4") (pinfunction "NC_4") (pintype "no_connect"))
    )
    (net (code "427") (name "unconnected-(U9-NC-Pad5)") (class "Default")
      (node (ref "U9") (pin "5") (pinfunction "NC_5") (pintype "no_connect"))
    )
    (net (code "428") (name "unconnected-(U9-NC-Pad6)") (class "Default")
      (node (ref "U9") (pin "6") (pinfunction "NC_6") (pintype "no_connect"))
    )
    (net (code "429") (name "unconnected-(U9-NC-Pad11)") (class "Default")
      (node (ref "U9") (pin "11") (pinfunction "NC_11") (pintype "no_connect"))
    )
    (net (code "430") (name "unconnected-(U9-NC-Pad12)") (class "Default")
      (node (ref "U9") (pin "12") (pinfunction "NC_12") (pintype "no_connect"))
    )
    (net (code "431") (name "unconnected-(U9-NC-Pad13)") (class "Default")
      (node (ref "U9") (pin "13") (pinfunction "NC_13") (pintype "no_connect"))
    )
    (net (code "432") (name "unconnected-(U9-NC-Pad14)") (class "Default")
      (node (ref "U9") (pin "14") (pinfunction "NC_14") (pintype "no_connect"))
    )
    (net (code "433") (name "unconnected-(U17-GPIO{slash}MFP5_(32)-Pad32)") (class "Default")
      (node (ref "U17") (pin "32") (pinfunction "GPIO/MFP5_(32)_32") (pintype "input"))
    )
    (net (code "434") (name "unconnected-(U17-IN1_L-Pad13)") (class "Default")
      (node (ref "U17") (pin "13") (pinfunction "IN1_L_13") (pintype "input"))
    )
    (net (code "435") (name "unconnected-(U17-IN1_R-Pad14)") (class "Default")
      (node (ref "U17") (pin "14") (pinfunction "IN1_R_14") (pintype "input"))
    )
    (net (code "436") (name "unconnected-(U17-IN3_L-Pad20)") (class "Default")
      (node (ref "U17") (pin "20") (pinfunction "IN3_L_20") (pintype "input"))
    )
    (net (code "437") (name "unconnected-(U17-IN3_R-Pad21)") (class "Default")
      (node (ref "U17") (pin "21") (pinfunction "IN3_R_21") (pintype "input"))
    )
    (net (code "438") (name "unconnected-(U17-MISO{slash}MFP4-Pad11)") (class "Default")
      (node (ref "U17") (pin "11") (pinfunction "MISO/MFP4_11") (pintype "output"))
    )
    (net (code "439") (name "unconnected-(U17-SCLK{slash}MFP3-Pad8)") (class "Default")
      (node (ref "U17") (pin "8") (pinfunction "SCLK/MFP3_8") (pintype "input"))
    )
    (net (code "440") (name "unconnected-(U18-NC-Pad1)") (class "Default")
      (node (ref "U18") (pin "1") (pinfunction "NC_1") (pintype "no_connect"))
    )
  )
)
